# UCirKitBreadboardWithEverything2.net
KiCad netlist of a schematic drawn in EAGLE
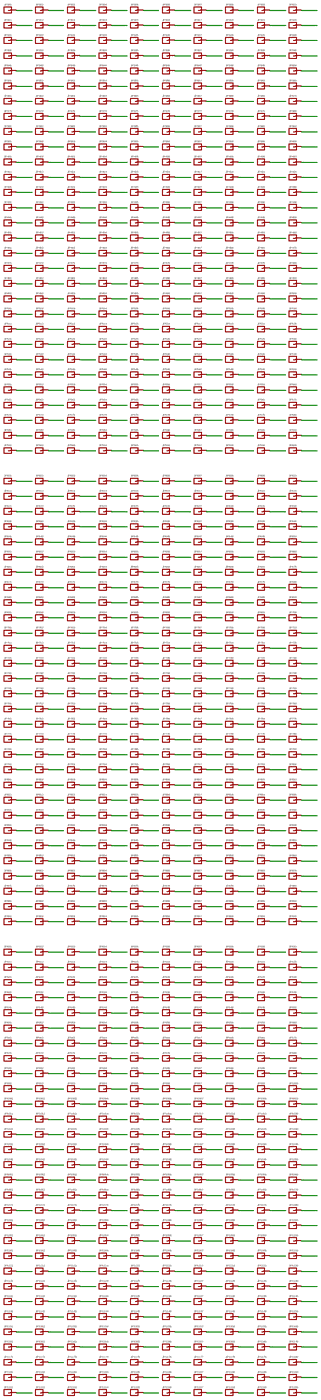
[diagram p0: schematic, sheet 1, overview]
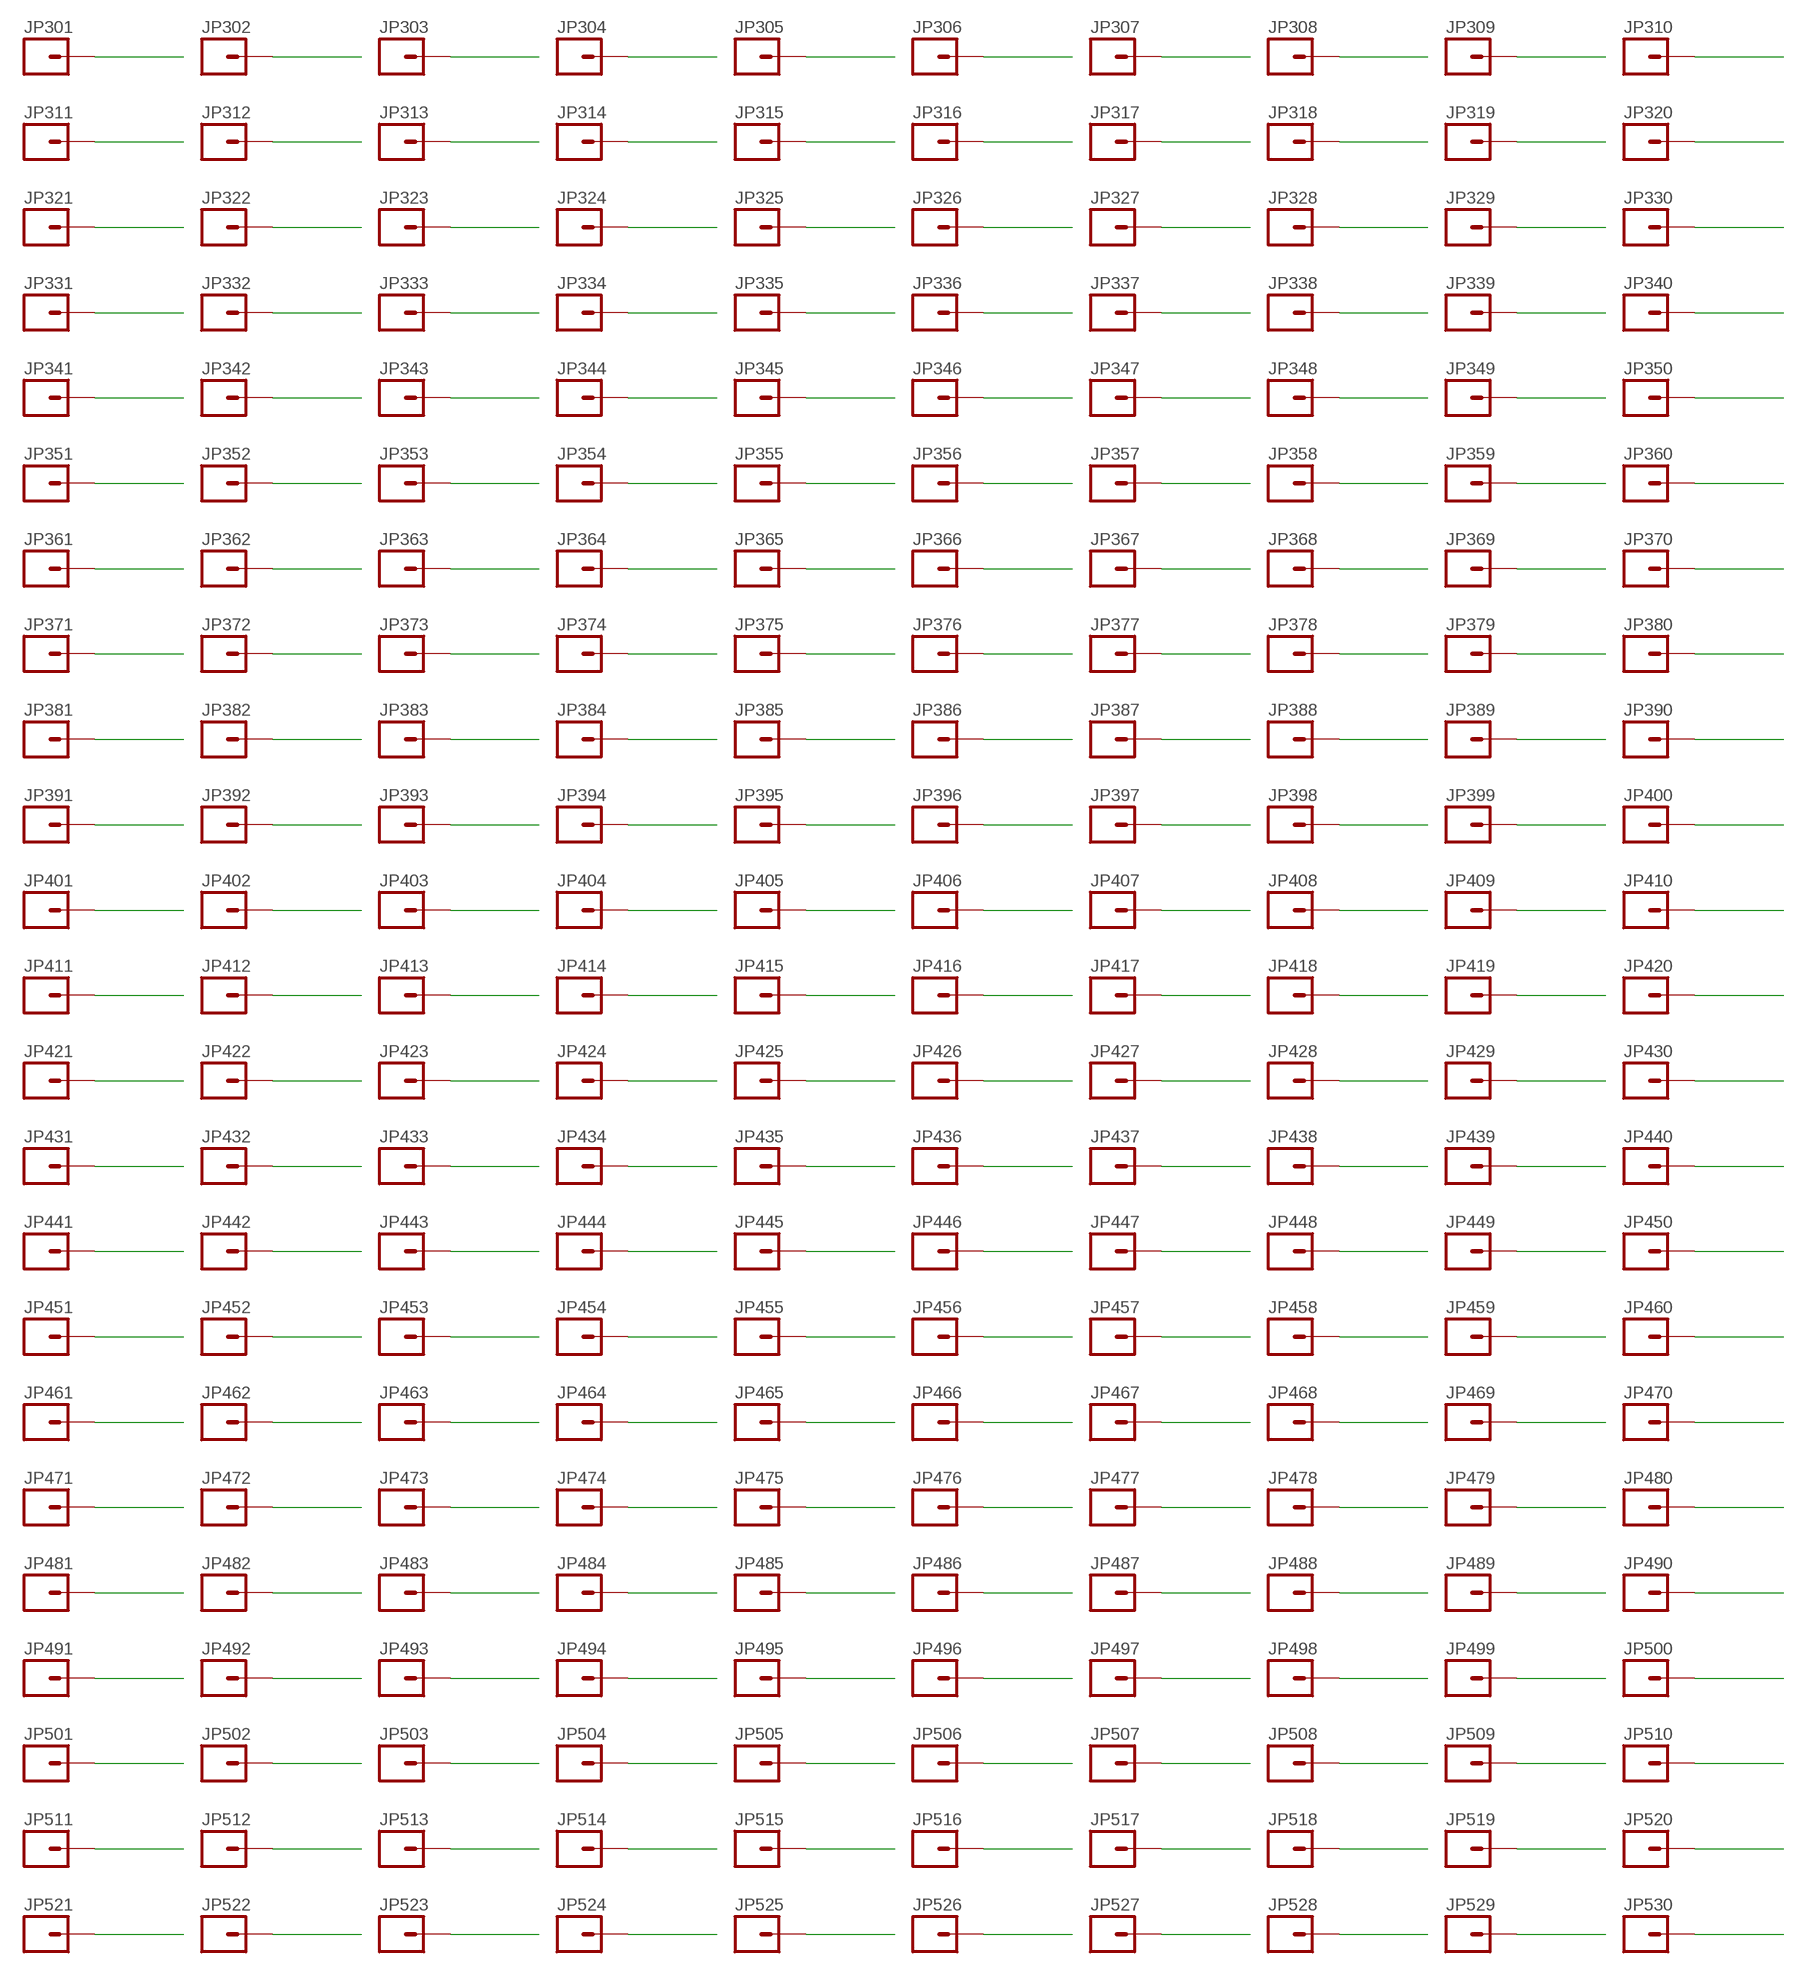
[diagram p1: schematic, sheet 1, part 1 of 4]
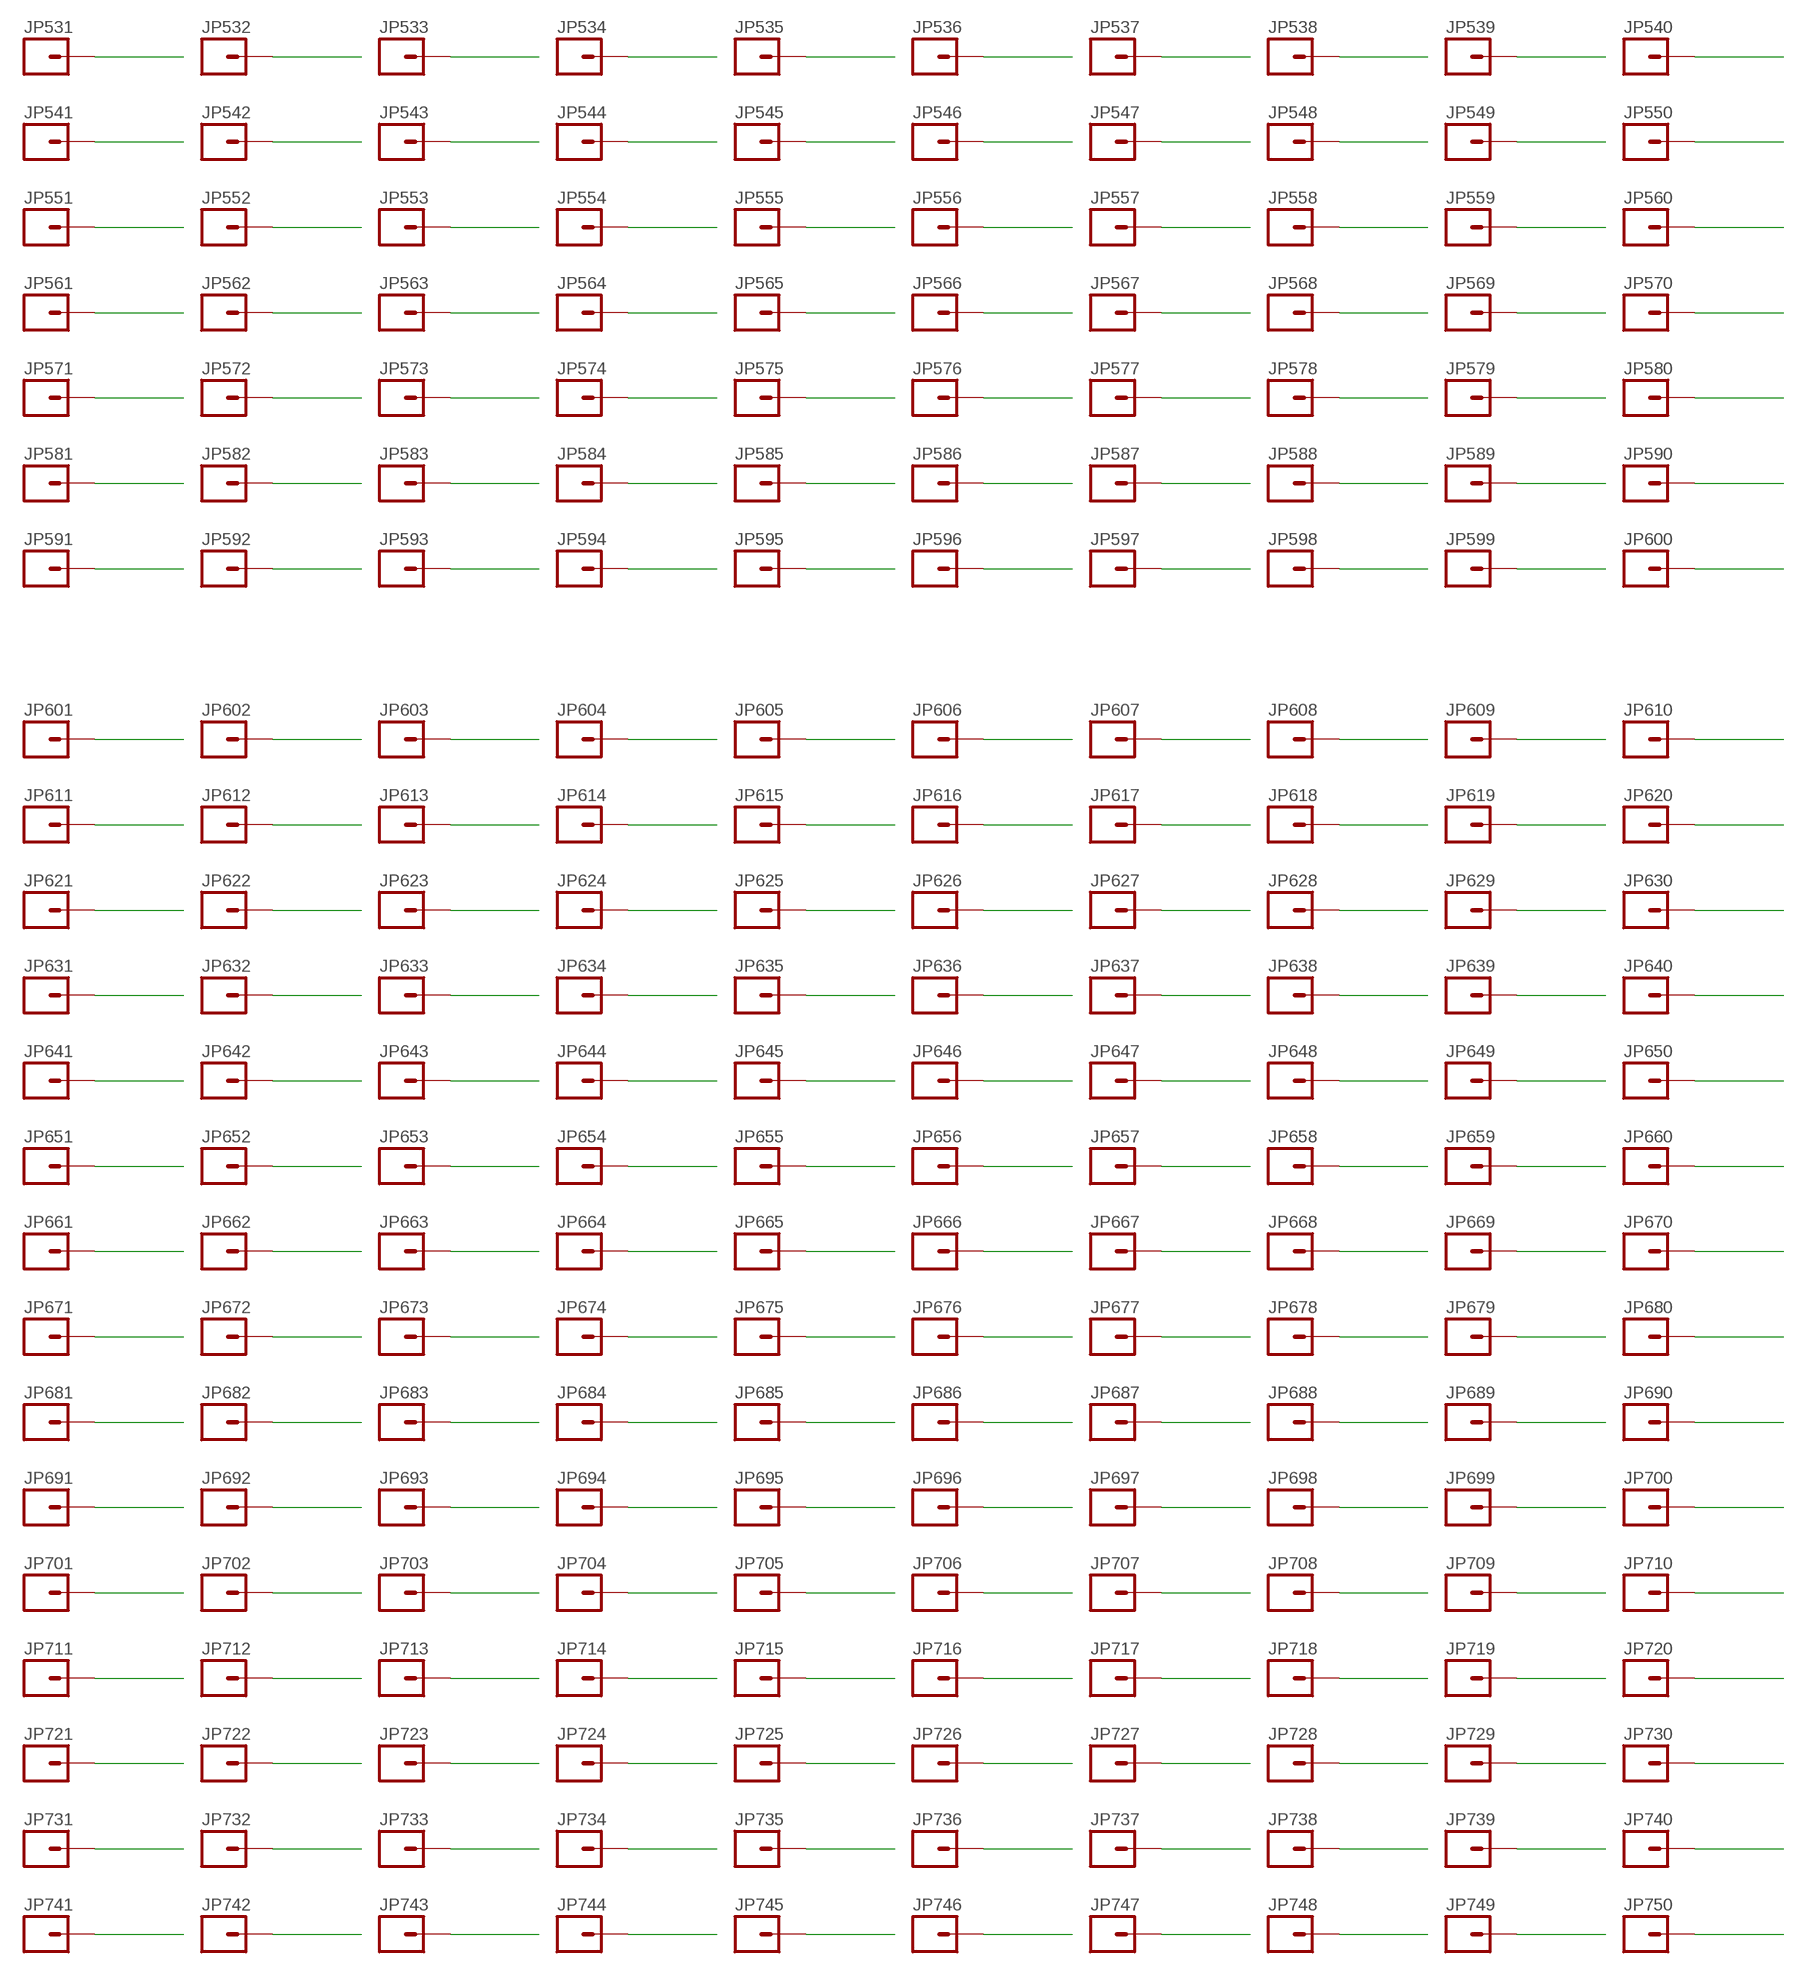
[diagram p2: schematic, sheet 1, part 2 of 4]
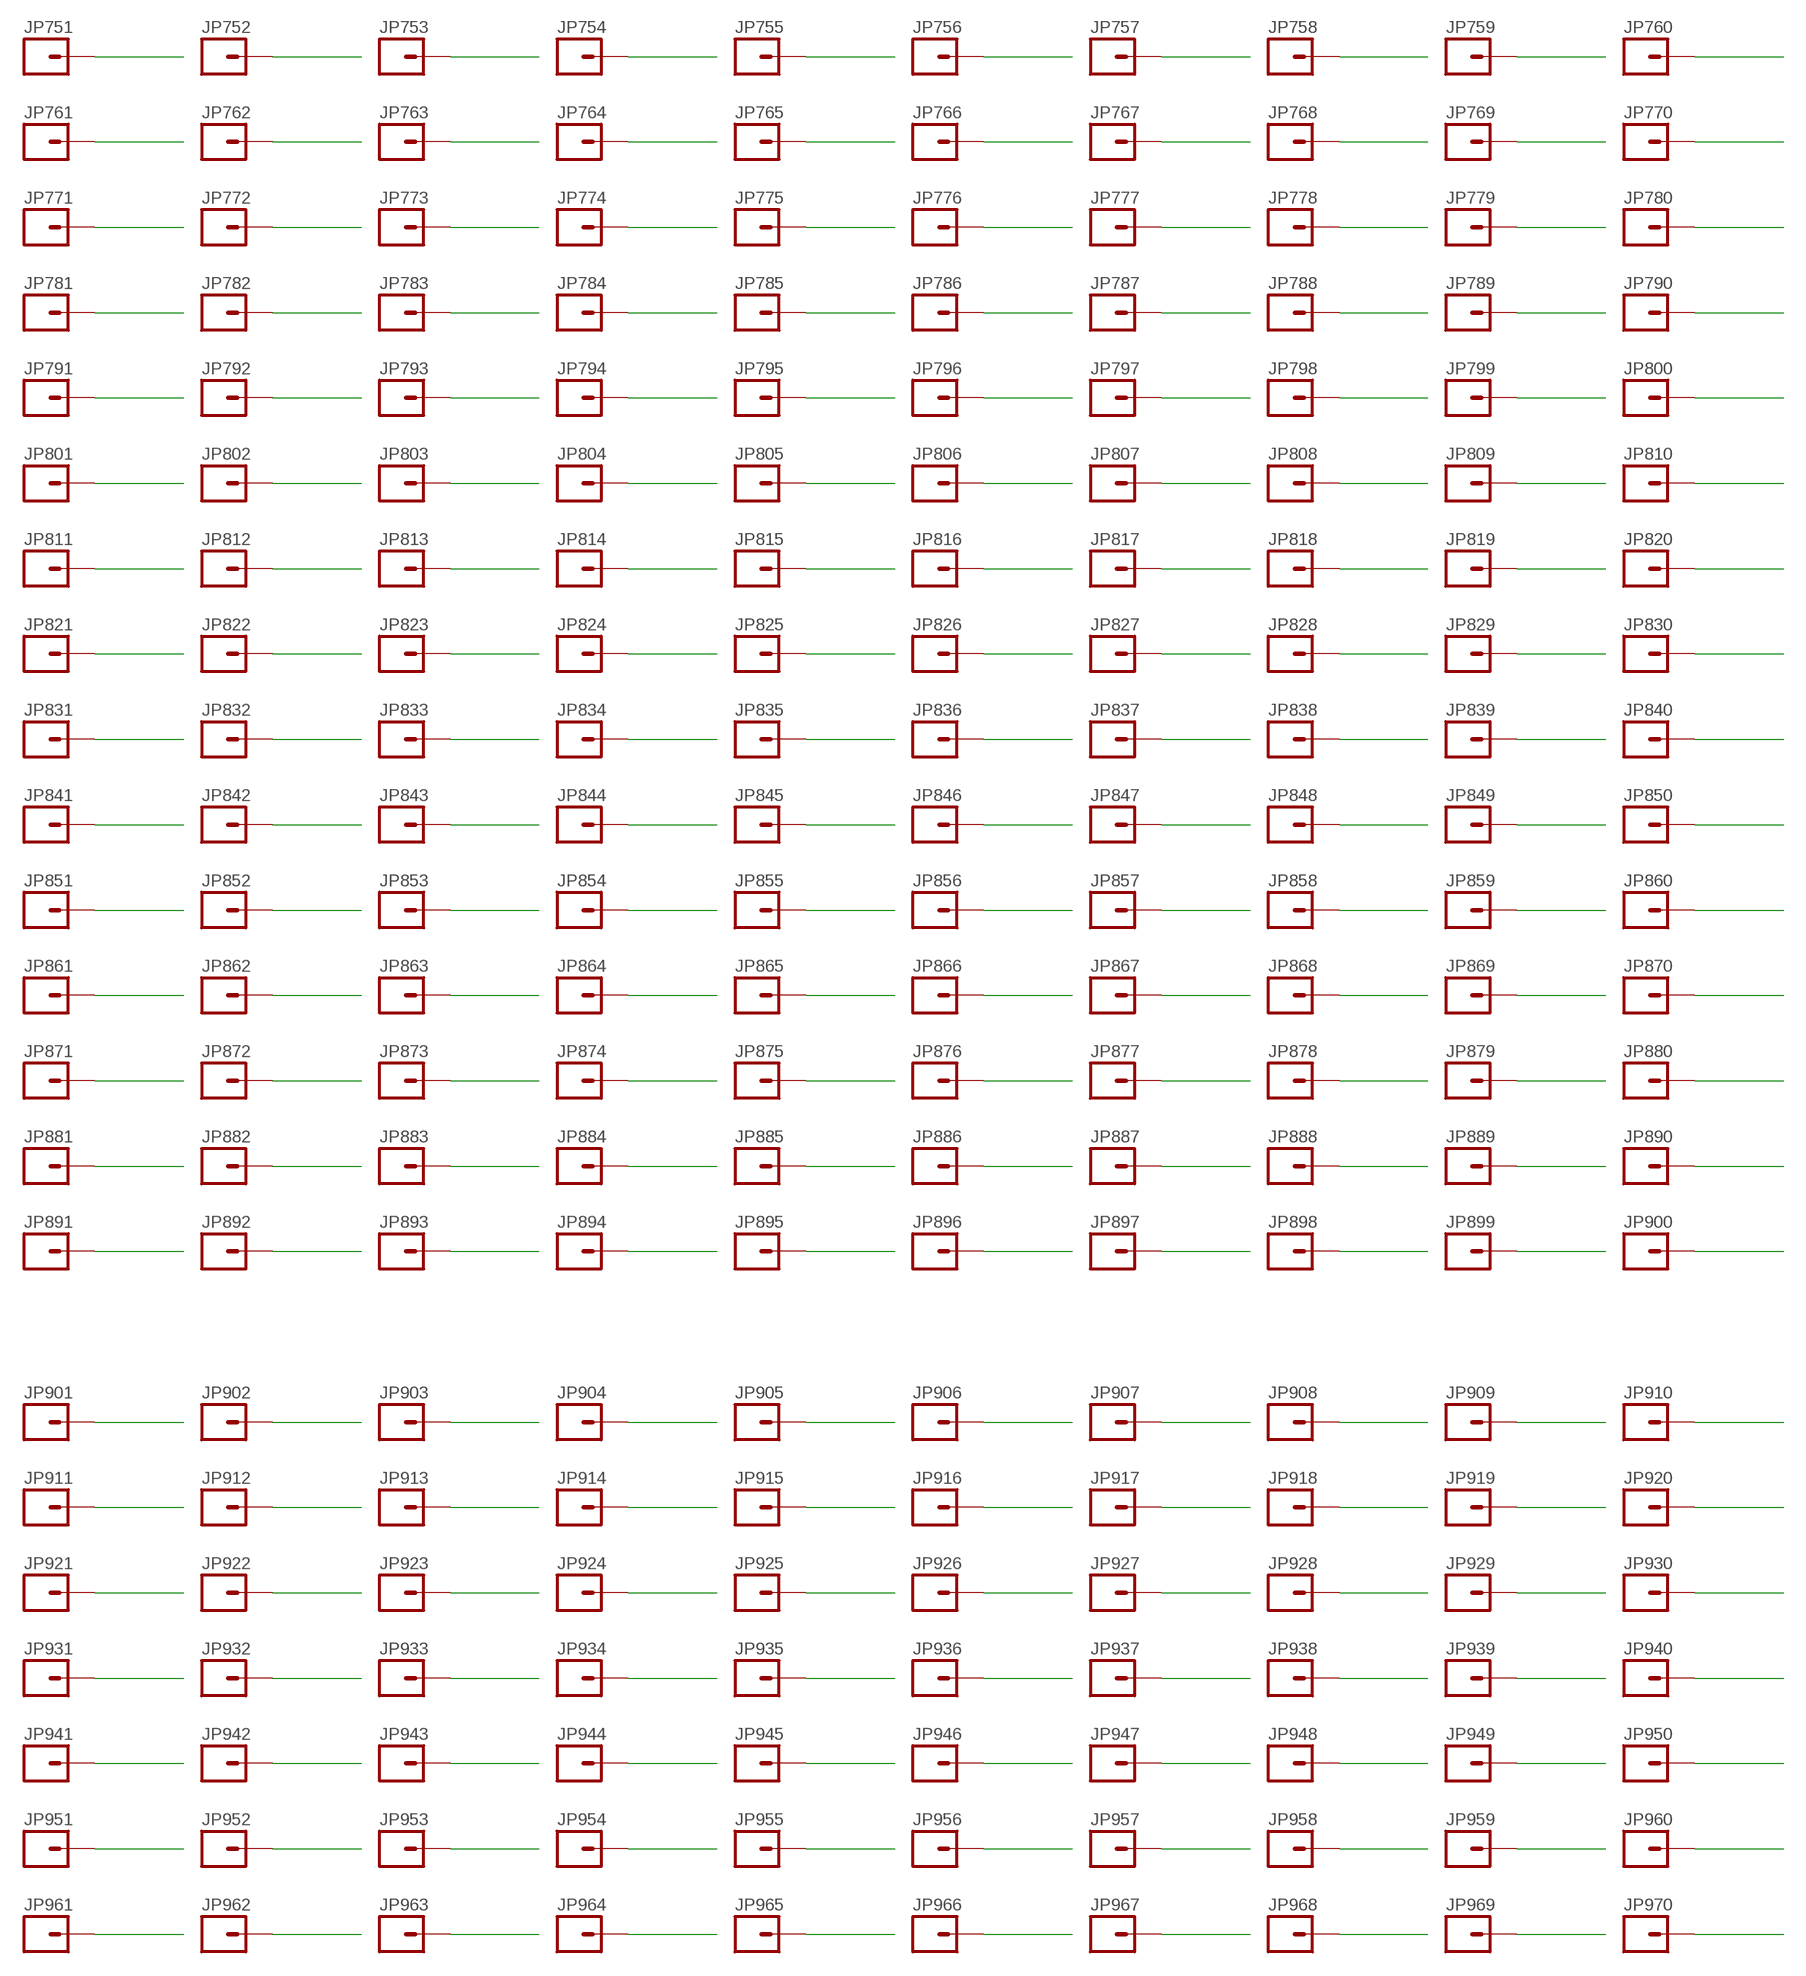
[diagram p3: schematic, sheet 1, part 3 of 4]
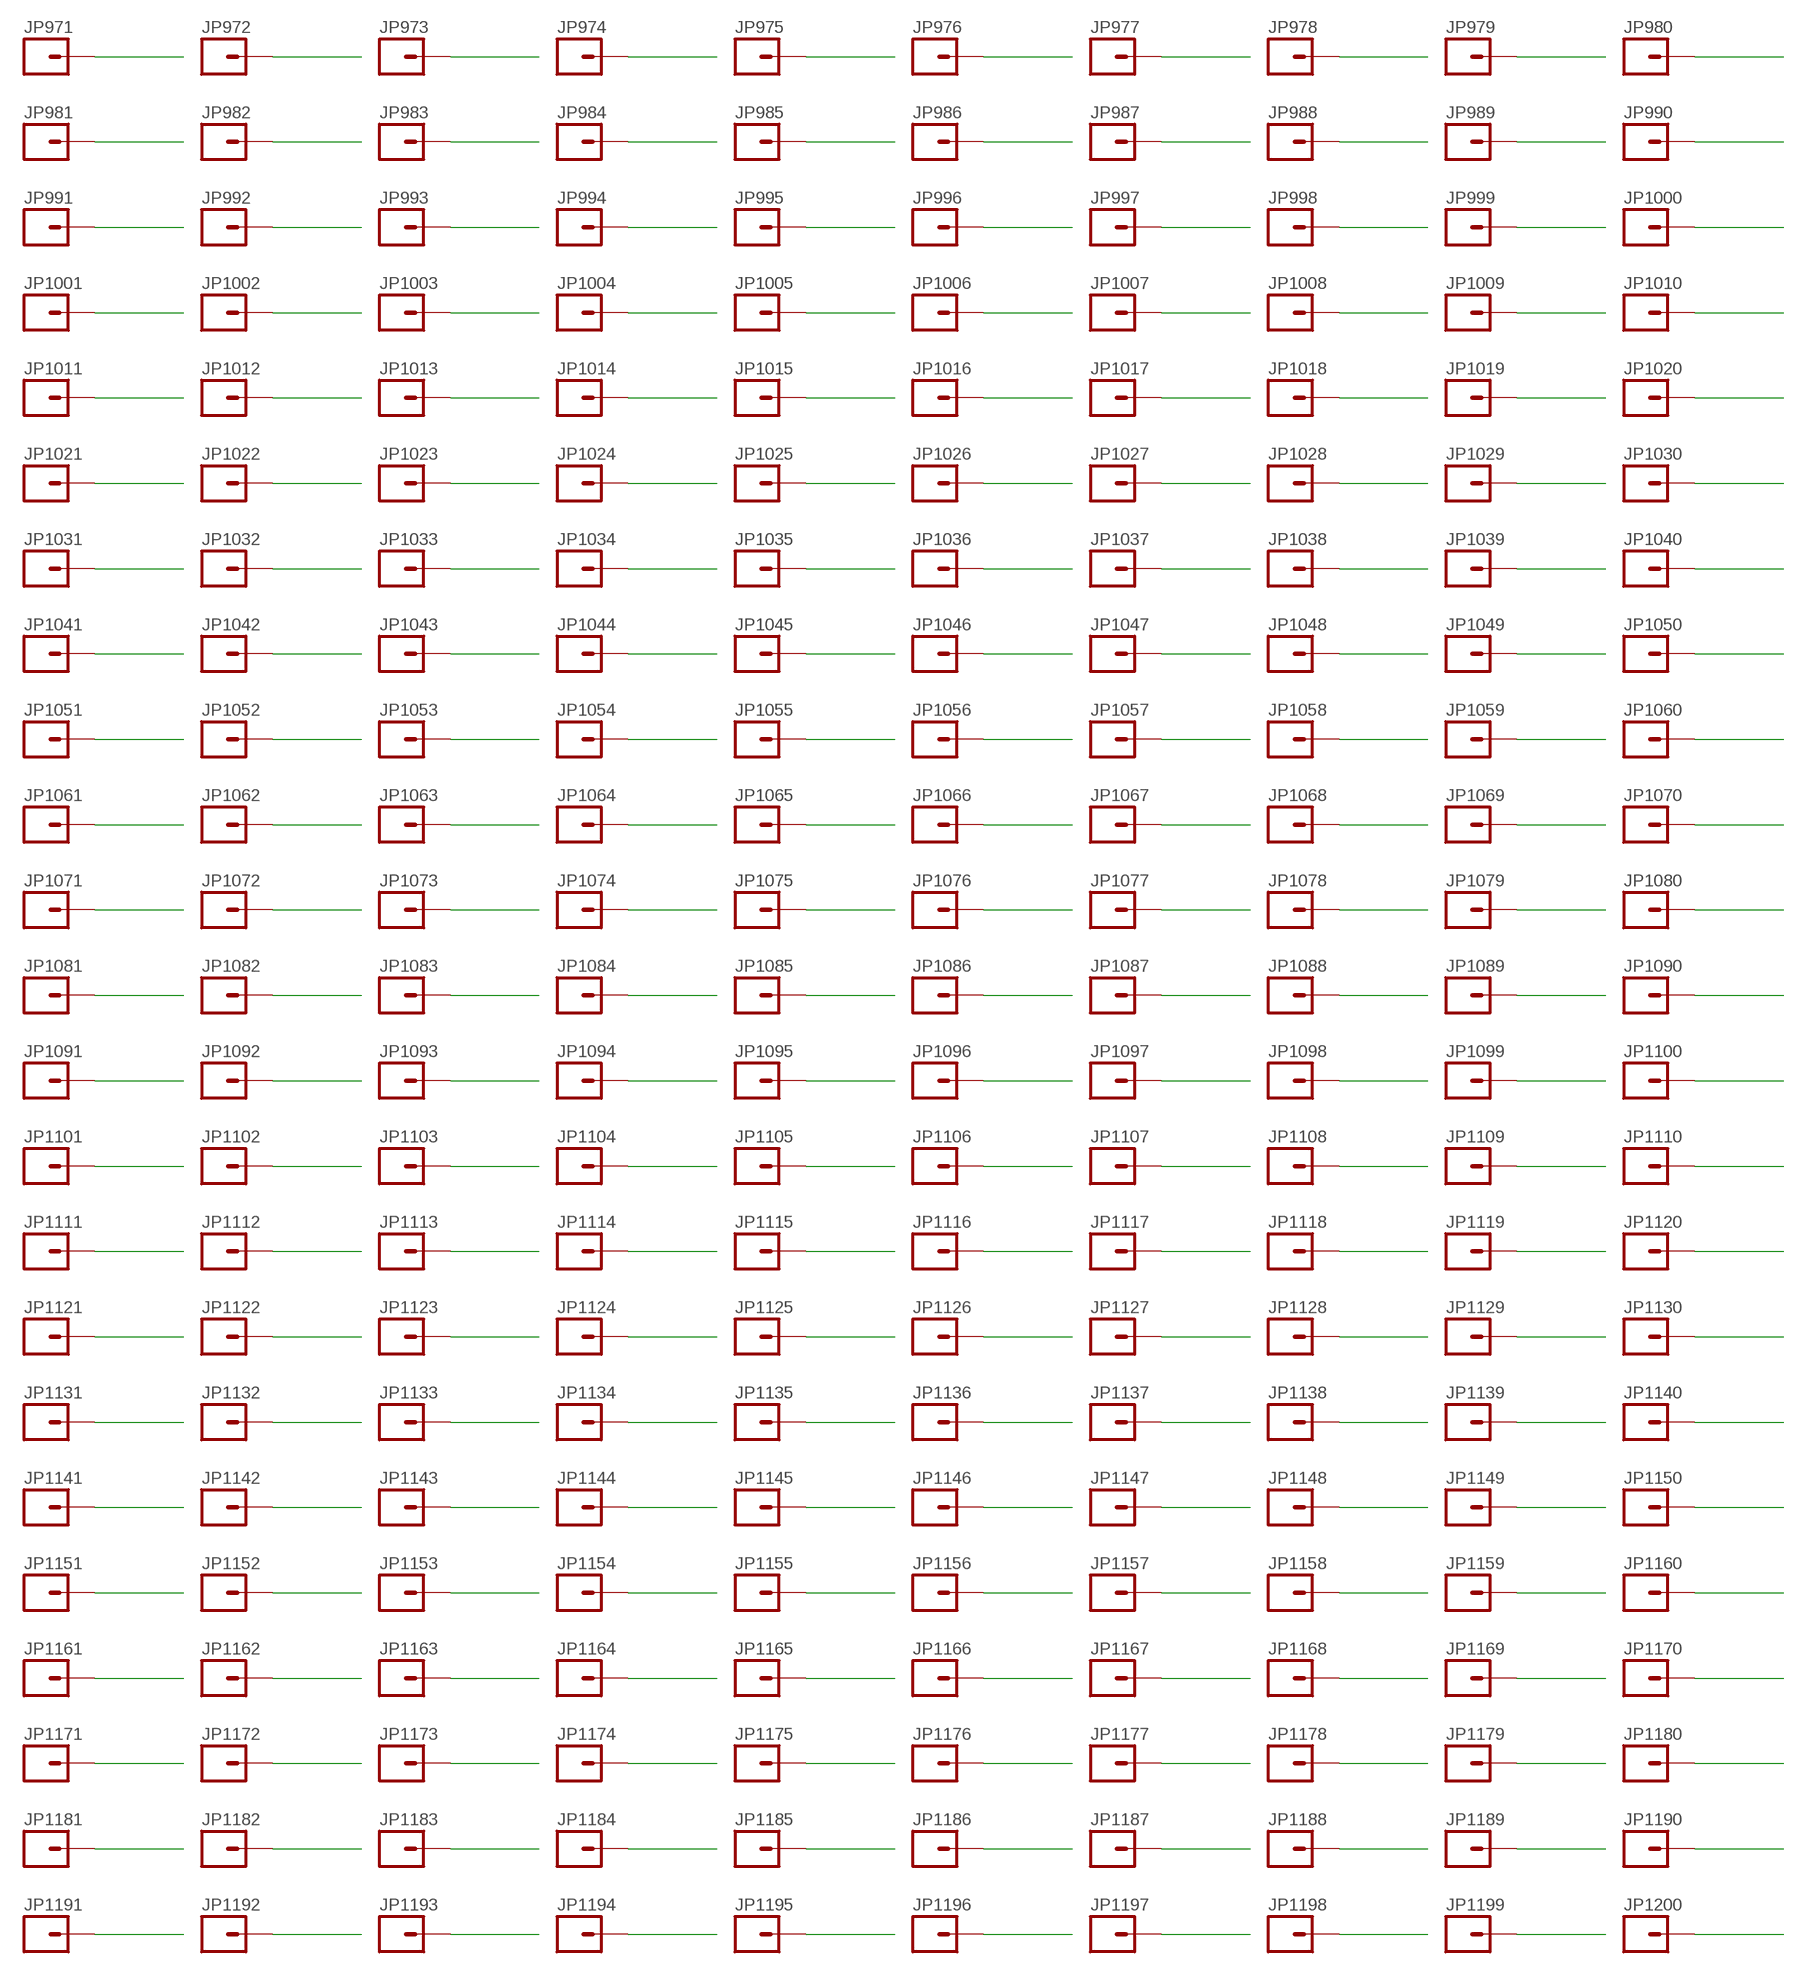
[diagram p4: schematic, sheet 1, part 4 of 4]

(export (version "E")
  (design (tool "Eeschema 10.0.6"))
  (components
    (comp (ref "JP301")
      (value "M01PTH_SMD_3.25X0.85MM_NO_SILK")
      (footprint "eagle-import:1X01_SMD_3.25X0.85MM_NO_SILK")
      (libsource (lib "eagle-import") (part "M01PTH_SMD_3.25X0.85MM_NO_SILK"))
    )
    (comp (ref "JP302")
      (value "M01PTH_SMD_3.25X0.85MM_NO_SILK")
      (footprint "eagle-import:1X01_SMD_3.25X0.85MM_NO_SILK")
      (libsource (lib "eagle-import") (part "M01PTH_SMD_3.25X0.85MM_NO_SILK"))
    )
    (comp (ref "JP303")
      (value "M01PTH_SMD_3.25X0.85MM_NO_SILK")
      (footprint "eagle-import:1X01_SMD_3.25X0.85MM_NO_SILK")
      (libsource (lib "eagle-import") (part "M01PTH_SMD_3.25X0.85MM_NO_SILK"))
    )
    (comp (ref "JP304")
      (value "M01PTH_SMD_3.25X0.85MM_NO_SILK")
      (footprint "eagle-import:1X01_SMD_3.25X0.85MM_NO_SILK")
      (libsource (lib "eagle-import") (part "M01PTH_SMD_3.25X0.85MM_NO_SILK"))
    )
    (comp (ref "JP305")
      (value "M01PTH_SMD_3.25X0.85MM_NO_SILK")
      (footprint "eagle-import:1X01_SMD_3.25X0.85MM_NO_SILK")
      (libsource (lib "eagle-import") (part "M01PTH_SMD_3.25X0.85MM_NO_SILK"))
    )
    (comp (ref "JP306")
      (value "M01PTH_SMD_3.25X0.85MM_NO_SILK")
      (footprint "eagle-import:1X01_SMD_3.25X0.85MM_NO_SILK")
      (libsource (lib "eagle-import") (part "M01PTH_SMD_3.25X0.85MM_NO_SILK"))
    )
    (comp (ref "JP307")
      (value "M01PTH_SMD_3.25X0.85MM_NO_SILK")
      (footprint "eagle-import:1X01_SMD_3.25X0.85MM_NO_SILK")
      (libsource (lib "eagle-import") (part "M01PTH_SMD_3.25X0.85MM_NO_SILK"))
    )
    (comp (ref "JP308")
      (value "M01PTH_SMD_3.25X0.85MM_NO_SILK")
      (footprint "eagle-import:1X01_SMD_3.25X0.85MM_NO_SILK")
      (libsource (lib "eagle-import") (part "M01PTH_SMD_3.25X0.85MM_NO_SILK"))
    )
    (comp (ref "JP309")
      (value "M01PTH_SMD_3.25X0.85MM_NO_SILK")
      (footprint "eagle-import:1X01_SMD_3.25X0.85MM_NO_SILK")
      (libsource (lib "eagle-import") (part "M01PTH_SMD_3.25X0.85MM_NO_SILK"))
    )
    (comp (ref "JP310")
      (value "M01PTH_SMD_3.25X0.85MM_NO_SILK")
      (footprint "eagle-import:1X01_SMD_3.25X0.85MM_NO_SILK")
      (libsource (lib "eagle-import") (part "M01PTH_SMD_3.25X0.85MM_NO_SILK"))
    )
    (comp (ref "JP311")
      (value "M01PTH_SMD_3.25X0.85MM_NO_SILK")
      (footprint "eagle-import:1X01_SMD_3.25X0.85MM_NO_SILK")
      (libsource (lib "eagle-import") (part "M01PTH_SMD_3.25X0.85MM_NO_SILK"))
    )
    (comp (ref "JP312")
      (value "M01PTH_SMD_3.25X0.85MM_NO_SILK")
      (footprint "eagle-import:1X01_SMD_3.25X0.85MM_NO_SILK")
      (libsource (lib "eagle-import") (part "M01PTH_SMD_3.25X0.85MM_NO_SILK"))
    )
    (comp (ref "JP313")
      (value "M01PTH_SMD_3.25X0.85MM_NO_SILK")
      (footprint "eagle-import:1X01_SMD_3.25X0.85MM_NO_SILK")
      (libsource (lib "eagle-import") (part "M01PTH_SMD_3.25X0.85MM_NO_SILK"))
    )
    (comp (ref "JP314")
      (value "M01PTH_SMD_3.25X0.85MM_NO_SILK")
      (footprint "eagle-import:1X01_SMD_3.25X0.85MM_NO_SILK")
      (libsource (lib "eagle-import") (part "M01PTH_SMD_3.25X0.85MM_NO_SILK"))
    )
    (comp (ref "JP315")
      (value "M01PTH_SMD_3.25X0.85MM_NO_SILK")
      (footprint "eagle-import:1X01_SMD_3.25X0.85MM_NO_SILK")
      (libsource (lib "eagle-import") (part "M01PTH_SMD_3.25X0.85MM_NO_SILK"))
    )
    (comp (ref "JP316")
      (value "M01PTH_SMD_3.25X0.85MM_NO_SILK")
      (footprint "eagle-import:1X01_SMD_3.25X0.85MM_NO_SILK")
      (libsource (lib "eagle-import") (part "M01PTH_SMD_3.25X0.85MM_NO_SILK"))
    )
    (comp (ref "JP317")
      (value "M01PTH_SMD_3.25X0.85MM_NO_SILK")
      (footprint "eagle-import:1X01_SMD_3.25X0.85MM_NO_SILK")
      (libsource (lib "eagle-import") (part "M01PTH_SMD_3.25X0.85MM_NO_SILK"))
    )
    (comp (ref "JP318")
      (value "M01PTH_SMD_3.25X0.85MM_NO_SILK")
      (footprint "eagle-import:1X01_SMD_3.25X0.85MM_NO_SILK")
      (libsource (lib "eagle-import") (part "M01PTH_SMD_3.25X0.85MM_NO_SILK"))
    )
    (comp (ref "JP319")
      (value "M01PTH_SMD_3.25X0.85MM_NO_SILK")
      (footprint "eagle-import:1X01_SMD_3.25X0.85MM_NO_SILK")
      (libsource (lib "eagle-import") (part "M01PTH_SMD_3.25X0.85MM_NO_SILK"))
    )
    (comp (ref "JP320")
      (value "M01PTH_SMD_3.25X0.85MM_NO_SILK")
      (footprint "eagle-import:1X01_SMD_3.25X0.85MM_NO_SILK")
      (libsource (lib "eagle-import") (part "M01PTH_SMD_3.25X0.85MM_NO_SILK"))
    )
    (comp (ref "JP321")
      (value "M01PTH_SMD_3.25X0.85MM_NO_SILK")
      (footprint "eagle-import:1X01_SMD_3.25X0.85MM_NO_SILK")
      (libsource (lib "eagle-import") (part "M01PTH_SMD_3.25X0.85MM_NO_SILK"))
    )
    (comp (ref "JP322")
      (value "M01PTH_SMD_3.25X0.85MM_NO_SILK")
      (footprint "eagle-import:1X01_SMD_3.25X0.85MM_NO_SILK")
      (libsource (lib "eagle-import") (part "M01PTH_SMD_3.25X0.85MM_NO_SILK"))
    )
    (comp (ref "JP323")
      (value "M01PTH_SMD_3.25X0.85MM_NO_SILK")
      (footprint "eagle-import:1X01_SMD_3.25X0.85MM_NO_SILK")
      (libsource (lib "eagle-import") (part "M01PTH_SMD_3.25X0.85MM_NO_SILK"))
    )
    (comp (ref "JP324")
      (value "M01PTH_SMD_3.25X0.85MM_NO_SILK")
      (footprint "eagle-import:1X01_SMD_3.25X0.85MM_NO_SILK")
      (libsource (lib "eagle-import") (part "M01PTH_SMD_3.25X0.85MM_NO_SILK"))
    )
    (comp (ref "JP325")
      (value "M01PTH_SMD_3.25X0.85MM_NO_SILK")
      (footprint "eagle-import:1X01_SMD_3.25X0.85MM_NO_SILK")
      (libsource (lib "eagle-import") (part "M01PTH_SMD_3.25X0.85MM_NO_SILK"))
    )
    (comp (ref "JP326")
      (value "M01PTH_SMD_3.25X0.85MM_NO_SILK")
      (footprint "eagle-import:1X01_SMD_3.25X0.85MM_NO_SILK")
      (libsource (lib "eagle-import") (part "M01PTH_SMD_3.25X0.85MM_NO_SILK"))
    )
    (comp (ref "JP327")
      (value "M01PTH_SMD_3.25X0.85MM_NO_SILK")
      (footprint "eagle-import:1X01_SMD_3.25X0.85MM_NO_SILK")
      (libsource (lib "eagle-import") (part "M01PTH_SMD_3.25X0.85MM_NO_SILK"))
    )
    (comp (ref "JP328")
      (value "M01PTH_SMD_3.25X0.85MM_NO_SILK")
      (footprint "eagle-import:1X01_SMD_3.25X0.85MM_NO_SILK")
      (libsource (lib "eagle-import") (part "M01PTH_SMD_3.25X0.85MM_NO_SILK"))
    )
    (comp (ref "JP329")
      (value "M01PTH_SMD_3.25X0.85MM_NO_SILK")
      (footprint "eagle-import:1X01_SMD_3.25X0.85MM_NO_SILK")
      (libsource (lib "eagle-import") (part "M01PTH_SMD_3.25X0.85MM_NO_SILK"))
    )
    (comp (ref "JP330")
      (value "M01PTH_SMD_3.25X0.85MM_NO_SILK")
      (footprint "eagle-import:1X01_SMD_3.25X0.85MM_NO_SILK")
      (libsource (lib "eagle-import") (part "M01PTH_SMD_3.25X0.85MM_NO_SILK"))
    )
    (comp (ref "JP331")
      (value "M01PTH_SMD_3.25X0.85MM_NO_SILK")
      (footprint "eagle-import:1X01_SMD_3.25X0.85MM_NO_SILK")
      (libsource (lib "eagle-import") (part "M01PTH_SMD_3.25X0.85MM_NO_SILK"))
    )
    (comp (ref "JP332")
      (value "M01PTH_SMD_3.25X0.85MM_NO_SILK")
      (footprint "eagle-import:1X01_SMD_3.25X0.85MM_NO_SILK")
      (libsource (lib "eagle-import") (part "M01PTH_SMD_3.25X0.85MM_NO_SILK"))
    )
    (comp (ref "JP333")
      (value "M01PTH_SMD_3.25X0.85MM_NO_SILK")
      (footprint "eagle-import:1X01_SMD_3.25X0.85MM_NO_SILK")
      (libsource (lib "eagle-import") (part "M01PTH_SMD_3.25X0.85MM_NO_SILK"))
    )
    (comp (ref "JP334")
      (value "M01PTH_SMD_3.25X0.85MM_NO_SILK")
      (footprint "eagle-import:1X01_SMD_3.25X0.85MM_NO_SILK")
      (libsource (lib "eagle-import") (part "M01PTH_SMD_3.25X0.85MM_NO_SILK"))
    )
    (comp (ref "JP335")
      (value "M01PTH_SMD_3.25X0.85MM_NO_SILK")
      (footprint "eagle-import:1X01_SMD_3.25X0.85MM_NO_SILK")
      (libsource (lib "eagle-import") (part "M01PTH_SMD_3.25X0.85MM_NO_SILK"))
    )
    (comp (ref "JP336")
      (value "M01PTH_SMD_3.25X0.85MM_NO_SILK")
      (footprint "eagle-import:1X01_SMD_3.25X0.85MM_NO_SILK")
      (libsource (lib "eagle-import") (part "M01PTH_SMD_3.25X0.85MM_NO_SILK"))
    )
    (comp (ref "JP337")
      (value "M01PTH_SMD_3.25X0.85MM_NO_SILK")
      (footprint "eagle-import:1X01_SMD_3.25X0.85MM_NO_SILK")
      (libsource (lib "eagle-import") (part "M01PTH_SMD_3.25X0.85MM_NO_SILK"))
    )
    (comp (ref "JP338")
      (value "M01PTH_SMD_3.25X0.85MM_NO_SILK")
      (footprint "eagle-import:1X01_SMD_3.25X0.85MM_NO_SILK")
      (libsource (lib "eagle-import") (part "M01PTH_SMD_3.25X0.85MM_NO_SILK"))
    )
    (comp (ref "JP339")
      (value "M01PTH_SMD_3.25X0.85MM_NO_SILK")
      (footprint "eagle-import:1X01_SMD_3.25X0.85MM_NO_SILK")
      (libsource (lib "eagle-import") (part "M01PTH_SMD_3.25X0.85MM_NO_SILK"))
    )
    (comp (ref "JP340")
      (value "M01PTH_SMD_3.25X0.85MM_NO_SILK")
      (footprint "eagle-import:1X01_SMD_3.25X0.85MM_NO_SILK")
      (libsource (lib "eagle-import") (part "M01PTH_SMD_3.25X0.85MM_NO_SILK"))
    )
    (comp (ref "JP341")
      (value "M01PTH_SMD_3.25X0.85MM_NO_SILK")
      (footprint "eagle-import:1X01_SMD_3.25X0.85MM_NO_SILK")
      (libsource (lib "eagle-import") (part "M01PTH_SMD_3.25X0.85MM_NO_SILK"))
    )
    (comp (ref "JP342")
      (value "M01PTH_SMD_3.25X0.85MM_NO_SILK")
      (footprint "eagle-import:1X01_SMD_3.25X0.85MM_NO_SILK")
      (libsource (lib "eagle-import") (part "M01PTH_SMD_3.25X0.85MM_NO_SILK"))
    )
    (comp (ref "JP343")
      (value "M01PTH_SMD_3.25X0.85MM_NO_SILK")
      (footprint "eagle-import:1X01_SMD_3.25X0.85MM_NO_SILK")
      (libsource (lib "eagle-import") (part "M01PTH_SMD_3.25X0.85MM_NO_SILK"))
    )
    (comp (ref "JP344")
      (value "M01PTH_SMD_3.25X0.85MM_NO_SILK")
      (footprint "eagle-import:1X01_SMD_3.25X0.85MM_NO_SILK")
      (libsource (lib "eagle-import") (part "M01PTH_SMD_3.25X0.85MM_NO_SILK"))
    )
    (comp (ref "JP345")
      (value "M01PTH_SMD_3.25X0.85MM_NO_SILK")
      (footprint "eagle-import:1X01_SMD_3.25X0.85MM_NO_SILK")
      (libsource (lib "eagle-import") (part "M01PTH_SMD_3.25X0.85MM_NO_SILK"))
    )
    (comp (ref "JP346")
      (value "M01PTH_SMD_3.25X0.85MM_NO_SILK")
      (footprint "eagle-import:1X01_SMD_3.25X0.85MM_NO_SILK")
      (libsource (lib "eagle-import") (part "M01PTH_SMD_3.25X0.85MM_NO_SILK"))
    )
    (comp (ref "JP347")
      (value "M01PTH_SMD_3.25X0.85MM_NO_SILK")
      (footprint "eagle-import:1X01_SMD_3.25X0.85MM_NO_SILK")
      (libsource (lib "eagle-import") (part "M01PTH_SMD_3.25X0.85MM_NO_SILK"))
    )
    (comp (ref "JP348")
      (value "M01PTH_SMD_3.25X0.85MM_NO_SILK")
      (footprint "eagle-import:1X01_SMD_3.25X0.85MM_NO_SILK")
      (libsource (lib "eagle-import") (part "M01PTH_SMD_3.25X0.85MM_NO_SILK"))
    )
    (comp (ref "JP349")
      (value "M01PTH_SMD_3.25X0.85MM_NO_SILK")
      (footprint "eagle-import:1X01_SMD_3.25X0.85MM_NO_SILK")
      (libsource (lib "eagle-import") (part "M01PTH_SMD_3.25X0.85MM_NO_SILK"))
    )
    (comp (ref "JP350")
      (value "M01PTH_SMD_3.25X0.85MM_NO_SILK")
      (footprint "eagle-import:1X01_SMD_3.25X0.85MM_NO_SILK")
      (libsource (lib "eagle-import") (part "M01PTH_SMD_3.25X0.85MM_NO_SILK"))
    )
    (comp (ref "JP351")
      (value "M01PTH_SMD_3.25X0.85MM_NO_SILK")
      (footprint "eagle-import:1X01_SMD_3.25X0.85MM_NO_SILK")
      (libsource (lib "eagle-import") (part "M01PTH_SMD_3.25X0.85MM_NO_SILK"))
    )
    (comp (ref "JP352")
      (value "M01PTH_SMD_3.25X0.85MM_NO_SILK")
      (footprint "eagle-import:1X01_SMD_3.25X0.85MM_NO_SILK")
      (libsource (lib "eagle-import") (part "M01PTH_SMD_3.25X0.85MM_NO_SILK"))
    )
    (comp (ref "JP353")
      (value "M01PTH_SMD_3.25X0.85MM_NO_SILK")
      (footprint "eagle-import:1X01_SMD_3.25X0.85MM_NO_SILK")
      (libsource (lib "eagle-import") (part "M01PTH_SMD_3.25X0.85MM_NO_SILK"))
    )
    (comp (ref "JP354")
      (value "M01PTH_SMD_3.25X0.85MM_NO_SILK")
      (footprint "eagle-import:1X01_SMD_3.25X0.85MM_NO_SILK")
      (libsource (lib "eagle-import") (part "M01PTH_SMD_3.25X0.85MM_NO_SILK"))
    )
    (comp (ref "JP355")
      (value "M01PTH_SMD_3.25X0.85MM_NO_SILK")
      (footprint "eagle-import:1X01_SMD_3.25X0.85MM_NO_SILK")
      (libsource (lib "eagle-import") (part "M01PTH_SMD_3.25X0.85MM_NO_SILK"))
    )
    (comp (ref "JP356")
      (value "M01PTH_SMD_3.25X0.85MM_NO_SILK")
      (footprint "eagle-import:1X01_SMD_3.25X0.85MM_NO_SILK")
      (libsource (lib "eagle-import") (part "M01PTH_SMD_3.25X0.85MM_NO_SILK"))
    )
    (comp (ref "JP357")
      (value "M01PTH_SMD_3.25X0.85MM_NO_SILK")
      (footprint "eagle-import:1X01_SMD_3.25X0.85MM_NO_SILK")
      (libsource (lib "eagle-import") (part "M01PTH_SMD_3.25X0.85MM_NO_SILK"))
    )
    (comp (ref "JP358")
      (value "M01PTH_SMD_3.25X0.85MM_NO_SILK")
      (footprint "eagle-import:1X01_SMD_3.25X0.85MM_NO_SILK")
      (libsource (lib "eagle-import") (part "M01PTH_SMD_3.25X0.85MM_NO_SILK"))
    )
    (comp (ref "JP359")
      (value "M01PTH_SMD_3.25X0.85MM_NO_SILK")
      (footprint "eagle-import:1X01_SMD_3.25X0.85MM_NO_SILK")
      (libsource (lib "eagle-import") (part "M01PTH_SMD_3.25X0.85MM_NO_SILK"))
    )
    (comp (ref "JP360")
      (value "M01PTH_SMD_3.25X0.85MM_NO_SILK")
      (footprint "eagle-import:1X01_SMD_3.25X0.85MM_NO_SILK")
      (libsource (lib "eagle-import") (part "M01PTH_SMD_3.25X0.85MM_NO_SILK"))
    )
    (comp (ref "JP361")
      (value "M01PTH_SMD_3.25X0.85MM_NO_SILK")
      (footprint "eagle-import:1X01_SMD_3.25X0.85MM_NO_SILK")
      (libsource (lib "eagle-import") (part "M01PTH_SMD_3.25X0.85MM_NO_SILK"))
    )
    (comp (ref "JP362")
      (value "M01PTH_SMD_3.25X0.85MM_NO_SILK")
      (footprint "eagle-import:1X01_SMD_3.25X0.85MM_NO_SILK")
      (libsource (lib "eagle-import") (part "M01PTH_SMD_3.25X0.85MM_NO_SILK"))
    )
    (comp (ref "JP363")
      (value "M01PTH_SMD_3.25X0.85MM_NO_SILK")
      (footprint "eagle-import:1X01_SMD_3.25X0.85MM_NO_SILK")
      (libsource (lib "eagle-import") (part "M01PTH_SMD_3.25X0.85MM_NO_SILK"))
    )
    (comp (ref "JP364")
      (value "M01PTH_SMD_3.25X0.85MM_NO_SILK")
      (footprint "eagle-import:1X01_SMD_3.25X0.85MM_NO_SILK")
      (libsource (lib "eagle-import") (part "M01PTH_SMD_3.25X0.85MM_NO_SILK"))
    )
    (comp (ref "JP365")
      (value "M01PTH_SMD_3.25X0.85MM_NO_SILK")
      (footprint "eagle-import:1X01_SMD_3.25X0.85MM_NO_SILK")
      (libsource (lib "eagle-import") (part "M01PTH_SMD_3.25X0.85MM_NO_SILK"))
    )
    (comp (ref "JP366")
      (value "M01PTH_SMD_3.25X0.85MM_NO_SILK")
      (footprint "eagle-import:1X01_SMD_3.25X0.85MM_NO_SILK")
      (libsource (lib "eagle-import") (part "M01PTH_SMD_3.25X0.85MM_NO_SILK"))
    )
    (comp (ref "JP367")
      (value "M01PTH_SMD_3.25X0.85MM_NO_SILK")
      (footprint "eagle-import:1X01_SMD_3.25X0.85MM_NO_SILK")
      (libsource (lib "eagle-import") (part "M01PTH_SMD_3.25X0.85MM_NO_SILK"))
    )
    (comp (ref "JP368")
      (value "M01PTH_SMD_3.25X0.85MM_NO_SILK")
      (footprint "eagle-import:1X01_SMD_3.25X0.85MM_NO_SILK")
      (libsource (lib "eagle-import") (part "M01PTH_SMD_3.25X0.85MM_NO_SILK"))
    )
    (comp (ref "JP369")
      (value "M01PTH_SMD_3.25X0.85MM_NO_SILK")
      (footprint "eagle-import:1X01_SMD_3.25X0.85MM_NO_SILK")
      (libsource (lib "eagle-import") (part "M01PTH_SMD_3.25X0.85MM_NO_SILK"))
    )
    (comp (ref "JP370")
      (value "M01PTH_SMD_3.25X0.85MM_NO_SILK")
      (footprint "eagle-import:1X01_SMD_3.25X0.85MM_NO_SILK")
      (libsource (lib "eagle-import") (part "M01PTH_SMD_3.25X0.85MM_NO_SILK"))
    )
    (comp (ref "JP371")
      (value "M01PTH_SMD_3.25X0.85MM_NO_SILK")
      (footprint "eagle-import:1X01_SMD_3.25X0.85MM_NO_SILK")
      (libsource (lib "eagle-import") (part "M01PTH_SMD_3.25X0.85MM_NO_SILK"))
    )
    (comp (ref "JP372")
      (value "M01PTH_SMD_3.25X0.85MM_NO_SILK")
      (footprint "eagle-import:1X01_SMD_3.25X0.85MM_NO_SILK")
      (libsource (lib "eagle-import") (part "M01PTH_SMD_3.25X0.85MM_NO_SILK"))
    )
    (comp (ref "JP373")
      (value "M01PTH_SMD_3.25X0.85MM_NO_SILK")
      (footprint "eagle-import:1X01_SMD_3.25X0.85MM_NO_SILK")
      (libsource (lib "eagle-import") (part "M01PTH_SMD_3.25X0.85MM_NO_SILK"))
    )
    (comp (ref "JP374")
      (value "M01PTH_SMD_3.25X0.85MM_NO_SILK")
      (footprint "eagle-import:1X01_SMD_3.25X0.85MM_NO_SILK")
      (libsource (lib "eagle-import") (part "M01PTH_SMD_3.25X0.85MM_NO_SILK"))
    )
    (comp (ref "JP375")
      (value "M01PTH_SMD_3.25X0.85MM_NO_SILK")
      (footprint "eagle-import:1X01_SMD_3.25X0.85MM_NO_SILK")
      (libsource (lib "eagle-import") (part "M01PTH_SMD_3.25X0.85MM_NO_SILK"))
    )
    (comp (ref "JP376")
      (value "M01PTH_SMD_3.25X0.85MM_NO_SILK")
      (footprint "eagle-import:1X01_SMD_3.25X0.85MM_NO_SILK")
      (libsource (lib "eagle-import") (part "M01PTH_SMD_3.25X0.85MM_NO_SILK"))
    )
    (comp (ref "JP377")
      (value "M01PTH_SMD_3.25X0.85MM_NO_SILK")
      (footprint "eagle-import:1X01_SMD_3.25X0.85MM_NO_SILK")
      (libsource (lib "eagle-import") (part "M01PTH_SMD_3.25X0.85MM_NO_SILK"))
    )
    (comp (ref "JP378")
      (value "M01PTH_SMD_3.25X0.85MM_NO_SILK")
      (footprint "eagle-import:1X01_SMD_3.25X0.85MM_NO_SILK")
      (libsource (lib "eagle-import") (part "M01PTH_SMD_3.25X0.85MM_NO_SILK"))
    )
    (comp (ref "JP379")
      (value "M01PTH_SMD_3.25X0.85MM_NO_SILK")
      (footprint "eagle-import:1X01_SMD_3.25X0.85MM_NO_SILK")
      (libsource (lib "eagle-import") (part "M01PTH_SMD_3.25X0.85MM_NO_SILK"))
    )
    (comp (ref "JP380")
      (value "M01PTH_SMD_3.25X0.85MM_NO_SILK")
      (footprint "eagle-import:1X01_SMD_3.25X0.85MM_NO_SILK")
      (libsource (lib "eagle-import") (part "M01PTH_SMD_3.25X0.85MM_NO_SILK"))
    )
    (comp (ref "JP381")
      (value "M01PTH_SMD_3.25X0.85MM_NO_SILK")
      (footprint "eagle-import:1X01_SMD_3.25X0.85MM_NO_SILK")
      (libsource (lib "eagle-import") (part "M01PTH_SMD_3.25X0.85MM_NO_SILK"))
    )
    (comp (ref "JP382")
      (value "M01PTH_SMD_3.25X0.85MM_NO_SILK")
      (footprint "eagle-import:1X01_SMD_3.25X0.85MM_NO_SILK")
      (libsource (lib "eagle-import") (part "M01PTH_SMD_3.25X0.85MM_NO_SILK"))
    )
    (comp (ref "JP383")
      (value "M01PTH_SMD_3.25X0.85MM_NO_SILK")
      (footprint "eagle-import:1X01_SMD_3.25X0.85MM_NO_SILK")
      (libsource (lib "eagle-import") (part "M01PTH_SMD_3.25X0.85MM_NO_SILK"))
    )
    (comp (ref "JP384")
      (value "M01PTH_SMD_3.25X0.85MM_NO_SILK")
      (footprint "eagle-import:1X01_SMD_3.25X0.85MM_NO_SILK")
      (libsource (lib "eagle-import") (part "M01PTH_SMD_3.25X0.85MM_NO_SILK"))
    )
    (comp (ref "JP385")
      (value "M01PTH_SMD_3.25X0.85MM_NO_SILK")
      (footprint "eagle-import:1X01_SMD_3.25X0.85MM_NO_SILK")
      (libsource (lib "eagle-import") (part "M01PTH_SMD_3.25X0.85MM_NO_SILK"))
    )
    (comp (ref "JP386")
      (value "M01PTH_SMD_3.25X0.85MM_NO_SILK")
      (footprint "eagle-import:1X01_SMD_3.25X0.85MM_NO_SILK")
      (libsource (lib "eagle-import") (part "M01PTH_SMD_3.25X0.85MM_NO_SILK"))
    )
    (comp (ref "JP387")
      (value "M01PTH_SMD_3.25X0.85MM_NO_SILK")
      (footprint "eagle-import:1X01_SMD_3.25X0.85MM_NO_SILK")
      (libsource (lib "eagle-import") (part "M01PTH_SMD_3.25X0.85MM_NO_SILK"))
    )
    (comp (ref "JP388")
      (value "M01PTH_SMD_3.25X0.85MM_NO_SILK")
      (footprint "eagle-import:1X01_SMD_3.25X0.85MM_NO_SILK")
      (libsource (lib "eagle-import") (part "M01PTH_SMD_3.25X0.85MM_NO_SILK"))
    )
    (comp (ref "JP389")
      (value "M01PTH_SMD_3.25X0.85MM_NO_SILK")
      (footprint "eagle-import:1X01_SMD_3.25X0.85MM_NO_SILK")
      (libsource (lib "eagle-import") (part "M01PTH_SMD_3.25X0.85MM_NO_SILK"))
    )
    (comp (ref "JP390")
      (value "M01PTH_SMD_3.25X0.85MM_NO_SILK")
      (footprint "eagle-import:1X01_SMD_3.25X0.85MM_NO_SILK")
      (libsource (lib "eagle-import") (part "M01PTH_SMD_3.25X0.85MM_NO_SILK"))
    )
    (comp (ref "JP391")
      (value "M01PTH_SMD_3.25X0.85MM_NO_SILK")
      (footprint "eagle-import:1X01_SMD_3.25X0.85MM_NO_SILK")
      (libsource (lib "eagle-import") (part "M01PTH_SMD_3.25X0.85MM_NO_SILK"))
    )
    (comp (ref "JP392")
      (value "M01PTH_SMD_3.25X0.85MM_NO_SILK")
      (footprint "eagle-import:1X01_SMD_3.25X0.85MM_NO_SILK")
      (libsource (lib "eagle-import") (part "M01PTH_SMD_3.25X0.85MM_NO_SILK"))
    )
    (comp (ref "JP393")
      (value "M01PTH_SMD_3.25X0.85MM_NO_SILK")
      (footprint "eagle-import:1X01_SMD_3.25X0.85MM_NO_SILK")
      (libsource (lib "eagle-import") (part "M01PTH_SMD_3.25X0.85MM_NO_SILK"))
    )
    (comp (ref "JP394")
      (value "M01PTH_SMD_3.25X0.85MM_NO_SILK")
      (footprint "eagle-import:1X01_SMD_3.25X0.85MM_NO_SILK")
      (libsource (lib "eagle-import") (part "M01PTH_SMD_3.25X0.85MM_NO_SILK"))
    )
    (comp (ref "JP395")
      (value "M01PTH_SMD_3.25X0.85MM_NO_SILK")
      (footprint "eagle-import:1X01_SMD_3.25X0.85MM_NO_SILK")
      (libsource (lib "eagle-import") (part "M01PTH_SMD_3.25X0.85MM_NO_SILK"))
    )
    (comp (ref "JP396")
      (value "M01PTH_SMD_3.25X0.85MM_NO_SILK")
      (footprint "eagle-import:1X01_SMD_3.25X0.85MM_NO_SILK")
      (libsource (lib "eagle-import") (part "M01PTH_SMD_3.25X0.85MM_NO_SILK"))
    )
    (comp (ref "JP397")
      (value "M01PTH_SMD_3.25X0.85MM_NO_SILK")
      (footprint "eagle-import:1X01_SMD_3.25X0.85MM_NO_SILK")
      (libsource (lib "eagle-import") (part "M01PTH_SMD_3.25X0.85MM_NO_SILK"))
    )
    (comp (ref "JP398")
      (value "M01PTH_SMD_3.25X0.85MM_NO_SILK")
      (footprint "eagle-import:1X01_SMD_3.25X0.85MM_NO_SILK")
      (libsource (lib "eagle-import") (part "M01PTH_SMD_3.25X0.85MM_NO_SILK"))
    )
    (comp (ref "JP399")
      (value "M01PTH_SMD_3.25X0.85MM_NO_SILK")
      (footprint "eagle-import:1X01_SMD_3.25X0.85MM_NO_SILK")
      (libsource (lib "eagle-import") (part "M01PTH_SMD_3.25X0.85MM_NO_SILK"))
    )
    (comp (ref "JP400")
      (value "M01PTH_SMD_3.25X0.85MM_NO_SILK")
      (footprint "eagle-import:1X01_SMD_3.25X0.85MM_NO_SILK")
      (libsource (lib "eagle-import") (part "M01PTH_SMD_3.25X0.85MM_NO_SILK"))
    )
    (comp (ref "JP401")
      (value "M01PTH_SMD_3.25X0.85MM_NO_SILK")
      (footprint "eagle-import:1X01_SMD_3.25X0.85MM_NO_SILK")
      (libsource (lib "eagle-import") (part "M01PTH_SMD_3.25X0.85MM_NO_SILK"))
    )
    (comp (ref "JP402")
      (value "M01PTH_SMD_3.25X0.85MM_NO_SILK")
      (footprint "eagle-import:1X01_SMD_3.25X0.85MM_NO_SILK")
      (libsource (lib "eagle-import") (part "M01PTH_SMD_3.25X0.85MM_NO_SILK"))
    )
    (comp (ref "JP403")
      (value "M01PTH_SMD_3.25X0.85MM_NO_SILK")
      (footprint "eagle-import:1X01_SMD_3.25X0.85MM_NO_SILK")
      (libsource (lib "eagle-import") (part "M01PTH_SMD_3.25X0.85MM_NO_SILK"))
    )
    (comp (ref "JP404")
      (value "M01PTH_SMD_3.25X0.85MM_NO_SILK")
      (footprint "eagle-import:1X01_SMD_3.25X0.85MM_NO_SILK")
      (libsource (lib "eagle-import") (part "M01PTH_SMD_3.25X0.85MM_NO_SILK"))
    )
    (comp (ref "JP405")
      (value "M01PTH_SMD_3.25X0.85MM_NO_SILK")
      (footprint "eagle-import:1X01_SMD_3.25X0.85MM_NO_SILK")
      (libsource (lib "eagle-import") (part "M01PTH_SMD_3.25X0.85MM_NO_SILK"))
    )
    (comp (ref "JP406")
      (value "M01PTH_SMD_3.25X0.85MM_NO_SILK")
      (footprint "eagle-import:1X01_SMD_3.25X0.85MM_NO_SILK")
      (libsource (lib "eagle-import") (part "M01PTH_SMD_3.25X0.85MM_NO_SILK"))
    )
    (comp (ref "JP407")
      (value "M01PTH_SMD_3.25X0.85MM_NO_SILK")
      (footprint "eagle-import:1X01_SMD_3.25X0.85MM_NO_SILK")
      (libsource (lib "eagle-import") (part "M01PTH_SMD_3.25X0.85MM_NO_SILK"))
    )
    (comp (ref "JP408")
      (value "M01PTH_SMD_3.25X0.85MM_NO_SILK")
      (footprint "eagle-import:1X01_SMD_3.25X0.85MM_NO_SILK")
      (libsource (lib "eagle-import") (part "M01PTH_SMD_3.25X0.85MM_NO_SILK"))
    )
    (comp (ref "JP409")
      (value "M01PTH_SMD_3.25X0.85MM_NO_SILK")
      (footprint "eagle-import:1X01_SMD_3.25X0.85MM_NO_SILK")
      (libsource (lib "eagle-import") (part "M01PTH_SMD_3.25X0.85MM_NO_SILK"))
    )
    (comp (ref "JP410")
      (value "M01PTH_SMD_3.25X0.85MM_NO_SILK")
      (footprint "eagle-import:1X01_SMD_3.25X0.85MM_NO_SILK")
      (libsource (lib "eagle-import") (part "M01PTH_SMD_3.25X0.85MM_NO_SILK"))
    )
    (comp (ref "JP411")
      (value "M01PTH_SMD_3.25X0.85MM_NO_SILK")
      (footprint "eagle-import:1X01_SMD_3.25X0.85MM_NO_SILK")
      (libsource (lib "eagle-import") (part "M01PTH_SMD_3.25X0.85MM_NO_SILK"))
    )
    (comp (ref "JP412")
      (value "M01PTH_SMD_3.25X0.85MM_NO_SILK")
      (footprint "eagle-import:1X01_SMD_3.25X0.85MM_NO_SILK")
      (libsource (lib "eagle-import") (part "M01PTH_SMD_3.25X0.85MM_NO_SILK"))
    )
    (comp (ref "JP413")
      (value "M01PTH_SMD_3.25X0.85MM_NO_SILK")
      (footprint "eagle-import:1X01_SMD_3.25X0.85MM_NO_SILK")
      (libsource (lib "eagle-import") (part "M01PTH_SMD_3.25X0.85MM_NO_SILK"))
    )
    (comp (ref "JP414")
      (value "M01PTH_SMD_3.25X0.85MM_NO_SILK")
      (footprint "eagle-import:1X01_SMD_3.25X0.85MM_NO_SILK")
      (libsource (lib "eagle-import") (part "M01PTH_SMD_3.25X0.85MM_NO_SILK"))
    )
    (comp (ref "JP415")
      (value "M01PTH_SMD_3.25X0.85MM_NO_SILK")
      (footprint "eagle-import:1X01_SMD_3.25X0.85MM_NO_SILK")
      (libsource (lib "eagle-import") (part "M01PTH_SMD_3.25X0.85MM_NO_SILK"))
    )
    (comp (ref "JP416")
      (value "M01PTH_SMD_3.25X0.85MM_NO_SILK")
      (footprint "eagle-import:1X01_SMD_3.25X0.85MM_NO_SILK")
      (libsource (lib "eagle-import") (part "M01PTH_SMD_3.25X0.85MM_NO_SILK"))
    )
    (comp (ref "JP417")
      (value "M01PTH_SMD_3.25X0.85MM_NO_SILK")
      (footprint "eagle-import:1X01_SMD_3.25X0.85MM_NO_SILK")
      (libsource (lib "eagle-import") (part "M01PTH_SMD_3.25X0.85MM_NO_SILK"))
    )
    (comp (ref "JP418")
      (value "M01PTH_SMD_3.25X0.85MM_NO_SILK")
      (footprint "eagle-import:1X01_SMD_3.25X0.85MM_NO_SILK")
      (libsource (lib "eagle-import") (part "M01PTH_SMD_3.25X0.85MM_NO_SILK"))
    )
    (comp (ref "JP419")
      (value "M01PTH_SMD_3.25X0.85MM_NO_SILK")
      (footprint "eagle-import:1X01_SMD_3.25X0.85MM_NO_SILK")
      (libsource (lib "eagle-import") (part "M01PTH_SMD_3.25X0.85MM_NO_SILK"))
    )
    (comp (ref "JP420")
      (value "M01PTH_SMD_3.25X0.85MM_NO_SILK")
      (footprint "eagle-import:1X01_SMD_3.25X0.85MM_NO_SILK")
      (libsource (lib "eagle-import") (part "M01PTH_SMD_3.25X0.85MM_NO_SILK"))
    )
    (comp (ref "JP421")
      (value "M01PTH_SMD_3.25X0.85MM_NO_SILK")
      (footprint "eagle-import:1X01_SMD_3.25X0.85MM_NO_SILK")
      (libsource (lib "eagle-import") (part "M01PTH_SMD_3.25X0.85MM_NO_SILK"))
    )
    (comp (ref "JP422")
      (value "M01PTH_SMD_3.25X0.85MM_NO_SILK")
      (footprint "eagle-import:1X01_SMD_3.25X0.85MM_NO_SILK")
      (libsource (lib "eagle-import") (part "M01PTH_SMD_3.25X0.85MM_NO_SILK"))
    )
    (comp (ref "JP423")
      (value "M01PTH_SMD_3.25X0.85MM_NO_SILK")
      (footprint "eagle-import:1X01_SMD_3.25X0.85MM_NO_SILK")
      (libsource (lib "eagle-import") (part "M01PTH_SMD_3.25X0.85MM_NO_SILK"))
    )
    (comp (ref "JP424")
      (value "M01PTH_SMD_3.25X0.85MM_NO_SILK")
      (footprint "eagle-import:1X01_SMD_3.25X0.85MM_NO_SILK")
      (libsource (lib "eagle-import") (part "M01PTH_SMD_3.25X0.85MM_NO_SILK"))
    )
    (comp (ref "JP425")
      (value "M01PTH_SMD_3.25X0.85MM_NO_SILK")
      (footprint "eagle-import:1X01_SMD_3.25X0.85MM_NO_SILK")
      (libsource (lib "eagle-import") (part "M01PTH_SMD_3.25X0.85MM_NO_SILK"))
    )
    (comp (ref "JP426")
      (value "M01PTH_SMD_3.25X0.85MM_NO_SILK")
      (footprint "eagle-import:1X01_SMD_3.25X0.85MM_NO_SILK")
      (libsource (lib "eagle-import") (part "M01PTH_SMD_3.25X0.85MM_NO_SILK"))
    )
    (comp (ref "JP427")
      (value "M01PTH_SMD_3.25X0.85MM_NO_SILK")
      (footprint "eagle-import:1X01_SMD_3.25X0.85MM_NO_SILK")
      (libsource (lib "eagle-import") (part "M01PTH_SMD_3.25X0.85MM_NO_SILK"))
    )
    (comp (ref "JP428")
      (value "M01PTH_SMD_3.25X0.85MM_NO_SILK")
      (footprint "eagle-import:1X01_SMD_3.25X0.85MM_NO_SILK")
      (libsource (lib "eagle-import") (part "M01PTH_SMD_3.25X0.85MM_NO_SILK"))
    )
    (comp (ref "JP429")
      (value "M01PTH_SMD_3.25X0.85MM_NO_SILK")
      (footprint "eagle-import:1X01_SMD_3.25X0.85MM_NO_SILK")
      (libsource (lib "eagle-import") (part "M01PTH_SMD_3.25X0.85MM_NO_SILK"))
    )
    (comp (ref "JP430")
      (value "M01PTH_SMD_3.25X0.85MM_NO_SILK")
      (footprint "eagle-import:1X01_SMD_3.25X0.85MM_NO_SILK")
      (libsource (lib "eagle-import") (part "M01PTH_SMD_3.25X0.85MM_NO_SILK"))
    )
    (comp (ref "JP431")
      (value "M01PTH_SMD_3.25X0.85MM_NO_SILK")
      (footprint "eagle-import:1X01_SMD_3.25X0.85MM_NO_SILK")
      (libsource (lib "eagle-import") (part "M01PTH_SMD_3.25X0.85MM_NO_SILK"))
    )
    (comp (ref "JP432")
      (value "M01PTH_SMD_3.25X0.85MM_NO_SILK")
      (footprint "eagle-import:1X01_SMD_3.25X0.85MM_NO_SILK")
      (libsource (lib "eagle-import") (part "M01PTH_SMD_3.25X0.85MM_NO_SILK"))
    )
    (comp (ref "JP433")
      (value "M01PTH_SMD_3.25X0.85MM_NO_SILK")
      (footprint "eagle-import:1X01_SMD_3.25X0.85MM_NO_SILK")
      (libsource (lib "eagle-import") (part "M01PTH_SMD_3.25X0.85MM_NO_SILK"))
    )
    (comp (ref "JP434")
      (value "M01PTH_SMD_3.25X0.85MM_NO_SILK")
      (footprint "eagle-import:1X01_SMD_3.25X0.85MM_NO_SILK")
      (libsource (lib "eagle-import") (part "M01PTH_SMD_3.25X0.85MM_NO_SILK"))
    )
    (comp (ref "JP435")
      (value "M01PTH_SMD_3.25X0.85MM_NO_SILK")
      (footprint "eagle-import:1X01_SMD_3.25X0.85MM_NO_SILK")
      (libsource (lib "eagle-import") (part "M01PTH_SMD_3.25X0.85MM_NO_SILK"))
    )
    (comp (ref "JP436")
      (value "M01PTH_SMD_3.25X0.85MM_NO_SILK")
      (footprint "eagle-import:1X01_SMD_3.25X0.85MM_NO_SILK")
      (libsource (lib "eagle-import") (part "M01PTH_SMD_3.25X0.85MM_NO_SILK"))
    )
    (comp (ref "JP437")
      (value "M01PTH_SMD_3.25X0.85MM_NO_SILK")
      (footprint "eagle-import:1X01_SMD_3.25X0.85MM_NO_SILK")
      (libsource (lib "eagle-import") (part "M01PTH_SMD_3.25X0.85MM_NO_SILK"))
    )
    (comp (ref "JP438")
      (value "M01PTH_SMD_3.25X0.85MM_NO_SILK")
      (footprint "eagle-import:1X01_SMD_3.25X0.85MM_NO_SILK")
      (libsource (lib "eagle-import") (part "M01PTH_SMD_3.25X0.85MM_NO_SILK"))
    )
    (comp (ref "JP439")
      (value "M01PTH_SMD_3.25X0.85MM_NO_SILK")
      (footprint "eagle-import:1X01_SMD_3.25X0.85MM_NO_SILK")
      (libsource (lib "eagle-import") (part "M01PTH_SMD_3.25X0.85MM_NO_SILK"))
    )
    (comp (ref "JP440")
      (value "M01PTH_SMD_3.25X0.85MM_NO_SILK")
      (footprint "eagle-import:1X01_SMD_3.25X0.85MM_NO_SILK")
      (libsource (lib "eagle-import") (part "M01PTH_SMD_3.25X0.85MM_NO_SILK"))
    )
    (comp (ref "JP441")
      (value "M01PTH_SMD_3.25X0.85MM_NO_SILK")
      (footprint "eagle-import:1X01_SMD_3.25X0.85MM_NO_SILK")
      (libsource (lib "eagle-import") (part "M01PTH_SMD_3.25X0.85MM_NO_SILK"))
    )
    (comp (ref "JP442")
      (value "M01PTH_SMD_3.25X0.85MM_NO_SILK")
      (footprint "eagle-import:1X01_SMD_3.25X0.85MM_NO_SILK")
      (libsource (lib "eagle-import") (part "M01PTH_SMD_3.25X0.85MM_NO_SILK"))
    )
    (comp (ref "JP443")
      (value "M01PTH_SMD_3.25X0.85MM_NO_SILK")
      (footprint "eagle-import:1X01_SMD_3.25X0.85MM_NO_SILK")
      (libsource (lib "eagle-import") (part "M01PTH_SMD_3.25X0.85MM_NO_SILK"))
    )
    (comp (ref "JP444")
      (value "M01PTH_SMD_3.25X0.85MM_NO_SILK")
      (footprint "eagle-import:1X01_SMD_3.25X0.85MM_NO_SILK")
      (libsource (lib "eagle-import") (part "M01PTH_SMD_3.25X0.85MM_NO_SILK"))
    )
    (comp (ref "JP445")
      (value "M01PTH_SMD_3.25X0.85MM_NO_SILK")
      (footprint "eagle-import:1X01_SMD_3.25X0.85MM_NO_SILK")
      (libsource (lib "eagle-import") (part "M01PTH_SMD_3.25X0.85MM_NO_SILK"))
    )
    (comp (ref "JP446")
      (value "M01PTH_SMD_3.25X0.85MM_NO_SILK")
      (footprint "eagle-import:1X01_SMD_3.25X0.85MM_NO_SILK")
      (libsource (lib "eagle-import") (part "M01PTH_SMD_3.25X0.85MM_NO_SILK"))
    )
    (comp (ref "JP447")
      (value "M01PTH_SMD_3.25X0.85MM_NO_SILK")
      (footprint "eagle-import:1X01_SMD_3.25X0.85MM_NO_SILK")
      (libsource (lib "eagle-import") (part "M01PTH_SMD_3.25X0.85MM_NO_SILK"))
    )
    (comp (ref "JP448")
      (value "M01PTH_SMD_3.25X0.85MM_NO_SILK")
      (footprint "eagle-import:1X01_SMD_3.25X0.85MM_NO_SILK")
      (libsource (lib "eagle-import") (part "M01PTH_SMD_3.25X0.85MM_NO_SILK"))
    )
    (comp (ref "JP449")
      (value "M01PTH_SMD_3.25X0.85MM_NO_SILK")
      (footprint "eagle-import:1X01_SMD_3.25X0.85MM_NO_SILK")
      (libsource (lib "eagle-import") (part "M01PTH_SMD_3.25X0.85MM_NO_SILK"))
    )
    (comp (ref "JP450")
      (value "M01PTH_SMD_3.25X0.85MM_NO_SILK")
      (footprint "eagle-import:1X01_SMD_3.25X0.85MM_NO_SILK")
      (libsource (lib "eagle-import") (part "M01PTH_SMD_3.25X0.85MM_NO_SILK"))
    )
    (comp (ref "JP451")
      (value "M01PTH_SMD_3.25X0.85MM_NO_SILK")
      (footprint "eagle-import:1X01_SMD_3.25X0.85MM_NO_SILK")
      (libsource (lib "eagle-import") (part "M01PTH_SMD_3.25X0.85MM_NO_SILK"))
    )
    (comp (ref "JP452")
      (value "M01PTH_SMD_3.25X0.85MM_NO_SILK")
      (footprint "eagle-import:1X01_SMD_3.25X0.85MM_NO_SILK")
      (libsource (lib "eagle-import") (part "M01PTH_SMD_3.25X0.85MM_NO_SILK"))
    )
    (comp (ref "JP453")
      (value "M01PTH_SMD_3.25X0.85MM_NO_SILK")
      (footprint "eagle-import:1X01_SMD_3.25X0.85MM_NO_SILK")
      (libsource (lib "eagle-import") (part "M01PTH_SMD_3.25X0.85MM_NO_SILK"))
    )
    (comp (ref "JP454")
      (value "M01PTH_SMD_3.25X0.85MM_NO_SILK")
      (footprint "eagle-import:1X01_SMD_3.25X0.85MM_NO_SILK")
      (libsource (lib "eagle-import") (part "M01PTH_SMD_3.25X0.85MM_NO_SILK"))
    )
    (comp (ref "JP455")
      (value "M01PTH_SMD_3.25X0.85MM_NO_SILK")
      (footprint "eagle-import:1X01_SMD_3.25X0.85MM_NO_SILK")
      (libsource (lib "eagle-import") (part "M01PTH_SMD_3.25X0.85MM_NO_SILK"))
    )
    (comp (ref "JP456")
      (value "M01PTH_SMD_3.25X0.85MM_NO_SILK")
      (footprint "eagle-import:1X01_SMD_3.25X0.85MM_NO_SILK")
      (libsource (lib "eagle-import") (part "M01PTH_SMD_3.25X0.85MM_NO_SILK"))
    )
    (comp (ref "JP457")
      (value "M01PTH_SMD_3.25X0.85MM_NO_SILK")
      (footprint "eagle-import:1X01_SMD_3.25X0.85MM_NO_SILK")
      (libsource (lib "eagle-import") (part "M01PTH_SMD_3.25X0.85MM_NO_SILK"))
    )
    (comp (ref "JP458")
      (value "M01PTH_SMD_3.25X0.85MM_NO_SILK")
      (footprint "eagle-import:1X01_SMD_3.25X0.85MM_NO_SILK")
      (libsource (lib "eagle-import") (part "M01PTH_SMD_3.25X0.85MM_NO_SILK"))
    )
    (comp (ref "JP459")
      (value "M01PTH_SMD_3.25X0.85MM_NO_SILK")
      (footprint "eagle-import:1X01_SMD_3.25X0.85MM_NO_SILK")
      (libsource (lib "eagle-import") (part "M01PTH_SMD_3.25X0.85MM_NO_SILK"))
    )
    (comp (ref "JP460")
      (value "M01PTH_SMD_3.25X0.85MM_NO_SILK")
      (footprint "eagle-import:1X01_SMD_3.25X0.85MM_NO_SILK")
      (libsource (lib "eagle-import") (part "M01PTH_SMD_3.25X0.85MM_NO_SILK"))
    )
    (comp (ref "JP461")
      (value "M01PTH_SMD_3.25X0.85MM_NO_SILK")
      (footprint "eagle-import:1X01_SMD_3.25X0.85MM_NO_SILK")
      (libsource (lib "eagle-import") (part "M01PTH_SMD_3.25X0.85MM_NO_SILK"))
    )
    (comp (ref "JP462")
      (value "M01PTH_SMD_3.25X0.85MM_NO_SILK")
      (footprint "eagle-import:1X01_SMD_3.25X0.85MM_NO_SILK")
      (libsource (lib "eagle-import") (part "M01PTH_SMD_3.25X0.85MM_NO_SILK"))
    )
    (comp (ref "JP463")
      (value "M01PTH_SMD_3.25X0.85MM_NO_SILK")
      (footprint "eagle-import:1X01_SMD_3.25X0.85MM_NO_SILK")
      (libsource (lib "eagle-import") (part "M01PTH_SMD_3.25X0.85MM_NO_SILK"))
    )
    (comp (ref "JP464")
      (value "M01PTH_SMD_3.25X0.85MM_NO_SILK")
      (footprint "eagle-import:1X01_SMD_3.25X0.85MM_NO_SILK")
      (libsource (lib "eagle-import") (part "M01PTH_SMD_3.25X0.85MM_NO_SILK"))
    )
    (comp (ref "JP465")
      (value "M01PTH_SMD_3.25X0.85MM_NO_SILK")
      (footprint "eagle-import:1X01_SMD_3.25X0.85MM_NO_SILK")
      (libsource (lib "eagle-import") (part "M01PTH_SMD_3.25X0.85MM_NO_SILK"))
    )
    (comp (ref "JP466")
      (value "M01PTH_SMD_3.25X0.85MM_NO_SILK")
      (footprint "eagle-import:1X01_SMD_3.25X0.85MM_NO_SILK")
      (libsource (lib "eagle-import") (part "M01PTH_SMD_3.25X0.85MM_NO_SILK"))
    )
    (comp (ref "JP467")
      (value "M01PTH_SMD_3.25X0.85MM_NO_SILK")
      (footprint "eagle-import:1X01_SMD_3.25X0.85MM_NO_SILK")
      (libsource (lib "eagle-import") (part "M01PTH_SMD_3.25X0.85MM_NO_SILK"))
    )
    (comp (ref "JP468")
      (value "M01PTH_SMD_3.25X0.85MM_NO_SILK")
      (footprint "eagle-import:1X01_SMD_3.25X0.85MM_NO_SILK")
      (libsource (lib "eagle-import") (part "M01PTH_SMD_3.25X0.85MM_NO_SILK"))
    )
    (comp (ref "JP469")
      (value "M01PTH_SMD_3.25X0.85MM_NO_SILK")
      (footprint "eagle-import:1X01_SMD_3.25X0.85MM_NO_SILK")
      (libsource (lib "eagle-import") (part "M01PTH_SMD_3.25X0.85MM_NO_SILK"))
    )
    (comp (ref "JP470")
      (value "M01PTH_SMD_3.25X0.85MM_NO_SILK")
      (footprint "eagle-import:1X01_SMD_3.25X0.85MM_NO_SILK")
      (libsource (lib "eagle-import") (part "M01PTH_SMD_3.25X0.85MM_NO_SILK"))
    )
    (comp (ref "JP471")
      (value "M01PTH_SMD_3.25X0.85MM_NO_SILK")
      (footprint "eagle-import:1X01_SMD_3.25X0.85MM_NO_SILK")
      (libsource (lib "eagle-import") (part "M01PTH_SMD_3.25X0.85MM_NO_SILK"))
    )
    (comp (ref "JP472")
      (value "M01PTH_SMD_3.25X0.85MM_NO_SILK")
      (footprint "eagle-import:1X01_SMD_3.25X0.85MM_NO_SILK")
      (libsource (lib "eagle-import") (part "M01PTH_SMD_3.25X0.85MM_NO_SILK"))
    )
    (comp (ref "JP473")
      (value "M01PTH_SMD_3.25X0.85MM_NO_SILK")
      (footprint "eagle-import:1X01_SMD_3.25X0.85MM_NO_SILK")
      (libsource (lib "eagle-import") (part "M01PTH_SMD_3.25X0.85MM_NO_SILK"))
    )
    (comp (ref "JP474")
      (value "M01PTH_SMD_3.25X0.85MM_NO_SILK")
      (footprint "eagle-import:1X01_SMD_3.25X0.85MM_NO_SILK")
      (libsource (lib "eagle-import") (part "M01PTH_SMD_3.25X0.85MM_NO_SILK"))
    )
    (comp (ref "JP475")
      (value "M01PTH_SMD_3.25X0.85MM_NO_SILK")
      (footprint "eagle-import:1X01_SMD_3.25X0.85MM_NO_SILK")
      (libsource (lib "eagle-import") (part "M01PTH_SMD_3.25X0.85MM_NO_SILK"))
    )
    (comp (ref "JP476")
      (value "M01PTH_SMD_3.25X0.85MM_NO_SILK")
      (footprint "eagle-import:1X01_SMD_3.25X0.85MM_NO_SILK")
      (libsource (lib "eagle-import") (part "M01PTH_SMD_3.25X0.85MM_NO_SILK"))
    )
    (comp (ref "JP477")
      (value "M01PTH_SMD_3.25X0.85MM_NO_SILK")
      (footprint "eagle-import:1X01_SMD_3.25X0.85MM_NO_SILK")
      (libsource (lib "eagle-import") (part "M01PTH_SMD_3.25X0.85MM_NO_SILK"))
    )
    (comp (ref "JP478")
      (value "M01PTH_SMD_3.25X0.85MM_NO_SILK")
      (footprint "eagle-import:1X01_SMD_3.25X0.85MM_NO_SILK")
      (libsource (lib "eagle-import") (part "M01PTH_SMD_3.25X0.85MM_NO_SILK"))
    )
    (comp (ref "JP479")
      (value "M01PTH_SMD_3.25X0.85MM_NO_SILK")
      (footprint "eagle-import:1X01_SMD_3.25X0.85MM_NO_SILK")
      (libsource (lib "eagle-import") (part "M01PTH_SMD_3.25X0.85MM_NO_SILK"))
    )
    (comp (ref "JP480")
      (value "M01PTH_SMD_3.25X0.85MM_NO_SILK")
      (footprint "eagle-import:1X01_SMD_3.25X0.85MM_NO_SILK")
      (libsource (lib "eagle-import") (part "M01PTH_SMD_3.25X0.85MM_NO_SILK"))
    )
    (comp (ref "JP481")
      (value "M01PTH_SMD_3.25X0.85MM_NO_SILK")
      (footprint "eagle-import:1X01_SMD_3.25X0.85MM_NO_SILK")
      (libsource (lib "eagle-import") (part "M01PTH_SMD_3.25X0.85MM_NO_SILK"))
    )
    (comp (ref "JP482")
      (value "M01PTH_SMD_3.25X0.85MM_NO_SILK")
      (footprint "eagle-import:1X01_SMD_3.25X0.85MM_NO_SILK")
      (libsource (lib "eagle-import") (part "M01PTH_SMD_3.25X0.85MM_NO_SILK"))
    )
    (comp (ref "JP483")
      (value "M01PTH_SMD_3.25X0.85MM_NO_SILK")
      (footprint "eagle-import:1X01_SMD_3.25X0.85MM_NO_SILK")
      (libsource (lib "eagle-import") (part "M01PTH_SMD_3.25X0.85MM_NO_SILK"))
    )
    (comp (ref "JP484")
      (value "M01PTH_SMD_3.25X0.85MM_NO_SILK")
      (footprint "eagle-import:1X01_SMD_3.25X0.85MM_NO_SILK")
      (libsource (lib "eagle-import") (part "M01PTH_SMD_3.25X0.85MM_NO_SILK"))
    )
    (comp (ref "JP485")
      (value "M01PTH_SMD_3.25X0.85MM_NO_SILK")
      (footprint "eagle-import:1X01_SMD_3.25X0.85MM_NO_SILK")
      (libsource (lib "eagle-import") (part "M01PTH_SMD_3.25X0.85MM_NO_SILK"))
    )
    (comp (ref "JP486")
      (value "M01PTH_SMD_3.25X0.85MM_NO_SILK")
      (footprint "eagle-import:1X01_SMD_3.25X0.85MM_NO_SILK")
      (libsource (lib "eagle-import") (part "M01PTH_SMD_3.25X0.85MM_NO_SILK"))
    )
    (comp (ref "JP487")
      (value "M01PTH_SMD_3.25X0.85MM_NO_SILK")
      (footprint "eagle-import:1X01_SMD_3.25X0.85MM_NO_SILK")
      (libsource (lib "eagle-import") (part "M01PTH_SMD_3.25X0.85MM_NO_SILK"))
    )
    (comp (ref "JP488")
      (value "M01PTH_SMD_3.25X0.85MM_NO_SILK")
      (footprint "eagle-import:1X01_SMD_3.25X0.85MM_NO_SILK")
      (libsource (lib "eagle-import") (part "M01PTH_SMD_3.25X0.85MM_NO_SILK"))
    )
    (comp (ref "JP489")
      (value "M01PTH_SMD_3.25X0.85MM_NO_SILK")
      (footprint "eagle-import:1X01_SMD_3.25X0.85MM_NO_SILK")
      (libsource (lib "eagle-import") (part "M01PTH_SMD_3.25X0.85MM_NO_SILK"))
    )
    (comp (ref "JP490")
      (value "M01PTH_SMD_3.25X0.85MM_NO_SILK")
      (footprint "eagle-import:1X01_SMD_3.25X0.85MM_NO_SILK")
      (libsource (lib "eagle-import") (part "M01PTH_SMD_3.25X0.85MM_NO_SILK"))
    )
    (comp (ref "JP491")
      (value "M01PTH_SMD_3.25X0.85MM_NO_SILK")
      (footprint "eagle-import:1X01_SMD_3.25X0.85MM_NO_SILK")
      (libsource (lib "eagle-import") (part "M01PTH_SMD_3.25X0.85MM_NO_SILK"))
    )
    (comp (ref "JP492")
      (value "M01PTH_SMD_3.25X0.85MM_NO_SILK")
      (footprint "eagle-import:1X01_SMD_3.25X0.85MM_NO_SILK")
      (libsource (lib "eagle-import") (part "M01PTH_SMD_3.25X0.85MM_NO_SILK"))
    )
    (comp (ref "JP493")
      (value "M01PTH_SMD_3.25X0.85MM_NO_SILK")
      (footprint "eagle-import:1X01_SMD_3.25X0.85MM_NO_SILK")
      (libsource (lib "eagle-import") (part "M01PTH_SMD_3.25X0.85MM_NO_SILK"))
    )
    (comp (ref "JP494")
      (value "M01PTH_SMD_3.25X0.85MM_NO_SILK")
      (footprint "eagle-import:1X01_SMD_3.25X0.85MM_NO_SILK")
      (libsource (lib "eagle-import") (part "M01PTH_SMD_3.25X0.85MM_NO_SILK"))
    )
    (comp (ref "JP495")
      (value "M01PTH_SMD_3.25X0.85MM_NO_SILK")
      (footprint "eagle-import:1X01_SMD_3.25X0.85MM_NO_SILK")
      (libsource (lib "eagle-import") (part "M01PTH_SMD_3.25X0.85MM_NO_SILK"))
    )
    (comp (ref "JP496")
      (value "M01PTH_SMD_3.25X0.85MM_NO_SILK")
      (footprint "eagle-import:1X01_SMD_3.25X0.85MM_NO_SILK")
      (libsource (lib "eagle-import") (part "M01PTH_SMD_3.25X0.85MM_NO_SILK"))
    )
    (comp (ref "JP497")
      (value "M01PTH_SMD_3.25X0.85MM_NO_SILK")
      (footprint "eagle-import:1X01_SMD_3.25X0.85MM_NO_SILK")
      (libsource (lib "eagle-import") (part "M01PTH_SMD_3.25X0.85MM_NO_SILK"))
    )
    (comp (ref "JP498")
      (value "M01PTH_SMD_3.25X0.85MM_NO_SILK")
      (footprint "eagle-import:1X01_SMD_3.25X0.85MM_NO_SILK")
      (libsource (lib "eagle-import") (part "M01PTH_SMD_3.25X0.85MM_NO_SILK"))
    )
    (comp (ref "JP499")
      (value "M01PTH_SMD_3.25X0.85MM_NO_SILK")
      (footprint "eagle-import:1X01_SMD_3.25X0.85MM_NO_SILK")
      (libsource (lib "eagle-import") (part "M01PTH_SMD_3.25X0.85MM_NO_SILK"))
    )
    (comp (ref "JP500")
      (value "M01PTH_SMD_3.25X0.85MM_NO_SILK")
      (footprint "eagle-import:1X01_SMD_3.25X0.85MM_NO_SILK")
      (libsource (lib "eagle-import") (part "M01PTH_SMD_3.25X0.85MM_NO_SILK"))
    )
    (comp (ref "JP501")
      (value "M01PTH_SMD_3.25X0.85MM_NO_SILK")
      (footprint "eagle-import:1X01_SMD_3.25X0.85MM_NO_SILK")
      (libsource (lib "eagle-import") (part "M01PTH_SMD_3.25X0.85MM_NO_SILK"))
    )
    (comp (ref "JP502")
      (value "M01PTH_SMD_3.25X0.85MM_NO_SILK")
      (footprint "eagle-import:1X01_SMD_3.25X0.85MM_NO_SILK")
      (libsource (lib "eagle-import") (part "M01PTH_SMD_3.25X0.85MM_NO_SILK"))
    )
    (comp (ref "JP503")
      (value "M01PTH_SMD_3.25X0.85MM_NO_SILK")
      (footprint "eagle-import:1X01_SMD_3.25X0.85MM_NO_SILK")
      (libsource (lib "eagle-import") (part "M01PTH_SMD_3.25X0.85MM_NO_SILK"))
    )
    (comp (ref "JP504")
      (value "M01PTH_SMD_3.25X0.85MM_NO_SILK")
      (footprint "eagle-import:1X01_SMD_3.25X0.85MM_NO_SILK")
      (libsource (lib "eagle-import") (part "M01PTH_SMD_3.25X0.85MM_NO_SILK"))
    )
    (comp (ref "JP505")
      (value "M01PTH_SMD_3.25X0.85MM_NO_SILK")
      (footprint "eagle-import:1X01_SMD_3.25X0.85MM_NO_SILK")
      (libsource (lib "eagle-import") (part "M01PTH_SMD_3.25X0.85MM_NO_SILK"))
    )
    (comp (ref "JP506")
      (value "M01PTH_SMD_3.25X0.85MM_NO_SILK")
      (footprint "eagle-import:1X01_SMD_3.25X0.85MM_NO_SILK")
      (libsource (lib "eagle-import") (part "M01PTH_SMD_3.25X0.85MM_NO_SILK"))
    )
    (comp (ref "JP507")
      (value "M01PTH_SMD_3.25X0.85MM_NO_SILK")
      (footprint "eagle-import:1X01_SMD_3.25X0.85MM_NO_SILK")
      (libsource (lib "eagle-import") (part "M01PTH_SMD_3.25X0.85MM_NO_SILK"))
    )
    (comp (ref "JP508")
      (value "M01PTH_SMD_3.25X0.85MM_NO_SILK")
      (footprint "eagle-import:1X01_SMD_3.25X0.85MM_NO_SILK")
      (libsource (lib "eagle-import") (part "M01PTH_SMD_3.25X0.85MM_NO_SILK"))
    )
    (comp (ref "JP509")
      (value "M01PTH_SMD_3.25X0.85MM_NO_SILK")
      (footprint "eagle-import:1X01_SMD_3.25X0.85MM_NO_SILK")
      (libsource (lib "eagle-import") (part "M01PTH_SMD_3.25X0.85MM_NO_SILK"))
    )
    (comp (ref "JP510")
      (value "M01PTH_SMD_3.25X0.85MM_NO_SILK")
      (footprint "eagle-import:1X01_SMD_3.25X0.85MM_NO_SILK")
      (libsource (lib "eagle-import") (part "M01PTH_SMD_3.25X0.85MM_NO_SILK"))
    )
    (comp (ref "JP511")
      (value "M01PTH_SMD_3.25X0.85MM_NO_SILK")
      (footprint "eagle-import:1X01_SMD_3.25X0.85MM_NO_SILK")
      (libsource (lib "eagle-import") (part "M01PTH_SMD_3.25X0.85MM_NO_SILK"))
    )
    (comp (ref "JP512")
      (value "M01PTH_SMD_3.25X0.85MM_NO_SILK")
      (footprint "eagle-import:1X01_SMD_3.25X0.85MM_NO_SILK")
      (libsource (lib "eagle-import") (part "M01PTH_SMD_3.25X0.85MM_NO_SILK"))
    )
    (comp (ref "JP513")
      (value "M01PTH_SMD_3.25X0.85MM_NO_SILK")
      (footprint "eagle-import:1X01_SMD_3.25X0.85MM_NO_SILK")
      (libsource (lib "eagle-import") (part "M01PTH_SMD_3.25X0.85MM_NO_SILK"))
    )
    (comp (ref "JP514")
      (value "M01PTH_SMD_3.25X0.85MM_NO_SILK")
      (footprint "eagle-import:1X01_SMD_3.25X0.85MM_NO_SILK")
      (libsource (lib "eagle-import") (part "M01PTH_SMD_3.25X0.85MM_NO_SILK"))
    )
    (comp (ref "JP515")
      (value "M01PTH_SMD_3.25X0.85MM_NO_SILK")
      (footprint "eagle-import:1X01_SMD_3.25X0.85MM_NO_SILK")
      (libsource (lib "eagle-import") (part "M01PTH_SMD_3.25X0.85MM_NO_SILK"))
    )
    (comp (ref "JP516")
      (value "M01PTH_SMD_3.25X0.85MM_NO_SILK")
      (footprint "eagle-import:1X01_SMD_3.25X0.85MM_NO_SILK")
      (libsource (lib "eagle-import") (part "M01PTH_SMD_3.25X0.85MM_NO_SILK"))
    )
    (comp (ref "JP517")
      (value "M01PTH_SMD_3.25X0.85MM_NO_SILK")
      (footprint "eagle-import:1X01_SMD_3.25X0.85MM_NO_SILK")
      (libsource (lib "eagle-import") (part "M01PTH_SMD_3.25X0.85MM_NO_SILK"))
    )
    (comp (ref "JP518")
      (value "M01PTH_SMD_3.25X0.85MM_NO_SILK")
      (footprint "eagle-import:1X01_SMD_3.25X0.85MM_NO_SILK")
      (libsource (lib "eagle-import") (part "M01PTH_SMD_3.25X0.85MM_NO_SILK"))
    )
    (comp (ref "JP519")
      (value "M01PTH_SMD_3.25X0.85MM_NO_SILK")
      (footprint "eagle-import:1X01_SMD_3.25X0.85MM_NO_SILK")
      (libsource (lib "eagle-import") (part "M01PTH_SMD_3.25X0.85MM_NO_SILK"))
    )
    (comp (ref "JP520")
      (value "M01PTH_SMD_3.25X0.85MM_NO_SILK")
      (footprint "eagle-import:1X01_SMD_3.25X0.85MM_NO_SILK")
      (libsource (lib "eagle-import") (part "M01PTH_SMD_3.25X0.85MM_NO_SILK"))
    )
    (comp (ref "JP521")
      (value "M01PTH_SMD_3.25X0.85MM_NO_SILK")
      (footprint "eagle-import:1X01_SMD_3.25X0.85MM_NO_SILK")
      (libsource (lib "eagle-import") (part "M01PTH_SMD_3.25X0.85MM_NO_SILK"))
    )
    (comp (ref "JP522")
      (value "M01PTH_SMD_3.25X0.85MM_NO_SILK")
      (footprint "eagle-import:1X01_SMD_3.25X0.85MM_NO_SILK")
      (libsource (lib "eagle-import") (part "M01PTH_SMD_3.25X0.85MM_NO_SILK"))
    )
    (comp (ref "JP523")
      (value "M01PTH_SMD_3.25X0.85MM_NO_SILK")
      (footprint "eagle-import:1X01_SMD_3.25X0.85MM_NO_SILK")
      (libsource (lib "eagle-import") (part "M01PTH_SMD_3.25X0.85MM_NO_SILK"))
    )
    (comp (ref "JP524")
      (value "M01PTH_SMD_3.25X0.85MM_NO_SILK")
      (footprint "eagle-import:1X01_SMD_3.25X0.85MM_NO_SILK")
      (libsource (lib "eagle-import") (part "M01PTH_SMD_3.25X0.85MM_NO_SILK"))
    )
    (comp (ref "JP525")
      (value "M01PTH_SMD_3.25X0.85MM_NO_SILK")
      (footprint "eagle-import:1X01_SMD_3.25X0.85MM_NO_SILK")
      (libsource (lib "eagle-import") (part "M01PTH_SMD_3.25X0.85MM_NO_SILK"))
    )
    (comp (ref "JP526")
      (value "M01PTH_SMD_3.25X0.85MM_NO_SILK")
      (footprint "eagle-import:1X01_SMD_3.25X0.85MM_NO_SILK")
      (libsource (lib "eagle-import") (part "M01PTH_SMD_3.25X0.85MM_NO_SILK"))
    )
    (comp (ref "JP527")
      (value "M01PTH_SMD_3.25X0.85MM_NO_SILK")
      (footprint "eagle-import:1X01_SMD_3.25X0.85MM_NO_SILK")
      (libsource (lib "eagle-import") (part "M01PTH_SMD_3.25X0.85MM_NO_SILK"))
    )
    (comp (ref "JP528")
      (value "M01PTH_SMD_3.25X0.85MM_NO_SILK")
      (footprint "eagle-import:1X01_SMD_3.25X0.85MM_NO_SILK")
      (libsource (lib "eagle-import") (part "M01PTH_SMD_3.25X0.85MM_NO_SILK"))
    )
    (comp (ref "JP529")
      (value "M01PTH_SMD_3.25X0.85MM_NO_SILK")
      (footprint "eagle-import:1X01_SMD_3.25X0.85MM_NO_SILK")
      (libsource (lib "eagle-import") (part "M01PTH_SMD_3.25X0.85MM_NO_SILK"))
    )
    (comp (ref "JP530")
      (value "M01PTH_SMD_3.25X0.85MM_NO_SILK")
      (footprint "eagle-import:1X01_SMD_3.25X0.85MM_NO_SILK")
      (libsource (lib "eagle-import") (part "M01PTH_SMD_3.25X0.85MM_NO_SILK"))
    )
    (comp (ref "JP531")
      (value "M01PTH_SMD_3.25X0.85MM_NO_SILK")
      (footprint "eagle-import:1X01_SMD_3.25X0.85MM_NO_SILK")
      (libsource (lib "eagle-import") (part "M01PTH_SMD_3.25X0.85MM_NO_SILK"))
    )
    (comp (ref "JP532")
      (value "M01PTH_SMD_3.25X0.85MM_NO_SILK")
      (footprint "eagle-import:1X01_SMD_3.25X0.85MM_NO_SILK")
      (libsource (lib "eagle-import") (part "M01PTH_SMD_3.25X0.85MM_NO_SILK"))
    )
    (comp (ref "JP533")
      (value "M01PTH_SMD_3.25X0.85MM_NO_SILK")
      (footprint "eagle-import:1X01_SMD_3.25X0.85MM_NO_SILK")
      (libsource (lib "eagle-import") (part "M01PTH_SMD_3.25X0.85MM_NO_SILK"))
    )
    (comp (ref "JP534")
      (value "M01PTH_SMD_3.25X0.85MM_NO_SILK")
      (footprint "eagle-import:1X01_SMD_3.25X0.85MM_NO_SILK")
      (libsource (lib "eagle-import") (part "M01PTH_SMD_3.25X0.85MM_NO_SILK"))
    )
    (comp (ref "JP535")
      (value "M01PTH_SMD_3.25X0.85MM_NO_SILK")
      (footprint "eagle-import:1X01_SMD_3.25X0.85MM_NO_SILK")
      (libsource (lib "eagle-import") (part "M01PTH_SMD_3.25X0.85MM_NO_SILK"))
    )
    (comp (ref "JP536")
      (value "M01PTH_SMD_3.25X0.85MM_NO_SILK")
      (footprint "eagle-import:1X01_SMD_3.25X0.85MM_NO_SILK")
      (libsource (lib "eagle-import") (part "M01PTH_SMD_3.25X0.85MM_NO_SILK"))
    )
    (comp (ref "JP537")
      (value "M01PTH_SMD_3.25X0.85MM_NO_SILK")
      (footprint "eagle-import:1X01_SMD_3.25X0.85MM_NO_SILK")
      (libsource (lib "eagle-import") (part "M01PTH_SMD_3.25X0.85MM_NO_SILK"))
    )
    (comp (ref "JP538")
      (value "M01PTH_SMD_3.25X0.85MM_NO_SILK")
      (footprint "eagle-import:1X01_SMD_3.25X0.85MM_NO_SILK")
      (libsource (lib "eagle-import") (part "M01PTH_SMD_3.25X0.85MM_NO_SILK"))
    )
    (comp (ref "JP539")
      (value "M01PTH_SMD_3.25X0.85MM_NO_SILK")
      (footprint "eagle-import:1X01_SMD_3.25X0.85MM_NO_SILK")
      (libsource (lib "eagle-import") (part "M01PTH_SMD_3.25X0.85MM_NO_SILK"))
    )
    (comp (ref "JP540")
      (value "M01PTH_SMD_3.25X0.85MM_NO_SILK")
      (footprint "eagle-import:1X01_SMD_3.25X0.85MM_NO_SILK")
      (libsource (lib "eagle-import") (part "M01PTH_SMD_3.25X0.85MM_NO_SILK"))
    )
    (comp (ref "JP541")
      (value "M01PTH_SMD_3.25X0.85MM_NO_SILK")
      (footprint "eagle-import:1X01_SMD_3.25X0.85MM_NO_SILK")
      (libsource (lib "eagle-import") (part "M01PTH_SMD_3.25X0.85MM_NO_SILK"))
    )
    (comp (ref "JP542")
      (value "M01PTH_SMD_3.25X0.85MM_NO_SILK")
      (footprint "eagle-import:1X01_SMD_3.25X0.85MM_NO_SILK")
      (libsource (lib "eagle-import") (part "M01PTH_SMD_3.25X0.85MM_NO_SILK"))
    )
    (comp (ref "JP543")
      (value "M01PTH_SMD_3.25X0.85MM_NO_SILK")
      (footprint "eagle-import:1X01_SMD_3.25X0.85MM_NO_SILK")
      (libsource (lib "eagle-import") (part "M01PTH_SMD_3.25X0.85MM_NO_SILK"))
    )
    (comp (ref "JP544")
      (value "M01PTH_SMD_3.25X0.85MM_NO_SILK")
      (footprint "eagle-import:1X01_SMD_3.25X0.85MM_NO_SILK")
      (libsource (lib "eagle-import") (part "M01PTH_SMD_3.25X0.85MM_NO_SILK"))
    )
    (comp (ref "JP545")
      (value "M01PTH_SMD_3.25X0.85MM_NO_SILK")
      (footprint "eagle-import:1X01_SMD_3.25X0.85MM_NO_SILK")
      (libsource (lib "eagle-import") (part "M01PTH_SMD_3.25X0.85MM_NO_SILK"))
    )
    (comp (ref "JP546")
      (value "M01PTH_SMD_3.25X0.85MM_NO_SILK")
      (footprint "eagle-import:1X01_SMD_3.25X0.85MM_NO_SILK")
      (libsource (lib "eagle-import") (part "M01PTH_SMD_3.25X0.85MM_NO_SILK"))
    )
    (comp (ref "JP547")
      (value "M01PTH_SMD_3.25X0.85MM_NO_SILK")
      (footprint "eagle-import:1X01_SMD_3.25X0.85MM_NO_SILK")
      (libsource (lib "eagle-import") (part "M01PTH_SMD_3.25X0.85MM_NO_SILK"))
    )
    (comp (ref "JP548")
      (value "M01PTH_SMD_3.25X0.85MM_NO_SILK")
      (footprint "eagle-import:1X01_SMD_3.25X0.85MM_NO_SILK")
      (libsource (lib "eagle-import") (part "M01PTH_SMD_3.25X0.85MM_NO_SILK"))
    )
    (comp (ref "JP549")
      (value "M01PTH_SMD_3.25X0.85MM_NO_SILK")
      (footprint "eagle-import:1X01_SMD_3.25X0.85MM_NO_SILK")
      (libsource (lib "eagle-import") (part "M01PTH_SMD_3.25X0.85MM_NO_SILK"))
    )
    (comp (ref "JP550")
      (value "M01PTH_SMD_3.25X0.85MM_NO_SILK")
      (footprint "eagle-import:1X01_SMD_3.25X0.85MM_NO_SILK")
      (libsource (lib "eagle-import") (part "M01PTH_SMD_3.25X0.85MM_NO_SILK"))
    )
    (comp (ref "JP551")
      (value "M01PTH_SMD_3.25X0.85MM_NO_SILK")
      (footprint "eagle-import:1X01_SMD_3.25X0.85MM_NO_SILK")
      (libsource (lib "eagle-import") (part "M01PTH_SMD_3.25X0.85MM_NO_SILK"))
    )
    (comp (ref "JP552")
      (value "M01PTH_SMD_3.25X0.85MM_NO_SILK")
      (footprint "eagle-import:1X01_SMD_3.25X0.85MM_NO_SILK")
      (libsource (lib "eagle-import") (part "M01PTH_SMD_3.25X0.85MM_NO_SILK"))
    )
    (comp (ref "JP553")
      (value "M01PTH_SMD_3.25X0.85MM_NO_SILK")
      (footprint "eagle-import:1X01_SMD_3.25X0.85MM_NO_SILK")
      (libsource (lib "eagle-import") (part "M01PTH_SMD_3.25X0.85MM_NO_SILK"))
    )
    (comp (ref "JP554")
      (value "M01PTH_SMD_3.25X0.85MM_NO_SILK")
      (footprint "eagle-import:1X01_SMD_3.25X0.85MM_NO_SILK")
      (libsource (lib "eagle-import") (part "M01PTH_SMD_3.25X0.85MM_NO_SILK"))
    )
    (comp (ref "JP555")
      (value "M01PTH_SMD_3.25X0.85MM_NO_SILK")
      (footprint "eagle-import:1X01_SMD_3.25X0.85MM_NO_SILK")
      (libsource (lib "eagle-import") (part "M01PTH_SMD_3.25X0.85MM_NO_SILK"))
    )
    (comp (ref "JP556")
      (value "M01PTH_SMD_3.25X0.85MM_NO_SILK")
      (footprint "eagle-import:1X01_SMD_3.25X0.85MM_NO_SILK")
      (libsource (lib "eagle-import") (part "M01PTH_SMD_3.25X0.85MM_NO_SILK"))
    )
    (comp (ref "JP557")
      (value "M01PTH_SMD_3.25X0.85MM_NO_SILK")
      (footprint "eagle-import:1X01_SMD_3.25X0.85MM_NO_SILK")
      (libsource (lib "eagle-import") (part "M01PTH_SMD_3.25X0.85MM_NO_SILK"))
    )
    (comp (ref "JP558")
      (value "M01PTH_SMD_3.25X0.85MM_NO_SILK")
      (footprint "eagle-import:1X01_SMD_3.25X0.85MM_NO_SILK")
      (libsource (lib "eagle-import") (part "M01PTH_SMD_3.25X0.85MM_NO_SILK"))
    )
    (comp (ref "JP559")
      (value "M01PTH_SMD_3.25X0.85MM_NO_SILK")
      (footprint "eagle-import:1X01_SMD_3.25X0.85MM_NO_SILK")
      (libsource (lib "eagle-import") (part "M01PTH_SMD_3.25X0.85MM_NO_SILK"))
    )
    (comp (ref "JP560")
      (value "M01PTH_SMD_3.25X0.85MM_NO_SILK")
      (footprint "eagle-import:1X01_SMD_3.25X0.85MM_NO_SILK")
      (libsource (lib "eagle-import") (part "M01PTH_SMD_3.25X0.85MM_NO_SILK"))
    )
    (comp (ref "JP561")
      (value "M01PTH_SMD_3.25X0.85MM_NO_SILK")
      (footprint "eagle-import:1X01_SMD_3.25X0.85MM_NO_SILK")
      (libsource (lib "eagle-import") (part "M01PTH_SMD_3.25X0.85MM_NO_SILK"))
    )
    (comp (ref "JP562")
      (value "M01PTH_SMD_3.25X0.85MM_NO_SILK")
      (footprint "eagle-import:1X01_SMD_3.25X0.85MM_NO_SILK")
      (libsource (lib "eagle-import") (part "M01PTH_SMD_3.25X0.85MM_NO_SILK"))
    )
    (comp (ref "JP563")
      (value "M01PTH_SMD_3.25X0.85MM_NO_SILK")
      (footprint "eagle-import:1X01_SMD_3.25X0.85MM_NO_SILK")
      (libsource (lib "eagle-import") (part "M01PTH_SMD_3.25X0.85MM_NO_SILK"))
    )
    (comp (ref "JP564")
      (value "M01PTH_SMD_3.25X0.85MM_NO_SILK")
      (footprint "eagle-import:1X01_SMD_3.25X0.85MM_NO_SILK")
      (libsource (lib "eagle-import") (part "M01PTH_SMD_3.25X0.85MM_NO_SILK"))
    )
    (comp (ref "JP565")
      (value "M01PTH_SMD_3.25X0.85MM_NO_SILK")
      (footprint "eagle-import:1X01_SMD_3.25X0.85MM_NO_SILK")
      (libsource (lib "eagle-import") (part "M01PTH_SMD_3.25X0.85MM_NO_SILK"))
    )
    (comp (ref "JP566")
      (value "M01PTH_SMD_3.25X0.85MM_NO_SILK")
      (footprint "eagle-import:1X01_SMD_3.25X0.85MM_NO_SILK")
      (libsource (lib "eagle-import") (part "M01PTH_SMD_3.25X0.85MM_NO_SILK"))
    )
    (comp (ref "JP567")
      (value "M01PTH_SMD_3.25X0.85MM_NO_SILK")
      (footprint "eagle-import:1X01_SMD_3.25X0.85MM_NO_SILK")
      (libsource (lib "eagle-import") (part "M01PTH_SMD_3.25X0.85MM_NO_SILK"))
    )
    (comp (ref "JP568")
      (value "M01PTH_SMD_3.25X0.85MM_NO_SILK")
      (footprint "eagle-import:1X01_SMD_3.25X0.85MM_NO_SILK")
      (libsource (lib "eagle-import") (part "M01PTH_SMD_3.25X0.85MM_NO_SILK"))
    )
    (comp (ref "JP569")
      (value "M01PTH_SMD_3.25X0.85MM_NO_SILK")
      (footprint "eagle-import:1X01_SMD_3.25X0.85MM_NO_SILK")
      (libsource (lib "eagle-import") (part "M01PTH_SMD_3.25X0.85MM_NO_SILK"))
    )
    (comp (ref "JP570")
      (value "M01PTH_SMD_3.25X0.85MM_NO_SILK")
      (footprint "eagle-import:1X01_SMD_3.25X0.85MM_NO_SILK")
      (libsource (lib "eagle-import") (part "M01PTH_SMD_3.25X0.85MM_NO_SILK"))
    )
    (comp (ref "JP571")
      (value "M01PTH_SMD_3.25X0.85MM_NO_SILK")
      (footprint "eagle-import:1X01_SMD_3.25X0.85MM_NO_SILK")
      (libsource (lib "eagle-import") (part "M01PTH_SMD_3.25X0.85MM_NO_SILK"))
    )
    (comp (ref "JP572")
      (value "M01PTH_SMD_3.25X0.85MM_NO_SILK")
      (footprint "eagle-import:1X01_SMD_3.25X0.85MM_NO_SILK")
      (libsource (lib "eagle-import") (part "M01PTH_SMD_3.25X0.85MM_NO_SILK"))
    )
    (comp (ref "JP573")
      (value "M01PTH_SMD_3.25X0.85MM_NO_SILK")
      (footprint "eagle-import:1X01_SMD_3.25X0.85MM_NO_SILK")
      (libsource (lib "eagle-import") (part "M01PTH_SMD_3.25X0.85MM_NO_SILK"))
    )
    (comp (ref "JP574")
      (value "M01PTH_SMD_3.25X0.85MM_NO_SILK")
      (footprint "eagle-import:1X01_SMD_3.25X0.85MM_NO_SILK")
      (libsource (lib "eagle-import") (part "M01PTH_SMD_3.25X0.85MM_NO_SILK"))
    )
    (comp (ref "JP575")
      (value "M01PTH_SMD_3.25X0.85MM_NO_SILK")
      (footprint "eagle-import:1X01_SMD_3.25X0.85MM_NO_SILK")
      (libsource (lib "eagle-import") (part "M01PTH_SMD_3.25X0.85MM_NO_SILK"))
    )
    (comp (ref "JP576")
      (value "M01PTH_SMD_3.25X0.85MM_NO_SILK")
      (footprint "eagle-import:1X01_SMD_3.25X0.85MM_NO_SILK")
      (libsource (lib "eagle-import") (part "M01PTH_SMD_3.25X0.85MM_NO_SILK"))
    )
    (comp (ref "JP577")
      (value "M01PTH_SMD_3.25X0.85MM_NO_SILK")
      (footprint "eagle-import:1X01_SMD_3.25X0.85MM_NO_SILK")
      (libsource (lib "eagle-import") (part "M01PTH_SMD_3.25X0.85MM_NO_SILK"))
    )
    (comp (ref "JP578")
      (value "M01PTH_SMD_3.25X0.85MM_NO_SILK")
      (footprint "eagle-import:1X01_SMD_3.25X0.85MM_NO_SILK")
      (libsource (lib "eagle-import") (part "M01PTH_SMD_3.25X0.85MM_NO_SILK"))
    )
    (comp (ref "JP579")
      (value "M01PTH_SMD_3.25X0.85MM_NO_SILK")
      (footprint "eagle-import:1X01_SMD_3.25X0.85MM_NO_SILK")
      (libsource (lib "eagle-import") (part "M01PTH_SMD_3.25X0.85MM_NO_SILK"))
    )
    (comp (ref "JP580")
      (value "M01PTH_SMD_3.25X0.85MM_NO_SILK")
      (footprint "eagle-import:1X01_SMD_3.25X0.85MM_NO_SILK")
      (libsource (lib "eagle-import") (part "M01PTH_SMD_3.25X0.85MM_NO_SILK"))
    )
    (comp (ref "JP581")
      (value "M01PTH_SMD_3.25X0.85MM_NO_SILK")
      (footprint "eagle-import:1X01_SMD_3.25X0.85MM_NO_SILK")
      (libsource (lib "eagle-import") (part "M01PTH_SMD_3.25X0.85MM_NO_SILK"))
    )
    (comp (ref "JP582")
      (value "M01PTH_SMD_3.25X0.85MM_NO_SILK")
      (footprint "eagle-import:1X01_SMD_3.25X0.85MM_NO_SILK")
      (libsource (lib "eagle-import") (part "M01PTH_SMD_3.25X0.85MM_NO_SILK"))
    )
    (comp (ref "JP583")
      (value "M01PTH_SMD_3.25X0.85MM_NO_SILK")
      (footprint "eagle-import:1X01_SMD_3.25X0.85MM_NO_SILK")
      (libsource (lib "eagle-import") (part "M01PTH_SMD_3.25X0.85MM_NO_SILK"))
    )
    (comp (ref "JP584")
      (value "M01PTH_SMD_3.25X0.85MM_NO_SILK")
      (footprint "eagle-import:1X01_SMD_3.25X0.85MM_NO_SILK")
      (libsource (lib "eagle-import") (part "M01PTH_SMD_3.25X0.85MM_NO_SILK"))
    )
    (comp (ref "JP585")
      (value "M01PTH_SMD_3.25X0.85MM_NO_SILK")
      (footprint "eagle-import:1X01_SMD_3.25X0.85MM_NO_SILK")
      (libsource (lib "eagle-import") (part "M01PTH_SMD_3.25X0.85MM_NO_SILK"))
    )
    (comp (ref "JP586")
      (value "M01PTH_SMD_3.25X0.85MM_NO_SILK")
      (footprint "eagle-import:1X01_SMD_3.25X0.85MM_NO_SILK")
      (libsource (lib "eagle-import") (part "M01PTH_SMD_3.25X0.85MM_NO_SILK"))
    )
    (comp (ref "JP587")
      (value "M01PTH_SMD_3.25X0.85MM_NO_SILK")
      (footprint "eagle-import:1X01_SMD_3.25X0.85MM_NO_SILK")
      (libsource (lib "eagle-import") (part "M01PTH_SMD_3.25X0.85MM_NO_SILK"))
    )
    (comp (ref "JP588")
      (value "M01PTH_SMD_3.25X0.85MM_NO_SILK")
      (footprint "eagle-import:1X01_SMD_3.25X0.85MM_NO_SILK")
      (libsource (lib "eagle-import") (part "M01PTH_SMD_3.25X0.85MM_NO_SILK"))
    )
    (comp (ref "JP589")
      (value "M01PTH_SMD_3.25X0.85MM_NO_SILK")
      (footprint "eagle-import:1X01_SMD_3.25X0.85MM_NO_SILK")
      (libsource (lib "eagle-import") (part "M01PTH_SMD_3.25X0.85MM_NO_SILK"))
    )
    (comp (ref "JP590")
      (value "M01PTH_SMD_3.25X0.85MM_NO_SILK")
      (footprint "eagle-import:1X01_SMD_3.25X0.85MM_NO_SILK")
      (libsource (lib "eagle-import") (part "M01PTH_SMD_3.25X0.85MM_NO_SILK"))
    )
    (comp (ref "JP591")
      (value "M01PTH_SMD_3.25X0.85MM_NO_SILK")
      (footprint "eagle-import:1X01_SMD_3.25X0.85MM_NO_SILK")
      (libsource (lib "eagle-import") (part "M01PTH_SMD_3.25X0.85MM_NO_SILK"))
    )
    (comp (ref "JP592")
      (value "M01PTH_SMD_3.25X0.85MM_NO_SILK")
      (footprint "eagle-import:1X01_SMD_3.25X0.85MM_NO_SILK")
      (libsource (lib "eagle-import") (part "M01PTH_SMD_3.25X0.85MM_NO_SILK"))
    )
    (comp (ref "JP593")
      (value "M01PTH_SMD_3.25X0.85MM_NO_SILK")
      (footprint "eagle-import:1X01_SMD_3.25X0.85MM_NO_SILK")
      (libsource (lib "eagle-import") (part "M01PTH_SMD_3.25X0.85MM_NO_SILK"))
    )
    (comp (ref "JP594")
      (value "M01PTH_SMD_3.25X0.85MM_NO_SILK")
      (footprint "eagle-import:1X01_SMD_3.25X0.85MM_NO_SILK")
      (libsource (lib "eagle-import") (part "M01PTH_SMD_3.25X0.85MM_NO_SILK"))
    )
    (comp (ref "JP595")
      (value "M01PTH_SMD_3.25X0.85MM_NO_SILK")
      (footprint "eagle-import:1X01_SMD_3.25X0.85MM_NO_SILK")
      (libsource (lib "eagle-import") (part "M01PTH_SMD_3.25X0.85MM_NO_SILK"))
    )
    (comp (ref "JP596")
      (value "M01PTH_SMD_3.25X0.85MM_NO_SILK")
      (footprint "eagle-import:1X01_SMD_3.25X0.85MM_NO_SILK")
      (libsource (lib "eagle-import") (part "M01PTH_SMD_3.25X0.85MM_NO_SILK"))
    )
    (comp (ref "JP597")
      (value "M01PTH_SMD_3.25X0.85MM_NO_SILK")
      (footprint "eagle-import:1X01_SMD_3.25X0.85MM_NO_SILK")
      (libsource (lib "eagle-import") (part "M01PTH_SMD_3.25X0.85MM_NO_SILK"))
    )
    (comp (ref "JP598")
      (value "M01PTH_SMD_3.25X0.85MM_NO_SILK")
      (footprint "eagle-import:1X01_SMD_3.25X0.85MM_NO_SILK")
      (libsource (lib "eagle-import") (part "M01PTH_SMD_3.25X0.85MM_NO_SILK"))
    )
    (comp (ref "JP599")
      (value "M01PTH_SMD_3.25X0.85MM_NO_SILK")
      (footprint "eagle-import:1X01_SMD_3.25X0.85MM_NO_SILK")
      (libsource (lib "eagle-import") (part "M01PTH_SMD_3.25X0.85MM_NO_SILK"))
    )
    (comp (ref "JP600")
      (value "M01PTH_SMD_3.25X0.85MM_NO_SILK")
      (footprint "eagle-import:1X01_SMD_3.25X0.85MM_NO_SILK")
      (libsource (lib "eagle-import") (part "M01PTH_SMD_3.25X0.85MM_NO_SILK"))
    )
    (comp (ref "JP601")
      (value "M01PTH_SMD_3.25X0.85MM_NO_SILK")
      (footprint "eagle-import:1X01_SMD_3.25X0.85MM_NO_SILK")
      (libsource (lib "eagle-import") (part "M01PTH_SMD_3.25X0.85MM_NO_SILK"))
    )
    (comp (ref "JP602")
      (value "M01PTH_SMD_3.25X0.85MM_NO_SILK")
      (footprint "eagle-import:1X01_SMD_3.25X0.85MM_NO_SILK")
      (libsource (lib "eagle-import") (part "M01PTH_SMD_3.25X0.85MM_NO_SILK"))
    )
    (comp (ref "JP603")
      (value "M01PTH_SMD_3.25X0.85MM_NO_SILK")
      (footprint "eagle-import:1X01_SMD_3.25X0.85MM_NO_SILK")
      (libsource (lib "eagle-import") (part "M01PTH_SMD_3.25X0.85MM_NO_SILK"))
    )
    (comp (ref "JP604")
      (value "M01PTH_SMD_3.25X0.85MM_NO_SILK")
      (footprint "eagle-import:1X01_SMD_3.25X0.85MM_NO_SILK")
      (libsource (lib "eagle-import") (part "M01PTH_SMD_3.25X0.85MM_NO_SILK"))
    )
    (comp (ref "JP605")
      (value "M01PTH_SMD_3.25X0.85MM_NO_SILK")
      (footprint "eagle-import:1X01_SMD_3.25X0.85MM_NO_SILK")
      (libsource (lib "eagle-import") (part "M01PTH_SMD_3.25X0.85MM_NO_SILK"))
    )
    (comp (ref "JP606")
      (value "M01PTH_SMD_3.25X0.85MM_NO_SILK")
      (footprint "eagle-import:1X01_SMD_3.25X0.85MM_NO_SILK")
      (libsource (lib "eagle-import") (part "M01PTH_SMD_3.25X0.85MM_NO_SILK"))
    )
    (comp (ref "JP607")
      (value "M01PTH_SMD_3.25X0.85MM_NO_SILK")
      (footprint "eagle-import:1X01_SMD_3.25X0.85MM_NO_SILK")
      (libsource (lib "eagle-import") (part "M01PTH_SMD_3.25X0.85MM_NO_SILK"))
    )
    (comp (ref "JP608")
      (value "M01PTH_SMD_3.25X0.85MM_NO_SILK")
      (footprint "eagle-import:1X01_SMD_3.25X0.85MM_NO_SILK")
      (libsource (lib "eagle-import") (part "M01PTH_SMD_3.25X0.85MM_NO_SILK"))
    )
    (comp (ref "JP609")
      (value "M01PTH_SMD_3.25X0.85MM_NO_SILK")
      (footprint "eagle-import:1X01_SMD_3.25X0.85MM_NO_SILK")
      (libsource (lib "eagle-import") (part "M01PTH_SMD_3.25X0.85MM_NO_SILK"))
    )
    (comp (ref "JP610")
      (value "M01PTH_SMD_3.25X0.85MM_NO_SILK")
      (footprint "eagle-import:1X01_SMD_3.25X0.85MM_NO_SILK")
      (libsource (lib "eagle-import") (part "M01PTH_SMD_3.25X0.85MM_NO_SILK"))
    )
    (comp (ref "JP611")
      (value "M01PTH_SMD_3.25X0.85MM_NO_SILK")
      (footprint "eagle-import:1X01_SMD_3.25X0.85MM_NO_SILK")
      (libsource (lib "eagle-import") (part "M01PTH_SMD_3.25X0.85MM_NO_SILK"))
    )
    (comp (ref "JP612")
      (value "M01PTH_SMD_3.25X0.85MM_NO_SILK")
      (footprint "eagle-import:1X01_SMD_3.25X0.85MM_NO_SILK")
      (libsource (lib "eagle-import") (part "M01PTH_SMD_3.25X0.85MM_NO_SILK"))
    )
    (comp (ref "JP613")
      (value "M01PTH_SMD_3.25X0.85MM_NO_SILK")
      (footprint "eagle-import:1X01_SMD_3.25X0.85MM_NO_SILK")
      (libsource (lib "eagle-import") (part "M01PTH_SMD_3.25X0.85MM_NO_SILK"))
    )
    (comp (ref "JP614")
      (value "M01PTH_SMD_3.25X0.85MM_NO_SILK")
      (footprint "eagle-import:1X01_SMD_3.25X0.85MM_NO_SILK")
      (libsource (lib "eagle-import") (part "M01PTH_SMD_3.25X0.85MM_NO_SILK"))
    )
    (comp (ref "JP615")
      (value "M01PTH_SMD_3.25X0.85MM_NO_SILK")
      (footprint "eagle-import:1X01_SMD_3.25X0.85MM_NO_SILK")
      (libsource (lib "eagle-import") (part "M01PTH_SMD_3.25X0.85MM_NO_SILK"))
    )
    (comp (ref "JP616")
      (value "M01PTH_SMD_3.25X0.85MM_NO_SILK")
      (footprint "eagle-import:1X01_SMD_3.25X0.85MM_NO_SILK")
      (libsource (lib "eagle-import") (part "M01PTH_SMD_3.25X0.85MM_NO_SILK"))
    )
    (comp (ref "JP617")
      (value "M01PTH_SMD_3.25X0.85MM_NO_SILK")
      (footprint "eagle-import:1X01_SMD_3.25X0.85MM_NO_SILK")
      (libsource (lib "eagle-import") (part "M01PTH_SMD_3.25X0.85MM_NO_SILK"))
    )
    (comp (ref "JP618")
      (value "M01PTH_SMD_3.25X0.85MM_NO_SILK")
      (footprint "eagle-import:1X01_SMD_3.25X0.85MM_NO_SILK")
      (libsource (lib "eagle-import") (part "M01PTH_SMD_3.25X0.85MM_NO_SILK"))
    )
    (comp (ref "JP619")
      (value "M01PTH_SMD_3.25X0.85MM_NO_SILK")
      (footprint "eagle-import:1X01_SMD_3.25X0.85MM_NO_SILK")
      (libsource (lib "eagle-import") (part "M01PTH_SMD_3.25X0.85MM_NO_SILK"))
    )
    (comp (ref "JP620")
      (value "M01PTH_SMD_3.25X0.85MM_NO_SILK")
      (footprint "eagle-import:1X01_SMD_3.25X0.85MM_NO_SILK")
      (libsource (lib "eagle-import") (part "M01PTH_SMD_3.25X0.85MM_NO_SILK"))
    )
    (comp (ref "JP621")
      (value "M01PTH_SMD_3.25X0.85MM_NO_SILK")
      (footprint "eagle-import:1X01_SMD_3.25X0.85MM_NO_SILK")
      (libsource (lib "eagle-import") (part "M01PTH_SMD_3.25X0.85MM_NO_SILK"))
    )
    (comp (ref "JP622")
      (value "M01PTH_SMD_3.25X0.85MM_NO_SILK")
      (footprint "eagle-import:1X01_SMD_3.25X0.85MM_NO_SILK")
      (libsource (lib "eagle-import") (part "M01PTH_SMD_3.25X0.85MM_NO_SILK"))
    )
    (comp (ref "JP623")
      (value "M01PTH_SMD_3.25X0.85MM_NO_SILK")
      (footprint "eagle-import:1X01_SMD_3.25X0.85MM_NO_SILK")
      (libsource (lib "eagle-import") (part "M01PTH_SMD_3.25X0.85MM_NO_SILK"))
    )
    (comp (ref "JP624")
      (value "M01PTH_SMD_3.25X0.85MM_NO_SILK")
      (footprint "eagle-import:1X01_SMD_3.25X0.85MM_NO_SILK")
      (libsource (lib "eagle-import") (part "M01PTH_SMD_3.25X0.85MM_NO_SILK"))
    )
    (comp (ref "JP625")
      (value "M01PTH_SMD_3.25X0.85MM_NO_SILK")
      (footprint "eagle-import:1X01_SMD_3.25X0.85MM_NO_SILK")
      (libsource (lib "eagle-import") (part "M01PTH_SMD_3.25X0.85MM_NO_SILK"))
    )
    (comp (ref "JP626")
      (value "M01PTH_SMD_3.25X0.85MM_NO_SILK")
      (footprint "eagle-import:1X01_SMD_3.25X0.85MM_NO_SILK")
      (libsource (lib "eagle-import") (part "M01PTH_SMD_3.25X0.85MM_NO_SILK"))
    )
    (comp (ref "JP627")
      (value "M01PTH_SMD_3.25X0.85MM_NO_SILK")
      (footprint "eagle-import:1X01_SMD_3.25X0.85MM_NO_SILK")
      (libsource (lib "eagle-import") (part "M01PTH_SMD_3.25X0.85MM_NO_SILK"))
    )
    (comp (ref "JP628")
      (value "M01PTH_SMD_3.25X0.85MM_NO_SILK")
      (footprint "eagle-import:1X01_SMD_3.25X0.85MM_NO_SILK")
      (libsource (lib "eagle-import") (part "M01PTH_SMD_3.25X0.85MM_NO_SILK"))
    )
    (comp (ref "JP629")
      (value "M01PTH_SMD_3.25X0.85MM_NO_SILK")
      (footprint "eagle-import:1X01_SMD_3.25X0.85MM_NO_SILK")
      (libsource (lib "eagle-import") (part "M01PTH_SMD_3.25X0.85MM_NO_SILK"))
    )
    (comp (ref "JP630")
      (value "M01PTH_SMD_3.25X0.85MM_NO_SILK")
      (footprint "eagle-import:1X01_SMD_3.25X0.85MM_NO_SILK")
      (libsource (lib "eagle-import") (part "M01PTH_SMD_3.25X0.85MM_NO_SILK"))
    )
    (comp (ref "JP631")
      (value "M01PTH_SMD_3.25X0.85MM_NO_SILK")
      (footprint "eagle-import:1X01_SMD_3.25X0.85MM_NO_SILK")
      (libsource (lib "eagle-import") (part "M01PTH_SMD_3.25X0.85MM_NO_SILK"))
    )
    (comp (ref "JP632")
      (value "M01PTH_SMD_3.25X0.85MM_NO_SILK")
      (footprint "eagle-import:1X01_SMD_3.25X0.85MM_NO_SILK")
      (libsource (lib "eagle-import") (part "M01PTH_SMD_3.25X0.85MM_NO_SILK"))
    )
    (comp (ref "JP633")
      (value "M01PTH_SMD_3.25X0.85MM_NO_SILK")
      (footprint "eagle-import:1X01_SMD_3.25X0.85MM_NO_SILK")
      (libsource (lib "eagle-import") (part "M01PTH_SMD_3.25X0.85MM_NO_SILK"))
    )
    (comp (ref "JP634")
      (value "M01PTH_SMD_3.25X0.85MM_NO_SILK")
      (footprint "eagle-import:1X01_SMD_3.25X0.85MM_NO_SILK")
      (libsource (lib "eagle-import") (part "M01PTH_SMD_3.25X0.85MM_NO_SILK"))
    )
    (comp (ref "JP635")
      (value "M01PTH_SMD_3.25X0.85MM_NO_SILK")
      (footprint "eagle-import:1X01_SMD_3.25X0.85MM_NO_SILK")
      (libsource (lib "eagle-import") (part "M01PTH_SMD_3.25X0.85MM_NO_SILK"))
    )
    (comp (ref "JP636")
      (value "M01PTH_SMD_3.25X0.85MM_NO_SILK")
      (footprint "eagle-import:1X01_SMD_3.25X0.85MM_NO_SILK")
      (libsource (lib "eagle-import") (part "M01PTH_SMD_3.25X0.85MM_NO_SILK"))
    )
    (comp (ref "JP637")
      (value "M01PTH_SMD_3.25X0.85MM_NO_SILK")
      (footprint "eagle-import:1X01_SMD_3.25X0.85MM_NO_SILK")
      (libsource (lib "eagle-import") (part "M01PTH_SMD_3.25X0.85MM_NO_SILK"))
    )
    (comp (ref "JP638")
      (value "M01PTH_SMD_3.25X0.85MM_NO_SILK")
      (footprint "eagle-import:1X01_SMD_3.25X0.85MM_NO_SILK")
      (libsource (lib "eagle-import") (part "M01PTH_SMD_3.25X0.85MM_NO_SILK"))
    )
    (comp (ref "JP639")
      (value "M01PTH_SMD_3.25X0.85MM_NO_SILK")
      (footprint "eagle-import:1X01_SMD_3.25X0.85MM_NO_SILK")
      (libsource (lib "eagle-import") (part "M01PTH_SMD_3.25X0.85MM_NO_SILK"))
    )
    (comp (ref "JP640")
      (value "M01PTH_SMD_3.25X0.85MM_NO_SILK")
      (footprint "eagle-import:1X01_SMD_3.25X0.85MM_NO_SILK")
      (libsource (lib "eagle-import") (part "M01PTH_SMD_3.25X0.85MM_NO_SILK"))
    )
    (comp (ref "JP641")
      (value "M01PTH_SMD_3.25X0.85MM_NO_SILK")
      (footprint "eagle-import:1X01_SMD_3.25X0.85MM_NO_SILK")
      (libsource (lib "eagle-import") (part "M01PTH_SMD_3.25X0.85MM_NO_SILK"))
    )
    (comp (ref "JP642")
      (value "M01PTH_SMD_3.25X0.85MM_NO_SILK")
      (footprint "eagle-import:1X01_SMD_3.25X0.85MM_NO_SILK")
      (libsource (lib "eagle-import") (part "M01PTH_SMD_3.25X0.85MM_NO_SILK"))
    )
    (comp (ref "JP643")
      (value "M01PTH_SMD_3.25X0.85MM_NO_SILK")
      (footprint "eagle-import:1X01_SMD_3.25X0.85MM_NO_SILK")
      (libsource (lib "eagle-import") (part "M01PTH_SMD_3.25X0.85MM_NO_SILK"))
    )
    (comp (ref "JP644")
      (value "M01PTH_SMD_3.25X0.85MM_NO_SILK")
      (footprint "eagle-import:1X01_SMD_3.25X0.85MM_NO_SILK")
      (libsource (lib "eagle-import") (part "M01PTH_SMD_3.25X0.85MM_NO_SILK"))
    )
    (comp (ref "JP645")
      (value "M01PTH_SMD_3.25X0.85MM_NO_SILK")
      (footprint "eagle-import:1X01_SMD_3.25X0.85MM_NO_SILK")
      (libsource (lib "eagle-import") (part "M01PTH_SMD_3.25X0.85MM_NO_SILK"))
    )
    (comp (ref "JP646")
      (value "M01PTH_SMD_3.25X0.85MM_NO_SILK")
      (footprint "eagle-import:1X01_SMD_3.25X0.85MM_NO_SILK")
      (libsource (lib "eagle-import") (part "M01PTH_SMD_3.25X0.85MM_NO_SILK"))
    )
    (comp (ref "JP647")
      (value "M01PTH_SMD_3.25X0.85MM_NO_SILK")
      (footprint "eagle-import:1X01_SMD_3.25X0.85MM_NO_SILK")
      (libsource (lib "eagle-import") (part "M01PTH_SMD_3.25X0.85MM_NO_SILK"))
    )
    (comp (ref "JP648")
      (value "M01PTH_SMD_3.25X0.85MM_NO_SILK")
      (footprint "eagle-import:1X01_SMD_3.25X0.85MM_NO_SILK")
      (libsource (lib "eagle-import") (part "M01PTH_SMD_3.25X0.85MM_NO_SILK"))
    )
    (comp (ref "JP649")
      (value "M01PTH_SMD_3.25X0.85MM_NO_SILK")
      (footprint "eagle-import:1X01_SMD_3.25X0.85MM_NO_SILK")
      (libsource (lib "eagle-import") (part "M01PTH_SMD_3.25X0.85MM_NO_SILK"))
    )
    (comp (ref "JP650")
      (value "M01PTH_SMD_3.25X0.85MM_NO_SILK")
      (footprint "eagle-import:1X01_SMD_3.25X0.85MM_NO_SILK")
      (libsource (lib "eagle-import") (part "M01PTH_SMD_3.25X0.85MM_NO_SILK"))
    )
    (comp (ref "JP651")
      (value "M01PTH_SMD_3.25X0.85MM_NO_SILK")
      (footprint "eagle-import:1X01_SMD_3.25X0.85MM_NO_SILK")
      (libsource (lib "eagle-import") (part "M01PTH_SMD_3.25X0.85MM_NO_SILK"))
    )
    (comp (ref "JP652")
      (value "M01PTH_SMD_3.25X0.85MM_NO_SILK")
      (footprint "eagle-import:1X01_SMD_3.25X0.85MM_NO_SILK")
      (libsource (lib "eagle-import") (part "M01PTH_SMD_3.25X0.85MM_NO_SILK"))
    )
    (comp (ref "JP653")
      (value "M01PTH_SMD_3.25X0.85MM_NO_SILK")
      (footprint "eagle-import:1X01_SMD_3.25X0.85MM_NO_SILK")
      (libsource (lib "eagle-import") (part "M01PTH_SMD_3.25X0.85MM_NO_SILK"))
    )
    (comp (ref "JP654")
      (value "M01PTH_SMD_3.25X0.85MM_NO_SILK")
      (footprint "eagle-import:1X01_SMD_3.25X0.85MM_NO_SILK")
      (libsource (lib "eagle-import") (part "M01PTH_SMD_3.25X0.85MM_NO_SILK"))
    )
    (comp (ref "JP655")
      (value "M01PTH_SMD_3.25X0.85MM_NO_SILK")
      (footprint "eagle-import:1X01_SMD_3.25X0.85MM_NO_SILK")
      (libsource (lib "eagle-import") (part "M01PTH_SMD_3.25X0.85MM_NO_SILK"))
    )
    (comp (ref "JP656")
      (value "M01PTH_SMD_3.25X0.85MM_NO_SILK")
      (footprint "eagle-import:1X01_SMD_3.25X0.85MM_NO_SILK")
      (libsource (lib "eagle-import") (part "M01PTH_SMD_3.25X0.85MM_NO_SILK"))
    )
    (comp (ref "JP657")
      (value "M01PTH_SMD_3.25X0.85MM_NO_SILK")
      (footprint "eagle-import:1X01_SMD_3.25X0.85MM_NO_SILK")
      (libsource (lib "eagle-import") (part "M01PTH_SMD_3.25X0.85MM_NO_SILK"))
    )
    (comp (ref "JP658")
      (value "M01PTH_SMD_3.25X0.85MM_NO_SILK")
      (footprint "eagle-import:1X01_SMD_3.25X0.85MM_NO_SILK")
      (libsource (lib "eagle-import") (part "M01PTH_SMD_3.25X0.85MM_NO_SILK"))
    )
    (comp (ref "JP659")
      (value "M01PTH_SMD_3.25X0.85MM_NO_SILK")
      (footprint "eagle-import:1X01_SMD_3.25X0.85MM_NO_SILK")
      (libsource (lib "eagle-import") (part "M01PTH_SMD_3.25X0.85MM_NO_SILK"))
    )
    (comp (ref "JP660")
      (value "M01PTH_SMD_3.25X0.85MM_NO_SILK")
      (footprint "eagle-import:1X01_SMD_3.25X0.85MM_NO_SILK")
      (libsource (lib "eagle-import") (part "M01PTH_SMD_3.25X0.85MM_NO_SILK"))
    )
    (comp (ref "JP661")
      (value "M01PTH_SMD_3.25X0.85MM_NO_SILK")
      (footprint "eagle-import:1X01_SMD_3.25X0.85MM_NO_SILK")
      (libsource (lib "eagle-import") (part "M01PTH_SMD_3.25X0.85MM_NO_SILK"))
    )
    (comp (ref "JP662")
      (value "M01PTH_SMD_3.25X0.85MM_NO_SILK")
      (footprint "eagle-import:1X01_SMD_3.25X0.85MM_NO_SILK")
      (libsource (lib "eagle-import") (part "M01PTH_SMD_3.25X0.85MM_NO_SILK"))
    )
    (comp (ref "JP663")
      (value "M01PTH_SMD_3.25X0.85MM_NO_SILK")
      (footprint "eagle-import:1X01_SMD_3.25X0.85MM_NO_SILK")
      (libsource (lib "eagle-import") (part "M01PTH_SMD_3.25X0.85MM_NO_SILK"))
    )
    (comp (ref "JP664")
      (value "M01PTH_SMD_3.25X0.85MM_NO_SILK")
      (footprint "eagle-import:1X01_SMD_3.25X0.85MM_NO_SILK")
      (libsource (lib "eagle-import") (part "M01PTH_SMD_3.25X0.85MM_NO_SILK"))
    )
    (comp (ref "JP665")
      (value "M01PTH_SMD_3.25X0.85MM_NO_SILK")
      (footprint "eagle-import:1X01_SMD_3.25X0.85MM_NO_SILK")
      (libsource (lib "eagle-import") (part "M01PTH_SMD_3.25X0.85MM_NO_SILK"))
    )
    (comp (ref "JP666")
      (value "M01PTH_SMD_3.25X0.85MM_NO_SILK")
      (footprint "eagle-import:1X01_SMD_3.25X0.85MM_NO_SILK")
      (libsource (lib "eagle-import") (part "M01PTH_SMD_3.25X0.85MM_NO_SILK"))
    )
    (comp (ref "JP667")
      (value "M01PTH_SMD_3.25X0.85MM_NO_SILK")
      (footprint "eagle-import:1X01_SMD_3.25X0.85MM_NO_SILK")
      (libsource (lib "eagle-import") (part "M01PTH_SMD_3.25X0.85MM_NO_SILK"))
    )
    (comp (ref "JP668")
      (value "M01PTH_SMD_3.25X0.85MM_NO_SILK")
      (footprint "eagle-import:1X01_SMD_3.25X0.85MM_NO_SILK")
      (libsource (lib "eagle-import") (part "M01PTH_SMD_3.25X0.85MM_NO_SILK"))
    )
    (comp (ref "JP669")
      (value "M01PTH_SMD_3.25X0.85MM_NO_SILK")
      (footprint "eagle-import:1X01_SMD_3.25X0.85MM_NO_SILK")
      (libsource (lib "eagle-import") (part "M01PTH_SMD_3.25X0.85MM_NO_SILK"))
    )
    (comp (ref "JP670")
      (value "M01PTH_SMD_3.25X0.85MM_NO_SILK")
      (footprint "eagle-import:1X01_SMD_3.25X0.85MM_NO_SILK")
      (libsource (lib "eagle-import") (part "M01PTH_SMD_3.25X0.85MM_NO_SILK"))
    )
    (comp (ref "JP671")
      (value "M01PTH_SMD_3.25X0.85MM_NO_SILK")
      (footprint "eagle-import:1X01_SMD_3.25X0.85MM_NO_SILK")
      (libsource (lib "eagle-import") (part "M01PTH_SMD_3.25X0.85MM_NO_SILK"))
    )
    (comp (ref "JP672")
      (value "M01PTH_SMD_3.25X0.85MM_NO_SILK")
      (footprint "eagle-import:1X01_SMD_3.25X0.85MM_NO_SILK")
      (libsource (lib "eagle-import") (part "M01PTH_SMD_3.25X0.85MM_NO_SILK"))
    )
    (comp (ref "JP673")
      (value "M01PTH_SMD_3.25X0.85MM_NO_SILK")
      (footprint "eagle-import:1X01_SMD_3.25X0.85MM_NO_SILK")
      (libsource (lib "eagle-import") (part "M01PTH_SMD_3.25X0.85MM_NO_SILK"))
    )
    (comp (ref "JP674")
      (value "M01PTH_SMD_3.25X0.85MM_NO_SILK")
      (footprint "eagle-import:1X01_SMD_3.25X0.85MM_NO_SILK")
      (libsource (lib "eagle-import") (part "M01PTH_SMD_3.25X0.85MM_NO_SILK"))
    )
    (comp (ref "JP675")
      (value "M01PTH_SMD_3.25X0.85MM_NO_SILK")
      (footprint "eagle-import:1X01_SMD_3.25X0.85MM_NO_SILK")
      (libsource (lib "eagle-import") (part "M01PTH_SMD_3.25X0.85MM_NO_SILK"))
    )
    (comp (ref "JP676")
      (value "M01PTH_SMD_3.25X0.85MM_NO_SILK")
      (footprint "eagle-import:1X01_SMD_3.25X0.85MM_NO_SILK")
      (libsource (lib "eagle-import") (part "M01PTH_SMD_3.25X0.85MM_NO_SILK"))
    )
    (comp (ref "JP677")
      (value "M01PTH_SMD_3.25X0.85MM_NO_SILK")
      (footprint "eagle-import:1X01_SMD_3.25X0.85MM_NO_SILK")
      (libsource (lib "eagle-import") (part "M01PTH_SMD_3.25X0.85MM_NO_SILK"))
    )
    (comp (ref "JP678")
      (value "M01PTH_SMD_3.25X0.85MM_NO_SILK")
      (footprint "eagle-import:1X01_SMD_3.25X0.85MM_NO_SILK")
      (libsource (lib "eagle-import") (part "M01PTH_SMD_3.25X0.85MM_NO_SILK"))
    )
    (comp (ref "JP679")
      (value "M01PTH_SMD_3.25X0.85MM_NO_SILK")
      (footprint "eagle-import:1X01_SMD_3.25X0.85MM_NO_SILK")
      (libsource (lib "eagle-import") (part "M01PTH_SMD_3.25X0.85MM_NO_SILK"))
    )
    (comp (ref "JP680")
      (value "M01PTH_SMD_3.25X0.85MM_NO_SILK")
      (footprint "eagle-import:1X01_SMD_3.25X0.85MM_NO_SILK")
      (libsource (lib "eagle-import") (part "M01PTH_SMD_3.25X0.85MM_NO_SILK"))
    )
    (comp (ref "JP681")
      (value "M01PTH_SMD_3.25X0.85MM_NO_SILK")
      (footprint "eagle-import:1X01_SMD_3.25X0.85MM_NO_SILK")
      (libsource (lib "eagle-import") (part "M01PTH_SMD_3.25X0.85MM_NO_SILK"))
    )
    (comp (ref "JP682")
      (value "M01PTH_SMD_3.25X0.85MM_NO_SILK")
      (footprint "eagle-import:1X01_SMD_3.25X0.85MM_NO_SILK")
      (libsource (lib "eagle-import") (part "M01PTH_SMD_3.25X0.85MM_NO_SILK"))
    )
    (comp (ref "JP683")
      (value "M01PTH_SMD_3.25X0.85MM_NO_SILK")
      (footprint "eagle-import:1X01_SMD_3.25X0.85MM_NO_SILK")
      (libsource (lib "eagle-import") (part "M01PTH_SMD_3.25X0.85MM_NO_SILK"))
    )
    (comp (ref "JP684")
      (value "M01PTH_SMD_3.25X0.85MM_NO_SILK")
      (footprint "eagle-import:1X01_SMD_3.25X0.85MM_NO_SILK")
      (libsource (lib "eagle-import") (part "M01PTH_SMD_3.25X0.85MM_NO_SILK"))
    )
    (comp (ref "JP685")
      (value "M01PTH_SMD_3.25X0.85MM_NO_SILK")
      (footprint "eagle-import:1X01_SMD_3.25X0.85MM_NO_SILK")
      (libsource (lib "eagle-import") (part "M01PTH_SMD_3.25X0.85MM_NO_SILK"))
    )
    (comp (ref "JP686")
      (value "M01PTH_SMD_3.25X0.85MM_NO_SILK")
      (footprint "eagle-import:1X01_SMD_3.25X0.85MM_NO_SILK")
      (libsource (lib "eagle-import") (part "M01PTH_SMD_3.25X0.85MM_NO_SILK"))
    )
    (comp (ref "JP687")
      (value "M01PTH_SMD_3.25X0.85MM_NO_SILK")
      (footprint "eagle-import:1X01_SMD_3.25X0.85MM_NO_SILK")
      (libsource (lib "eagle-import") (part "M01PTH_SMD_3.25X0.85MM_NO_SILK"))
    )
    (comp (ref "JP688")
      (value "M01PTH_SMD_3.25X0.85MM_NO_SILK")
      (footprint "eagle-import:1X01_SMD_3.25X0.85MM_NO_SILK")
      (libsource (lib "eagle-import") (part "M01PTH_SMD_3.25X0.85MM_NO_SILK"))
    )
    (comp (ref "JP689")
      (value "M01PTH_SMD_3.25X0.85MM_NO_SILK")
      (footprint "eagle-import:1X01_SMD_3.25X0.85MM_NO_SILK")
      (libsource (lib "eagle-import") (part "M01PTH_SMD_3.25X0.85MM_NO_SILK"))
    )
    (comp (ref "JP690")
      (value "M01PTH_SMD_3.25X0.85MM_NO_SILK")
      (footprint "eagle-import:1X01_SMD_3.25X0.85MM_NO_SILK")
      (libsource (lib "eagle-import") (part "M01PTH_SMD_3.25X0.85MM_NO_SILK"))
    )
    (comp (ref "JP691")
      (value "M01PTH_SMD_3.25X0.85MM_NO_SILK")
      (footprint "eagle-import:1X01_SMD_3.25X0.85MM_NO_SILK")
      (libsource (lib "eagle-import") (part "M01PTH_SMD_3.25X0.85MM_NO_SILK"))
    )
    (comp (ref "JP692")
      (value "M01PTH_SMD_3.25X0.85MM_NO_SILK")
      (footprint "eagle-import:1X01_SMD_3.25X0.85MM_NO_SILK")
      (libsource (lib "eagle-import") (part "M01PTH_SMD_3.25X0.85MM_NO_SILK"))
    )
    (comp (ref "JP693")
      (value "M01PTH_SMD_3.25X0.85MM_NO_SILK")
      (footprint "eagle-import:1X01_SMD_3.25X0.85MM_NO_SILK")
      (libsource (lib "eagle-import") (part "M01PTH_SMD_3.25X0.85MM_NO_SILK"))
    )
    (comp (ref "JP694")
      (value "M01PTH_SMD_3.25X0.85MM_NO_SILK")
      (footprint "eagle-import:1X01_SMD_3.25X0.85MM_NO_SILK")
      (libsource (lib "eagle-import") (part "M01PTH_SMD_3.25X0.85MM_NO_SILK"))
    )
    (comp (ref "JP695")
      (value "M01PTH_SMD_3.25X0.85MM_NO_SILK")
      (footprint "eagle-import:1X01_SMD_3.25X0.85MM_NO_SILK")
      (libsource (lib "eagle-import") (part "M01PTH_SMD_3.25X0.85MM_NO_SILK"))
    )
    (comp (ref "JP696")
      (value "M01PTH_SMD_3.25X0.85MM_NO_SILK")
      (footprint "eagle-import:1X01_SMD_3.25X0.85MM_NO_SILK")
      (libsource (lib "eagle-import") (part "M01PTH_SMD_3.25X0.85MM_NO_SILK"))
    )
    (comp (ref "JP697")
      (value "M01PTH_SMD_3.25X0.85MM_NO_SILK")
      (footprint "eagle-import:1X01_SMD_3.25X0.85MM_NO_SILK")
      (libsource (lib "eagle-import") (part "M01PTH_SMD_3.25X0.85MM_NO_SILK"))
    )
    (comp (ref "JP698")
      (value "M01PTH_SMD_3.25X0.85MM_NO_SILK")
      (footprint "eagle-import:1X01_SMD_3.25X0.85MM_NO_SILK")
      (libsource (lib "eagle-import") (part "M01PTH_SMD_3.25X0.85MM_NO_SILK"))
    )
    (comp (ref "JP699")
      (value "M01PTH_SMD_3.25X0.85MM_NO_SILK")
      (footprint "eagle-import:1X01_SMD_3.25X0.85MM_NO_SILK")
      (libsource (lib "eagle-import") (part "M01PTH_SMD_3.25X0.85MM_NO_SILK"))
    )
    (comp (ref "JP700")
      (value "M01PTH_SMD_3.25X0.85MM_NO_SILK")
      (footprint "eagle-import:1X01_SMD_3.25X0.85MM_NO_SILK")
      (libsource (lib "eagle-import") (part "M01PTH_SMD_3.25X0.85MM_NO_SILK"))
    )
    (comp (ref "JP701")
      (value "M01PTH_SMD_3.25X0.85MM_NO_SILK")
      (footprint "eagle-import:1X01_SMD_3.25X0.85MM_NO_SILK")
      (libsource (lib "eagle-import") (part "M01PTH_SMD_3.25X0.85MM_NO_SILK"))
    )
    (comp (ref "JP702")
      (value "M01PTH_SMD_3.25X0.85MM_NO_SILK")
      (footprint "eagle-import:1X01_SMD_3.25X0.85MM_NO_SILK")
      (libsource (lib "eagle-import") (part "M01PTH_SMD_3.25X0.85MM_NO_SILK"))
    )
    (comp (ref "JP703")
      (value "M01PTH_SMD_3.25X0.85MM_NO_SILK")
      (footprint "eagle-import:1X01_SMD_3.25X0.85MM_NO_SILK")
      (libsource (lib "eagle-import") (part "M01PTH_SMD_3.25X0.85MM_NO_SILK"))
    )
    (comp (ref "JP704")
      (value "M01PTH_SMD_3.25X0.85MM_NO_SILK")
      (footprint "eagle-import:1X01_SMD_3.25X0.85MM_NO_SILK")
      (libsource (lib "eagle-import") (part "M01PTH_SMD_3.25X0.85MM_NO_SILK"))
    )
    (comp (ref "JP705")
      (value "M01PTH_SMD_3.25X0.85MM_NO_SILK")
      (footprint "eagle-import:1X01_SMD_3.25X0.85MM_NO_SILK")
      (libsource (lib "eagle-import") (part "M01PTH_SMD_3.25X0.85MM_NO_SILK"))
    )
    (comp (ref "JP706")
      (value "M01PTH_SMD_3.25X0.85MM_NO_SILK")
      (footprint "eagle-import:1X01_SMD_3.25X0.85MM_NO_SILK")
      (libsource (lib "eagle-import") (part "M01PTH_SMD_3.25X0.85MM_NO_SILK"))
    )
    (comp (ref "JP707")
      (value "M01PTH_SMD_3.25X0.85MM_NO_SILK")
      (footprint "eagle-import:1X01_SMD_3.25X0.85MM_NO_SILK")
      (libsource (lib "eagle-import") (part "M01PTH_SMD_3.25X0.85MM_NO_SILK"))
    )
    (comp (ref "JP708")
      (value "M01PTH_SMD_3.25X0.85MM_NO_SILK")
      (footprint "eagle-import:1X01_SMD_3.25X0.85MM_NO_SILK")
      (libsource (lib "eagle-import") (part "M01PTH_SMD_3.25X0.85MM_NO_SILK"))
    )
    (comp (ref "JP709")
      (value "M01PTH_SMD_3.25X0.85MM_NO_SILK")
      (footprint "eagle-import:1X01_SMD_3.25X0.85MM_NO_SILK")
      (libsource (lib "eagle-import") (part "M01PTH_SMD_3.25X0.85MM_NO_SILK"))
    )
    (comp (ref "JP710")
      (value "M01PTH_SMD_3.25X0.85MM_NO_SILK")
      (footprint "eagle-import:1X01_SMD_3.25X0.85MM_NO_SILK")
      (libsource (lib "eagle-import") (part "M01PTH_SMD_3.25X0.85MM_NO_SILK"))
    )
    (comp (ref "JP711")
      (value "M01PTH_SMD_3.25X0.85MM_NO_SILK")
      (footprint "eagle-import:1X01_SMD_3.25X0.85MM_NO_SILK")
      (libsource (lib "eagle-import") (part "M01PTH_SMD_3.25X0.85MM_NO_SILK"))
    )
    (comp (ref "JP712")
      (value "M01PTH_SMD_3.25X0.85MM_NO_SILK")
      (footprint "eagle-import:1X01_SMD_3.25X0.85MM_NO_SILK")
      (libsource (lib "eagle-import") (part "M01PTH_SMD_3.25X0.85MM_NO_SILK"))
    )
    (comp (ref "JP713")
      (value "M01PTH_SMD_3.25X0.85MM_NO_SILK")
      (footprint "eagle-import:1X01_SMD_3.25X0.85MM_NO_SILK")
      (libsource (lib "eagle-import") (part "M01PTH_SMD_3.25X0.85MM_NO_SILK"))
    )
    (comp (ref "JP714")
      (value "M01PTH_SMD_3.25X0.85MM_NO_SILK")
      (footprint "eagle-import:1X01_SMD_3.25X0.85MM_NO_SILK")
      (libsource (lib "eagle-import") (part "M01PTH_SMD_3.25X0.85MM_NO_SILK"))
    )
    (comp (ref "JP715")
      (value "M01PTH_SMD_3.25X0.85MM_NO_SILK")
      (footprint "eagle-import:1X01_SMD_3.25X0.85MM_NO_SILK")
      (libsource (lib "eagle-import") (part "M01PTH_SMD_3.25X0.85MM_NO_SILK"))
    )
    (comp (ref "JP716")
      (value "M01PTH_SMD_3.25X0.85MM_NO_SILK")
      (footprint "eagle-import:1X01_SMD_3.25X0.85MM_NO_SILK")
      (libsource (lib "eagle-import") (part "M01PTH_SMD_3.25X0.85MM_NO_SILK"))
    )
    (comp (ref "JP717")
      (value "M01PTH_SMD_3.25X0.85MM_NO_SILK")
      (footprint "eagle-import:1X01_SMD_3.25X0.85MM_NO_SILK")
      (libsource (lib "eagle-import") (part "M01PTH_SMD_3.25X0.85MM_NO_SILK"))
    )
    (comp (ref "JP718")
      (value "M01PTH_SMD_3.25X0.85MM_NO_SILK")
      (footprint "eagle-import:1X01_SMD_3.25X0.85MM_NO_SILK")
      (libsource (lib "eagle-import") (part "M01PTH_SMD_3.25X0.85MM_NO_SILK"))
    )
    (comp (ref "JP719")
      (value "M01PTH_SMD_3.25X0.85MM_NO_SILK")
      (footprint "eagle-import:1X01_SMD_3.25X0.85MM_NO_SILK")
      (libsource (lib "eagle-import") (part "M01PTH_SMD_3.25X0.85MM_NO_SILK"))
    )
    (comp (ref "JP720")
      (value "M01PTH_SMD_3.25X0.85MM_NO_SILK")
      (footprint "eagle-import:1X01_SMD_3.25X0.85MM_NO_SILK")
      (libsource (lib "eagle-import") (part "M01PTH_SMD_3.25X0.85MM_NO_SILK"))
    )
    (comp (ref "JP721")
      (value "M01PTH_SMD_3.25X0.85MM_NO_SILK")
      (footprint "eagle-import:1X01_SMD_3.25X0.85MM_NO_SILK")
      (libsource (lib "eagle-import") (part "M01PTH_SMD_3.25X0.85MM_NO_SILK"))
    )
    (comp (ref "JP722")
      (value "M01PTH_SMD_3.25X0.85MM_NO_SILK")
      (footprint "eagle-import:1X01_SMD_3.25X0.85MM_NO_SILK")
      (libsource (lib "eagle-import") (part "M01PTH_SMD_3.25X0.85MM_NO_SILK"))
    )
    (comp (ref "JP723")
      (value "M01PTH_SMD_3.25X0.85MM_NO_SILK")
      (footprint "eagle-import:1X01_SMD_3.25X0.85MM_NO_SILK")
      (libsource (lib "eagle-import") (part "M01PTH_SMD_3.25X0.85MM_NO_SILK"))
    )
    (comp (ref "JP724")
      (value "M01PTH_SMD_3.25X0.85MM_NO_SILK")
      (footprint "eagle-import:1X01_SMD_3.25X0.85MM_NO_SILK")
      (libsource (lib "eagle-import") (part "M01PTH_SMD_3.25X0.85MM_NO_SILK"))
    )
    (comp (ref "JP725")
      (value "M01PTH_SMD_3.25X0.85MM_NO_SILK")
      (footprint "eagle-import:1X01_SMD_3.25X0.85MM_NO_SILK")
      (libsource (lib "eagle-import") (part "M01PTH_SMD_3.25X0.85MM_NO_SILK"))
    )
    (comp (ref "JP726")
      (value "M01PTH_SMD_3.25X0.85MM_NO_SILK")
      (footprint "eagle-import:1X01_SMD_3.25X0.85MM_NO_SILK")
      (libsource (lib "eagle-import") (part "M01PTH_SMD_3.25X0.85MM_NO_SILK"))
    )
    (comp (ref "JP727")
      (value "M01PTH_SMD_3.25X0.85MM_NO_SILK")
      (footprint "eagle-import:1X01_SMD_3.25X0.85MM_NO_SILK")
      (libsource (lib "eagle-import") (part "M01PTH_SMD_3.25X0.85MM_NO_SILK"))
    )
    (comp (ref "JP728")
      (value "M01PTH_SMD_3.25X0.85MM_NO_SILK")
      (footprint "eagle-import:1X01_SMD_3.25X0.85MM_NO_SILK")
      (libsource (lib "eagle-import") (part "M01PTH_SMD_3.25X0.85MM_NO_SILK"))
    )
    (comp (ref "JP729")
      (value "M01PTH_SMD_3.25X0.85MM_NO_SILK")
      (footprint "eagle-import:1X01_SMD_3.25X0.85MM_NO_SILK")
      (libsource (lib "eagle-import") (part "M01PTH_SMD_3.25X0.85MM_NO_SILK"))
    )
    (comp (ref "JP730")
      (value "M01PTH_SMD_3.25X0.85MM_NO_SILK")
      (footprint "eagle-import:1X01_SMD_3.25X0.85MM_NO_SILK")
      (libsource (lib "eagle-import") (part "M01PTH_SMD_3.25X0.85MM_NO_SILK"))
    )
    (comp (ref "JP731")
      (value "M01PTH_SMD_3.25X0.85MM_NO_SILK")
      (footprint "eagle-import:1X01_SMD_3.25X0.85MM_NO_SILK")
      (libsource (lib "eagle-import") (part "M01PTH_SMD_3.25X0.85MM_NO_SILK"))
    )
    (comp (ref "JP732")
      (value "M01PTH_SMD_3.25X0.85MM_NO_SILK")
      (footprint "eagle-import:1X01_SMD_3.25X0.85MM_NO_SILK")
      (libsource (lib "eagle-import") (part "M01PTH_SMD_3.25X0.85MM_NO_SILK"))
    )
    (comp (ref "JP733")
      (value "M01PTH_SMD_3.25X0.85MM_NO_SILK")
      (footprint "eagle-import:1X01_SMD_3.25X0.85MM_NO_SILK")
      (libsource (lib "eagle-import") (part "M01PTH_SMD_3.25X0.85MM_NO_SILK"))
    )
    (comp (ref "JP734")
      (value "M01PTH_SMD_3.25X0.85MM_NO_SILK")
      (footprint "eagle-import:1X01_SMD_3.25X0.85MM_NO_SILK")
      (libsource (lib "eagle-import") (part "M01PTH_SMD_3.25X0.85MM_NO_SILK"))
    )
    (comp (ref "JP735")
      (value "M01PTH_SMD_3.25X0.85MM_NO_SILK")
      (footprint "eagle-import:1X01_SMD_3.25X0.85MM_NO_SILK")
      (libsource (lib "eagle-import") (part "M01PTH_SMD_3.25X0.85MM_NO_SILK"))
    )
    (comp (ref "JP736")
      (value "M01PTH_SMD_3.25X0.85MM_NO_SILK")
      (footprint "eagle-import:1X01_SMD_3.25X0.85MM_NO_SILK")
      (libsource (lib "eagle-import") (part "M01PTH_SMD_3.25X0.85MM_NO_SILK"))
    )
    (comp (ref "JP737")
      (value "M01PTH_SMD_3.25X0.85MM_NO_SILK")
      (footprint "eagle-import:1X01_SMD_3.25X0.85MM_NO_SILK")
      (libsource (lib "eagle-import") (part "M01PTH_SMD_3.25X0.85MM_NO_SILK"))
    )
    (comp (ref "JP738")
      (value "M01PTH_SMD_3.25X0.85MM_NO_SILK")
      (footprint "eagle-import:1X01_SMD_3.25X0.85MM_NO_SILK")
      (libsource (lib "eagle-import") (part "M01PTH_SMD_3.25X0.85MM_NO_SILK"))
    )
    (comp (ref "JP739")
      (value "M01PTH_SMD_3.25X0.85MM_NO_SILK")
      (footprint "eagle-import:1X01_SMD_3.25X0.85MM_NO_SILK")
      (libsource (lib "eagle-import") (part "M01PTH_SMD_3.25X0.85MM_NO_SILK"))
    )
    (comp (ref "JP740")
      (value "M01PTH_SMD_3.25X0.85MM_NO_SILK")
      (footprint "eagle-import:1X01_SMD_3.25X0.85MM_NO_SILK")
      (libsource (lib "eagle-import") (part "M01PTH_SMD_3.25X0.85MM_NO_SILK"))
    )
    (comp (ref "JP741")
      (value "M01PTH_SMD_3.25X0.85MM_NO_SILK")
      (footprint "eagle-import:1X01_SMD_3.25X0.85MM_NO_SILK")
      (libsource (lib "eagle-import") (part "M01PTH_SMD_3.25X0.85MM_NO_SILK"))
    )
    (comp (ref "JP742")
      (value "M01PTH_SMD_3.25X0.85MM_NO_SILK")
      (footprint "eagle-import:1X01_SMD_3.25X0.85MM_NO_SILK")
      (libsource (lib "eagle-import") (part "M01PTH_SMD_3.25X0.85MM_NO_SILK"))
    )
    (comp (ref "JP743")
      (value "M01PTH_SMD_3.25X0.85MM_NO_SILK")
      (footprint "eagle-import:1X01_SMD_3.25X0.85MM_NO_SILK")
      (libsource (lib "eagle-import") (part "M01PTH_SMD_3.25X0.85MM_NO_SILK"))
    )
    (comp (ref "JP744")
      (value "M01PTH_SMD_3.25X0.85MM_NO_SILK")
      (footprint "eagle-import:1X01_SMD_3.25X0.85MM_NO_SILK")
      (libsource (lib "eagle-import") (part "M01PTH_SMD_3.25X0.85MM_NO_SILK"))
    )
    (comp (ref "JP745")
      (value "M01PTH_SMD_3.25X0.85MM_NO_SILK")
      (footprint "eagle-import:1X01_SMD_3.25X0.85MM_NO_SILK")
      (libsource (lib "eagle-import") (part "M01PTH_SMD_3.25X0.85MM_NO_SILK"))
    )
    (comp (ref "JP746")
      (value "M01PTH_SMD_3.25X0.85MM_NO_SILK")
      (footprint "eagle-import:1X01_SMD_3.25X0.85MM_NO_SILK")
      (libsource (lib "eagle-import") (part "M01PTH_SMD_3.25X0.85MM_NO_SILK"))
    )
    (comp (ref "JP747")
      (value "M01PTH_SMD_3.25X0.85MM_NO_SILK")
      (footprint "eagle-import:1X01_SMD_3.25X0.85MM_NO_SILK")
      (libsource (lib "eagle-import") (part "M01PTH_SMD_3.25X0.85MM_NO_SILK"))
    )
    (comp (ref "JP748")
      (value "M01PTH_SMD_3.25X0.85MM_NO_SILK")
      (footprint "eagle-import:1X01_SMD_3.25X0.85MM_NO_SILK")
      (libsource (lib "eagle-import") (part "M01PTH_SMD_3.25X0.85MM_NO_SILK"))
    )
    (comp (ref "JP749")
      (value "M01PTH_SMD_3.25X0.85MM_NO_SILK")
      (footprint "eagle-import:1X01_SMD_3.25X0.85MM_NO_SILK")
      (libsource (lib "eagle-import") (part "M01PTH_SMD_3.25X0.85MM_NO_SILK"))
    )
    (comp (ref "JP750")
      (value "M01PTH_SMD_3.25X0.85MM_NO_SILK")
      (footprint "eagle-import:1X01_SMD_3.25X0.85MM_NO_SILK")
      (libsource (lib "eagle-import") (part "M01PTH_SMD_3.25X0.85MM_NO_SILK"))
    )
    (comp (ref "JP751")
      (value "M01PTH_SMD_3.25X0.85MM_NO_SILK")
      (footprint "eagle-import:1X01_SMD_3.25X0.85MM_NO_SILK")
      (libsource (lib "eagle-import") (part "M01PTH_SMD_3.25X0.85MM_NO_SILK"))
    )
    (comp (ref "JP752")
      (value "M01PTH_SMD_3.25X0.85MM_NO_SILK")
      (footprint "eagle-import:1X01_SMD_3.25X0.85MM_NO_SILK")
      (libsource (lib "eagle-import") (part "M01PTH_SMD_3.25X0.85MM_NO_SILK"))
    )
    (comp (ref "JP753")
      (value "M01PTH_SMD_3.25X0.85MM_NO_SILK")
      (footprint "eagle-import:1X01_SMD_3.25X0.85MM_NO_SILK")
      (libsource (lib "eagle-import") (part "M01PTH_SMD_3.25X0.85MM_NO_SILK"))
    )
    (comp (ref "JP754")
      (value "M01PTH_SMD_3.25X0.85MM_NO_SILK")
      (footprint "eagle-import:1X01_SMD_3.25X0.85MM_NO_SILK")
      (libsource (lib "eagle-import") (part "M01PTH_SMD_3.25X0.85MM_NO_SILK"))
    )
    (comp (ref "JP755")
      (value "M01PTH_SMD_3.25X0.85MM_NO_SILK")
      (footprint "eagle-import:1X01_SMD_3.25X0.85MM_NO_SILK")
      (libsource (lib "eagle-import") (part "M01PTH_SMD_3.25X0.85MM_NO_SILK"))
    )
    (comp (ref "JP756")
      (value "M01PTH_SMD_3.25X0.85MM_NO_SILK")
      (footprint "eagle-import:1X01_SMD_3.25X0.85MM_NO_SILK")
      (libsource (lib "eagle-import") (part "M01PTH_SMD_3.25X0.85MM_NO_SILK"))
    )
    (comp (ref "JP757")
      (value "M01PTH_SMD_3.25X0.85MM_NO_SILK")
      (footprint "eagle-import:1X01_SMD_3.25X0.85MM_NO_SILK")
      (libsource (lib "eagle-import") (part "M01PTH_SMD_3.25X0.85MM_NO_SILK"))
    )
    (comp (ref "JP758")
      (value "M01PTH_SMD_3.25X0.85MM_NO_SILK")
      (footprint "eagle-import:1X01_SMD_3.25X0.85MM_NO_SILK")
      (libsource (lib "eagle-import") (part "M01PTH_SMD_3.25X0.85MM_NO_SILK"))
    )
    (comp (ref "JP759")
      (value "M01PTH_SMD_3.25X0.85MM_NO_SILK")
      (footprint "eagle-import:1X01_SMD_3.25X0.85MM_NO_SILK")
      (libsource (lib "eagle-import") (part "M01PTH_SMD_3.25X0.85MM_NO_SILK"))
    )
    (comp (ref "JP760")
      (value "M01PTH_SMD_3.25X0.85MM_NO_SILK")
      (footprint "eagle-import:1X01_SMD_3.25X0.85MM_NO_SILK")
      (libsource (lib "eagle-import") (part "M01PTH_SMD_3.25X0.85MM_NO_SILK"))
    )
    (comp (ref "JP761")
      (value "M01PTH_SMD_3.25X0.85MM_NO_SILK")
      (footprint "eagle-import:1X01_SMD_3.25X0.85MM_NO_SILK")
      (libsource (lib "eagle-import") (part "M01PTH_SMD_3.25X0.85MM_NO_SILK"))
    )
    (comp (ref "JP762")
      (value "M01PTH_SMD_3.25X0.85MM_NO_SILK")
      (footprint "eagle-import:1X01_SMD_3.25X0.85MM_NO_SILK")
      (libsource (lib "eagle-import") (part "M01PTH_SMD_3.25X0.85MM_NO_SILK"))
    )
    (comp (ref "JP763")
      (value "M01PTH_SMD_3.25X0.85MM_NO_SILK")
      (footprint "eagle-import:1X01_SMD_3.25X0.85MM_NO_SILK")
      (libsource (lib "eagle-import") (part "M01PTH_SMD_3.25X0.85MM_NO_SILK"))
    )
    (comp (ref "JP764")
      (value "M01PTH_SMD_3.25X0.85MM_NO_SILK")
      (footprint "eagle-import:1X01_SMD_3.25X0.85MM_NO_SILK")
      (libsource (lib "eagle-import") (part "M01PTH_SMD_3.25X0.85MM_NO_SILK"))
    )
    (comp (ref "JP765")
      (value "M01PTH_SMD_3.25X0.85MM_NO_SILK")
      (footprint "eagle-import:1X01_SMD_3.25X0.85MM_NO_SILK")
      (libsource (lib "eagle-import") (part "M01PTH_SMD_3.25X0.85MM_NO_SILK"))
    )
    (comp (ref "JP766")
      (value "M01PTH_SMD_3.25X0.85MM_NO_SILK")
      (footprint "eagle-import:1X01_SMD_3.25X0.85MM_NO_SILK")
      (libsource (lib "eagle-import") (part "M01PTH_SMD_3.25X0.85MM_NO_SILK"))
    )
    (comp (ref "JP767")
      (value "M01PTH_SMD_3.25X0.85MM_NO_SILK")
      (footprint "eagle-import:1X01_SMD_3.25X0.85MM_NO_SILK")
      (libsource (lib "eagle-import") (part "M01PTH_SMD_3.25X0.85MM_NO_SILK"))
    )
    (comp (ref "JP768")
      (value "M01PTH_SMD_3.25X0.85MM_NO_SILK")
      (footprint "eagle-import:1X01_SMD_3.25X0.85MM_NO_SILK")
      (libsource (lib "eagle-import") (part "M01PTH_SMD_3.25X0.85MM_NO_SILK"))
    )
    (comp (ref "JP769")
      (value "M01PTH_SMD_3.25X0.85MM_NO_SILK")
      (footprint "eagle-import:1X01_SMD_3.25X0.85MM_NO_SILK")
      (libsource (lib "eagle-import") (part "M01PTH_SMD_3.25X0.85MM_NO_SILK"))
    )
    (comp (ref "JP770")
      (value "M01PTH_SMD_3.25X0.85MM_NO_SILK")
      (footprint "eagle-import:1X01_SMD_3.25X0.85MM_NO_SILK")
      (libsource (lib "eagle-import") (part "M01PTH_SMD_3.25X0.85MM_NO_SILK"))
    )
    (comp (ref "JP771")
      (value "M01PTH_SMD_3.25X0.85MM_NO_SILK")
      (footprint "eagle-import:1X01_SMD_3.25X0.85MM_NO_SILK")
      (libsource (lib "eagle-import") (part "M01PTH_SMD_3.25X0.85MM_NO_SILK"))
    )
    (comp (ref "JP772")
      (value "M01PTH_SMD_3.25X0.85MM_NO_SILK")
      (footprint "eagle-import:1X01_SMD_3.25X0.85MM_NO_SILK")
      (libsource (lib "eagle-import") (part "M01PTH_SMD_3.25X0.85MM_NO_SILK"))
    )
    (comp (ref "JP773")
      (value "M01PTH_SMD_3.25X0.85MM_NO_SILK")
      (footprint "eagle-import:1X01_SMD_3.25X0.85MM_NO_SILK")
      (libsource (lib "eagle-import") (part "M01PTH_SMD_3.25X0.85MM_NO_SILK"))
    )
    (comp (ref "JP774")
      (value "M01PTH_SMD_3.25X0.85MM_NO_SILK")
      (footprint "eagle-import:1X01_SMD_3.25X0.85MM_NO_SILK")
      (libsource (lib "eagle-import") (part "M01PTH_SMD_3.25X0.85MM_NO_SILK"))
    )
    (comp (ref "JP775")
      (value "M01PTH_SMD_3.25X0.85MM_NO_SILK")
      (footprint "eagle-import:1X01_SMD_3.25X0.85MM_NO_SILK")
      (libsource (lib "eagle-import") (part "M01PTH_SMD_3.25X0.85MM_NO_SILK"))
    )
    (comp (ref "JP776")
      (value "M01PTH_SMD_3.25X0.85MM_NO_SILK")
      (footprint "eagle-import:1X01_SMD_3.25X0.85MM_NO_SILK")
      (libsource (lib "eagle-import") (part "M01PTH_SMD_3.25X0.85MM_NO_SILK"))
    )
    (comp (ref "JP777")
      (value "M01PTH_SMD_3.25X0.85MM_NO_SILK")
      (footprint "eagle-import:1X01_SMD_3.25X0.85MM_NO_SILK")
      (libsource (lib "eagle-import") (part "M01PTH_SMD_3.25X0.85MM_NO_SILK"))
    )
    (comp (ref "JP778")
      (value "M01PTH_SMD_3.25X0.85MM_NO_SILK")
      (footprint "eagle-import:1X01_SMD_3.25X0.85MM_NO_SILK")
      (libsource (lib "eagle-import") (part "M01PTH_SMD_3.25X0.85MM_NO_SILK"))
    )
    (comp (ref "JP779")
      (value "M01PTH_SMD_3.25X0.85MM_NO_SILK")
      (footprint "eagle-import:1X01_SMD_3.25X0.85MM_NO_SILK")
      (libsource (lib "eagle-import") (part "M01PTH_SMD_3.25X0.85MM_NO_SILK"))
    )
    (comp (ref "JP780")
      (value "M01PTH_SMD_3.25X0.85MM_NO_SILK")
      (footprint "eagle-import:1X01_SMD_3.25X0.85MM_NO_SILK")
      (libsource (lib "eagle-import") (part "M01PTH_SMD_3.25X0.85MM_NO_SILK"))
    )
    (comp (ref "JP781")
      (value "M01PTH_SMD_3.25X0.85MM_NO_SILK")
      (footprint "eagle-import:1X01_SMD_3.25X0.85MM_NO_SILK")
      (libsource (lib "eagle-import") (part "M01PTH_SMD_3.25X0.85MM_NO_SILK"))
    )
    (comp (ref "JP782")
      (value "M01PTH_SMD_3.25X0.85MM_NO_SILK")
      (footprint "eagle-import:1X01_SMD_3.25X0.85MM_NO_SILK")
      (libsource (lib "eagle-import") (part "M01PTH_SMD_3.25X0.85MM_NO_SILK"))
    )
    (comp (ref "JP783")
      (value "M01PTH_SMD_3.25X0.85MM_NO_SILK")
      (footprint "eagle-import:1X01_SMD_3.25X0.85MM_NO_SILK")
      (libsource (lib "eagle-import") (part "M01PTH_SMD_3.25X0.85MM_NO_SILK"))
    )
    (comp (ref "JP784")
      (value "M01PTH_SMD_3.25X0.85MM_NO_SILK")
      (footprint "eagle-import:1X01_SMD_3.25X0.85MM_NO_SILK")
      (libsource (lib "eagle-import") (part "M01PTH_SMD_3.25X0.85MM_NO_SILK"))
    )
    (comp (ref "JP785")
      (value "M01PTH_SMD_3.25X0.85MM_NO_SILK")
      (footprint "eagle-import:1X01_SMD_3.25X0.85MM_NO_SILK")
      (libsource (lib "eagle-import") (part "M01PTH_SMD_3.25X0.85MM_NO_SILK"))
    )
    (comp (ref "JP786")
      (value "M01PTH_SMD_3.25X0.85MM_NO_SILK")
      (footprint "eagle-import:1X01_SMD_3.25X0.85MM_NO_SILK")
      (libsource (lib "eagle-import") (part "M01PTH_SMD_3.25X0.85MM_NO_SILK"))
    )
    (comp (ref "JP787")
      (value "M01PTH_SMD_3.25X0.85MM_NO_SILK")
      (footprint "eagle-import:1X01_SMD_3.25X0.85MM_NO_SILK")
      (libsource (lib "eagle-import") (part "M01PTH_SMD_3.25X0.85MM_NO_SILK"))
    )
    (comp (ref "JP788")
      (value "M01PTH_SMD_3.25X0.85MM_NO_SILK")
      (footprint "eagle-import:1X01_SMD_3.25X0.85MM_NO_SILK")
      (libsource (lib "eagle-import") (part "M01PTH_SMD_3.25X0.85MM_NO_SILK"))
    )
    (comp (ref "JP789")
      (value "M01PTH_SMD_3.25X0.85MM_NO_SILK")
      (footprint "eagle-import:1X01_SMD_3.25X0.85MM_NO_SILK")
      (libsource (lib "eagle-import") (part "M01PTH_SMD_3.25X0.85MM_NO_SILK"))
    )
    (comp (ref "JP790")
      (value "M01PTH_SMD_3.25X0.85MM_NO_SILK")
      (footprint "eagle-import:1X01_SMD_3.25X0.85MM_NO_SILK")
      (libsource (lib "eagle-import") (part "M01PTH_SMD_3.25X0.85MM_NO_SILK"))
    )
    (comp (ref "JP791")
      (value "M01PTH_SMD_3.25X0.85MM_NO_SILK")
      (footprint "eagle-import:1X01_SMD_3.25X0.85MM_NO_SILK")
      (libsource (lib "eagle-import") (part "M01PTH_SMD_3.25X0.85MM_NO_SILK"))
    )
    (comp (ref "JP792")
      (value "M01PTH_SMD_3.25X0.85MM_NO_SILK")
      (footprint "eagle-import:1X01_SMD_3.25X0.85MM_NO_SILK")
      (libsource (lib "eagle-import") (part "M01PTH_SMD_3.25X0.85MM_NO_SILK"))
    )
    (comp (ref "JP793")
      (value "M01PTH_SMD_3.25X0.85MM_NO_SILK")
      (footprint "eagle-import:1X01_SMD_3.25X0.85MM_NO_SILK")
      (libsource (lib "eagle-import") (part "M01PTH_SMD_3.25X0.85MM_NO_SILK"))
    )
    (comp (ref "JP794")
      (value "M01PTH_SMD_3.25X0.85MM_NO_SILK")
      (footprint "eagle-import:1X01_SMD_3.25X0.85MM_NO_SILK")
      (libsource (lib "eagle-import") (part "M01PTH_SMD_3.25X0.85MM_NO_SILK"))
    )
    (comp (ref "JP795")
      (value "M01PTH_SMD_3.25X0.85MM_NO_SILK")
      (footprint "eagle-import:1X01_SMD_3.25X0.85MM_NO_SILK")
      (libsource (lib "eagle-import") (part "M01PTH_SMD_3.25X0.85MM_NO_SILK"))
    )
    (comp (ref "JP796")
      (value "M01PTH_SMD_3.25X0.85MM_NO_SILK")
      (footprint "eagle-import:1X01_SMD_3.25X0.85MM_NO_SILK")
      (libsource (lib "eagle-import") (part "M01PTH_SMD_3.25X0.85MM_NO_SILK"))
    )
    (comp (ref "JP797")
      (value "M01PTH_SMD_3.25X0.85MM_NO_SILK")
      (footprint "eagle-import:1X01_SMD_3.25X0.85MM_NO_SILK")
      (libsource (lib "eagle-import") (part "M01PTH_SMD_3.25X0.85MM_NO_SILK"))
    )
    (comp (ref "JP798")
      (value "M01PTH_SMD_3.25X0.85MM_NO_SILK")
      (footprint "eagle-import:1X01_SMD_3.25X0.85MM_NO_SILK")
      (libsource (lib "eagle-import") (part "M01PTH_SMD_3.25X0.85MM_NO_SILK"))
    )
    (comp (ref "JP799")
      (value "M01PTH_SMD_3.25X0.85MM_NO_SILK")
      (footprint "eagle-import:1X01_SMD_3.25X0.85MM_NO_SILK")
      (libsource (lib "eagle-import") (part "M01PTH_SMD_3.25X0.85MM_NO_SILK"))
    )
    (comp (ref "JP800")
      (value "M01PTH_SMD_3.25X0.85MM_NO_SILK")
      (footprint "eagle-import:1X01_SMD_3.25X0.85MM_NO_SILK")
      (libsource (lib "eagle-import") (part "M01PTH_SMD_3.25X0.85MM_NO_SILK"))
    )
    (comp (ref "JP801")
      (value "M01PTH_SMD_3.25X0.85MM_NO_SILK")
      (footprint "eagle-import:1X01_SMD_3.25X0.85MM_NO_SILK")
      (libsource (lib "eagle-import") (part "M01PTH_SMD_3.25X0.85MM_NO_SILK"))
    )
    (comp (ref "JP802")
      (value "M01PTH_SMD_3.25X0.85MM_NO_SILK")
      (footprint "eagle-import:1X01_SMD_3.25X0.85MM_NO_SILK")
      (libsource (lib "eagle-import") (part "M01PTH_SMD_3.25X0.85MM_NO_SILK"))
    )
    (comp (ref "JP803")
      (value "M01PTH_SMD_3.25X0.85MM_NO_SILK")
      (footprint "eagle-import:1X01_SMD_3.25X0.85MM_NO_SILK")
      (libsource (lib "eagle-import") (part "M01PTH_SMD_3.25X0.85MM_NO_SILK"))
    )
    (comp (ref "JP804")
      (value "M01PTH_SMD_3.25X0.85MM_NO_SILK")
      (footprint "eagle-import:1X01_SMD_3.25X0.85MM_NO_SILK")
      (libsource (lib "eagle-import") (part "M01PTH_SMD_3.25X0.85MM_NO_SILK"))
    )
    (comp (ref "JP805")
      (value "M01PTH_SMD_3.25X0.85MM_NO_SILK")
      (footprint "eagle-import:1X01_SMD_3.25X0.85MM_NO_SILK")
      (libsource (lib "eagle-import") (part "M01PTH_SMD_3.25X0.85MM_NO_SILK"))
    )
    (comp (ref "JP806")
      (value "M01PTH_SMD_3.25X0.85MM_NO_SILK")
      (footprint "eagle-import:1X01_SMD_3.25X0.85MM_NO_SILK")
      (libsource (lib "eagle-import") (part "M01PTH_SMD_3.25X0.85MM_NO_SILK"))
    )
    (comp (ref "JP807")
      (value "M01PTH_SMD_3.25X0.85MM_NO_SILK")
      (footprint "eagle-import:1X01_SMD_3.25X0.85MM_NO_SILK")
      (libsource (lib "eagle-import") (part "M01PTH_SMD_3.25X0.85MM_NO_SILK"))
    )
    (comp (ref "JP808")
      (value "M01PTH_SMD_3.25X0.85MM_NO_SILK")
      (footprint "eagle-import:1X01_SMD_3.25X0.85MM_NO_SILK")
      (libsource (lib "eagle-import") (part "M01PTH_SMD_3.25X0.85MM_NO_SILK"))
    )
    (comp (ref "JP809")
      (value "M01PTH_SMD_3.25X0.85MM_NO_SILK")
      (footprint "eagle-import:1X01_SMD_3.25X0.85MM_NO_SILK")
      (libsource (lib "eagle-import") (part "M01PTH_SMD_3.25X0.85MM_NO_SILK"))
    )
    (comp (ref "JP810")
      (value "M01PTH_SMD_3.25X0.85MM_NO_SILK")
      (footprint "eagle-import:1X01_SMD_3.25X0.85MM_NO_SILK")
      (libsource (lib "eagle-import") (part "M01PTH_SMD_3.25X0.85MM_NO_SILK"))
    )
    (comp (ref "JP811")
      (value "M01PTH_SMD_3.25X0.85MM_NO_SILK")
      (footprint "eagle-import:1X01_SMD_3.25X0.85MM_NO_SILK")
      (libsource (lib "eagle-import") (part "M01PTH_SMD_3.25X0.85MM_NO_SILK"))
    )
    (comp (ref "JP812")
      (value "M01PTH_SMD_3.25X0.85MM_NO_SILK")
      (footprint "eagle-import:1X01_SMD_3.25X0.85MM_NO_SILK")
      (libsource (lib "eagle-import") (part "M01PTH_SMD_3.25X0.85MM_NO_SILK"))
    )
    (comp (ref "JP813")
      (value "M01PTH_SMD_3.25X0.85MM_NO_SILK")
      (footprint "eagle-import:1X01_SMD_3.25X0.85MM_NO_SILK")
      (libsource (lib "eagle-import") (part "M01PTH_SMD_3.25X0.85MM_NO_SILK"))
    )
    (comp (ref "JP814")
      (value "M01PTH_SMD_3.25X0.85MM_NO_SILK")
      (footprint "eagle-import:1X01_SMD_3.25X0.85MM_NO_SILK")
      (libsource (lib "eagle-import") (part "M01PTH_SMD_3.25X0.85MM_NO_SILK"))
    )
    (comp (ref "JP815")
      (value "M01PTH_SMD_3.25X0.85MM_NO_SILK")
      (footprint "eagle-import:1X01_SMD_3.25X0.85MM_NO_SILK")
      (libsource (lib "eagle-import") (part "M01PTH_SMD_3.25X0.85MM_NO_SILK"))
    )
    (comp (ref "JP816")
      (value "M01PTH_SMD_3.25X0.85MM_NO_SILK")
      (footprint "eagle-import:1X01_SMD_3.25X0.85MM_NO_SILK")
      (libsource (lib "eagle-import") (part "M01PTH_SMD_3.25X0.85MM_NO_SILK"))
    )
    (comp (ref "JP817")
      (value "M01PTH_SMD_3.25X0.85MM_NO_SILK")
      (footprint "eagle-import:1X01_SMD_3.25X0.85MM_NO_SILK")
      (libsource (lib "eagle-import") (part "M01PTH_SMD_3.25X0.85MM_NO_SILK"))
    )
    (comp (ref "JP818")
      (value "M01PTH_SMD_3.25X0.85MM_NO_SILK")
      (footprint "eagle-import:1X01_SMD_3.25X0.85MM_NO_SILK")
      (libsource (lib "eagle-import") (part "M01PTH_SMD_3.25X0.85MM_NO_SILK"))
    )
    (comp (ref "JP819")
      (value "M01PTH_SMD_3.25X0.85MM_NO_SILK")
      (footprint "eagle-import:1X01_SMD_3.25X0.85MM_NO_SILK")
      (libsource (lib "eagle-import") (part "M01PTH_SMD_3.25X0.85MM_NO_SILK"))
    )
    (comp (ref "JP820")
      (value "M01PTH_SMD_3.25X0.85MM_NO_SILK")
      (footprint "eagle-import:1X01_SMD_3.25X0.85MM_NO_SILK")
      (libsource (lib "eagle-import") (part "M01PTH_SMD_3.25X0.85MM_NO_SILK"))
    )
    (comp (ref "JP821")
      (value "M01PTH_SMD_3.25X0.85MM_NO_SILK")
      (footprint "eagle-import:1X01_SMD_3.25X0.85MM_NO_SILK")
      (libsource (lib "eagle-import") (part "M01PTH_SMD_3.25X0.85MM_NO_SILK"))
    )
    (comp (ref "JP822")
      (value "M01PTH_SMD_3.25X0.85MM_NO_SILK")
      (footprint "eagle-import:1X01_SMD_3.25X0.85MM_NO_SILK")
      (libsource (lib "eagle-import") (part "M01PTH_SMD_3.25X0.85MM_NO_SILK"))
    )
    (comp (ref "JP823")
      (value "M01PTH_SMD_3.25X0.85MM_NO_SILK")
      (footprint "eagle-import:1X01_SMD_3.25X0.85MM_NO_SILK")
      (libsource (lib "eagle-import") (part "M01PTH_SMD_3.25X0.85MM_NO_SILK"))
    )
    (comp (ref "JP824")
      (value "M01PTH_SMD_3.25X0.85MM_NO_SILK")
      (footprint "eagle-import:1X01_SMD_3.25X0.85MM_NO_SILK")
      (libsource (lib "eagle-import") (part "M01PTH_SMD_3.25X0.85MM_NO_SILK"))
    )
    (comp (ref "JP825")
      (value "M01PTH_SMD_3.25X0.85MM_NO_SILK")
      (footprint "eagle-import:1X01_SMD_3.25X0.85MM_NO_SILK")
      (libsource (lib "eagle-import") (part "M01PTH_SMD_3.25X0.85MM_NO_SILK"))
    )
    (comp (ref "JP826")
      (value "M01PTH_SMD_3.25X0.85MM_NO_SILK")
      (footprint "eagle-import:1X01_SMD_3.25X0.85MM_NO_SILK")
      (libsource (lib "eagle-import") (part "M01PTH_SMD_3.25X0.85MM_NO_SILK"))
    )
    (comp (ref "JP827")
      (value "M01PTH_SMD_3.25X0.85MM_NO_SILK")
      (footprint "eagle-import:1X01_SMD_3.25X0.85MM_NO_SILK")
      (libsource (lib "eagle-import") (part "M01PTH_SMD_3.25X0.85MM_NO_SILK"))
    )
    (comp (ref "JP828")
      (value "M01PTH_SMD_3.25X0.85MM_NO_SILK")
      (footprint "eagle-import:1X01_SMD_3.25X0.85MM_NO_SILK")
      (libsource (lib "eagle-import") (part "M01PTH_SMD_3.25X0.85MM_NO_SILK"))
    )
    (comp (ref "JP829")
      (value "M01PTH_SMD_3.25X0.85MM_NO_SILK")
      (footprint "eagle-import:1X01_SMD_3.25X0.85MM_NO_SILK")
      (libsource (lib "eagle-import") (part "M01PTH_SMD_3.25X0.85MM_NO_SILK"))
    )
    (comp (ref "JP830")
      (value "M01PTH_SMD_3.25X0.85MM_NO_SILK")
      (footprint "eagle-import:1X01_SMD_3.25X0.85MM_NO_SILK")
      (libsource (lib "eagle-import") (part "M01PTH_SMD_3.25X0.85MM_NO_SILK"))
    )
    (comp (ref "JP831")
      (value "M01PTH_SMD_3.25X0.85MM_NO_SILK")
      (footprint "eagle-import:1X01_SMD_3.25X0.85MM_NO_SILK")
      (libsource (lib "eagle-import") (part "M01PTH_SMD_3.25X0.85MM_NO_SILK"))
    )
    (comp (ref "JP832")
      (value "M01PTH_SMD_3.25X0.85MM_NO_SILK")
      (footprint "eagle-import:1X01_SMD_3.25X0.85MM_NO_SILK")
      (libsource (lib "eagle-import") (part "M01PTH_SMD_3.25X0.85MM_NO_SILK"))
    )
    (comp (ref "JP833")
      (value "M01PTH_SMD_3.25X0.85MM_NO_SILK")
      (footprint "eagle-import:1X01_SMD_3.25X0.85MM_NO_SILK")
      (libsource (lib "eagle-import") (part "M01PTH_SMD_3.25X0.85MM_NO_SILK"))
    )
    (comp (ref "JP834")
      (value "M01PTH_SMD_3.25X0.85MM_NO_SILK")
      (footprint "eagle-import:1X01_SMD_3.25X0.85MM_NO_SILK")
      (libsource (lib "eagle-import") (part "M01PTH_SMD_3.25X0.85MM_NO_SILK"))
    )
    (comp (ref "JP835")
      (value "M01PTH_SMD_3.25X0.85MM_NO_SILK")
      (footprint "eagle-import:1X01_SMD_3.25X0.85MM_NO_SILK")
      (libsource (lib "eagle-import") (part "M01PTH_SMD_3.25X0.85MM_NO_SILK"))
    )
    (comp (ref "JP836")
      (value "M01PTH_SMD_3.25X0.85MM_NO_SILK")
      (footprint "eagle-import:1X01_SMD_3.25X0.85MM_NO_SILK")
      (libsource (lib "eagle-import") (part "M01PTH_SMD_3.25X0.85MM_NO_SILK"))
    )
    (comp (ref "JP837")
      (value "M01PTH_SMD_3.25X0.85MM_NO_SILK")
      (footprint "eagle-import:1X01_SMD_3.25X0.85MM_NO_SILK")
      (libsource (lib "eagle-import") (part "M01PTH_SMD_3.25X0.85MM_NO_SILK"))
    )
    (comp (ref "JP838")
      (value "M01PTH_SMD_3.25X0.85MM_NO_SILK")
      (footprint "eagle-import:1X01_SMD_3.25X0.85MM_NO_SILK")
      (libsource (lib "eagle-import") (part "M01PTH_SMD_3.25X0.85MM_NO_SILK"))
    )
    (comp (ref "JP839")
      (value "M01PTH_SMD_3.25X0.85MM_NO_SILK")
      (footprint "eagle-import:1X01_SMD_3.25X0.85MM_NO_SILK")
      (libsource (lib "eagle-import") (part "M01PTH_SMD_3.25X0.85MM_NO_SILK"))
    )
    (comp (ref "JP840")
      (value "M01PTH_SMD_3.25X0.85MM_NO_SILK")
      (footprint "eagle-import:1X01_SMD_3.25X0.85MM_NO_SILK")
      (libsource (lib "eagle-import") (part "M01PTH_SMD_3.25X0.85MM_NO_SILK"))
    )
    (comp (ref "JP841")
      (value "M01PTH_SMD_3.25X0.85MM_NO_SILK")
      (footprint "eagle-import:1X01_SMD_3.25X0.85MM_NO_SILK")
      (libsource (lib "eagle-import") (part "M01PTH_SMD_3.25X0.85MM_NO_SILK"))
    )
    (comp (ref "JP842")
      (value "M01PTH_SMD_3.25X0.85MM_NO_SILK")
      (footprint "eagle-import:1X01_SMD_3.25X0.85MM_NO_SILK")
      (libsource (lib "eagle-import") (part "M01PTH_SMD_3.25X0.85MM_NO_SILK"))
    )
    (comp (ref "JP843")
      (value "M01PTH_SMD_3.25X0.85MM_NO_SILK")
      (footprint "eagle-import:1X01_SMD_3.25X0.85MM_NO_SILK")
      (libsource (lib "eagle-import") (part "M01PTH_SMD_3.25X0.85MM_NO_SILK"))
    )
    (comp (ref "JP844")
      (value "M01PTH_SMD_3.25X0.85MM_NO_SILK")
      (footprint "eagle-import:1X01_SMD_3.25X0.85MM_NO_SILK")
      (libsource (lib "eagle-import") (part "M01PTH_SMD_3.25X0.85MM_NO_SILK"))
    )
    (comp (ref "JP845")
      (value "M01PTH_SMD_3.25X0.85MM_NO_SILK")
      (footprint "eagle-import:1X01_SMD_3.25X0.85MM_NO_SILK")
      (libsource (lib "eagle-import") (part "M01PTH_SMD_3.25X0.85MM_NO_SILK"))
    )
    (comp (ref "JP846")
      (value "M01PTH_SMD_3.25X0.85MM_NO_SILK")
      (footprint "eagle-import:1X01_SMD_3.25X0.85MM_NO_SILK")
      (libsource (lib "eagle-import") (part "M01PTH_SMD_3.25X0.85MM_NO_SILK"))
    )
    (comp (ref "JP847")
      (value "M01PTH_SMD_3.25X0.85MM_NO_SILK")
      (footprint "eagle-import:1X01_SMD_3.25X0.85MM_NO_SILK")
      (libsource (lib "eagle-import") (part "M01PTH_SMD_3.25X0.85MM_NO_SILK"))
    )
    (comp (ref "JP848")
      (value "M01PTH_SMD_3.25X0.85MM_NO_SILK")
      (footprint "eagle-import:1X01_SMD_3.25X0.85MM_NO_SILK")
      (libsource (lib "eagle-import") (part "M01PTH_SMD_3.25X0.85MM_NO_SILK"))
    )
    (comp (ref "JP849")
      (value "M01PTH_SMD_3.25X0.85MM_NO_SILK")
      (footprint "eagle-import:1X01_SMD_3.25X0.85MM_NO_SILK")
      (libsource (lib "eagle-import") (part "M01PTH_SMD_3.25X0.85MM_NO_SILK"))
    )
    (comp (ref "JP850")
      (value "M01PTH_SMD_3.25X0.85MM_NO_SILK")
      (footprint "eagle-import:1X01_SMD_3.25X0.85MM_NO_SILK")
      (libsource (lib "eagle-import") (part "M01PTH_SMD_3.25X0.85MM_NO_SILK"))
    )
    (comp (ref "JP851")
      (value "M01PTH_SMD_3.25X0.85MM_NO_SILK")
      (footprint "eagle-import:1X01_SMD_3.25X0.85MM_NO_SILK")
      (libsource (lib "eagle-import") (part "M01PTH_SMD_3.25X0.85MM_NO_SILK"))
    )
    (comp (ref "JP852")
      (value "M01PTH_SMD_3.25X0.85MM_NO_SILK")
      (footprint "eagle-import:1X01_SMD_3.25X0.85MM_NO_SILK")
      (libsource (lib "eagle-import") (part "M01PTH_SMD_3.25X0.85MM_NO_SILK"))
    )
    (comp (ref "JP853")
      (value "M01PTH_SMD_3.25X0.85MM_NO_SILK")
      (footprint "eagle-import:1X01_SMD_3.25X0.85MM_NO_SILK")
      (libsource (lib "eagle-import") (part "M01PTH_SMD_3.25X0.85MM_NO_SILK"))
    )
    (comp (ref "JP854")
      (value "M01PTH_SMD_3.25X0.85MM_NO_SILK")
      (footprint "eagle-import:1X01_SMD_3.25X0.85MM_NO_SILK")
      (libsource (lib "eagle-import") (part "M01PTH_SMD_3.25X0.85MM_NO_SILK"))
    )
    (comp (ref "JP855")
      (value "M01PTH_SMD_3.25X0.85MM_NO_SILK")
      (footprint "eagle-import:1X01_SMD_3.25X0.85MM_NO_SILK")
      (libsource (lib "eagle-import") (part "M01PTH_SMD_3.25X0.85MM_NO_SILK"))
    )
    (comp (ref "JP856")
      (value "M01PTH_SMD_3.25X0.85MM_NO_SILK")
      (footprint "eagle-import:1X01_SMD_3.25X0.85MM_NO_SILK")
      (libsource (lib "eagle-import") (part "M01PTH_SMD_3.25X0.85MM_NO_SILK"))
    )
    (comp (ref "JP857")
      (value "M01PTH_SMD_3.25X0.85MM_NO_SILK")
      (footprint "eagle-import:1X01_SMD_3.25X0.85MM_NO_SILK")
      (libsource (lib "eagle-import") (part "M01PTH_SMD_3.25X0.85MM_NO_SILK"))
    )
    (comp (ref "JP858")
      (value "M01PTH_SMD_3.25X0.85MM_NO_SILK")
      (footprint "eagle-import:1X01_SMD_3.25X0.85MM_NO_SILK")
      (libsource (lib "eagle-import") (part "M01PTH_SMD_3.25X0.85MM_NO_SILK"))
    )
    (comp (ref "JP859")
      (value "M01PTH_SMD_3.25X0.85MM_NO_SILK")
      (footprint "eagle-import:1X01_SMD_3.25X0.85MM_NO_SILK")
      (libsource (lib "eagle-import") (part "M01PTH_SMD_3.25X0.85MM_NO_SILK"))
    )
    (comp (ref "JP860")
      (value "M01PTH_SMD_3.25X0.85MM_NO_SILK")
      (footprint "eagle-import:1X01_SMD_3.25X0.85MM_NO_SILK")
      (libsource (lib "eagle-import") (part "M01PTH_SMD_3.25X0.85MM_NO_SILK"))
    )
    (comp (ref "JP861")
      (value "M01PTH_SMD_3.25X0.85MM_NO_SILK")
      (footprint "eagle-import:1X01_SMD_3.25X0.85MM_NO_SILK")
      (libsource (lib "eagle-import") (part "M01PTH_SMD_3.25X0.85MM_NO_SILK"))
    )
    (comp (ref "JP862")
      (value "M01PTH_SMD_3.25X0.85MM_NO_SILK")
      (footprint "eagle-import:1X01_SMD_3.25X0.85MM_NO_SILK")
      (libsource (lib "eagle-import") (part "M01PTH_SMD_3.25X0.85MM_NO_SILK"))
    )
    (comp (ref "JP863")
      (value "M01PTH_SMD_3.25X0.85MM_NO_SILK")
      (footprint "eagle-import:1X01_SMD_3.25X0.85MM_NO_SILK")
      (libsource (lib "eagle-import") (part "M01PTH_SMD_3.25X0.85MM_NO_SILK"))
    )
    (comp (ref "JP864")
      (value "M01PTH_SMD_3.25X0.85MM_NO_SILK")
      (footprint "eagle-import:1X01_SMD_3.25X0.85MM_NO_SILK")
      (libsource (lib "eagle-import") (part "M01PTH_SMD_3.25X0.85MM_NO_SILK"))
    )
    (comp (ref "JP865")
      (value "M01PTH_SMD_3.25X0.85MM_NO_SILK")
      (footprint "eagle-import:1X01_SMD_3.25X0.85MM_NO_SILK")
      (libsource (lib "eagle-import") (part "M01PTH_SMD_3.25X0.85MM_NO_SILK"))
    )
    (comp (ref "JP866")
      (value "M01PTH_SMD_3.25X0.85MM_NO_SILK")
      (footprint "eagle-import:1X01_SMD_3.25X0.85MM_NO_SILK")
      (libsource (lib "eagle-import") (part "M01PTH_SMD_3.25X0.85MM_NO_SILK"))
    )
    (comp (ref "JP867")
      (value "M01PTH_SMD_3.25X0.85MM_NO_SILK")
      (footprint "eagle-import:1X01_SMD_3.25X0.85MM_NO_SILK")
      (libsource (lib "eagle-import") (part "M01PTH_SMD_3.25X0.85MM_NO_SILK"))
    )
    (comp (ref "JP868")
      (value "M01PTH_SMD_3.25X0.85MM_NO_SILK")
      (footprint "eagle-import:1X01_SMD_3.25X0.85MM_NO_SILK")
      (libsource (lib "eagle-import") (part "M01PTH_SMD_3.25X0.85MM_NO_SILK"))
    )
    (comp (ref "JP869")
      (value "M01PTH_SMD_3.25X0.85MM_NO_SILK")
      (footprint "eagle-import:1X01_SMD_3.25X0.85MM_NO_SILK")
      (libsource (lib "eagle-import") (part "M01PTH_SMD_3.25X0.85MM_NO_SILK"))
    )
    (comp (ref "JP870")
      (value "M01PTH_SMD_3.25X0.85MM_NO_SILK")
      (footprint "eagle-import:1X01_SMD_3.25X0.85MM_NO_SILK")
      (libsource (lib "eagle-import") (part "M01PTH_SMD_3.25X0.85MM_NO_SILK"))
    )
    (comp (ref "JP871")
      (value "M01PTH_SMD_3.25X0.85MM_NO_SILK")
      (footprint "eagle-import:1X01_SMD_3.25X0.85MM_NO_SILK")
      (libsource (lib "eagle-import") (part "M01PTH_SMD_3.25X0.85MM_NO_SILK"))
    )
    (comp (ref "JP872")
      (value "M01PTH_SMD_3.25X0.85MM_NO_SILK")
      (footprint "eagle-import:1X01_SMD_3.25X0.85MM_NO_SILK")
      (libsource (lib "eagle-import") (part "M01PTH_SMD_3.25X0.85MM_NO_SILK"))
    )
    (comp (ref "JP873")
      (value "M01PTH_SMD_3.25X0.85MM_NO_SILK")
      (footprint "eagle-import:1X01_SMD_3.25X0.85MM_NO_SILK")
      (libsource (lib "eagle-import") (part "M01PTH_SMD_3.25X0.85MM_NO_SILK"))
    )
    (comp (ref "JP874")
      (value "M01PTH_SMD_3.25X0.85MM_NO_SILK")
      (footprint "eagle-import:1X01_SMD_3.25X0.85MM_NO_SILK")
      (libsource (lib "eagle-import") (part "M01PTH_SMD_3.25X0.85MM_NO_SILK"))
    )
    (comp (ref "JP875")
      (value "M01PTH_SMD_3.25X0.85MM_NO_SILK")
      (footprint "eagle-import:1X01_SMD_3.25X0.85MM_NO_SILK")
      (libsource (lib "eagle-import") (part "M01PTH_SMD_3.25X0.85MM_NO_SILK"))
    )
    (comp (ref "JP876")
      (value "M01PTH_SMD_3.25X0.85MM_NO_SILK")
      (footprint "eagle-import:1X01_SMD_3.25X0.85MM_NO_SILK")
      (libsource (lib "eagle-import") (part "M01PTH_SMD_3.25X0.85MM_NO_SILK"))
    )
    (comp (ref "JP877")
      (value "M01PTH_SMD_3.25X0.85MM_NO_SILK")
      (footprint "eagle-import:1X01_SMD_3.25X0.85MM_NO_SILK")
      (libsource (lib "eagle-import") (part "M01PTH_SMD_3.25X0.85MM_NO_SILK"))
    )
    (comp (ref "JP878")
      (value "M01PTH_SMD_3.25X0.85MM_NO_SILK")
      (footprint "eagle-import:1X01_SMD_3.25X0.85MM_NO_SILK")
      (libsource (lib "eagle-import") (part "M01PTH_SMD_3.25X0.85MM_NO_SILK"))
    )
    (comp (ref "JP879")
      (value "M01PTH_SMD_3.25X0.85MM_NO_SILK")
      (footprint "eagle-import:1X01_SMD_3.25X0.85MM_NO_SILK")
      (libsource (lib "eagle-import") (part "M01PTH_SMD_3.25X0.85MM_NO_SILK"))
    )
    (comp (ref "JP880")
      (value "M01PTH_SMD_3.25X0.85MM_NO_SILK")
      (footprint "eagle-import:1X01_SMD_3.25X0.85MM_NO_SILK")
      (libsource (lib "eagle-import") (part "M01PTH_SMD_3.25X0.85MM_NO_SILK"))
    )
    (comp (ref "JP881")
      (value "M01PTH_SMD_3.25X0.85MM_NO_SILK")
      (footprint "eagle-import:1X01_SMD_3.25X0.85MM_NO_SILK")
      (libsource (lib "eagle-import") (part "M01PTH_SMD_3.25X0.85MM_NO_SILK"))
    )
    (comp (ref "JP882")
      (value "M01PTH_SMD_3.25X0.85MM_NO_SILK")
      (footprint "eagle-import:1X01_SMD_3.25X0.85MM_NO_SILK")
      (libsource (lib "eagle-import") (part "M01PTH_SMD_3.25X0.85MM_NO_SILK"))
    )
    (comp (ref "JP883")
      (value "M01PTH_SMD_3.25X0.85MM_NO_SILK")
      (footprint "eagle-import:1X01_SMD_3.25X0.85MM_NO_SILK")
      (libsource (lib "eagle-import") (part "M01PTH_SMD_3.25X0.85MM_NO_SILK"))
    )
    (comp (ref "JP884")
      (value "M01PTH_SMD_3.25X0.85MM_NO_SILK")
      (footprint "eagle-import:1X01_SMD_3.25X0.85MM_NO_SILK")
      (libsource (lib "eagle-import") (part "M01PTH_SMD_3.25X0.85MM_NO_SILK"))
    )
    (comp (ref "JP885")
      (value "M01PTH_SMD_3.25X0.85MM_NO_SILK")
      (footprint "eagle-import:1X01_SMD_3.25X0.85MM_NO_SILK")
      (libsource (lib "eagle-import") (part "M01PTH_SMD_3.25X0.85MM_NO_SILK"))
    )
    (comp (ref "JP886")
      (value "M01PTH_SMD_3.25X0.85MM_NO_SILK")
      (footprint "eagle-import:1X01_SMD_3.25X0.85MM_NO_SILK")
      (libsource (lib "eagle-import") (part "M01PTH_SMD_3.25X0.85MM_NO_SILK"))
    )
    (comp (ref "JP887")
      (value "M01PTH_SMD_3.25X0.85MM_NO_SILK")
      (footprint "eagle-import:1X01_SMD_3.25X0.85MM_NO_SILK")
      (libsource (lib "eagle-import") (part "M01PTH_SMD_3.25X0.85MM_NO_SILK"))
    )
    (comp (ref "JP888")
      (value "M01PTH_SMD_3.25X0.85MM_NO_SILK")
      (footprint "eagle-import:1X01_SMD_3.25X0.85MM_NO_SILK")
      (libsource (lib "eagle-import") (part "M01PTH_SMD_3.25X0.85MM_NO_SILK"))
    )
    (comp (ref "JP889")
      (value "M01PTH_SMD_3.25X0.85MM_NO_SILK")
      (footprint "eagle-import:1X01_SMD_3.25X0.85MM_NO_SILK")
      (libsource (lib "eagle-import") (part "M01PTH_SMD_3.25X0.85MM_NO_SILK"))
    )
    (comp (ref "JP890")
      (value "M01PTH_SMD_3.25X0.85MM_NO_SILK")
      (footprint "eagle-import:1X01_SMD_3.25X0.85MM_NO_SILK")
      (libsource (lib "eagle-import") (part "M01PTH_SMD_3.25X0.85MM_NO_SILK"))
    )
    (comp (ref "JP891")
      (value "M01PTH_SMD_3.25X0.85MM_NO_SILK")
      (footprint "eagle-import:1X01_SMD_3.25X0.85MM_NO_SILK")
      (libsource (lib "eagle-import") (part "M01PTH_SMD_3.25X0.85MM_NO_SILK"))
    )
    (comp (ref "JP892")
      (value "M01PTH_SMD_3.25X0.85MM_NO_SILK")
      (footprint "eagle-import:1X01_SMD_3.25X0.85MM_NO_SILK")
      (libsource (lib "eagle-import") (part "M01PTH_SMD_3.25X0.85MM_NO_SILK"))
    )
    (comp (ref "JP893")
      (value "M01PTH_SMD_3.25X0.85MM_NO_SILK")
      (footprint "eagle-import:1X01_SMD_3.25X0.85MM_NO_SILK")
      (libsource (lib "eagle-import") (part "M01PTH_SMD_3.25X0.85MM_NO_SILK"))
    )
    (comp (ref "JP894")
      (value "M01PTH_SMD_3.25X0.85MM_NO_SILK")
      (footprint "eagle-import:1X01_SMD_3.25X0.85MM_NO_SILK")
      (libsource (lib "eagle-import") (part "M01PTH_SMD_3.25X0.85MM_NO_SILK"))
    )
    (comp (ref "JP895")
      (value "M01PTH_SMD_3.25X0.85MM_NO_SILK")
      (footprint "eagle-import:1X01_SMD_3.25X0.85MM_NO_SILK")
      (libsource (lib "eagle-import") (part "M01PTH_SMD_3.25X0.85MM_NO_SILK"))
    )
    (comp (ref "JP896")
      (value "M01PTH_SMD_3.25X0.85MM_NO_SILK")
      (footprint "eagle-import:1X01_SMD_3.25X0.85MM_NO_SILK")
      (libsource (lib "eagle-import") (part "M01PTH_SMD_3.25X0.85MM_NO_SILK"))
    )
    (comp (ref "JP897")
      (value "M01PTH_SMD_3.25X0.85MM_NO_SILK")
      (footprint "eagle-import:1X01_SMD_3.25X0.85MM_NO_SILK")
      (libsource (lib "eagle-import") (part "M01PTH_SMD_3.25X0.85MM_NO_SILK"))
    )
    (comp (ref "JP898")
      (value "M01PTH_SMD_3.25X0.85MM_NO_SILK")
      (footprint "eagle-import:1X01_SMD_3.25X0.85MM_NO_SILK")
      (libsource (lib "eagle-import") (part "M01PTH_SMD_3.25X0.85MM_NO_SILK"))
    )
    (comp (ref "JP899")
      (value "M01PTH_SMD_3.25X0.85MM_NO_SILK")
      (footprint "eagle-import:1X01_SMD_3.25X0.85MM_NO_SILK")
      (libsource (lib "eagle-import") (part "M01PTH_SMD_3.25X0.85MM_NO_SILK"))
    )
    (comp (ref "JP900")
      (value "M01PTH_SMD_3.25X0.85MM_NO_SILK")
      (footprint "eagle-import:1X01_SMD_3.25X0.85MM_NO_SILK")
      (libsource (lib "eagle-import") (part "M01PTH_SMD_3.25X0.85MM_NO_SILK"))
    )
    (comp (ref "JP901")
      (value "M01PTH_SMD_3.25X0.85MM_NO_SILK")
      (footprint "eagle-import:1X01_SMD_3.25X0.85MM_NO_SILK")
      (libsource (lib "eagle-import") (part "M01PTH_SMD_3.25X0.85MM_NO_SILK"))
    )
    (comp (ref "JP902")
      (value "M01PTH_SMD_3.25X0.85MM_NO_SILK")
      (footprint "eagle-import:1X01_SMD_3.25X0.85MM_NO_SILK")
      (libsource (lib "eagle-import") (part "M01PTH_SMD_3.25X0.85MM_NO_SILK"))
    )
    (comp (ref "JP903")
      (value "M01PTH_SMD_3.25X0.85MM_NO_SILK")
      (footprint "eagle-import:1X01_SMD_3.25X0.85MM_NO_SILK")
      (libsource (lib "eagle-import") (part "M01PTH_SMD_3.25X0.85MM_NO_SILK"))
    )
    (comp (ref "JP904")
      (value "M01PTH_SMD_3.25X0.85MM_NO_SILK")
      (footprint "eagle-import:1X01_SMD_3.25X0.85MM_NO_SILK")
      (libsource (lib "eagle-import") (part "M01PTH_SMD_3.25X0.85MM_NO_SILK"))
    )
    (comp (ref "JP905")
      (value "M01PTH_SMD_3.25X0.85MM_NO_SILK")
      (footprint "eagle-import:1X01_SMD_3.25X0.85MM_NO_SILK")
      (libsource (lib "eagle-import") (part "M01PTH_SMD_3.25X0.85MM_NO_SILK"))
    )
    (comp (ref "JP906")
      (value "M01PTH_SMD_3.25X0.85MM_NO_SILK")
      (footprint "eagle-import:1X01_SMD_3.25X0.85MM_NO_SILK")
      (libsource (lib "eagle-import") (part "M01PTH_SMD_3.25X0.85MM_NO_SILK"))
    )
    (comp (ref "JP907")
      (value "M01PTH_SMD_3.25X0.85MM_NO_SILK")
      (footprint "eagle-import:1X01_SMD_3.25X0.85MM_NO_SILK")
      (libsource (lib "eagle-import") (part "M01PTH_SMD_3.25X0.85MM_NO_SILK"))
    )
    (comp (ref "JP908")
      (value "M01PTH_SMD_3.25X0.85MM_NO_SILK")
      (footprint "eagle-import:1X01_SMD_3.25X0.85MM_NO_SILK")
      (libsource (lib "eagle-import") (part "M01PTH_SMD_3.25X0.85MM_NO_SILK"))
    )
    (comp (ref "JP909")
      (value "M01PTH_SMD_3.25X0.85MM_NO_SILK")
      (footprint "eagle-import:1X01_SMD_3.25X0.85MM_NO_SILK")
      (libsource (lib "eagle-import") (part "M01PTH_SMD_3.25X0.85MM_NO_SILK"))
    )
    (comp (ref "JP910")
      (value "M01PTH_SMD_3.25X0.85MM_NO_SILK")
      (footprint "eagle-import:1X01_SMD_3.25X0.85MM_NO_SILK")
      (libsource (lib "eagle-import") (part "M01PTH_SMD_3.25X0.85MM_NO_SILK"))
    )
    (comp (ref "JP911")
      (value "M01PTH_SMD_3.25X0.85MM_NO_SILK")
      (footprint "eagle-import:1X01_SMD_3.25X0.85MM_NO_SILK")
      (libsource (lib "eagle-import") (part "M01PTH_SMD_3.25X0.85MM_NO_SILK"))
    )
    (comp (ref "JP912")
      (value "M01PTH_SMD_3.25X0.85MM_NO_SILK")
      (footprint "eagle-import:1X01_SMD_3.25X0.85MM_NO_SILK")
      (libsource (lib "eagle-import") (part "M01PTH_SMD_3.25X0.85MM_NO_SILK"))
    )
    (comp (ref "JP913")
      (value "M01PTH_SMD_3.25X0.85MM_NO_SILK")
      (footprint "eagle-import:1X01_SMD_3.25X0.85MM_NO_SILK")
      (libsource (lib "eagle-import") (part "M01PTH_SMD_3.25X0.85MM_NO_SILK"))
    )
    (comp (ref "JP914")
      (value "M01PTH_SMD_3.25X0.85MM_NO_SILK")
      (footprint "eagle-import:1X01_SMD_3.25X0.85MM_NO_SILK")
      (libsource (lib "eagle-import") (part "M01PTH_SMD_3.25X0.85MM_NO_SILK"))
    )
    (comp (ref "JP915")
      (value "M01PTH_SMD_3.25X0.85MM_NO_SILK")
      (footprint "eagle-import:1X01_SMD_3.25X0.85MM_NO_SILK")
      (libsource (lib "eagle-import") (part "M01PTH_SMD_3.25X0.85MM_NO_SILK"))
    )
    (comp (ref "JP916")
      (value "M01PTH_SMD_3.25X0.85MM_NO_SILK")
      (footprint "eagle-import:1X01_SMD_3.25X0.85MM_NO_SILK")
      (libsource (lib "eagle-import") (part "M01PTH_SMD_3.25X0.85MM_NO_SILK"))
    )
    (comp (ref "JP917")
      (value "M01PTH_SMD_3.25X0.85MM_NO_SILK")
      (footprint "eagle-import:1X01_SMD_3.25X0.85MM_NO_SILK")
      (libsource (lib "eagle-import") (part "M01PTH_SMD_3.25X0.85MM_NO_SILK"))
    )
    (comp (ref "JP918")
      (value "M01PTH_SMD_3.25X0.85MM_NO_SILK")
      (footprint "eagle-import:1X01_SMD_3.25X0.85MM_NO_SILK")
      (libsource (lib "eagle-import") (part "M01PTH_SMD_3.25X0.85MM_NO_SILK"))
    )
    (comp (ref "JP919")
      (value "M01PTH_SMD_3.25X0.85MM_NO_SILK")
      (footprint "eagle-import:1X01_SMD_3.25X0.85MM_NO_SILK")
      (libsource (lib "eagle-import") (part "M01PTH_SMD_3.25X0.85MM_NO_SILK"))
    )
    (comp (ref "JP920")
      (value "M01PTH_SMD_3.25X0.85MM_NO_SILK")
      (footprint "eagle-import:1X01_SMD_3.25X0.85MM_NO_SILK")
      (libsource (lib "eagle-import") (part "M01PTH_SMD_3.25X0.85MM_NO_SILK"))
    )
    (comp (ref "JP921")
      (value "M01PTH_SMD_3.25X0.85MM_NO_SILK")
      (footprint "eagle-import:1X01_SMD_3.25X0.85MM_NO_SILK")
      (libsource (lib "eagle-import") (part "M01PTH_SMD_3.25X0.85MM_NO_SILK"))
    )
    (comp (ref "JP922")
      (value "M01PTH_SMD_3.25X0.85MM_NO_SILK")
      (footprint "eagle-import:1X01_SMD_3.25X0.85MM_NO_SILK")
      (libsource (lib "eagle-import") (part "M01PTH_SMD_3.25X0.85MM_NO_SILK"))
    )
    (comp (ref "JP923")
      (value "M01PTH_SMD_3.25X0.85MM_NO_SILK")
      (footprint "eagle-import:1X01_SMD_3.25X0.85MM_NO_SILK")
      (libsource (lib "eagle-import") (part "M01PTH_SMD_3.25X0.85MM_NO_SILK"))
    )
    (comp (ref "JP924")
      (value "M01PTH_SMD_3.25X0.85MM_NO_SILK")
      (footprint "eagle-import:1X01_SMD_3.25X0.85MM_NO_SILK")
      (libsource (lib "eagle-import") (part "M01PTH_SMD_3.25X0.85MM_NO_SILK"))
    )
    (comp (ref "JP925")
      (value "M01PTH_SMD_3.25X0.85MM_NO_SILK")
      (footprint "eagle-import:1X01_SMD_3.25X0.85MM_NO_SILK")
      (libsource (lib "eagle-import") (part "M01PTH_SMD_3.25X0.85MM_NO_SILK"))
    )
    (comp (ref "JP926")
      (value "M01PTH_SMD_3.25X0.85MM_NO_SILK")
      (footprint "eagle-import:1X01_SMD_3.25X0.85MM_NO_SILK")
      (libsource (lib "eagle-import") (part "M01PTH_SMD_3.25X0.85MM_NO_SILK"))
    )
    (comp (ref "JP927")
      (value "M01PTH_SMD_3.25X0.85MM_NO_SILK")
      (footprint "eagle-import:1X01_SMD_3.25X0.85MM_NO_SILK")
      (libsource (lib "eagle-import") (part "M01PTH_SMD_3.25X0.85MM_NO_SILK"))
    )
    (comp (ref "JP928")
      (value "M01PTH_SMD_3.25X0.85MM_NO_SILK")
      (footprint "eagle-import:1X01_SMD_3.25X0.85MM_NO_SILK")
      (libsource (lib "eagle-import") (part "M01PTH_SMD_3.25X0.85MM_NO_SILK"))
    )
    (comp (ref "JP929")
      (value "M01PTH_SMD_3.25X0.85MM_NO_SILK")
      (footprint "eagle-import:1X01_SMD_3.25X0.85MM_NO_SILK")
      (libsource (lib "eagle-import") (part "M01PTH_SMD_3.25X0.85MM_NO_SILK"))
    )
    (comp (ref "JP930")
      (value "M01PTH_SMD_3.25X0.85MM_NO_SILK")
      (footprint "eagle-import:1X01_SMD_3.25X0.85MM_NO_SILK")
      (libsource (lib "eagle-import") (part "M01PTH_SMD_3.25X0.85MM_NO_SILK"))
    )
    (comp (ref "JP931")
      (value "M01PTH_SMD_3.25X0.85MM_NO_SILK")
      (footprint "eagle-import:1X01_SMD_3.25X0.85MM_NO_SILK")
      (libsource (lib "eagle-import") (part "M01PTH_SMD_3.25X0.85MM_NO_SILK"))
    )
    (comp (ref "JP932")
      (value "M01PTH_SMD_3.25X0.85MM_NO_SILK")
      (footprint "eagle-import:1X01_SMD_3.25X0.85MM_NO_SILK")
      (libsource (lib "eagle-import") (part "M01PTH_SMD_3.25X0.85MM_NO_SILK"))
    )
    (comp (ref "JP933")
      (value "M01PTH_SMD_3.25X0.85MM_NO_SILK")
      (footprint "eagle-import:1X01_SMD_3.25X0.85MM_NO_SILK")
      (libsource (lib "eagle-import") (part "M01PTH_SMD_3.25X0.85MM_NO_SILK"))
    )
    (comp (ref "JP934")
      (value "M01PTH_SMD_3.25X0.85MM_NO_SILK")
      (footprint "eagle-import:1X01_SMD_3.25X0.85MM_NO_SILK")
      (libsource (lib "eagle-import") (part "M01PTH_SMD_3.25X0.85MM_NO_SILK"))
    )
    (comp (ref "JP935")
      (value "M01PTH_SMD_3.25X0.85MM_NO_SILK")
      (footprint "eagle-import:1X01_SMD_3.25X0.85MM_NO_SILK")
      (libsource (lib "eagle-import") (part "M01PTH_SMD_3.25X0.85MM_NO_SILK"))
    )
    (comp (ref "JP936")
      (value "M01PTH_SMD_3.25X0.85MM_NO_SILK")
      (footprint "eagle-import:1X01_SMD_3.25X0.85MM_NO_SILK")
      (libsource (lib "eagle-import") (part "M01PTH_SMD_3.25X0.85MM_NO_SILK"))
    )
    (comp (ref "JP937")
      (value "M01PTH_SMD_3.25X0.85MM_NO_SILK")
      (footprint "eagle-import:1X01_SMD_3.25X0.85MM_NO_SILK")
      (libsource (lib "eagle-import") (part "M01PTH_SMD_3.25X0.85MM_NO_SILK"))
    )
    (comp (ref "JP938")
      (value "M01PTH_SMD_3.25X0.85MM_NO_SILK")
      (footprint "eagle-import:1X01_SMD_3.25X0.85MM_NO_SILK")
      (libsource (lib "eagle-import") (part "M01PTH_SMD_3.25X0.85MM_NO_SILK"))
    )
    (comp (ref "JP939")
      (value "M01PTH_SMD_3.25X0.85MM_NO_SILK")
      (footprint "eagle-import:1X01_SMD_3.25X0.85MM_NO_SILK")
      (libsource (lib "eagle-import") (part "M01PTH_SMD_3.25X0.85MM_NO_SILK"))
    )
    (comp (ref "JP940")
      (value "M01PTH_SMD_3.25X0.85MM_NO_SILK")
      (footprint "eagle-import:1X01_SMD_3.25X0.85MM_NO_SILK")
      (libsource (lib "eagle-import") (part "M01PTH_SMD_3.25X0.85MM_NO_SILK"))
    )
    (comp (ref "JP941")
      (value "M01PTH_SMD_3.25X0.85MM_NO_SILK")
      (footprint "eagle-import:1X01_SMD_3.25X0.85MM_NO_SILK")
      (libsource (lib "eagle-import") (part "M01PTH_SMD_3.25X0.85MM_NO_SILK"))
    )
    (comp (ref "JP942")
      (value "M01PTH_SMD_3.25X0.85MM_NO_SILK")
      (footprint "eagle-import:1X01_SMD_3.25X0.85MM_NO_SILK")
      (libsource (lib "eagle-import") (part "M01PTH_SMD_3.25X0.85MM_NO_SILK"))
    )
    (comp (ref "JP943")
      (value "M01PTH_SMD_3.25X0.85MM_NO_SILK")
      (footprint "eagle-import:1X01_SMD_3.25X0.85MM_NO_SILK")
      (libsource (lib "eagle-import") (part "M01PTH_SMD_3.25X0.85MM_NO_SILK"))
    )
    (comp (ref "JP944")
      (value "M01PTH_SMD_3.25X0.85MM_NO_SILK")
      (footprint "eagle-import:1X01_SMD_3.25X0.85MM_NO_SILK")
      (libsource (lib "eagle-import") (part "M01PTH_SMD_3.25X0.85MM_NO_SILK"))
    )
    (comp (ref "JP945")
      (value "M01PTH_SMD_3.25X0.85MM_NO_SILK")
      (footprint "eagle-import:1X01_SMD_3.25X0.85MM_NO_SILK")
      (libsource (lib "eagle-import") (part "M01PTH_SMD_3.25X0.85MM_NO_SILK"))
    )
    (comp (ref "JP946")
      (value "M01PTH_SMD_3.25X0.85MM_NO_SILK")
      (footprint "eagle-import:1X01_SMD_3.25X0.85MM_NO_SILK")
      (libsource (lib "eagle-import") (part "M01PTH_SMD_3.25X0.85MM_NO_SILK"))
    )
    (comp (ref "JP947")
      (value "M01PTH_SMD_3.25X0.85MM_NO_SILK")
      (footprint "eagle-import:1X01_SMD_3.25X0.85MM_NO_SILK")
      (libsource (lib "eagle-import") (part "M01PTH_SMD_3.25X0.85MM_NO_SILK"))
    )
    (comp (ref "JP948")
      (value "M01PTH_SMD_3.25X0.85MM_NO_SILK")
      (footprint "eagle-import:1X01_SMD_3.25X0.85MM_NO_SILK")
      (libsource (lib "eagle-import") (part "M01PTH_SMD_3.25X0.85MM_NO_SILK"))
    )
    (comp (ref "JP949")
      (value "M01PTH_SMD_3.25X0.85MM_NO_SILK")
      (footprint "eagle-import:1X01_SMD_3.25X0.85MM_NO_SILK")
      (libsource (lib "eagle-import") (part "M01PTH_SMD_3.25X0.85MM_NO_SILK"))
    )
    (comp (ref "JP950")
      (value "M01PTH_SMD_3.25X0.85MM_NO_SILK")
      (footprint "eagle-import:1X01_SMD_3.25X0.85MM_NO_SILK")
      (libsource (lib "eagle-import") (part "M01PTH_SMD_3.25X0.85MM_NO_SILK"))
    )
    (comp (ref "JP951")
      (value "M01PTH_SMD_3.25X0.85MM_NO_SILK")
      (footprint "eagle-import:1X01_SMD_3.25X0.85MM_NO_SILK")
      (libsource (lib "eagle-import") (part "M01PTH_SMD_3.25X0.85MM_NO_SILK"))
    )
    (comp (ref "JP952")
      (value "M01PTH_SMD_3.25X0.85MM_NO_SILK")
      (footprint "eagle-import:1X01_SMD_3.25X0.85MM_NO_SILK")
      (libsource (lib "eagle-import") (part "M01PTH_SMD_3.25X0.85MM_NO_SILK"))
    )
    (comp (ref "JP953")
      (value "M01PTH_SMD_3.25X0.85MM_NO_SILK")
      (footprint "eagle-import:1X01_SMD_3.25X0.85MM_NO_SILK")
      (libsource (lib "eagle-import") (part "M01PTH_SMD_3.25X0.85MM_NO_SILK"))
    )
    (comp (ref "JP954")
      (value "M01PTH_SMD_3.25X0.85MM_NO_SILK")
      (footprint "eagle-import:1X01_SMD_3.25X0.85MM_NO_SILK")
      (libsource (lib "eagle-import") (part "M01PTH_SMD_3.25X0.85MM_NO_SILK"))
    )
    (comp (ref "JP955")
      (value "M01PTH_SMD_3.25X0.85MM_NO_SILK")
      (footprint "eagle-import:1X01_SMD_3.25X0.85MM_NO_SILK")
      (libsource (lib "eagle-import") (part "M01PTH_SMD_3.25X0.85MM_NO_SILK"))
    )
    (comp (ref "JP956")
      (value "M01PTH_SMD_3.25X0.85MM_NO_SILK")
      (footprint "eagle-import:1X01_SMD_3.25X0.85MM_NO_SILK")
      (libsource (lib "eagle-import") (part "M01PTH_SMD_3.25X0.85MM_NO_SILK"))
    )
    (comp (ref "JP957")
      (value "M01PTH_SMD_3.25X0.85MM_NO_SILK")
      (footprint "eagle-import:1X01_SMD_3.25X0.85MM_NO_SILK")
      (libsource (lib "eagle-import") (part "M01PTH_SMD_3.25X0.85MM_NO_SILK"))
    )
    (comp (ref "JP958")
      (value "M01PTH_SMD_3.25X0.85MM_NO_SILK")
      (footprint "eagle-import:1X01_SMD_3.25X0.85MM_NO_SILK")
      (libsource (lib "eagle-import") (part "M01PTH_SMD_3.25X0.85MM_NO_SILK"))
    )
    (comp (ref "JP959")
      (value "M01PTH_SMD_3.25X0.85MM_NO_SILK")
      (footprint "eagle-import:1X01_SMD_3.25X0.85MM_NO_SILK")
      (libsource (lib "eagle-import") (part "M01PTH_SMD_3.25X0.85MM_NO_SILK"))
    )
    (comp (ref "JP960")
      (value "M01PTH_SMD_3.25X0.85MM_NO_SILK")
      (footprint "eagle-import:1X01_SMD_3.25X0.85MM_NO_SILK")
      (libsource (lib "eagle-import") (part "M01PTH_SMD_3.25X0.85MM_NO_SILK"))
    )
    (comp (ref "JP961")
      (value "M01PTH_SMD_3.25X0.85MM_NO_SILK")
      (footprint "eagle-import:1X01_SMD_3.25X0.85MM_NO_SILK")
      (libsource (lib "eagle-import") (part "M01PTH_SMD_3.25X0.85MM_NO_SILK"))
    )
    (comp (ref "JP962")
      (value "M01PTH_SMD_3.25X0.85MM_NO_SILK")
      (footprint "eagle-import:1X01_SMD_3.25X0.85MM_NO_SILK")
      (libsource (lib "eagle-import") (part "M01PTH_SMD_3.25X0.85MM_NO_SILK"))
    )
    (comp (ref "JP963")
      (value "M01PTH_SMD_3.25X0.85MM_NO_SILK")
      (footprint "eagle-import:1X01_SMD_3.25X0.85MM_NO_SILK")
      (libsource (lib "eagle-import") (part "M01PTH_SMD_3.25X0.85MM_NO_SILK"))
    )
    (comp (ref "JP964")
      (value "M01PTH_SMD_3.25X0.85MM_NO_SILK")
      (footprint "eagle-import:1X01_SMD_3.25X0.85MM_NO_SILK")
      (libsource (lib "eagle-import") (part "M01PTH_SMD_3.25X0.85MM_NO_SILK"))
    )
    (comp (ref "JP965")
      (value "M01PTH_SMD_3.25X0.85MM_NO_SILK")
      (footprint "eagle-import:1X01_SMD_3.25X0.85MM_NO_SILK")
      (libsource (lib "eagle-import") (part "M01PTH_SMD_3.25X0.85MM_NO_SILK"))
    )
    (comp (ref "JP966")
      (value "M01PTH_SMD_3.25X0.85MM_NO_SILK")
      (footprint "eagle-import:1X01_SMD_3.25X0.85MM_NO_SILK")
      (libsource (lib "eagle-import") (part "M01PTH_SMD_3.25X0.85MM_NO_SILK"))
    )
    (comp (ref "JP967")
      (value "M01PTH_SMD_3.25X0.85MM_NO_SILK")
      (footprint "eagle-import:1X01_SMD_3.25X0.85MM_NO_SILK")
      (libsource (lib "eagle-import") (part "M01PTH_SMD_3.25X0.85MM_NO_SILK"))
    )
    (comp (ref "JP968")
      (value "M01PTH_SMD_3.25X0.85MM_NO_SILK")
      (footprint "eagle-import:1X01_SMD_3.25X0.85MM_NO_SILK")
      (libsource (lib "eagle-import") (part "M01PTH_SMD_3.25X0.85MM_NO_SILK"))
    )
    (comp (ref "JP969")
      (value "M01PTH_SMD_3.25X0.85MM_NO_SILK")
      (footprint "eagle-import:1X01_SMD_3.25X0.85MM_NO_SILK")
      (libsource (lib "eagle-import") (part "M01PTH_SMD_3.25X0.85MM_NO_SILK"))
    )
    (comp (ref "JP970")
      (value "M01PTH_SMD_3.25X0.85MM_NO_SILK")
      (footprint "eagle-import:1X01_SMD_3.25X0.85MM_NO_SILK")
      (libsource (lib "eagle-import") (part "M01PTH_SMD_3.25X0.85MM_NO_SILK"))
    )
    (comp (ref "JP971")
      (value "M01PTH_SMD_3.25X0.85MM_NO_SILK")
      (footprint "eagle-import:1X01_SMD_3.25X0.85MM_NO_SILK")
      (libsource (lib "eagle-import") (part "M01PTH_SMD_3.25X0.85MM_NO_SILK"))
    )
    (comp (ref "JP972")
      (value "M01PTH_SMD_3.25X0.85MM_NO_SILK")
      (footprint "eagle-import:1X01_SMD_3.25X0.85MM_NO_SILK")
      (libsource (lib "eagle-import") (part "M01PTH_SMD_3.25X0.85MM_NO_SILK"))
    )
    (comp (ref "JP973")
      (value "M01PTH_SMD_3.25X0.85MM_NO_SILK")
      (footprint "eagle-import:1X01_SMD_3.25X0.85MM_NO_SILK")
      (libsource (lib "eagle-import") (part "M01PTH_SMD_3.25X0.85MM_NO_SILK"))
    )
    (comp (ref "JP974")
      (value "M01PTH_SMD_3.25X0.85MM_NO_SILK")
      (footprint "eagle-import:1X01_SMD_3.25X0.85MM_NO_SILK")
      (libsource (lib "eagle-import") (part "M01PTH_SMD_3.25X0.85MM_NO_SILK"))
    )
    (comp (ref "JP975")
      (value "M01PTH_SMD_3.25X0.85MM_NO_SILK")
      (footprint "eagle-import:1X01_SMD_3.25X0.85MM_NO_SILK")
      (libsource (lib "eagle-import") (part "M01PTH_SMD_3.25X0.85MM_NO_SILK"))
    )
    (comp (ref "JP976")
      (value "M01PTH_SMD_3.25X0.85MM_NO_SILK")
      (footprint "eagle-import:1X01_SMD_3.25X0.85MM_NO_SILK")
      (libsource (lib "eagle-import") (part "M01PTH_SMD_3.25X0.85MM_NO_SILK"))
    )
    (comp (ref "JP977")
      (value "M01PTH_SMD_3.25X0.85MM_NO_SILK")
      (footprint "eagle-import:1X01_SMD_3.25X0.85MM_NO_SILK")
      (libsource (lib "eagle-import") (part "M01PTH_SMD_3.25X0.85MM_NO_SILK"))
    )
    (comp (ref "JP978")
      (value "M01PTH_SMD_3.25X0.85MM_NO_SILK")
      (footprint "eagle-import:1X01_SMD_3.25X0.85MM_NO_SILK")
      (libsource (lib "eagle-import") (part "M01PTH_SMD_3.25X0.85MM_NO_SILK"))
    )
    (comp (ref "JP979")
      (value "M01PTH_SMD_3.25X0.85MM_NO_SILK")
      (footprint "eagle-import:1X01_SMD_3.25X0.85MM_NO_SILK")
      (libsource (lib "eagle-import") (part "M01PTH_SMD_3.25X0.85MM_NO_SILK"))
    )
    (comp (ref "JP980")
      (value "M01PTH_SMD_3.25X0.85MM_NO_SILK")
      (footprint "eagle-import:1X01_SMD_3.25X0.85MM_NO_SILK")
      (libsource (lib "eagle-import") (part "M01PTH_SMD_3.25X0.85MM_NO_SILK"))
    )
    (comp (ref "JP981")
      (value "M01PTH_SMD_3.25X0.85MM_NO_SILK")
      (footprint "eagle-import:1X01_SMD_3.25X0.85MM_NO_SILK")
      (libsource (lib "eagle-import") (part "M01PTH_SMD_3.25X0.85MM_NO_SILK"))
    )
    (comp (ref "JP982")
      (value "M01PTH_SMD_3.25X0.85MM_NO_SILK")
      (footprint "eagle-import:1X01_SMD_3.25X0.85MM_NO_SILK")
      (libsource (lib "eagle-import") (part "M01PTH_SMD_3.25X0.85MM_NO_SILK"))
    )
    (comp (ref "JP983")
      (value "M01PTH_SMD_3.25X0.85MM_NO_SILK")
      (footprint "eagle-import:1X01_SMD_3.25X0.85MM_NO_SILK")
      (libsource (lib "eagle-import") (part "M01PTH_SMD_3.25X0.85MM_NO_SILK"))
    )
    (comp (ref "JP984")
      (value "M01PTH_SMD_3.25X0.85MM_NO_SILK")
      (footprint "eagle-import:1X01_SMD_3.25X0.85MM_NO_SILK")
      (libsource (lib "eagle-import") (part "M01PTH_SMD_3.25X0.85MM_NO_SILK"))
    )
    (comp (ref "JP985")
      (value "M01PTH_SMD_3.25X0.85MM_NO_SILK")
      (footprint "eagle-import:1X01_SMD_3.25X0.85MM_NO_SILK")
      (libsource (lib "eagle-import") (part "M01PTH_SMD_3.25X0.85MM_NO_SILK"))
    )
    (comp (ref "JP986")
      (value "M01PTH_SMD_3.25X0.85MM_NO_SILK")
      (footprint "eagle-import:1X01_SMD_3.25X0.85MM_NO_SILK")
      (libsource (lib "eagle-import") (part "M01PTH_SMD_3.25X0.85MM_NO_SILK"))
    )
    (comp (ref "JP987")
      (value "M01PTH_SMD_3.25X0.85MM_NO_SILK")
      (footprint "eagle-import:1X01_SMD_3.25X0.85MM_NO_SILK")
      (libsource (lib "eagle-import") (part "M01PTH_SMD_3.25X0.85MM_NO_SILK"))
    )
    (comp (ref "JP988")
      (value "M01PTH_SMD_3.25X0.85MM_NO_SILK")
      (footprint "eagle-import:1X01_SMD_3.25X0.85MM_NO_SILK")
      (libsource (lib "eagle-import") (part "M01PTH_SMD_3.25X0.85MM_NO_SILK"))
    )
    (comp (ref "JP989")
      (value "M01PTH_SMD_3.25X0.85MM_NO_SILK")
      (footprint "eagle-import:1X01_SMD_3.25X0.85MM_NO_SILK")
      (libsource (lib "eagle-import") (part "M01PTH_SMD_3.25X0.85MM_NO_SILK"))
    )
    (comp (ref "JP990")
      (value "M01PTH_SMD_3.25X0.85MM_NO_SILK")
      (footprint "eagle-import:1X01_SMD_3.25X0.85MM_NO_SILK")
      (libsource (lib "eagle-import") (part "M01PTH_SMD_3.25X0.85MM_NO_SILK"))
    )
    (comp (ref "JP991")
      (value "M01PTH_SMD_3.25X0.85MM_NO_SILK")
      (footprint "eagle-import:1X01_SMD_3.25X0.85MM_NO_SILK")
      (libsource (lib "eagle-import") (part "M01PTH_SMD_3.25X0.85MM_NO_SILK"))
    )
    (comp (ref "JP992")
      (value "M01PTH_SMD_3.25X0.85MM_NO_SILK")
      (footprint "eagle-import:1X01_SMD_3.25X0.85MM_NO_SILK")
      (libsource (lib "eagle-import") (part "M01PTH_SMD_3.25X0.85MM_NO_SILK"))
    )
    (comp (ref "JP993")
      (value "M01PTH_SMD_3.25X0.85MM_NO_SILK")
      (footprint "eagle-import:1X01_SMD_3.25X0.85MM_NO_SILK")
      (libsource (lib "eagle-import") (part "M01PTH_SMD_3.25X0.85MM_NO_SILK"))
    )
    (comp (ref "JP994")
      (value "M01PTH_SMD_3.25X0.85MM_NO_SILK")
      (footprint "eagle-import:1X01_SMD_3.25X0.85MM_NO_SILK")
      (libsource (lib "eagle-import") (part "M01PTH_SMD_3.25X0.85MM_NO_SILK"))
    )
    (comp (ref "JP995")
      (value "M01PTH_SMD_3.25X0.85MM_NO_SILK")
      (footprint "eagle-import:1X01_SMD_3.25X0.85MM_NO_SILK")
      (libsource (lib "eagle-import") (part "M01PTH_SMD_3.25X0.85MM_NO_SILK"))
    )
    (comp (ref "JP996")
      (value "M01PTH_SMD_3.25X0.85MM_NO_SILK")
      (footprint "eagle-import:1X01_SMD_3.25X0.85MM_NO_SILK")
      (libsource (lib "eagle-import") (part "M01PTH_SMD_3.25X0.85MM_NO_SILK"))
    )
    (comp (ref "JP997")
      (value "M01PTH_SMD_3.25X0.85MM_NO_SILK")
      (footprint "eagle-import:1X01_SMD_3.25X0.85MM_NO_SILK")
      (libsource (lib "eagle-import") (part "M01PTH_SMD_3.25X0.85MM_NO_SILK"))
    )
    (comp (ref "JP998")
      (value "M01PTH_SMD_3.25X0.85MM_NO_SILK")
      (footprint "eagle-import:1X01_SMD_3.25X0.85MM_NO_SILK")
      (libsource (lib "eagle-import") (part "M01PTH_SMD_3.25X0.85MM_NO_SILK"))
    )
    (comp (ref "JP999")
      (value "M01PTH_SMD_3.25X0.85MM_NO_SILK")
      (footprint "eagle-import:1X01_SMD_3.25X0.85MM_NO_SILK")
      (libsource (lib "eagle-import") (part "M01PTH_SMD_3.25X0.85MM_NO_SILK"))
    )
    (comp (ref "JP1000")
      (value "M01PTH_SMD_3.25X0.85MM_NO_SILK")
      (footprint "eagle-import:1X01_SMD_3.25X0.85MM_NO_SILK")
      (libsource (lib "eagle-import") (part "M01PTH_SMD_3.25X0.85MM_NO_SILK"))
    )
    (comp (ref "JP1001")
      (value "M01PTH_SMD_3.25X0.85MM_NO_SILK")
      (footprint "eagle-import:1X01_SMD_3.25X0.85MM_NO_SILK")
      (libsource (lib "eagle-import") (part "M01PTH_SMD_3.25X0.85MM_NO_SILK"))
    )
    (comp (ref "JP1002")
      (value "M01PTH_SMD_3.25X0.85MM_NO_SILK")
      (footprint "eagle-import:1X01_SMD_3.25X0.85MM_NO_SILK")
      (libsource (lib "eagle-import") (part "M01PTH_SMD_3.25X0.85MM_NO_SILK"))
    )
    (comp (ref "JP1003")
      (value "M01PTH_SMD_3.25X0.85MM_NO_SILK")
      (footprint "eagle-import:1X01_SMD_3.25X0.85MM_NO_SILK")
      (libsource (lib "eagle-import") (part "M01PTH_SMD_3.25X0.85MM_NO_SILK"))
    )
    (comp (ref "JP1004")
      (value "M01PTH_SMD_3.25X0.85MM_NO_SILK")
      (footprint "eagle-import:1X01_SMD_3.25X0.85MM_NO_SILK")
      (libsource (lib "eagle-import") (part "M01PTH_SMD_3.25X0.85MM_NO_SILK"))
    )
    (comp (ref "JP1005")
      (value "M01PTH_SMD_3.25X0.85MM_NO_SILK")
      (footprint "eagle-import:1X01_SMD_3.25X0.85MM_NO_SILK")
      (libsource (lib "eagle-import") (part "M01PTH_SMD_3.25X0.85MM_NO_SILK"))
    )
    (comp (ref "JP1006")
      (value "M01PTH_SMD_3.25X0.85MM_NO_SILK")
      (footprint "eagle-import:1X01_SMD_3.25X0.85MM_NO_SILK")
      (libsource (lib "eagle-import") (part "M01PTH_SMD_3.25X0.85MM_NO_SILK"))
    )
    (comp (ref "JP1007")
      (value "M01PTH_SMD_3.25X0.85MM_NO_SILK")
      (footprint "eagle-import:1X01_SMD_3.25X0.85MM_NO_SILK")
      (libsource (lib "eagle-import") (part "M01PTH_SMD_3.25X0.85MM_NO_SILK"))
    )
    (comp (ref "JP1008")
      (value "M01PTH_SMD_3.25X0.85MM_NO_SILK")
      (footprint "eagle-import:1X01_SMD_3.25X0.85MM_NO_SILK")
      (libsource (lib "eagle-import") (part "M01PTH_SMD_3.25X0.85MM_NO_SILK"))
    )
    (comp (ref "JP1009")
      (value "M01PTH_SMD_3.25X0.85MM_NO_SILK")
      (footprint "eagle-import:1X01_SMD_3.25X0.85MM_NO_SILK")
      (libsource (lib "eagle-import") (part "M01PTH_SMD_3.25X0.85MM_NO_SILK"))
    )
    (comp (ref "JP1010")
      (value "M01PTH_SMD_3.25X0.85MM_NO_SILK")
      (footprint "eagle-import:1X01_SMD_3.25X0.85MM_NO_SILK")
      (libsource (lib "eagle-import") (part "M01PTH_SMD_3.25X0.85MM_NO_SILK"))
    )
    (comp (ref "JP1011")
      (value "M01PTH_SMD_3.25X0.85MM_NO_SILK")
      (footprint "eagle-import:1X01_SMD_3.25X0.85MM_NO_SILK")
      (libsource (lib "eagle-import") (part "M01PTH_SMD_3.25X0.85MM_NO_SILK"))
    )
    (comp (ref "JP1012")
      (value "M01PTH_SMD_3.25X0.85MM_NO_SILK")
      (footprint "eagle-import:1X01_SMD_3.25X0.85MM_NO_SILK")
      (libsource (lib "eagle-import") (part "M01PTH_SMD_3.25X0.85MM_NO_SILK"))
    )
    (comp (ref "JP1013")
      (value "M01PTH_SMD_3.25X0.85MM_NO_SILK")
      (footprint "eagle-import:1X01_SMD_3.25X0.85MM_NO_SILK")
      (libsource (lib "eagle-import") (part "M01PTH_SMD_3.25X0.85MM_NO_SILK"))
    )
    (comp (ref "JP1014")
      (value "M01PTH_SMD_3.25X0.85MM_NO_SILK")
      (footprint "eagle-import:1X01_SMD_3.25X0.85MM_NO_SILK")
      (libsource (lib "eagle-import") (part "M01PTH_SMD_3.25X0.85MM_NO_SILK"))
    )
    (comp (ref "JP1015")
      (value "M01PTH_SMD_3.25X0.85MM_NO_SILK")
      (footprint "eagle-import:1X01_SMD_3.25X0.85MM_NO_SILK")
      (libsource (lib "eagle-import") (part "M01PTH_SMD_3.25X0.85MM_NO_SILK"))
    )
    (comp (ref "JP1016")
      (value "M01PTH_SMD_3.25X0.85MM_NO_SILK")
      (footprint "eagle-import:1X01_SMD_3.25X0.85MM_NO_SILK")
      (libsource (lib "eagle-import") (part "M01PTH_SMD_3.25X0.85MM_NO_SILK"))
    )
    (comp (ref "JP1017")
      (value "M01PTH_SMD_3.25X0.85MM_NO_SILK")
      (footprint "eagle-import:1X01_SMD_3.25X0.85MM_NO_SILK")
      (libsource (lib "eagle-import") (part "M01PTH_SMD_3.25X0.85MM_NO_SILK"))
    )
    (comp (ref "JP1018")
      (value "M01PTH_SMD_3.25X0.85MM_NO_SILK")
      (footprint "eagle-import:1X01_SMD_3.25X0.85MM_NO_SILK")
      (libsource (lib "eagle-import") (part "M01PTH_SMD_3.25X0.85MM_NO_SILK"))
    )
    (comp (ref "JP1019")
      (value "M01PTH_SMD_3.25X0.85MM_NO_SILK")
      (footprint "eagle-import:1X01_SMD_3.25X0.85MM_NO_SILK")
      (libsource (lib "eagle-import") (part "M01PTH_SMD_3.25X0.85MM_NO_SILK"))
    )
    (comp (ref "JP1020")
      (value "M01PTH_SMD_3.25X0.85MM_NO_SILK")
      (footprint "eagle-import:1X01_SMD_3.25X0.85MM_NO_SILK")
      (libsource (lib "eagle-import") (part "M01PTH_SMD_3.25X0.85MM_NO_SILK"))
    )
    (comp (ref "JP1021")
      (value "M01PTH_SMD_3.25X0.85MM_NO_SILK")
      (footprint "eagle-import:1X01_SMD_3.25X0.85MM_NO_SILK")
      (libsource (lib "eagle-import") (part "M01PTH_SMD_3.25X0.85MM_NO_SILK"))
    )
    (comp (ref "JP1022")
      (value "M01PTH_SMD_3.25X0.85MM_NO_SILK")
      (footprint "eagle-import:1X01_SMD_3.25X0.85MM_NO_SILK")
      (libsource (lib "eagle-import") (part "M01PTH_SMD_3.25X0.85MM_NO_SILK"))
    )
    (comp (ref "JP1023")
      (value "M01PTH_SMD_3.25X0.85MM_NO_SILK")
      (footprint "eagle-import:1X01_SMD_3.25X0.85MM_NO_SILK")
      (libsource (lib "eagle-import") (part "M01PTH_SMD_3.25X0.85MM_NO_SILK"))
    )
    (comp (ref "JP1024")
      (value "M01PTH_SMD_3.25X0.85MM_NO_SILK")
      (footprint "eagle-import:1X01_SMD_3.25X0.85MM_NO_SILK")
      (libsource (lib "eagle-import") (part "M01PTH_SMD_3.25X0.85MM_NO_SILK"))
    )
    (comp (ref "JP1025")
      (value "M01PTH_SMD_3.25X0.85MM_NO_SILK")
      (footprint "eagle-import:1X01_SMD_3.25X0.85MM_NO_SILK")
      (libsource (lib "eagle-import") (part "M01PTH_SMD_3.25X0.85MM_NO_SILK"))
    )
    (comp (ref "JP1026")
      (value "M01PTH_SMD_3.25X0.85MM_NO_SILK")
      (footprint "eagle-import:1X01_SMD_3.25X0.85MM_NO_SILK")
      (libsource (lib "eagle-import") (part "M01PTH_SMD_3.25X0.85MM_NO_SILK"))
    )
    (comp (ref "JP1027")
      (value "M01PTH_SMD_3.25X0.85MM_NO_SILK")
      (footprint "eagle-import:1X01_SMD_3.25X0.85MM_NO_SILK")
      (libsource (lib "eagle-import") (part "M01PTH_SMD_3.25X0.85MM_NO_SILK"))
    )
    (comp (ref "JP1028")
      (value "M01PTH_SMD_3.25X0.85MM_NO_SILK")
      (footprint "eagle-import:1X01_SMD_3.25X0.85MM_NO_SILK")
      (libsource (lib "eagle-import") (part "M01PTH_SMD_3.25X0.85MM_NO_SILK"))
    )
    (comp (ref "JP1029")
      (value "M01PTH_SMD_3.25X0.85MM_NO_SILK")
      (footprint "eagle-import:1X01_SMD_3.25X0.85MM_NO_SILK")
      (libsource (lib "eagle-import") (part "M01PTH_SMD_3.25X0.85MM_NO_SILK"))
    )
    (comp (ref "JP1030")
      (value "M01PTH_SMD_3.25X0.85MM_NO_SILK")
      (footprint "eagle-import:1X01_SMD_3.25X0.85MM_NO_SILK")
      (libsource (lib "eagle-import") (part "M01PTH_SMD_3.25X0.85MM_NO_SILK"))
    )
    (comp (ref "JP1031")
      (value "M01PTH_SMD_3.25X0.85MM_NO_SILK")
      (footprint "eagle-import:1X01_SMD_3.25X0.85MM_NO_SILK")
      (libsource (lib "eagle-import") (part "M01PTH_SMD_3.25X0.85MM_NO_SILK"))
    )
    (comp (ref "JP1032")
      (value "M01PTH_SMD_3.25X0.85MM_NO_SILK")
      (footprint "eagle-import:1X01_SMD_3.25X0.85MM_NO_SILK")
      (libsource (lib "eagle-import") (part "M01PTH_SMD_3.25X0.85MM_NO_SILK"))
    )
    (comp (ref "JP1033")
      (value "M01PTH_SMD_3.25X0.85MM_NO_SILK")
      (footprint "eagle-import:1X01_SMD_3.25X0.85MM_NO_SILK")
      (libsource (lib "eagle-import") (part "M01PTH_SMD_3.25X0.85MM_NO_SILK"))
    )
    (comp (ref "JP1034")
      (value "M01PTH_SMD_3.25X0.85MM_NO_SILK")
      (footprint "eagle-import:1X01_SMD_3.25X0.85MM_NO_SILK")
      (libsource (lib "eagle-import") (part "M01PTH_SMD_3.25X0.85MM_NO_SILK"))
    )
    (comp (ref "JP1035")
      (value "M01PTH_SMD_3.25X0.85MM_NO_SILK")
      (footprint "eagle-import:1X01_SMD_3.25X0.85MM_NO_SILK")
      (libsource (lib "eagle-import") (part "M01PTH_SMD_3.25X0.85MM_NO_SILK"))
    )
    (comp (ref "JP1036")
      (value "M01PTH_SMD_3.25X0.85MM_NO_SILK")
      (footprint "eagle-import:1X01_SMD_3.25X0.85MM_NO_SILK")
      (libsource (lib "eagle-import") (part "M01PTH_SMD_3.25X0.85MM_NO_SILK"))
    )
    (comp (ref "JP1037")
      (value "M01PTH_SMD_3.25X0.85MM_NO_SILK")
      (footprint "eagle-import:1X01_SMD_3.25X0.85MM_NO_SILK")
      (libsource (lib "eagle-import") (part "M01PTH_SMD_3.25X0.85MM_NO_SILK"))
    )
    (comp (ref "JP1038")
      (value "M01PTH_SMD_3.25X0.85MM_NO_SILK")
      (footprint "eagle-import:1X01_SMD_3.25X0.85MM_NO_SILK")
      (libsource (lib "eagle-import") (part "M01PTH_SMD_3.25X0.85MM_NO_SILK"))
    )
    (comp (ref "JP1039")
      (value "M01PTH_SMD_3.25X0.85MM_NO_SILK")
      (footprint "eagle-import:1X01_SMD_3.25X0.85MM_NO_SILK")
      (libsource (lib "eagle-import") (part "M01PTH_SMD_3.25X0.85MM_NO_SILK"))
    )
    (comp (ref "JP1040")
      (value "M01PTH_SMD_3.25X0.85MM_NO_SILK")
      (footprint "eagle-import:1X01_SMD_3.25X0.85MM_NO_SILK")
      (libsource (lib "eagle-import") (part "M01PTH_SMD_3.25X0.85MM_NO_SILK"))
    )
    (comp (ref "JP1041")
      (value "M01PTH_SMD_3.25X0.85MM_NO_SILK")
      (footprint "eagle-import:1X01_SMD_3.25X0.85MM_NO_SILK")
      (libsource (lib "eagle-import") (part "M01PTH_SMD_3.25X0.85MM_NO_SILK"))
    )
    (comp (ref "JP1042")
      (value "M01PTH_SMD_3.25X0.85MM_NO_SILK")
      (footprint "eagle-import:1X01_SMD_3.25X0.85MM_NO_SILK")
      (libsource (lib "eagle-import") (part "M01PTH_SMD_3.25X0.85MM_NO_SILK"))
    )
    (comp (ref "JP1043")
      (value "M01PTH_SMD_3.25X0.85MM_NO_SILK")
      (footprint "eagle-import:1X01_SMD_3.25X0.85MM_NO_SILK")
      (libsource (lib "eagle-import") (part "M01PTH_SMD_3.25X0.85MM_NO_SILK"))
    )
    (comp (ref "JP1044")
      (value "M01PTH_SMD_3.25X0.85MM_NO_SILK")
      (footprint "eagle-import:1X01_SMD_3.25X0.85MM_NO_SILK")
      (libsource (lib "eagle-import") (part "M01PTH_SMD_3.25X0.85MM_NO_SILK"))
    )
    (comp (ref "JP1045")
      (value "M01PTH_SMD_3.25X0.85MM_NO_SILK")
      (footprint "eagle-import:1X01_SMD_3.25X0.85MM_NO_SILK")
      (libsource (lib "eagle-import") (part "M01PTH_SMD_3.25X0.85MM_NO_SILK"))
    )
    (comp (ref "JP1046")
      (value "M01PTH_SMD_3.25X0.85MM_NO_SILK")
      (footprint "eagle-import:1X01_SMD_3.25X0.85MM_NO_SILK")
      (libsource (lib "eagle-import") (part "M01PTH_SMD_3.25X0.85MM_NO_SILK"))
    )
    (comp (ref "JP1047")
      (value "M01PTH_SMD_3.25X0.85MM_NO_SILK")
      (footprint "eagle-import:1X01_SMD_3.25X0.85MM_NO_SILK")
      (libsource (lib "eagle-import") (part "M01PTH_SMD_3.25X0.85MM_NO_SILK"))
    )
    (comp (ref "JP1048")
      (value "M01PTH_SMD_3.25X0.85MM_NO_SILK")
      (footprint "eagle-import:1X01_SMD_3.25X0.85MM_NO_SILK")
      (libsource (lib "eagle-import") (part "M01PTH_SMD_3.25X0.85MM_NO_SILK"))
    )
    (comp (ref "JP1049")
      (value "M01PTH_SMD_3.25X0.85MM_NO_SILK")
      (footprint "eagle-import:1X01_SMD_3.25X0.85MM_NO_SILK")
      (libsource (lib "eagle-import") (part "M01PTH_SMD_3.25X0.85MM_NO_SILK"))
    )
    (comp (ref "JP1050")
      (value "M01PTH_SMD_3.25X0.85MM_NO_SILK")
      (footprint "eagle-import:1X01_SMD_3.25X0.85MM_NO_SILK")
      (libsource (lib "eagle-import") (part "M01PTH_SMD_3.25X0.85MM_NO_SILK"))
    )
    (comp (ref "JP1051")
      (value "M01PTH_SMD_3.25X0.85MM_NO_SILK")
      (footprint "eagle-import:1X01_SMD_3.25X0.85MM_NO_SILK")
      (libsource (lib "eagle-import") (part "M01PTH_SMD_3.25X0.85MM_NO_SILK"))
    )
    (comp (ref "JP1052")
      (value "M01PTH_SMD_3.25X0.85MM_NO_SILK")
      (footprint "eagle-import:1X01_SMD_3.25X0.85MM_NO_SILK")
      (libsource (lib "eagle-import") (part "M01PTH_SMD_3.25X0.85MM_NO_SILK"))
    )
    (comp (ref "JP1053")
      (value "M01PTH_SMD_3.25X0.85MM_NO_SILK")
      (footprint "eagle-import:1X01_SMD_3.25X0.85MM_NO_SILK")
      (libsource (lib "eagle-import") (part "M01PTH_SMD_3.25X0.85MM_NO_SILK"))
    )
    (comp (ref "JP1054")
      (value "M01PTH_SMD_3.25X0.85MM_NO_SILK")
      (footprint "eagle-import:1X01_SMD_3.25X0.85MM_NO_SILK")
      (libsource (lib "eagle-import") (part "M01PTH_SMD_3.25X0.85MM_NO_SILK"))
    )
    (comp (ref "JP1055")
      (value "M01PTH_SMD_3.25X0.85MM_NO_SILK")
      (footprint "eagle-import:1X01_SMD_3.25X0.85MM_NO_SILK")
      (libsource (lib "eagle-import") (part "M01PTH_SMD_3.25X0.85MM_NO_SILK"))
    )
    (comp (ref "JP1056")
      (value "M01PTH_SMD_3.25X0.85MM_NO_SILK")
      (footprint "eagle-import:1X01_SMD_3.25X0.85MM_NO_SILK")
      (libsource (lib "eagle-import") (part "M01PTH_SMD_3.25X0.85MM_NO_SILK"))
    )
    (comp (ref "JP1057")
      (value "M01PTH_SMD_3.25X0.85MM_NO_SILK")
      (footprint "eagle-import:1X01_SMD_3.25X0.85MM_NO_SILK")
      (libsource (lib "eagle-import") (part "M01PTH_SMD_3.25X0.85MM_NO_SILK"))
    )
    (comp (ref "JP1058")
      (value "M01PTH_SMD_3.25X0.85MM_NO_SILK")
      (footprint "eagle-import:1X01_SMD_3.25X0.85MM_NO_SILK")
      (libsource (lib "eagle-import") (part "M01PTH_SMD_3.25X0.85MM_NO_SILK"))
    )
    (comp (ref "JP1059")
      (value "M01PTH_SMD_3.25X0.85MM_NO_SILK")
      (footprint "eagle-import:1X01_SMD_3.25X0.85MM_NO_SILK")
      (libsource (lib "eagle-import") (part "M01PTH_SMD_3.25X0.85MM_NO_SILK"))
    )
    (comp (ref "JP1060")
      (value "M01PTH_SMD_3.25X0.85MM_NO_SILK")
      (footprint "eagle-import:1X01_SMD_3.25X0.85MM_NO_SILK")
      (libsource (lib "eagle-import") (part "M01PTH_SMD_3.25X0.85MM_NO_SILK"))
    )
    (comp (ref "JP1061")
      (value "M01PTH_SMD_3.25X0.85MM_NO_SILK")
      (footprint "eagle-import:1X01_SMD_3.25X0.85MM_NO_SILK")
      (libsource (lib "eagle-import") (part "M01PTH_SMD_3.25X0.85MM_NO_SILK"))
    )
    (comp (ref "JP1062")
      (value "M01PTH_SMD_3.25X0.85MM_NO_SILK")
      (footprint "eagle-import:1X01_SMD_3.25X0.85MM_NO_SILK")
      (libsource (lib "eagle-import") (part "M01PTH_SMD_3.25X0.85MM_NO_SILK"))
    )
    (comp (ref "JP1063")
      (value "M01PTH_SMD_3.25X0.85MM_NO_SILK")
      (footprint "eagle-import:1X01_SMD_3.25X0.85MM_NO_SILK")
      (libsource (lib "eagle-import") (part "M01PTH_SMD_3.25X0.85MM_NO_SILK"))
    )
    (comp (ref "JP1064")
      (value "M01PTH_SMD_3.25X0.85MM_NO_SILK")
      (footprint "eagle-import:1X01_SMD_3.25X0.85MM_NO_SILK")
      (libsource (lib "eagle-import") (part "M01PTH_SMD_3.25X0.85MM_NO_SILK"))
    )
    (comp (ref "JP1065")
      (value "M01PTH_SMD_3.25X0.85MM_NO_SILK")
      (footprint "eagle-import:1X01_SMD_3.25X0.85MM_NO_SILK")
      (libsource (lib "eagle-import") (part "M01PTH_SMD_3.25X0.85MM_NO_SILK"))
    )
    (comp (ref "JP1066")
      (value "M01PTH_SMD_3.25X0.85MM_NO_SILK")
      (footprint "eagle-import:1X01_SMD_3.25X0.85MM_NO_SILK")
      (libsource (lib "eagle-import") (part "M01PTH_SMD_3.25X0.85MM_NO_SILK"))
    )
    (comp (ref "JP1067")
      (value "M01PTH_SMD_3.25X0.85MM_NO_SILK")
      (footprint "eagle-import:1X01_SMD_3.25X0.85MM_NO_SILK")
      (libsource (lib "eagle-import") (part "M01PTH_SMD_3.25X0.85MM_NO_SILK"))
    )
    (comp (ref "JP1068")
      (value "M01PTH_SMD_3.25X0.85MM_NO_SILK")
      (footprint "eagle-import:1X01_SMD_3.25X0.85MM_NO_SILK")
      (libsource (lib "eagle-import") (part "M01PTH_SMD_3.25X0.85MM_NO_SILK"))
    )
    (comp (ref "JP1069")
      (value "M01PTH_SMD_3.25X0.85MM_NO_SILK")
      (footprint "eagle-import:1X01_SMD_3.25X0.85MM_NO_SILK")
      (libsource (lib "eagle-import") (part "M01PTH_SMD_3.25X0.85MM_NO_SILK"))
    )
    (comp (ref "JP1070")
      (value "M01PTH_SMD_3.25X0.85MM_NO_SILK")
      (footprint "eagle-import:1X01_SMD_3.25X0.85MM_NO_SILK")
      (libsource (lib "eagle-import") (part "M01PTH_SMD_3.25X0.85MM_NO_SILK"))
    )
    (comp (ref "JP1071")
      (value "M01PTH_SMD_3.25X0.85MM_NO_SILK")
      (footprint "eagle-import:1X01_SMD_3.25X0.85MM_NO_SILK")
      (libsource (lib "eagle-import") (part "M01PTH_SMD_3.25X0.85MM_NO_SILK"))
    )
    (comp (ref "JP1072")
      (value "M01PTH_SMD_3.25X0.85MM_NO_SILK")
      (footprint "eagle-import:1X01_SMD_3.25X0.85MM_NO_SILK")
      (libsource (lib "eagle-import") (part "M01PTH_SMD_3.25X0.85MM_NO_SILK"))
    )
    (comp (ref "JP1073")
      (value "M01PTH_SMD_3.25X0.85MM_NO_SILK")
      (footprint "eagle-import:1X01_SMD_3.25X0.85MM_NO_SILK")
      (libsource (lib "eagle-import") (part "M01PTH_SMD_3.25X0.85MM_NO_SILK"))
    )
    (comp (ref "JP1074")
      (value "M01PTH_SMD_3.25X0.85MM_NO_SILK")
      (footprint "eagle-import:1X01_SMD_3.25X0.85MM_NO_SILK")
      (libsource (lib "eagle-import") (part "M01PTH_SMD_3.25X0.85MM_NO_SILK"))
    )
    (comp (ref "JP1075")
      (value "M01PTH_SMD_3.25X0.85MM_NO_SILK")
      (footprint "eagle-import:1X01_SMD_3.25X0.85MM_NO_SILK")
      (libsource (lib "eagle-import") (part "M01PTH_SMD_3.25X0.85MM_NO_SILK"))
    )
    (comp (ref "JP1076")
      (value "M01PTH_SMD_3.25X0.85MM_NO_SILK")
      (footprint "eagle-import:1X01_SMD_3.25X0.85MM_NO_SILK")
      (libsource (lib "eagle-import") (part "M01PTH_SMD_3.25X0.85MM_NO_SILK"))
    )
    (comp (ref "JP1077")
      (value "M01PTH_SMD_3.25X0.85MM_NO_SILK")
      (footprint "eagle-import:1X01_SMD_3.25X0.85MM_NO_SILK")
      (libsource (lib "eagle-import") (part "M01PTH_SMD_3.25X0.85MM_NO_SILK"))
    )
    (comp (ref "JP1078")
      (value "M01PTH_SMD_3.25X0.85MM_NO_SILK")
      (footprint "eagle-import:1X01_SMD_3.25X0.85MM_NO_SILK")
      (libsource (lib "eagle-import") (part "M01PTH_SMD_3.25X0.85MM_NO_SILK"))
    )
    (comp (ref "JP1079")
      (value "M01PTH_SMD_3.25X0.85MM_NO_SILK")
      (footprint "eagle-import:1X01_SMD_3.25X0.85MM_NO_SILK")
      (libsource (lib "eagle-import") (part "M01PTH_SMD_3.25X0.85MM_NO_SILK"))
    )
    (comp (ref "JP1080")
      (value "M01PTH_SMD_3.25X0.85MM_NO_SILK")
      (footprint "eagle-import:1X01_SMD_3.25X0.85MM_NO_SILK")
      (libsource (lib "eagle-import") (part "M01PTH_SMD_3.25X0.85MM_NO_SILK"))
    )
    (comp (ref "JP1081")
      (value "M01PTH_SMD_3.25X0.85MM_NO_SILK")
      (footprint "eagle-import:1X01_SMD_3.25X0.85MM_NO_SILK")
      (libsource (lib "eagle-import") (part "M01PTH_SMD_3.25X0.85MM_NO_SILK"))
    )
    (comp (ref "JP1082")
      (value "M01PTH_SMD_3.25X0.85MM_NO_SILK")
      (footprint "eagle-import:1X01_SMD_3.25X0.85MM_NO_SILK")
      (libsource (lib "eagle-import") (part "M01PTH_SMD_3.25X0.85MM_NO_SILK"))
    )
    (comp (ref "JP1083")
      (value "M01PTH_SMD_3.25X0.85MM_NO_SILK")
      (footprint "eagle-import:1X01_SMD_3.25X0.85MM_NO_SILK")
      (libsource (lib "eagle-import") (part "M01PTH_SMD_3.25X0.85MM_NO_SILK"))
    )
    (comp (ref "JP1084")
      (value "M01PTH_SMD_3.25X0.85MM_NO_SILK")
      (footprint "eagle-import:1X01_SMD_3.25X0.85MM_NO_SILK")
      (libsource (lib "eagle-import") (part "M01PTH_SMD_3.25X0.85MM_NO_SILK"))
    )
    (comp (ref "JP1085")
      (value "M01PTH_SMD_3.25X0.85MM_NO_SILK")
      (footprint "eagle-import:1X01_SMD_3.25X0.85MM_NO_SILK")
      (libsource (lib "eagle-import") (part "M01PTH_SMD_3.25X0.85MM_NO_SILK"))
    )
    (comp (ref "JP1086")
      (value "M01PTH_SMD_3.25X0.85MM_NO_SILK")
      (footprint "eagle-import:1X01_SMD_3.25X0.85MM_NO_SILK")
      (libsource (lib "eagle-import") (part "M01PTH_SMD_3.25X0.85MM_NO_SILK"))
    )
    (comp (ref "JP1087")
      (value "M01PTH_SMD_3.25X0.85MM_NO_SILK")
      (footprint "eagle-import:1X01_SMD_3.25X0.85MM_NO_SILK")
      (libsource (lib "eagle-import") (part "M01PTH_SMD_3.25X0.85MM_NO_SILK"))
    )
    (comp (ref "JP1088")
      (value "M01PTH_SMD_3.25X0.85MM_NO_SILK")
      (footprint "eagle-import:1X01_SMD_3.25X0.85MM_NO_SILK")
      (libsource (lib "eagle-import") (part "M01PTH_SMD_3.25X0.85MM_NO_SILK"))
    )
    (comp (ref "JP1089")
      (value "M01PTH_SMD_3.25X0.85MM_NO_SILK")
      (footprint "eagle-import:1X01_SMD_3.25X0.85MM_NO_SILK")
      (libsource (lib "eagle-import") (part "M01PTH_SMD_3.25X0.85MM_NO_SILK"))
    )
    (comp (ref "JP1090")
      (value "M01PTH_SMD_3.25X0.85MM_NO_SILK")
      (footprint "eagle-import:1X01_SMD_3.25X0.85MM_NO_SILK")
      (libsource (lib "eagle-import") (part "M01PTH_SMD_3.25X0.85MM_NO_SILK"))
    )
    (comp (ref "JP1091")
      (value "M01PTH_SMD_3.25X0.85MM_NO_SILK")
      (footprint "eagle-import:1X01_SMD_3.25X0.85MM_NO_SILK")
      (libsource (lib "eagle-import") (part "M01PTH_SMD_3.25X0.85MM_NO_SILK"))
    )
    (comp (ref "JP1092")
      (value "M01PTH_SMD_3.25X0.85MM_NO_SILK")
      (footprint "eagle-import:1X01_SMD_3.25X0.85MM_NO_SILK")
      (libsource (lib "eagle-import") (part "M01PTH_SMD_3.25X0.85MM_NO_SILK"))
    )
    (comp (ref "JP1093")
      (value "M01PTH_SMD_3.25X0.85MM_NO_SILK")
      (footprint "eagle-import:1X01_SMD_3.25X0.85MM_NO_SILK")
      (libsource (lib "eagle-import") (part "M01PTH_SMD_3.25X0.85MM_NO_SILK"))
    )
    (comp (ref "JP1094")
      (value "M01PTH_SMD_3.25X0.85MM_NO_SILK")
      (footprint "eagle-import:1X01_SMD_3.25X0.85MM_NO_SILK")
      (libsource (lib "eagle-import") (part "M01PTH_SMD_3.25X0.85MM_NO_SILK"))
    )
    (comp (ref "JP1095")
      (value "M01PTH_SMD_3.25X0.85MM_NO_SILK")
      (footprint "eagle-import:1X01_SMD_3.25X0.85MM_NO_SILK")
      (libsource (lib "eagle-import") (part "M01PTH_SMD_3.25X0.85MM_NO_SILK"))
    )
    (comp (ref "JP1096")
      (value "M01PTH_SMD_3.25X0.85MM_NO_SILK")
      (footprint "eagle-import:1X01_SMD_3.25X0.85MM_NO_SILK")
      (libsource (lib "eagle-import") (part "M01PTH_SMD_3.25X0.85MM_NO_SILK"))
    )
    (comp (ref "JP1097")
      (value "M01PTH_SMD_3.25X0.85MM_NO_SILK")
      (footprint "eagle-import:1X01_SMD_3.25X0.85MM_NO_SILK")
      (libsource (lib "eagle-import") (part "M01PTH_SMD_3.25X0.85MM_NO_SILK"))
    )
    (comp (ref "JP1098")
      (value "M01PTH_SMD_3.25X0.85MM_NO_SILK")
      (footprint "eagle-import:1X01_SMD_3.25X0.85MM_NO_SILK")
      (libsource (lib "eagle-import") (part "M01PTH_SMD_3.25X0.85MM_NO_SILK"))
    )
    (comp (ref "JP1099")
      (value "M01PTH_SMD_3.25X0.85MM_NO_SILK")
      (footprint "eagle-import:1X01_SMD_3.25X0.85MM_NO_SILK")
      (libsource (lib "eagle-import") (part "M01PTH_SMD_3.25X0.85MM_NO_SILK"))
    )
    (comp (ref "JP1100")
      (value "M01PTH_SMD_3.25X0.85MM_NO_SILK")
      (footprint "eagle-import:1X01_SMD_3.25X0.85MM_NO_SILK")
      (libsource (lib "eagle-import") (part "M01PTH_SMD_3.25X0.85MM_NO_SILK"))
    )
    (comp (ref "JP1101")
      (value "M01PTH_SMD_3.25X0.85MM_NO_SILK")
      (footprint "eagle-import:1X01_SMD_3.25X0.85MM_NO_SILK")
      (libsource (lib "eagle-import") (part "M01PTH_SMD_3.25X0.85MM_NO_SILK"))
    )
    (comp (ref "JP1102")
      (value "M01PTH_SMD_3.25X0.85MM_NO_SILK")
      (footprint "eagle-import:1X01_SMD_3.25X0.85MM_NO_SILK")
      (libsource (lib "eagle-import") (part "M01PTH_SMD_3.25X0.85MM_NO_SILK"))
    )
    (comp (ref "JP1103")
      (value "M01PTH_SMD_3.25X0.85MM_NO_SILK")
      (footprint "eagle-import:1X01_SMD_3.25X0.85MM_NO_SILK")
      (libsource (lib "eagle-import") (part "M01PTH_SMD_3.25X0.85MM_NO_SILK"))
    )
    (comp (ref "JP1104")
      (value "M01PTH_SMD_3.25X0.85MM_NO_SILK")
      (footprint "eagle-import:1X01_SMD_3.25X0.85MM_NO_SILK")
      (libsource (lib "eagle-import") (part "M01PTH_SMD_3.25X0.85MM_NO_SILK"))
    )
    (comp (ref "JP1105")
      (value "M01PTH_SMD_3.25X0.85MM_NO_SILK")
      (footprint "eagle-import:1X01_SMD_3.25X0.85MM_NO_SILK")
      (libsource (lib "eagle-import") (part "M01PTH_SMD_3.25X0.85MM_NO_SILK"))
    )
    (comp (ref "JP1106")
      (value "M01PTH_SMD_3.25X0.85MM_NO_SILK")
      (footprint "eagle-import:1X01_SMD_3.25X0.85MM_NO_SILK")
      (libsource (lib "eagle-import") (part "M01PTH_SMD_3.25X0.85MM_NO_SILK"))
    )
    (comp (ref "JP1107")
      (value "M01PTH_SMD_3.25X0.85MM_NO_SILK")
      (footprint "eagle-import:1X01_SMD_3.25X0.85MM_NO_SILK")
      (libsource (lib "eagle-import") (part "M01PTH_SMD_3.25X0.85MM_NO_SILK"))
    )
    (comp (ref "JP1108")
      (value "M01PTH_SMD_3.25X0.85MM_NO_SILK")
      (footprint "eagle-import:1X01_SMD_3.25X0.85MM_NO_SILK")
      (libsource (lib "eagle-import") (part "M01PTH_SMD_3.25X0.85MM_NO_SILK"))
    )
    (comp (ref "JP1109")
      (value "M01PTH_SMD_3.25X0.85MM_NO_SILK")
      (footprint "eagle-import:1X01_SMD_3.25X0.85MM_NO_SILK")
      (libsource (lib "eagle-import") (part "M01PTH_SMD_3.25X0.85MM_NO_SILK"))
    )
    (comp (ref "JP1110")
      (value "M01PTH_SMD_3.25X0.85MM_NO_SILK")
      (footprint "eagle-import:1X01_SMD_3.25X0.85MM_NO_SILK")
      (libsource (lib "eagle-import") (part "M01PTH_SMD_3.25X0.85MM_NO_SILK"))
    )
    (comp (ref "JP1111")
      (value "M01PTH_SMD_3.25X0.85MM_NO_SILK")
      (footprint "eagle-import:1X01_SMD_3.25X0.85MM_NO_SILK")
      (libsource (lib "eagle-import") (part "M01PTH_SMD_3.25X0.85MM_NO_SILK"))
    )
    (comp (ref "JP1112")
      (value "M01PTH_SMD_3.25X0.85MM_NO_SILK")
      (footprint "eagle-import:1X01_SMD_3.25X0.85MM_NO_SILK")
      (libsource (lib "eagle-import") (part "M01PTH_SMD_3.25X0.85MM_NO_SILK"))
    )
    (comp (ref "JP1113")
      (value "M01PTH_SMD_3.25X0.85MM_NO_SILK")
      (footprint "eagle-import:1X01_SMD_3.25X0.85MM_NO_SILK")
      (libsource (lib "eagle-import") (part "M01PTH_SMD_3.25X0.85MM_NO_SILK"))
    )
    (comp (ref "JP1114")
      (value "M01PTH_SMD_3.25X0.85MM_NO_SILK")
      (footprint "eagle-import:1X01_SMD_3.25X0.85MM_NO_SILK")
      (libsource (lib "eagle-import") (part "M01PTH_SMD_3.25X0.85MM_NO_SILK"))
    )
    (comp (ref "JP1115")
      (value "M01PTH_SMD_3.25X0.85MM_NO_SILK")
      (footprint "eagle-import:1X01_SMD_3.25X0.85MM_NO_SILK")
      (libsource (lib "eagle-import") (part "M01PTH_SMD_3.25X0.85MM_NO_SILK"))
    )
    (comp (ref "JP1116")
      (value "M01PTH_SMD_3.25X0.85MM_NO_SILK")
      (footprint "eagle-import:1X01_SMD_3.25X0.85MM_NO_SILK")
      (libsource (lib "eagle-import") (part "M01PTH_SMD_3.25X0.85MM_NO_SILK"))
    )
    (comp (ref "JP1117")
      (value "M01PTH_SMD_3.25X0.85MM_NO_SILK")
      (footprint "eagle-import:1X01_SMD_3.25X0.85MM_NO_SILK")
      (libsource (lib "eagle-import") (part "M01PTH_SMD_3.25X0.85MM_NO_SILK"))
    )
    (comp (ref "JP1118")
      (value "M01PTH_SMD_3.25X0.85MM_NO_SILK")
      (footprint "eagle-import:1X01_SMD_3.25X0.85MM_NO_SILK")
      (libsource (lib "eagle-import") (part "M01PTH_SMD_3.25X0.85MM_NO_SILK"))
    )
    (comp (ref "JP1119")
      (value "M01PTH_SMD_3.25X0.85MM_NO_SILK")
      (footprint "eagle-import:1X01_SMD_3.25X0.85MM_NO_SILK")
      (libsource (lib "eagle-import") (part "M01PTH_SMD_3.25X0.85MM_NO_SILK"))
    )
    (comp (ref "JP1120")
      (value "M01PTH_SMD_3.25X0.85MM_NO_SILK")
      (footprint "eagle-import:1X01_SMD_3.25X0.85MM_NO_SILK")
      (libsource (lib "eagle-import") (part "M01PTH_SMD_3.25X0.85MM_NO_SILK"))
    )
    (comp (ref "JP1121")
      (value "M01PTH_SMD_3.25X0.85MM_NO_SILK")
      (footprint "eagle-import:1X01_SMD_3.25X0.85MM_NO_SILK")
      (libsource (lib "eagle-import") (part "M01PTH_SMD_3.25X0.85MM_NO_SILK"))
    )
    (comp (ref "JP1122")
      (value "M01PTH_SMD_3.25X0.85MM_NO_SILK")
      (footprint "eagle-import:1X01_SMD_3.25X0.85MM_NO_SILK")
      (libsource (lib "eagle-import") (part "M01PTH_SMD_3.25X0.85MM_NO_SILK"))
    )
    (comp (ref "JP1123")
      (value "M01PTH_SMD_3.25X0.85MM_NO_SILK")
      (footprint "eagle-import:1X01_SMD_3.25X0.85MM_NO_SILK")
      (libsource (lib "eagle-import") (part "M01PTH_SMD_3.25X0.85MM_NO_SILK"))
    )
    (comp (ref "JP1124")
      (value "M01PTH_SMD_3.25X0.85MM_NO_SILK")
      (footprint "eagle-import:1X01_SMD_3.25X0.85MM_NO_SILK")
      (libsource (lib "eagle-import") (part "M01PTH_SMD_3.25X0.85MM_NO_SILK"))
    )
    (comp (ref "JP1125")
      (value "M01PTH_SMD_3.25X0.85MM_NO_SILK")
      (footprint "eagle-import:1X01_SMD_3.25X0.85MM_NO_SILK")
      (libsource (lib "eagle-import") (part "M01PTH_SMD_3.25X0.85MM_NO_SILK"))
    )
    (comp (ref "JP1126")
      (value "M01PTH_SMD_3.25X0.85MM_NO_SILK")
      (footprint "eagle-import:1X01_SMD_3.25X0.85MM_NO_SILK")
      (libsource (lib "eagle-import") (part "M01PTH_SMD_3.25X0.85MM_NO_SILK"))
    )
    (comp (ref "JP1127")
      (value "M01PTH_SMD_3.25X0.85MM_NO_SILK")
      (footprint "eagle-import:1X01_SMD_3.25X0.85MM_NO_SILK")
      (libsource (lib "eagle-import") (part "M01PTH_SMD_3.25X0.85MM_NO_SILK"))
    )
    (comp (ref "JP1128")
      (value "M01PTH_SMD_3.25X0.85MM_NO_SILK")
      (footprint "eagle-import:1X01_SMD_3.25X0.85MM_NO_SILK")
      (libsource (lib "eagle-import") (part "M01PTH_SMD_3.25X0.85MM_NO_SILK"))
    )
    (comp (ref "JP1129")
      (value "M01PTH_SMD_3.25X0.85MM_NO_SILK")
      (footprint "eagle-import:1X01_SMD_3.25X0.85MM_NO_SILK")
      (libsource (lib "eagle-import") (part "M01PTH_SMD_3.25X0.85MM_NO_SILK"))
    )
    (comp (ref "JP1130")
      (value "M01PTH_SMD_3.25X0.85MM_NO_SILK")
      (footprint "eagle-import:1X01_SMD_3.25X0.85MM_NO_SILK")
      (libsource (lib "eagle-import") (part "M01PTH_SMD_3.25X0.85MM_NO_SILK"))
    )
    (comp (ref "JP1131")
      (value "M01PTH_SMD_3.25X0.85MM_NO_SILK")
      (footprint "eagle-import:1X01_SMD_3.25X0.85MM_NO_SILK")
      (libsource (lib "eagle-import") (part "M01PTH_SMD_3.25X0.85MM_NO_SILK"))
    )
    (comp (ref "JP1132")
      (value "M01PTH_SMD_3.25X0.85MM_NO_SILK")
      (footprint "eagle-import:1X01_SMD_3.25X0.85MM_NO_SILK")
      (libsource (lib "eagle-import") (part "M01PTH_SMD_3.25X0.85MM_NO_SILK"))
    )
    (comp (ref "JP1133")
      (value "M01PTH_SMD_3.25X0.85MM_NO_SILK")
      (footprint "eagle-import:1X01_SMD_3.25X0.85MM_NO_SILK")
      (libsource (lib "eagle-import") (part "M01PTH_SMD_3.25X0.85MM_NO_SILK"))
    )
    (comp (ref "JP1134")
      (value "M01PTH_SMD_3.25X0.85MM_NO_SILK")
      (footprint "eagle-import:1X01_SMD_3.25X0.85MM_NO_SILK")
      (libsource (lib "eagle-import") (part "M01PTH_SMD_3.25X0.85MM_NO_SILK"))
    )
    (comp (ref "JP1135")
      (value "M01PTH_SMD_3.25X0.85MM_NO_SILK")
      (footprint "eagle-import:1X01_SMD_3.25X0.85MM_NO_SILK")
      (libsource (lib "eagle-import") (part "M01PTH_SMD_3.25X0.85MM_NO_SILK"))
    )
    (comp (ref "JP1136")
      (value "M01PTH_SMD_3.25X0.85MM_NO_SILK")
      (footprint "eagle-import:1X01_SMD_3.25X0.85MM_NO_SILK")
      (libsource (lib "eagle-import") (part "M01PTH_SMD_3.25X0.85MM_NO_SILK"))
    )
    (comp (ref "JP1137")
      (value "M01PTH_SMD_3.25X0.85MM_NO_SILK")
      (footprint "eagle-import:1X01_SMD_3.25X0.85MM_NO_SILK")
      (libsource (lib "eagle-import") (part "M01PTH_SMD_3.25X0.85MM_NO_SILK"))
    )
    (comp (ref "JP1138")
      (value "M01PTH_SMD_3.25X0.85MM_NO_SILK")
      (footprint "eagle-import:1X01_SMD_3.25X0.85MM_NO_SILK")
      (libsource (lib "eagle-import") (part "M01PTH_SMD_3.25X0.85MM_NO_SILK"))
    )
    (comp (ref "JP1139")
      (value "M01PTH_SMD_3.25X0.85MM_NO_SILK")
      (footprint "eagle-import:1X01_SMD_3.25X0.85MM_NO_SILK")
      (libsource (lib "eagle-import") (part "M01PTH_SMD_3.25X0.85MM_NO_SILK"))
    )
    (comp (ref "JP1140")
      (value "M01PTH_SMD_3.25X0.85MM_NO_SILK")
      (footprint "eagle-import:1X01_SMD_3.25X0.85MM_NO_SILK")
      (libsource (lib "eagle-import") (part "M01PTH_SMD_3.25X0.85MM_NO_SILK"))
    )
    (comp (ref "JP1141")
      (value "M01PTH_SMD_3.25X0.85MM_NO_SILK")
      (footprint "eagle-import:1X01_SMD_3.25X0.85MM_NO_SILK")
      (libsource (lib "eagle-import") (part "M01PTH_SMD_3.25X0.85MM_NO_SILK"))
    )
    (comp (ref "JP1142")
      (value "M01PTH_SMD_3.25X0.85MM_NO_SILK")
      (footprint "eagle-import:1X01_SMD_3.25X0.85MM_NO_SILK")
      (libsource (lib "eagle-import") (part "M01PTH_SMD_3.25X0.85MM_NO_SILK"))
    )
    (comp (ref "JP1143")
      (value "M01PTH_SMD_3.25X0.85MM_NO_SILK")
      (footprint "eagle-import:1X01_SMD_3.25X0.85MM_NO_SILK")
      (libsource (lib "eagle-import") (part "M01PTH_SMD_3.25X0.85MM_NO_SILK"))
    )
    (comp (ref "JP1144")
      (value "M01PTH_SMD_3.25X0.85MM_NO_SILK")
      (footprint "eagle-import:1X01_SMD_3.25X0.85MM_NO_SILK")
      (libsource (lib "eagle-import") (part "M01PTH_SMD_3.25X0.85MM_NO_SILK"))
    )
    (comp (ref "JP1145")
      (value "M01PTH_SMD_3.25X0.85MM_NO_SILK")
      (footprint "eagle-import:1X01_SMD_3.25X0.85MM_NO_SILK")
      (libsource (lib "eagle-import") (part "M01PTH_SMD_3.25X0.85MM_NO_SILK"))
    )
    (comp (ref "JP1146")
      (value "M01PTH_SMD_3.25X0.85MM_NO_SILK")
      (footprint "eagle-import:1X01_SMD_3.25X0.85MM_NO_SILK")
      (libsource (lib "eagle-import") (part "M01PTH_SMD_3.25X0.85MM_NO_SILK"))
    )
    (comp (ref "JP1147")
      (value "M01PTH_SMD_3.25X0.85MM_NO_SILK")
      (footprint "eagle-import:1X01_SMD_3.25X0.85MM_NO_SILK")
      (libsource (lib "eagle-import") (part "M01PTH_SMD_3.25X0.85MM_NO_SILK"))
    )
    (comp (ref "JP1148")
      (value "M01PTH_SMD_3.25X0.85MM_NO_SILK")
      (footprint "eagle-import:1X01_SMD_3.25X0.85MM_NO_SILK")
      (libsource (lib "eagle-import") (part "M01PTH_SMD_3.25X0.85MM_NO_SILK"))
    )
    (comp (ref "JP1149")
      (value "M01PTH_SMD_3.25X0.85MM_NO_SILK")
      (footprint "eagle-import:1X01_SMD_3.25X0.85MM_NO_SILK")
      (libsource (lib "eagle-import") (part "M01PTH_SMD_3.25X0.85MM_NO_SILK"))
    )
    (comp (ref "JP1150")
      (value "M01PTH_SMD_3.25X0.85MM_NO_SILK")
      (footprint "eagle-import:1X01_SMD_3.25X0.85MM_NO_SILK")
      (libsource (lib "eagle-import") (part "M01PTH_SMD_3.25X0.85MM_NO_SILK"))
    )
    (comp (ref "JP1151")
      (value "M01PTH_SMD_3.25X0.85MM_NO_SILK")
      (footprint "eagle-import:1X01_SMD_3.25X0.85MM_NO_SILK")
      (libsource (lib "eagle-import") (part "M01PTH_SMD_3.25X0.85MM_NO_SILK"))
    )
    (comp (ref "JP1152")
      (value "M01PTH_SMD_3.25X0.85MM_NO_SILK")
      (footprint "eagle-import:1X01_SMD_3.25X0.85MM_NO_SILK")
      (libsource (lib "eagle-import") (part "M01PTH_SMD_3.25X0.85MM_NO_SILK"))
    )
    (comp (ref "JP1153")
      (value "M01PTH_SMD_3.25X0.85MM_NO_SILK")
      (footprint "eagle-import:1X01_SMD_3.25X0.85MM_NO_SILK")
      (libsource (lib "eagle-import") (part "M01PTH_SMD_3.25X0.85MM_NO_SILK"))
    )
    (comp (ref "JP1154")
      (value "M01PTH_SMD_3.25X0.85MM_NO_SILK")
      (footprint "eagle-import:1X01_SMD_3.25X0.85MM_NO_SILK")
      (libsource (lib "eagle-import") (part "M01PTH_SMD_3.25X0.85MM_NO_SILK"))
    )
    (comp (ref "JP1155")
      (value "M01PTH_SMD_3.25X0.85MM_NO_SILK")
      (footprint "eagle-import:1X01_SMD_3.25X0.85MM_NO_SILK")
      (libsource (lib "eagle-import") (part "M01PTH_SMD_3.25X0.85MM_NO_SILK"))
    )
    (comp (ref "JP1156")
      (value "M01PTH_SMD_3.25X0.85MM_NO_SILK")
      (footprint "eagle-import:1X01_SMD_3.25X0.85MM_NO_SILK")
      (libsource (lib "eagle-import") (part "M01PTH_SMD_3.25X0.85MM_NO_SILK"))
    )
    (comp (ref "JP1157")
      (value "M01PTH_SMD_3.25X0.85MM_NO_SILK")
      (footprint "eagle-import:1X01_SMD_3.25X0.85MM_NO_SILK")
      (libsource (lib "eagle-import") (part "M01PTH_SMD_3.25X0.85MM_NO_SILK"))
    )
    (comp (ref "JP1158")
      (value "M01PTH_SMD_3.25X0.85MM_NO_SILK")
      (footprint "eagle-import:1X01_SMD_3.25X0.85MM_NO_SILK")
      (libsource (lib "eagle-import") (part "M01PTH_SMD_3.25X0.85MM_NO_SILK"))
    )
    (comp (ref "JP1159")
      (value "M01PTH_SMD_3.25X0.85MM_NO_SILK")
      (footprint "eagle-import:1X01_SMD_3.25X0.85MM_NO_SILK")
      (libsource (lib "eagle-import") (part "M01PTH_SMD_3.25X0.85MM_NO_SILK"))
    )
    (comp (ref "JP1160")
      (value "M01PTH_SMD_3.25X0.85MM_NO_SILK")
      (footprint "eagle-import:1X01_SMD_3.25X0.85MM_NO_SILK")
      (libsource (lib "eagle-import") (part "M01PTH_SMD_3.25X0.85MM_NO_SILK"))
    )
    (comp (ref "JP1161")
      (value "M01PTH_SMD_3.25X0.85MM_NO_SILK")
      (footprint "eagle-import:1X01_SMD_3.25X0.85MM_NO_SILK")
      (libsource (lib "eagle-import") (part "M01PTH_SMD_3.25X0.85MM_NO_SILK"))
    )
    (comp (ref "JP1162")
      (value "M01PTH_SMD_3.25X0.85MM_NO_SILK")
      (footprint "eagle-import:1X01_SMD_3.25X0.85MM_NO_SILK")
      (libsource (lib "eagle-import") (part "M01PTH_SMD_3.25X0.85MM_NO_SILK"))
    )
    (comp (ref "JP1163")
      (value "M01PTH_SMD_3.25X0.85MM_NO_SILK")
      (footprint "eagle-import:1X01_SMD_3.25X0.85MM_NO_SILK")
      (libsource (lib "eagle-import") (part "M01PTH_SMD_3.25X0.85MM_NO_SILK"))
    )
    (comp (ref "JP1164")
      (value "M01PTH_SMD_3.25X0.85MM_NO_SILK")
      (footprint "eagle-import:1X01_SMD_3.25X0.85MM_NO_SILK")
      (libsource (lib "eagle-import") (part "M01PTH_SMD_3.25X0.85MM_NO_SILK"))
    )
    (comp (ref "JP1165")
      (value "M01PTH_SMD_3.25X0.85MM_NO_SILK")
      (footprint "eagle-import:1X01_SMD_3.25X0.85MM_NO_SILK")
      (libsource (lib "eagle-import") (part "M01PTH_SMD_3.25X0.85MM_NO_SILK"))
    )
    (comp (ref "JP1166")
      (value "M01PTH_SMD_3.25X0.85MM_NO_SILK")
      (footprint "eagle-import:1X01_SMD_3.25X0.85MM_NO_SILK")
      (libsource (lib "eagle-import") (part "M01PTH_SMD_3.25X0.85MM_NO_SILK"))
    )
    (comp (ref "JP1167")
      (value "M01PTH_SMD_3.25X0.85MM_NO_SILK")
      (footprint "eagle-import:1X01_SMD_3.25X0.85MM_NO_SILK")
      (libsource (lib "eagle-import") (part "M01PTH_SMD_3.25X0.85MM_NO_SILK"))
    )
    (comp (ref "JP1168")
      (value "M01PTH_SMD_3.25X0.85MM_NO_SILK")
      (footprint "eagle-import:1X01_SMD_3.25X0.85MM_NO_SILK")
      (libsource (lib "eagle-import") (part "M01PTH_SMD_3.25X0.85MM_NO_SILK"))
    )
    (comp (ref "JP1169")
      (value "M01PTH_SMD_3.25X0.85MM_NO_SILK")
      (footprint "eagle-import:1X01_SMD_3.25X0.85MM_NO_SILK")
      (libsource (lib "eagle-import") (part "M01PTH_SMD_3.25X0.85MM_NO_SILK"))
    )
    (comp (ref "JP1170")
      (value "M01PTH_SMD_3.25X0.85MM_NO_SILK")
      (footprint "eagle-import:1X01_SMD_3.25X0.85MM_NO_SILK")
      (libsource (lib "eagle-import") (part "M01PTH_SMD_3.25X0.85MM_NO_SILK"))
    )
    (comp (ref "JP1171")
      (value "M01PTH_SMD_3.25X0.85MM_NO_SILK")
      (footprint "eagle-import:1X01_SMD_3.25X0.85MM_NO_SILK")
      (libsource (lib "eagle-import") (part "M01PTH_SMD_3.25X0.85MM_NO_SILK"))
    )
    (comp (ref "JP1172")
      (value "M01PTH_SMD_3.25X0.85MM_NO_SILK")
      (footprint "eagle-import:1X01_SMD_3.25X0.85MM_NO_SILK")
      (libsource (lib "eagle-import") (part "M01PTH_SMD_3.25X0.85MM_NO_SILK"))
    )
    (comp (ref "JP1173")
      (value "M01PTH_SMD_3.25X0.85MM_NO_SILK")
      (footprint "eagle-import:1X01_SMD_3.25X0.85MM_NO_SILK")
      (libsource (lib "eagle-import") (part "M01PTH_SMD_3.25X0.85MM_NO_SILK"))
    )
    (comp (ref "JP1174")
      (value "M01PTH_SMD_3.25X0.85MM_NO_SILK")
      (footprint "eagle-import:1X01_SMD_3.25X0.85MM_NO_SILK")
      (libsource (lib "eagle-import") (part "M01PTH_SMD_3.25X0.85MM_NO_SILK"))
    )
    (comp (ref "JP1175")
      (value "M01PTH_SMD_3.25X0.85MM_NO_SILK")
      (footprint "eagle-import:1X01_SMD_3.25X0.85MM_NO_SILK")
      (libsource (lib "eagle-import") (part "M01PTH_SMD_3.25X0.85MM_NO_SILK"))
    )
    (comp (ref "JP1176")
      (value "M01PTH_SMD_3.25X0.85MM_NO_SILK")
      (footprint "eagle-import:1X01_SMD_3.25X0.85MM_NO_SILK")
      (libsource (lib "eagle-import") (part "M01PTH_SMD_3.25X0.85MM_NO_SILK"))
    )
    (comp (ref "JP1177")
      (value "M01PTH_SMD_3.25X0.85MM_NO_SILK")
      (footprint "eagle-import:1X01_SMD_3.25X0.85MM_NO_SILK")
      (libsource (lib "eagle-import") (part "M01PTH_SMD_3.25X0.85MM_NO_SILK"))
    )
    (comp (ref "JP1178")
      (value "M01PTH_SMD_3.25X0.85MM_NO_SILK")
      (footprint "eagle-import:1X01_SMD_3.25X0.85MM_NO_SILK")
      (libsource (lib "eagle-import") (part "M01PTH_SMD_3.25X0.85MM_NO_SILK"))
    )
    (comp (ref "JP1179")
      (value "M01PTH_SMD_3.25X0.85MM_NO_SILK")
      (footprint "eagle-import:1X01_SMD_3.25X0.85MM_NO_SILK")
      (libsource (lib "eagle-import") (part "M01PTH_SMD_3.25X0.85MM_NO_SILK"))
    )
    (comp (ref "JP1180")
      (value "M01PTH_SMD_3.25X0.85MM_NO_SILK")
      (footprint "eagle-import:1X01_SMD_3.25X0.85MM_NO_SILK")
      (libsource (lib "eagle-import") (part "M01PTH_SMD_3.25X0.85MM_NO_SILK"))
    )
    (comp (ref "JP1181")
      (value "M01PTH_SMD_3.25X0.85MM_NO_SILK")
      (footprint "eagle-import:1X01_SMD_3.25X0.85MM_NO_SILK")
      (libsource (lib "eagle-import") (part "M01PTH_SMD_3.25X0.85MM_NO_SILK"))
    )
    (comp (ref "JP1182")
      (value "M01PTH_SMD_3.25X0.85MM_NO_SILK")
      (footprint "eagle-import:1X01_SMD_3.25X0.85MM_NO_SILK")
      (libsource (lib "eagle-import") (part "M01PTH_SMD_3.25X0.85MM_NO_SILK"))
    )
    (comp (ref "JP1183")
      (value "M01PTH_SMD_3.25X0.85MM_NO_SILK")
      (footprint "eagle-import:1X01_SMD_3.25X0.85MM_NO_SILK")
      (libsource (lib "eagle-import") (part "M01PTH_SMD_3.25X0.85MM_NO_SILK"))
    )
    (comp (ref "JP1184")
      (value "M01PTH_SMD_3.25X0.85MM_NO_SILK")
      (footprint "eagle-import:1X01_SMD_3.25X0.85MM_NO_SILK")
      (libsource (lib "eagle-import") (part "M01PTH_SMD_3.25X0.85MM_NO_SILK"))
    )
    (comp (ref "JP1185")
      (value "M01PTH_SMD_3.25X0.85MM_NO_SILK")
      (footprint "eagle-import:1X01_SMD_3.25X0.85MM_NO_SILK")
      (libsource (lib "eagle-import") (part "M01PTH_SMD_3.25X0.85MM_NO_SILK"))
    )
    (comp (ref "JP1186")
      (value "M01PTH_SMD_3.25X0.85MM_NO_SILK")
      (footprint "eagle-import:1X01_SMD_3.25X0.85MM_NO_SILK")
      (libsource (lib "eagle-import") (part "M01PTH_SMD_3.25X0.85MM_NO_SILK"))
    )
    (comp (ref "JP1187")
      (value "M01PTH_SMD_3.25X0.85MM_NO_SILK")
      (footprint "eagle-import:1X01_SMD_3.25X0.85MM_NO_SILK")
      (libsource (lib "eagle-import") (part "M01PTH_SMD_3.25X0.85MM_NO_SILK"))
    )
    (comp (ref "JP1188")
      (value "M01PTH_SMD_3.25X0.85MM_NO_SILK")
      (footprint "eagle-import:1X01_SMD_3.25X0.85MM_NO_SILK")
      (libsource (lib "eagle-import") (part "M01PTH_SMD_3.25X0.85MM_NO_SILK"))
    )
    (comp (ref "JP1189")
      (value "M01PTH_SMD_3.25X0.85MM_NO_SILK")
      (footprint "eagle-import:1X01_SMD_3.25X0.85MM_NO_SILK")
      (libsource (lib "eagle-import") (part "M01PTH_SMD_3.25X0.85MM_NO_SILK"))
    )
    (comp (ref "JP1190")
      (value "M01PTH_SMD_3.25X0.85MM_NO_SILK")
      (footprint "eagle-import:1X01_SMD_3.25X0.85MM_NO_SILK")
      (libsource (lib "eagle-import") (part "M01PTH_SMD_3.25X0.85MM_NO_SILK"))
    )
    (comp (ref "JP1191")
      (value "M01PTH_SMD_3.25X0.85MM_NO_SILK")
      (footprint "eagle-import:1X01_SMD_3.25X0.85MM_NO_SILK")
      (libsource (lib "eagle-import") (part "M01PTH_SMD_3.25X0.85MM_NO_SILK"))
    )
    (comp (ref "JP1192")
      (value "M01PTH_SMD_3.25X0.85MM_NO_SILK")
      (footprint "eagle-import:1X01_SMD_3.25X0.85MM_NO_SILK")
      (libsource (lib "eagle-import") (part "M01PTH_SMD_3.25X0.85MM_NO_SILK"))
    )
    (comp (ref "JP1193")
      (value "M01PTH_SMD_3.25X0.85MM_NO_SILK")
      (footprint "eagle-import:1X01_SMD_3.25X0.85MM_NO_SILK")
      (libsource (lib "eagle-import") (part "M01PTH_SMD_3.25X0.85MM_NO_SILK"))
    )
    (comp (ref "JP1194")
      (value "M01PTH_SMD_3.25X0.85MM_NO_SILK")
      (footprint "eagle-import:1X01_SMD_3.25X0.85MM_NO_SILK")
      (libsource (lib "eagle-import") (part "M01PTH_SMD_3.25X0.85MM_NO_SILK"))
    )
    (comp (ref "JP1195")
      (value "M01PTH_SMD_3.25X0.85MM_NO_SILK")
      (footprint "eagle-import:1X01_SMD_3.25X0.85MM_NO_SILK")
      (libsource (lib "eagle-import") (part "M01PTH_SMD_3.25X0.85MM_NO_SILK"))
    )
    (comp (ref "JP1196")
      (value "M01PTH_SMD_3.25X0.85MM_NO_SILK")
      (footprint "eagle-import:1X01_SMD_3.25X0.85MM_NO_SILK")
      (libsource (lib "eagle-import") (part "M01PTH_SMD_3.25X0.85MM_NO_SILK"))
    )
    (comp (ref "JP1197")
      (value "M01PTH_SMD_3.25X0.85MM_NO_SILK")
      (footprint "eagle-import:1X01_SMD_3.25X0.85MM_NO_SILK")
      (libsource (lib "eagle-import") (part "M01PTH_SMD_3.25X0.85MM_NO_SILK"))
    )
    (comp (ref "JP1198")
      (value "M01PTH_SMD_3.25X0.85MM_NO_SILK")
      (footprint "eagle-import:1X01_SMD_3.25X0.85MM_NO_SILK")
      (libsource (lib "eagle-import") (part "M01PTH_SMD_3.25X0.85MM_NO_SILK"))
    )
    (comp (ref "JP1199")
      (value "M01PTH_SMD_3.25X0.85MM_NO_SILK")
      (footprint "eagle-import:1X01_SMD_3.25X0.85MM_NO_SILK")
      (libsource (lib "eagle-import") (part "M01PTH_SMD_3.25X0.85MM_NO_SILK"))
    )
    (comp (ref "JP1200")
      (value "M01PTH_SMD_3.25X0.85MM_NO_SILK")
      (footprint "eagle-import:1X01_SMD_3.25X0.85MM_NO_SILK")
      (libsource (lib "eagle-import") (part "M01PTH_SMD_3.25X0.85MM_NO_SILK"))
    )
  )
  (nets
    (net (code "1") (name "/0_1439897169") (class "Default")
      (node (ref "JP301") (pin "P$3") (pinfunction "1_P$3") (pintype "passive"))
      (node (ref "JP841") (pin "P$3") (pinfunction "1_P$3") (pintype "passive"))
    )
    (net (code "2") (name "/0_1439897178") (class "Default")
      (node (ref "JP311") (pin "P$3") (pinfunction "1_P$3") (pintype "passive"))
      (node (ref "JP843") (pin "P$3") (pinfunction "1_P$3") (pintype "passive"))
    )
    (net (code "3") (name "/0_1439897188") (class "Default")
      (node (ref "JP321") (pin "P$3") (pinfunction "1_P$3") (pintype "passive"))
      (node (ref "JP845") (pin "P$3") (pinfunction "1_P$3") (pintype "passive"))
    )
    (net (code "4") (name "/0_1439897194") (class "Default")
      (node (ref "JP310") (pin "P$3") (pinfunction "1_P$3") (pintype "passive"))
      (node (ref "JP781") (pin "P$3") (pinfunction "1_P$3") (pintype "passive"))
    )
    (net (code "5") (name "/0_1439897209") (class "Default")
      (node (ref "JP320") (pin "P$3") (pinfunction "1_P$3") (pintype "passive"))
      (node (ref "JP783") (pin "P$3") (pinfunction "1_P$3") (pintype "passive"))
    )
    (net (code "6") (name "/0_1439897217") (class "Default")
      (node (ref "JP330") (pin "P$3") (pinfunction "1_P$3") (pintype "passive"))
      (node (ref "JP785") (pin "P$3") (pinfunction "1_P$3") (pintype "passive"))
    )
    (net (code "7") (name "/0_1439897230") (class "Default")
      (node (ref "JP340") (pin "P$3") (pinfunction "1_P$3") (pintype "passive"))
      (node (ref "JP787") (pin "P$3") (pinfunction "1_P$3") (pintype "passive"))
    )
    (net (code "8") (name "/0_1439897238") (class "Default")
      (node (ref "JP350") (pin "P$3") (pinfunction "1_P$3") (pintype "passive"))
      (node (ref "JP789") (pin "P$3") (pinfunction "1_P$3") (pintype "passive"))
    )
    (net (code "9") (name "/0_1439897247") (class "Default")
      (node (ref "JP360") (pin "P$3") (pinfunction "1_P$3") (pintype "passive"))
      (node (ref "JP791") (pin "P$3") (pinfunction "1_P$3") (pintype "passive"))
    )
    (net (code "10") (name "/0_1439897254") (class "Default")
      (node (ref "JP370") (pin "P$3") (pinfunction "1_P$3") (pintype "passive"))
      (node (ref "JP793") (pin "P$3") (pinfunction "1_P$3") (pintype "passive"))
    )
    (net (code "11") (name "/0_1439897261") (class "Default")
      (node (ref "JP380") (pin "P$3") (pinfunction "1_P$3") (pintype "passive"))
      (node (ref "JP795") (pin "P$3") (pinfunction "1_P$3") (pintype "passive"))
    )
    (net (code "12") (name "/0_1439897267") (class "Default")
      (node (ref "JP390") (pin "P$3") (pinfunction "1_P$3") (pintype "passive"))
      (node (ref "JP797") (pin "P$3") (pinfunction "1_P$3") (pintype "passive"))
    )
    (net (code "13") (name "/0_1439897281") (class "Default")
      (node (ref "JP600") (pin "P$3") (pinfunction "1_P$3") (pintype "passive"))
      (node (ref "JP839") (pin "P$3") (pinfunction "1_P$3") (pintype "passive"))
    )
    (net (code "14") (name "/0_1439897288") (class "Default")
      (node (ref "JP590") (pin "P$3") (pinfunction "1_P$3") (pintype "passive"))
      (node (ref "JP837") (pin "P$3") (pinfunction "1_P$3") (pintype "passive"))
    )
    (net (code "15") (name "/0_1439897294") (class "Default")
      (node (ref "JP580") (pin "P$3") (pinfunction "1_P$3") (pintype "passive"))
      (node (ref "JP835") (pin "P$3") (pinfunction "1_P$3") (pintype "passive"))
    )
    (net (code "16") (name "/0_1439897300") (class "Default")
      (node (ref "JP591") (pin "P$3") (pinfunction "1_P$3") (pintype "passive"))
      (node (ref "JP899") (pin "P$3") (pinfunction "1_P$3") (pintype "passive"))
    )
    (net (code "17") (name "/0_1439897307") (class "Default")
      (node (ref "JP581") (pin "P$3") (pinfunction "1_P$3") (pintype "passive"))
      (node (ref "JP897") (pin "P$3") (pinfunction "1_P$3") (pintype "passive"))
    )
    (net (code "18") (name "/0_1439897312") (class "Default")
      (node (ref "JP571") (pin "P$3") (pinfunction "1_P$3") (pintype "passive"))
      (node (ref "JP895") (pin "P$3") (pinfunction "1_P$3") (pintype "passive"))
    )
    (net (code "19") (name "/0_1439897321") (class "Default")
      (node (ref "JP561") (pin "P$3") (pinfunction "1_P$3") (pintype "passive"))
      (node (ref "JP893") (pin "P$3") (pinfunction "1_P$3") (pintype "passive"))
    )
    (net (code "20") (name "/0_1439897329") (class "Default")
      (node (ref "JP551") (pin "P$3") (pinfunction "1_P$3") (pintype "passive"))
      (node (ref "JP891") (pin "P$3") (pinfunction "1_P$3") (pintype "passive"))
    )
    (net (code "21") (name "/0_1439897335") (class "Default")
      (node (ref "JP541") (pin "P$3") (pinfunction "1_P$3") (pintype "passive"))
      (node (ref "JP889") (pin "P$3") (pinfunction "1_P$3") (pintype "passive"))
    )
    (net (code "22") (name "/0_1439897341") (class "Default")
      (node (ref "JP531") (pin "P$3") (pinfunction "1_P$3") (pintype "passive"))
      (node (ref "JP887") (pin "P$3") (pinfunction "1_P$3") (pintype "passive"))
    )
    (net (code "23") (name "/0_1439897349") (class "Default")
      (node (ref "JP521") (pin "P$3") (pinfunction "1_P$3") (pintype "passive"))
      (node (ref "JP885") (pin "P$3") (pinfunction "1_P$3") (pintype "passive"))
    )
    (net (code "24") (name "/0_1439897354") (class "Default")
      (node (ref "JP570") (pin "P$3") (pinfunction "1_P$3") (pintype "passive"))
      (node (ref "JP833") (pin "P$3") (pinfunction "1_P$3") (pintype "passive"))
    )
    (net (code "25") (name "/0_1439897362") (class "Default")
      (node (ref "JP560") (pin "P$3") (pinfunction "1_P$3") (pintype "passive"))
      (node (ref "JP831") (pin "P$3") (pinfunction "1_P$3") (pintype "passive"))
    )
    (net (code "26") (name "/0_1439897369") (class "Default")
      (node (ref "JP550") (pin "P$3") (pinfunction "1_P$3") (pintype "passive"))
      (node (ref "JP829") (pin "P$3") (pinfunction "1_P$3") (pintype "passive"))
    )
    (net (code "27") (name "/0_1439897383") (class "Default")
      (node (ref "JP540") (pin "P$3") (pinfunction "1_P$3") (pintype "passive"))
      (node (ref "JP827") (pin "P$3") (pinfunction "1_P$3") (pintype "passive"))
    )
    (net (code "28") (name "/0_1439897389") (class "Default")
      (node (ref "JP530") (pin "P$3") (pinfunction "1_P$3") (pintype "passive"))
      (node (ref "JP825") (pin "P$3") (pinfunction "1_P$3") (pintype "passive"))
    )
    (net (code "29") (name "/0_1439897395") (class "Default")
      (node (ref "JP511") (pin "P$3") (pinfunction "1_P$3") (pintype "passive"))
      (node (ref "JP883") (pin "P$3") (pinfunction "1_P$3") (pintype "passive"))
    )
    (net (code "30") (name "/0_1439897401") (class "Default")
      (node (ref "JP501") (pin "P$3") (pinfunction "1_P$3") (pintype "passive"))
      (node (ref "JP881") (pin "P$3") (pinfunction "1_P$3") (pintype "passive"))
    )
    (net (code "31") (name "/0_1439897407") (class "Default")
      (node (ref "JP491") (pin "P$3") (pinfunction "1_P$3") (pintype "passive"))
      (node (ref "JP879") (pin "P$3") (pinfunction "1_P$3") (pintype "passive"))
    )
    (net (code "32") (name "/0_1439897412") (class "Default")
      (node (ref "JP481") (pin "P$3") (pinfunction "1_P$3") (pintype "passive"))
      (node (ref "JP877") (pin "P$3") (pinfunction "1_P$3") (pintype "passive"))
    )
    (net (code "33") (name "/0_1439897418") (class "Default")
      (node (ref "JP471") (pin "P$3") (pinfunction "1_P$3") (pintype "passive"))
      (node (ref "JP875") (pin "P$3") (pinfunction "1_P$3") (pintype "passive"))
    )
    (net (code "34") (name "/0_1439897423") (class "Default")
      (node (ref "JP461") (pin "P$3") (pinfunction "1_P$3") (pintype "passive"))
      (node (ref "JP873") (pin "P$3") (pinfunction "1_P$3") (pintype "passive"))
    )
    (net (code "35") (name "/0_1439897429") (class "Default")
      (node (ref "JP451") (pin "P$3") (pinfunction "1_P$3") (pintype "passive"))
      (node (ref "JP871") (pin "P$3") (pinfunction "1_P$3") (pintype "passive"))
    )
    (net (code "36") (name "/0_1439897436") (class "Default")
      (node (ref "JP520") (pin "P$3") (pinfunction "1_P$3") (pintype "passive"))
      (node (ref "JP823") (pin "P$3") (pinfunction "1_P$3") (pintype "passive"))
    )
    (net (code "37") (name "/0_1439897442") (class "Default")
      (node (ref "JP510") (pin "P$3") (pinfunction "1_P$3") (pintype "passive"))
      (node (ref "JP821") (pin "P$3") (pinfunction "1_P$3") (pintype "passive"))
    )
    (net (code "38") (name "/0_1439897448") (class "Default")
      (node (ref "JP500") (pin "P$3") (pinfunction "1_P$3") (pintype "passive"))
      (node (ref "JP819") (pin "P$3") (pinfunction "1_P$3") (pintype "passive"))
    )
    (net (code "39") (name "/0_1439897454") (class "Default")
      (node (ref "JP490") (pin "P$3") (pinfunction "1_P$3") (pintype "passive"))
      (node (ref "JP817") (pin "P$3") (pinfunction "1_P$3") (pintype "passive"))
    )
    (net (code "40") (name "/0_1439897461") (class "Default")
      (node (ref "JP480") (pin "P$3") (pinfunction "1_P$3") (pintype "passive"))
      (node (ref "JP815") (pin "P$3") (pinfunction "1_P$3") (pintype "passive"))
    )
    (net (code "41") (name "/0_1439897467") (class "Default")
      (node (ref "JP470") (pin "P$3") (pinfunction "1_P$3") (pintype "passive"))
      (node (ref "JP813") (pin "P$3") (pinfunction "1_P$3") (pintype "passive"))
    )
    (net (code "42") (name "/0_1439897473") (class "Default")
      (node (ref "JP460") (pin "P$3") (pinfunction "1_P$3") (pintype "passive"))
      (node (ref "JP811") (pin "P$3") (pinfunction "1_P$3") (pintype "passive"))
    )
    (net (code "43") (name "/0_1439897480") (class "Default")
      (node (ref "JP450") (pin "P$3") (pinfunction "1_P$3") (pintype "passive"))
      (node (ref "JP809") (pin "P$3") (pinfunction "1_P$3") (pintype "passive"))
    )
    (net (code "44") (name "/0_1439897485") (class "Default")
      (node (ref "JP441") (pin "P$3") (pinfunction "1_P$3") (pintype "passive"))
      (node (ref "JP869") (pin "P$3") (pinfunction "1_P$3") (pintype "passive"))
    )
    (net (code "45") (name "/0_1439897491") (class "Default")
      (node (ref "JP431") (pin "P$3") (pinfunction "1_P$3") (pintype "passive"))
      (node (ref "JP867") (pin "P$3") (pinfunction "1_P$3") (pintype "passive"))
    )
    (net (code "46") (name "/0_1439897496") (class "Default")
      (node (ref "JP421") (pin "P$3") (pinfunction "1_P$3") (pintype "passive"))
      (node (ref "JP865") (pin "P$3") (pinfunction "1_P$3") (pintype "passive"))
    )
    (net (code "47") (name "/0_1439897505") (class "Default")
      (node (ref "JP411") (pin "P$3") (pinfunction "1_P$3") (pintype "passive"))
      (node (ref "JP863") (pin "P$3") (pinfunction "1_P$3") (pintype "passive"))
    )
    (net (code "48") (name "/0_1439897514") (class "Default")
      (node (ref "JP401") (pin "P$3") (pinfunction "1_P$3") (pintype "passive"))
      (node (ref "JP861") (pin "P$3") (pinfunction "1_P$3") (pintype "passive"))
    )
    (net (code "49") (name "/0_1439897520") (class "Default")
      (node (ref "JP440") (pin "P$3") (pinfunction "1_P$3") (pintype "passive"))
      (node (ref "JP807") (pin "P$3") (pinfunction "1_P$3") (pintype "passive"))
    )
    (net (code "50") (name "/0_1439897527") (class "Default")
      (node (ref "JP430") (pin "P$3") (pinfunction "1_P$3") (pintype "passive"))
      (node (ref "JP805") (pin "P$3") (pinfunction "1_P$3") (pintype "passive"))
    )
    (net (code "51") (name "/0_1439897534") (class "Default")
      (node (ref "JP420") (pin "P$3") (pinfunction "1_P$3") (pintype "passive"))
      (node (ref "JP803") (pin "P$3") (pinfunction "1_P$3") (pintype "passive"))
    )
    (net (code "52") (name "/0_1439897539") (class "Default")
      (node (ref "JP410") (pin "P$3") (pinfunction "1_P$3") (pintype "passive"))
      (node (ref "JP801") (pin "P$3") (pinfunction "1_P$3") (pintype "passive"))
    )
    (net (code "53") (name "/0_1439897546") (class "Default")
      (node (ref "JP400") (pin "P$3") (pinfunction "1_P$3") (pintype "passive"))
      (node (ref "JP799") (pin "P$3") (pinfunction "1_P$3") (pintype "passive"))
    )
    (net (code "54") (name "/0_1439897614") (class "Default")
      (node (ref "JP391") (pin "P$3") (pinfunction "1_P$3") (pintype "passive"))
      (node (ref "JP859") (pin "P$3") (pinfunction "1_P$3") (pintype "passive"))
    )
    (net (code "55") (name "/0_1439897622") (class "Default")
      (node (ref "JP381") (pin "P$3") (pinfunction "1_P$3") (pintype "passive"))
      (node (ref "JP857") (pin "P$3") (pinfunction "1_P$3") (pintype "passive"))
    )
    (net (code "56") (name "/0_1439897631") (class "Default")
      (node (ref "JP371") (pin "P$3") (pinfunction "1_P$3") (pintype "passive"))
      (node (ref "JP855") (pin "P$3") (pinfunction "1_P$3") (pintype "passive"))
    )
    (net (code "57") (name "/0_1439897637") (class "Default")
      (node (ref "JP361") (pin "P$3") (pinfunction "1_P$3") (pintype "passive"))
      (node (ref "JP853") (pin "P$3") (pinfunction "1_P$3") (pintype "passive"))
    )
    (net (code "58") (name "/0_1439897643") (class "Default")
      (node (ref "JP351") (pin "P$3") (pinfunction "1_P$3") (pintype "passive"))
      (node (ref "JP851") (pin "P$3") (pinfunction "1_P$3") (pintype "passive"))
    )
    (net (code "59") (name "/0_1439897654") (class "Default")
      (node (ref "JP331") (pin "P$3") (pinfunction "1_P$3") (pintype "passive"))
      (node (ref "JP847") (pin "P$3") (pinfunction "1_P$3") (pintype "passive"))
    )
    (net (code "60") (name "/0_1439897660") (class "Default")
      (node (ref "JP341") (pin "P$3") (pinfunction "1_P$3") (pintype "passive"))
      (node (ref "JP849") (pin "P$3") (pinfunction "1_P$3") (pintype "passive"))
    )
    (net (code "61") (name "/0_1439897711") (class "Default")
      (node (ref "JP593") (pin "P$3") (pinfunction "1_P$3") (pintype "passive"))
      (node (ref "JP651") (pin "P$3") (pinfunction "1_P$3") (pintype "passive"))
    )
    (net (code "62") (name "/0_1439897726") (class "Default")
      (node (ref "JP597") (pin "P$3") (pinfunction "1_P$3") (pintype "passive"))
      (node (ref "JP641") (pin "P$3") (pinfunction "1_P$3") (pintype "passive"))
    )
    (net (code "63") (name "/0_1439897746") (class "Default")
      (node (ref "JP303") (pin "P$3") (pinfunction "1_P$3") (pintype "passive"))
      (node (ref "JP621") (pin "P$3") (pinfunction "1_P$3") (pintype "passive"))
    )
    (net (code "64") (name "/0_1439897770") (class "Default")
      (node (ref "JP307") (pin "P$3") (pinfunction "1_P$3") (pintype "passive"))
      (node (ref "JP601") (pin "P$3") (pinfunction "1_P$3") (pintype "passive"))
    )
    (net (code "65") (name "/0_1439897792") (class "Default")
      (node (ref "JP363") (pin "P$3") (pinfunction "1_P$3") (pintype "passive"))
      (node (ref "JP661") (pin "P$3") (pinfunction "1_P$3") (pintype "passive"))
    )
    (net (code "66") (name "/0_1439897815") (class "Default")
      (node (ref "JP378") (pin "P$3") (pinfunction "1_P$3") (pintype "passive"))
      (node (ref "JP721") (pin "P$3") (pinfunction "1_P$3") (pintype "passive"))
    )
    (net (code "67") (name "/0_1439897831") (class "Default")
      (node (ref "JP473") (pin "P$3") (pinfunction "1_P$3") (pintype "passive"))
      (node (ref "JP695") (pin "P$3") (pinfunction "1_P$3") (pintype "passive"))
    )
    (net (code "68") (name "/0_1439897845") (class "Default")
      (node (ref "JP488") (pin "P$3") (pinfunction "1_P$3") (pintype "passive"))
      (node (ref "JP757") (pin "P$3") (pinfunction "1_P$3") (pintype "passive"))
    )
    (net (code "69") (name "/0_1439897966") (class "Default")
      (node (ref "JP423") (pin "P$3") (pinfunction "1_P$3") (pintype "passive"))
      (node (ref "JP677") (pin "P$3") (pinfunction "1_P$3") (pintype "passive"))
    )
    (net (code "70") (name "/0_1439897993") (class "Default")
      (node (ref "JP428") (pin "P$3") (pinfunction "1_P$3") (pintype "passive"))
      (node (ref "JP737") (pin "P$3") (pinfunction "1_P$3") (pintype "passive"))
    )
    (net (code "71") (name "/1_1439897169") (class "Default")
      (node (ref "JP302") (pin "P$3") (pinfunction "1_P$3") (pintype "passive"))
      (node (ref "JP842") (pin "P$3") (pinfunction "1_P$3") (pintype "passive"))
    )
    (net (code "72") (name "/1_1439897178") (class "Default")
      (node (ref "JP312") (pin "P$3") (pinfunction "1_P$3") (pintype "passive"))
      (node (ref "JP844") (pin "P$3") (pinfunction "1_P$3") (pintype "passive"))
    )
    (net (code "73") (name "/1_1439897188") (class "Default")
      (node (ref "JP322") (pin "P$3") (pinfunction "1_P$3") (pintype "passive"))
      (node (ref "JP846") (pin "P$3") (pinfunction "1_P$3") (pintype "passive"))
    )
    (net (code "74") (name "/1_1439897194") (class "Default")
      (node (ref "JP309") (pin "P$3") (pinfunction "1_P$3") (pintype "passive"))
      (node (ref "JP782") (pin "P$3") (pinfunction "1_P$3") (pintype "passive"))
    )
    (net (code "75") (name "/1_1439897209") (class "Default")
      (node (ref "JP319") (pin "P$3") (pinfunction "1_P$3") (pintype "passive"))
      (node (ref "JP784") (pin "P$3") (pinfunction "1_P$3") (pintype "passive"))
    )
    (net (code "76") (name "/1_1439897217") (class "Default")
      (node (ref "JP329") (pin "P$3") (pinfunction "1_P$3") (pintype "passive"))
      (node (ref "JP786") (pin "P$3") (pinfunction "1_P$3") (pintype "passive"))
    )
    (net (code "77") (name "/1_1439897230") (class "Default")
      (node (ref "JP339") (pin "P$3") (pinfunction "1_P$3") (pintype "passive"))
      (node (ref "JP788") (pin "P$3") (pinfunction "1_P$3") (pintype "passive"))
    )
    (net (code "78") (name "/1_1439897238") (class "Default")
      (node (ref "JP349") (pin "P$3") (pinfunction "1_P$3") (pintype "passive"))
      (node (ref "JP790") (pin "P$3") (pinfunction "1_P$3") (pintype "passive"))
    )
    (net (code "79") (name "/1_1439897247") (class "Default")
      (node (ref "JP359") (pin "P$3") (pinfunction "1_P$3") (pintype "passive"))
      (node (ref "JP792") (pin "P$3") (pinfunction "1_P$3") (pintype "passive"))
    )
    (net (code "80") (name "/1_1439897254") (class "Default")
      (node (ref "JP369") (pin "P$3") (pinfunction "1_P$3") (pintype "passive"))
      (node (ref "JP794") (pin "P$3") (pinfunction "1_P$3") (pintype "passive"))
    )
    (net (code "81") (name "/1_1439897261") (class "Default")
      (node (ref "JP379") (pin "P$3") (pinfunction "1_P$3") (pintype "passive"))
      (node (ref "JP796") (pin "P$3") (pinfunction "1_P$3") (pintype "passive"))
    )
    (net (code "82") (name "/1_1439897267") (class "Default")
      (node (ref "JP389") (pin "P$3") (pinfunction "1_P$3") (pintype "passive"))
      (node (ref "JP798") (pin "P$3") (pinfunction "1_P$3") (pintype "passive"))
    )
    (net (code "83") (name "/1_1439897281") (class "Default")
      (node (ref "JP599") (pin "P$3") (pinfunction "1_P$3") (pintype "passive"))
      (node (ref "JP840") (pin "P$3") (pinfunction "1_P$3") (pintype "passive"))
    )
    (net (code "84") (name "/1_1439897288") (class "Default")
      (node (ref "JP589") (pin "P$3") (pinfunction "1_P$3") (pintype "passive"))
      (node (ref "JP838") (pin "P$3") (pinfunction "1_P$3") (pintype "passive"))
    )
    (net (code "85") (name "/1_1439897294") (class "Default")
      (node (ref "JP579") (pin "P$3") (pinfunction "1_P$3") (pintype "passive"))
      (node (ref "JP836") (pin "P$3") (pinfunction "1_P$3") (pintype "passive"))
    )
    (net (code "86") (name "/1_1439897300") (class "Default")
      (node (ref "JP592") (pin "P$3") (pinfunction "1_P$3") (pintype "passive"))
      (node (ref "JP900") (pin "P$3") (pinfunction "1_P$3") (pintype "passive"))
    )
    (net (code "87") (name "/1_1439897307") (class "Default")
      (node (ref "JP582") (pin "P$3") (pinfunction "1_P$3") (pintype "passive"))
      (node (ref "JP898") (pin "P$3") (pinfunction "1_P$3") (pintype "passive"))
    )
    (net (code "88") (name "/1_1439897312") (class "Default")
      (node (ref "JP572") (pin "P$3") (pinfunction "1_P$3") (pintype "passive"))
      (node (ref "JP896") (pin "P$3") (pinfunction "1_P$3") (pintype "passive"))
    )
    (net (code "89") (name "/1_1439897321") (class "Default")
      (node (ref "JP562") (pin "P$3") (pinfunction "1_P$3") (pintype "passive"))
      (node (ref "JP894") (pin "P$3") (pinfunction "1_P$3") (pintype "passive"))
    )
    (net (code "90") (name "/1_1439897329") (class "Default")
      (node (ref "JP552") (pin "P$3") (pinfunction "1_P$3") (pintype "passive"))
      (node (ref "JP892") (pin "P$3") (pinfunction "1_P$3") (pintype "passive"))
    )
    (net (code "91") (name "/1_1439897335") (class "Default")
      (node (ref "JP542") (pin "P$3") (pinfunction "1_P$3") (pintype "passive"))
      (node (ref "JP890") (pin "P$3") (pinfunction "1_P$3") (pintype "passive"))
    )
    (net (code "92") (name "/1_1439897341") (class "Default")
      (node (ref "JP532") (pin "P$3") (pinfunction "1_P$3") (pintype "passive"))
      (node (ref "JP888") (pin "P$3") (pinfunction "1_P$3") (pintype "passive"))
    )
    (net (code "93") (name "/1_1439897349") (class "Default")
      (node (ref "JP522") (pin "P$3") (pinfunction "1_P$3") (pintype "passive"))
      (node (ref "JP886") (pin "P$3") (pinfunction "1_P$3") (pintype "passive"))
    )
    (net (code "94") (name "/1_1439897354") (class "Default")
      (node (ref "JP569") (pin "P$3") (pinfunction "1_P$3") (pintype "passive"))
      (node (ref "JP834") (pin "P$3") (pinfunction "1_P$3") (pintype "passive"))
    )
    (net (code "95") (name "/1_1439897362") (class "Default")
      (node (ref "JP559") (pin "P$3") (pinfunction "1_P$3") (pintype "passive"))
      (node (ref "JP832") (pin "P$3") (pinfunction "1_P$3") (pintype "passive"))
    )
    (net (code "96") (name "/1_1439897369") (class "Default")
      (node (ref "JP549") (pin "P$3") (pinfunction "1_P$3") (pintype "passive"))
      (node (ref "JP830") (pin "P$3") (pinfunction "1_P$3") (pintype "passive"))
    )
    (net (code "97") (name "/1_1439897383") (class "Default")
      (node (ref "JP539") (pin "P$3") (pinfunction "1_P$3") (pintype "passive"))
      (node (ref "JP828") (pin "P$3") (pinfunction "1_P$3") (pintype "passive"))
    )
    (net (code "98") (name "/1_1439897389") (class "Default")
      (node (ref "JP529") (pin "P$3") (pinfunction "1_P$3") (pintype "passive"))
      (node (ref "JP826") (pin "P$3") (pinfunction "1_P$3") (pintype "passive"))
    )
    (net (code "99") (name "/1_1439897395") (class "Default")
      (node (ref "JP512") (pin "P$3") (pinfunction "1_P$3") (pintype "passive"))
      (node (ref "JP884") (pin "P$3") (pinfunction "1_P$3") (pintype "passive"))
    )
    (net (code "100") (name "/1_1439897401") (class "Default")
      (node (ref "JP502") (pin "P$3") (pinfunction "1_P$3") (pintype "passive"))
      (node (ref "JP882") (pin "P$3") (pinfunction "1_P$3") (pintype "passive"))
    )
    (net (code "101") (name "/1_1439897407") (class "Default")
      (node (ref "JP492") (pin "P$3") (pinfunction "1_P$3") (pintype "passive"))
      (node (ref "JP880") (pin "P$3") (pinfunction "1_P$3") (pintype "passive"))
    )
    (net (code "102") (name "/1_1439897412") (class "Default")
      (node (ref "JP482") (pin "P$3") (pinfunction "1_P$3") (pintype "passive"))
      (node (ref "JP878") (pin "P$3") (pinfunction "1_P$3") (pintype "passive"))
    )
    (net (code "103") (name "/1_1439897418") (class "Default")
      (node (ref "JP472") (pin "P$3") (pinfunction "1_P$3") (pintype "passive"))
      (node (ref "JP876") (pin "P$3") (pinfunction "1_P$3") (pintype "passive"))
    )
    (net (code "104") (name "/1_1439897423") (class "Default")
      (node (ref "JP462") (pin "P$3") (pinfunction "1_P$3") (pintype "passive"))
      (node (ref "JP874") (pin "P$3") (pinfunction "1_P$3") (pintype "passive"))
    )
    (net (code "105") (name "/1_1439897429") (class "Default")
      (node (ref "JP452") (pin "P$3") (pinfunction "1_P$3") (pintype "passive"))
      (node (ref "JP872") (pin "P$3") (pinfunction "1_P$3") (pintype "passive"))
    )
    (net (code "106") (name "/1_1439897436") (class "Default")
      (node (ref "JP519") (pin "P$3") (pinfunction "1_P$3") (pintype "passive"))
      (node (ref "JP824") (pin "P$3") (pinfunction "1_P$3") (pintype "passive"))
    )
    (net (code "107") (name "/1_1439897442") (class "Default")
      (node (ref "JP509") (pin "P$3") (pinfunction "1_P$3") (pintype "passive"))
      (node (ref "JP822") (pin "P$3") (pinfunction "1_P$3") (pintype "passive"))
    )
    (net (code "108") (name "/1_1439897448") (class "Default")
      (node (ref "JP499") (pin "P$3") (pinfunction "1_P$3") (pintype "passive"))
      (node (ref "JP820") (pin "P$3") (pinfunction "1_P$3") (pintype "passive"))
    )
    (net (code "109") (name "/1_1439897454") (class "Default")
      (node (ref "JP489") (pin "P$3") (pinfunction "1_P$3") (pintype "passive"))
      (node (ref "JP818") (pin "P$3") (pinfunction "1_P$3") (pintype "passive"))
    )
    (net (code "110") (name "/1_1439897461") (class "Default")
      (node (ref "JP479") (pin "P$3") (pinfunction "1_P$3") (pintype "passive"))
      (node (ref "JP816") (pin "P$3") (pinfunction "1_P$3") (pintype "passive"))
    )
    (net (code "111") (name "/1_1439897467") (class "Default")
      (node (ref "JP469") (pin "P$3") (pinfunction "1_P$3") (pintype "passive"))
      (node (ref "JP814") (pin "P$3") (pinfunction "1_P$3") (pintype "passive"))
    )
    (net (code "112") (name "/1_1439897473") (class "Default")
      (node (ref "JP459") (pin "P$3") (pinfunction "1_P$3") (pintype "passive"))
      (node (ref "JP812") (pin "P$3") (pinfunction "1_P$3") (pintype "passive"))
    )
    (net (code "113") (name "/1_1439897480") (class "Default")
      (node (ref "JP449") (pin "P$3") (pinfunction "1_P$3") (pintype "passive"))
      (node (ref "JP810") (pin "P$3") (pinfunction "1_P$3") (pintype "passive"))
    )
    (net (code "114") (name "/1_1439897485") (class "Default")
      (node (ref "JP442") (pin "P$3") (pinfunction "1_P$3") (pintype "passive"))
      (node (ref "JP870") (pin "P$3") (pinfunction "1_P$3") (pintype "passive"))
    )
    (net (code "115") (name "/1_1439897491") (class "Default")
      (node (ref "JP432") (pin "P$3") (pinfunction "1_P$3") (pintype "passive"))
      (node (ref "JP868") (pin "P$3") (pinfunction "1_P$3") (pintype "passive"))
    )
    (net (code "116") (name "/1_1439897496") (class "Default")
      (node (ref "JP422") (pin "P$3") (pinfunction "1_P$3") (pintype "passive"))
      (node (ref "JP866") (pin "P$3") (pinfunction "1_P$3") (pintype "passive"))
    )
    (net (code "117") (name "/1_1439897505") (class "Default")
      (node (ref "JP412") (pin "P$3") (pinfunction "1_P$3") (pintype "passive"))
      (node (ref "JP864") (pin "P$3") (pinfunction "1_P$3") (pintype "passive"))
    )
    (net (code "118") (name "/1_1439897514") (class "Default")
      (node (ref "JP402") (pin "P$3") (pinfunction "1_P$3") (pintype "passive"))
      (node (ref "JP862") (pin "P$3") (pinfunction "1_P$3") (pintype "passive"))
    )
    (net (code "119") (name "/1_1439897520") (class "Default")
      (node (ref "JP439") (pin "P$3") (pinfunction "1_P$3") (pintype "passive"))
      (node (ref "JP808") (pin "P$3") (pinfunction "1_P$3") (pintype "passive"))
    )
    (net (code "120") (name "/1_1439897527") (class "Default")
      (node (ref "JP429") (pin "P$3") (pinfunction "1_P$3") (pintype "passive"))
      (node (ref "JP806") (pin "P$3") (pinfunction "1_P$3") (pintype "passive"))
    )
    (net (code "121") (name "/1_1439897534") (class "Default")
      (node (ref "JP419") (pin "P$3") (pinfunction "1_P$3") (pintype "passive"))
      (node (ref "JP804") (pin "P$3") (pinfunction "1_P$3") (pintype "passive"))
    )
    (net (code "122") (name "/1_1439897539") (class "Default")
      (node (ref "JP409") (pin "P$3") (pinfunction "1_P$3") (pintype "passive"))
      (node (ref "JP802") (pin "P$3") (pinfunction "1_P$3") (pintype "passive"))
    )
    (net (code "123") (name "/1_1439897546") (class "Default")
      (node (ref "JP399") (pin "P$3") (pinfunction "1_P$3") (pintype "passive"))
      (node (ref "JP800") (pin "P$3") (pinfunction "1_P$3") (pintype "passive"))
    )
    (net (code "124") (name "/1_1439897614") (class "Default")
      (node (ref "JP392") (pin "P$3") (pinfunction "1_P$3") (pintype "passive"))
      (node (ref "JP860") (pin "P$3") (pinfunction "1_P$3") (pintype "passive"))
    )
    (net (code "125") (name "/1_1439897622") (class "Default")
      (node (ref "JP382") (pin "P$3") (pinfunction "1_P$3") (pintype "passive"))
      (node (ref "JP858") (pin "P$3") (pinfunction "1_P$3") (pintype "passive"))
    )
    (net (code "126") (name "/1_1439897631") (class "Default")
      (node (ref "JP372") (pin "P$3") (pinfunction "1_P$3") (pintype "passive"))
      (node (ref "JP856") (pin "P$3") (pinfunction "1_P$3") (pintype "passive"))
    )
    (net (code "127") (name "/1_1439897637") (class "Default")
      (node (ref "JP362") (pin "P$3") (pinfunction "1_P$3") (pintype "passive"))
      (node (ref "JP854") (pin "P$3") (pinfunction "1_P$3") (pintype "passive"))
    )
    (net (code "128") (name "/1_1439897643") (class "Default")
      (node (ref "JP352") (pin "P$3") (pinfunction "1_P$3") (pintype "passive"))
      (node (ref "JP852") (pin "P$3") (pinfunction "1_P$3") (pintype "passive"))
    )
    (net (code "129") (name "/1_1439897654") (class "Default")
      (node (ref "JP332") (pin "P$3") (pinfunction "1_P$3") (pintype "passive"))
      (node (ref "JP848") (pin "P$3") (pinfunction "1_P$3") (pintype "passive"))
    )
    (net (code "130") (name "/1_1439897660") (class "Default")
      (node (ref "JP342") (pin "P$3") (pinfunction "1_P$3") (pintype "passive"))
      (node (ref "JP850") (pin "P$3") (pinfunction "1_P$3") (pintype "passive"))
    )
    (net (code "131") (name "/1_1439897711") (class "Default")
      (node (ref "JP583") (pin "P$3") (pinfunction "1_P$3") (pintype "passive"))
      (node (ref "JP652") (pin "P$3") (pinfunction "1_P$3") (pintype "passive"))
    )
    (net (code "132") (name "/1_1439897726") (class "Default")
      (node (ref "JP598") (pin "P$3") (pinfunction "1_P$3") (pintype "passive"))
      (node (ref "JP642") (pin "P$3") (pinfunction "1_P$3") (pintype "passive"))
    )
    (net (code "133") (name "/1_1439897746") (class "Default")
      (node (ref "JP304") (pin "P$3") (pinfunction "1_P$3") (pintype "passive"))
      (node (ref "JP622") (pin "P$3") (pinfunction "1_P$3") (pintype "passive"))
    )
    (net (code "134") (name "/1_1439897770") (class "Default")
      (node (ref "JP308") (pin "P$3") (pinfunction "1_P$3") (pintype "passive"))
      (node (ref "JP602") (pin "P$3") (pinfunction "1_P$3") (pintype "passive"))
    )
    (net (code "135") (name "/1_1439897792") (class "Default")
      (node (ref "JP373") (pin "P$3") (pinfunction "1_P$3") (pintype "passive"))
      (node (ref "JP662") (pin "P$3") (pinfunction "1_P$3") (pintype "passive"))
    )
    (net (code "136") (name "/1_1439897815") (class "Default")
      (node (ref "JP388") (pin "P$3") (pinfunction "1_P$3") (pintype "passive"))
      (node (ref "JP722") (pin "P$3") (pinfunction "1_P$3") (pintype "passive"))
    )
    (net (code "137") (name "/1_1439897831") (class "Default")
      (node (ref "JP483") (pin "P$3") (pinfunction "1_P$3") (pintype "passive"))
      (node (ref "JP696") (pin "P$3") (pinfunction "1_P$3") (pintype "passive"))
    )
    (net (code "138") (name "/1_1439897845") (class "Default")
      (node (ref "JP498") (pin "P$3") (pinfunction "1_P$3") (pintype "passive"))
      (node (ref "JP758") (pin "P$3") (pinfunction "1_P$3") (pintype "passive"))
    )
    (net (code "139") (name "/1_1439897966") (class "Default")
      (node (ref "JP433") (pin "P$3") (pinfunction "1_P$3") (pintype "passive"))
      (node (ref "JP678") (pin "P$3") (pinfunction "1_P$3") (pintype "passive"))
    )
    (net (code "140") (name "/1_1439897993") (class "Default")
      (node (ref "JP438") (pin "P$3") (pinfunction "1_P$3") (pintype "passive"))
      (node (ref "JP738") (pin "P$3") (pinfunction "1_P$3") (pintype "passive"))
    )
    (net (code "141") (name "/2_1439897711") (class "Default")
      (node (ref "JP594") (pin "P$3") (pinfunction "1_P$3") (pintype "passive"))
      (node (ref "JP653") (pin "P$3") (pinfunction "1_P$3") (pintype "passive"))
    )
    (net (code "142") (name "/2_1439897726") (class "Default")
      (node (ref "JP596") (pin "P$3") (pinfunction "1_P$3") (pintype "passive"))
      (node (ref "JP643") (pin "P$3") (pinfunction "1_P$3") (pintype "passive"))
    )
    (net (code "143") (name "/2_1439897746") (class "Default")
      (node (ref "JP313") (pin "P$3") (pinfunction "1_P$3") (pintype "passive"))
      (node (ref "JP623") (pin "P$3") (pinfunction "1_P$3") (pintype "passive"))
    )
    (net (code "144") (name "/2_1439897770") (class "Default")
      (node (ref "JP306") (pin "P$3") (pinfunction "1_P$3") (pintype "passive"))
      (node (ref "JP603") (pin "P$3") (pinfunction "1_P$3") (pintype "passive"))
    )
    (net (code "145") (name "/2_1439897792") (class "Default")
      (node (ref "JP383") (pin "P$3") (pinfunction "1_P$3") (pintype "passive"))
      (node (ref "JP663") (pin "P$3") (pinfunction "1_P$3") (pintype "passive"))
    )
    (net (code "146") (name "/2_1439897815") (class "Default")
      (node (ref "JP377") (pin "P$3") (pinfunction "1_P$3") (pintype "passive"))
      (node (ref "JP723") (pin "P$3") (pinfunction "1_P$3") (pintype "passive"))
    )
    (net (code "147") (name "/2_1439897831") (class "Default")
      (node (ref "JP493") (pin "P$3") (pinfunction "1_P$3") (pintype "passive"))
      (node (ref "JP697") (pin "P$3") (pinfunction "1_P$3") (pintype "passive"))
    )
    (net (code "148") (name "/2_1439897845") (class "Default")
      (node (ref "JP508") (pin "P$3") (pinfunction "1_P$3") (pintype "passive"))
      (node (ref "JP759") (pin "P$3") (pinfunction "1_P$3") (pintype "passive"))
    )
    (net (code "149") (name "/2_1439897966") (class "Default")
      (node (ref "JP443") (pin "P$3") (pinfunction "1_P$3") (pintype "passive"))
      (node (ref "JP679") (pin "P$3") (pinfunction "1_P$3") (pintype "passive"))
    )
    (net (code "150") (name "/2_1439897993") (class "Default")
      (node (ref "JP448") (pin "P$3") (pinfunction "1_P$3") (pintype "passive"))
      (node (ref "JP739") (pin "P$3") (pinfunction "1_P$3") (pintype "passive"))
    )
    (net (code "151") (name "/3_1439897711") (class "Default")
      (node (ref "JP584") (pin "P$3") (pinfunction "1_P$3") (pintype "passive"))
      (node (ref "JP654") (pin "P$3") (pinfunction "1_P$3") (pintype "passive"))
    )
    (net (code "152") (name "/3_1439897726") (class "Default")
      (node (ref "JP588") (pin "P$3") (pinfunction "1_P$3") (pintype "passive"))
      (node (ref "JP644") (pin "P$3") (pinfunction "1_P$3") (pintype "passive"))
    )
    (net (code "153") (name "/3_1439897746") (class "Default")
      (node (ref "JP314") (pin "P$3") (pinfunction "1_P$3") (pintype "passive"))
      (node (ref "JP624") (pin "P$3") (pinfunction "1_P$3") (pintype "passive"))
    )
    (net (code "154") (name "/3_1439897770") (class "Default")
      (node (ref "JP318") (pin "P$3") (pinfunction "1_P$3") (pintype "passive"))
      (node (ref "JP604") (pin "P$3") (pinfunction "1_P$3") (pintype "passive"))
    )
    (net (code "155") (name "/3_1439897792") (class "Default")
      (node (ref "JP374") (pin "P$3") (pinfunction "1_P$3") (pintype "passive"))
      (node (ref "JP664") (pin "P$3") (pinfunction "1_P$3") (pintype "passive"))
    )
    (net (code "156") (name "/3_1439897815") (class "Default")
      (node (ref "JP398") (pin "P$3") (pinfunction "1_P$3") (pintype "passive"))
      (node (ref "JP724") (pin "P$3") (pinfunction "1_P$3") (pintype "passive"))
    )
    (net (code "157") (name "/3_1439897831") (class "Default")
      (node (ref "JP503") (pin "P$3") (pinfunction "1_P$3") (pintype "passive"))
      (node (ref "JP698") (pin "P$3") (pinfunction "1_P$3") (pintype "passive"))
    )
    (net (code "158") (name "/3_1439897845") (class "Default")
      (node (ref "JP518") (pin "P$3") (pinfunction "1_P$3") (pintype "passive"))
      (node (ref "JP760") (pin "P$3") (pinfunction "1_P$3") (pintype "passive"))
    )
    (net (code "159") (name "/3_1439897966") (class "Default")
      (node (ref "JP424") (pin "P$3") (pinfunction "1_P$3") (pintype "passive"))
      (node (ref "JP680") (pin "P$3") (pinfunction "1_P$3") (pintype "passive"))
    )
    (net (code "160") (name "/3_1439897993") (class "Default")
      (node (ref "JP427") (pin "P$3") (pinfunction "1_P$3") (pintype "passive"))
      (node (ref "JP740") (pin "P$3") (pinfunction "1_P$3") (pintype "passive"))
    )
    (net (code "161") (name "/4_1439897711") (class "Default")
      (node (ref "JP573") (pin "P$3") (pinfunction "1_P$3") (pintype "passive"))
      (node (ref "JP655") (pin "P$3") (pinfunction "1_P$3") (pintype "passive"))
    )
    (net (code "162") (name "/4_1439897726") (class "Default")
      (node (ref "JP587") (pin "P$3") (pinfunction "1_P$3") (pintype "passive"))
      (node (ref "JP645") (pin "P$3") (pinfunction "1_P$3") (pintype "passive"))
    )
    (net (code "163") (name "/4_1439897746") (class "Default")
      (node (ref "JP305") (pin "P$3") (pinfunction "1_P$3") (pintype "passive"))
      (node (ref "JP625") (pin "P$3") (pinfunction "1_P$3") (pintype "passive"))
    )
    (net (code "164") (name "/4_1439897770") (class "Default")
      (node (ref "JP317") (pin "P$3") (pinfunction "1_P$3") (pintype "passive"))
      (node (ref "JP605") (pin "P$3") (pinfunction "1_P$3") (pintype "passive"))
    )
    (net (code "165") (name "/4_1439897792") (class "Default")
      (node (ref "JP393") (pin "P$3") (pinfunction "1_P$3") (pintype "passive"))
      (node (ref "JP665") (pin "P$3") (pinfunction "1_P$3") (pintype "passive"))
    )
    (net (code "166") (name "/4_1439897815") (class "Default")
      (node (ref "JP387") (pin "P$3") (pinfunction "1_P$3") (pintype "passive"))
      (node (ref "JP725") (pin "P$3") (pinfunction "1_P$3") (pintype "passive"))
    )
    (net (code "167") (name "/4_1439897831") (class "Default")
      (node (ref "JP513") (pin "P$3") (pinfunction "1_P$3") (pintype "passive"))
      (node (ref "JP699") (pin "P$3") (pinfunction "1_P$3") (pintype "passive"))
    )
    (net (code "168") (name "/4_1439897845") (class "Default")
      (node (ref "JP528") (pin "P$3") (pinfunction "1_P$3") (pintype "passive"))
      (node (ref "JP761") (pin "P$3") (pinfunction "1_P$3") (pintype "passive"))
    )
    (net (code "169") (name "/4_1439897966") (class "Default")
      (node (ref "JP453") (pin "P$3") (pinfunction "1_P$3") (pintype "passive"))
      (node (ref "JP681") (pin "P$3") (pinfunction "1_P$3") (pintype "passive"))
    )
    (net (code "170") (name "/4_1439897993") (class "Default")
      (node (ref "JP458") (pin "P$3") (pinfunction "1_P$3") (pintype "passive"))
      (node (ref "JP741") (pin "P$3") (pinfunction "1_P$3") (pintype "passive"))
    )
    (net (code "171") (name "/5_1439897711") (class "Default")
      (node (ref "JP595") (pin "P$3") (pinfunction "1_P$3") (pintype "passive"))
      (node (ref "JP656") (pin "P$3") (pinfunction "1_P$3") (pintype "passive"))
    )
    (net (code "172") (name "/5_1439897726") (class "Default")
      (node (ref "JP578") (pin "P$3") (pinfunction "1_P$3") (pintype "passive"))
      (node (ref "JP646") (pin "P$3") (pinfunction "1_P$3") (pintype "passive"))
    )
    (net (code "173") (name "/5_1439897746") (class "Default")
      (node (ref "JP315") (pin "P$3") (pinfunction "1_P$3") (pintype "passive"))
      (node (ref "JP626") (pin "P$3") (pinfunction "1_P$3") (pintype "passive"))
    )
    (net (code "174") (name "/5_1439897770") (class "Default")
      (node (ref "JP328") (pin "P$3") (pinfunction "1_P$3") (pintype "passive"))
      (node (ref "JP606") (pin "P$3") (pinfunction "1_P$3") (pintype "passive"))
    )
    (net (code "175") (name "/5_1439897792") (class "Default")
      (node (ref "JP384") (pin "P$3") (pinfunction "1_P$3") (pintype "passive"))
      (node (ref "JP666") (pin "P$3") (pinfunction "1_P$3") (pintype "passive"))
    )
    (net (code "176") (name "/5_1439897815") (class "Default")
      (node (ref "JP366") (pin "P$3") (pinfunction "1_P$3") (pintype "passive"))
      (node (ref "JP726") (pin "P$3") (pinfunction "1_P$3") (pintype "passive"))
    )
    (net (code "177") (name "/5_1439897831") (class "Default")
      (node (ref "JP523") (pin "P$3") (pinfunction "1_P$3") (pintype "passive"))
      (node (ref "JP700") (pin "P$3") (pinfunction "1_P$3") (pintype "passive"))
    )
    (net (code "178") (name "/5_1439897845") (class "Default")
      (node (ref "JP538") (pin "P$3") (pinfunction "1_P$3") (pintype "passive"))
      (node (ref "JP762") (pin "P$3") (pinfunction "1_P$3") (pintype "passive"))
    )
    (net (code "179") (name "/5_1439897966") (class "Default")
      (node (ref "JP434") (pin "P$3") (pinfunction "1_P$3") (pintype "passive"))
      (node (ref "JP682") (pin "P$3") (pinfunction "1_P$3") (pintype "passive"))
    )
    (net (code "180") (name "/5_1439897993") (class "Default")
      (node (ref "JP437") (pin "P$3") (pinfunction "1_P$3") (pintype "passive"))
      (node (ref "JP742") (pin "P$3") (pinfunction "1_P$3") (pintype "passive"))
    )
    (net (code "181") (name "/6_1439897711") (class "Default")
      (node (ref "JP585") (pin "P$3") (pinfunction "1_P$3") (pintype "passive"))
      (node (ref "JP657") (pin "P$3") (pinfunction "1_P$3") (pintype "passive"))
    )
    (net (code "182") (name "/6_1439897726") (class "Default")
      (node (ref "JP577") (pin "P$3") (pinfunction "1_P$3") (pintype "passive"))
      (node (ref "JP647") (pin "P$3") (pinfunction "1_P$3") (pintype "passive"))
    )
    (net (code "183") (name "/6_1439897746") (class "Default")
      (node (ref "JP323") (pin "P$3") (pinfunction "1_P$3") (pintype "passive"))
      (node (ref "JP627") (pin "P$3") (pinfunction "1_P$3") (pintype "passive"))
    )
    (net (code "184") (name "/6_1439897770") (class "Default")
      (node (ref "JP327") (pin "P$3") (pinfunction "1_P$3") (pintype "passive"))
      (node (ref "JP607") (pin "P$3") (pinfunction "1_P$3") (pintype "passive"))
    )
    (net (code "185") (name "/6_1439897792") (class "Default")
      (node (ref "JP403") (pin "P$3") (pinfunction "1_P$3") (pintype "passive"))
      (node (ref "JP667") (pin "P$3") (pinfunction "1_P$3") (pintype "passive"))
    )
    (net (code "186") (name "/6_1439897815") (class "Default")
      (node (ref "JP408") (pin "P$3") (pinfunction "1_P$3") (pintype "passive"))
      (node (ref "JP727") (pin "P$3") (pinfunction "1_P$3") (pintype "passive"))
    )
    (net (code "187") (name "/6_1439897831") (class "Default")
      (node (ref "JP533") (pin "P$3") (pinfunction "1_P$3") (pintype "passive"))
      (node (ref "JP701") (pin "P$3") (pinfunction "1_P$3") (pintype "passive"))
    )
    (net (code "188") (name "/6_1439897845") (class "Default")
      (node (ref "JP548") (pin "P$3") (pinfunction "1_P$3") (pintype "passive"))
      (node (ref "JP763") (pin "P$3") (pinfunction "1_P$3") (pintype "passive"))
    )
    (net (code "189") (name "/6_1439897966") (class "Default")
      (node (ref "JP463") (pin "P$3") (pinfunction "1_P$3") (pintype "passive"))
      (node (ref "JP683") (pin "P$3") (pinfunction "1_P$3") (pintype "passive"))
    )
    (net (code "190") (name "/6_1439897993") (class "Default")
      (node (ref "JP468") (pin "P$3") (pinfunction "1_P$3") (pintype "passive"))
      (node (ref "JP743") (pin "P$3") (pinfunction "1_P$3") (pintype "passive"))
    )
    (net (code "191") (name "/7_1439897711") (class "Default")
      (node (ref "JP574") (pin "P$3") (pinfunction "1_P$3") (pintype "passive"))
      (node (ref "JP658") (pin "P$3") (pinfunction "1_P$3") (pintype "passive"))
    )
    (net (code "192") (name "/7_1439897726") (class "Default")
      (node (ref "JP568") (pin "P$3") (pinfunction "1_P$3") (pintype "passive"))
      (node (ref "JP648") (pin "P$3") (pinfunction "1_P$3") (pintype "passive"))
    )
    (net (code "193") (name "/7_1439897746") (class "Default")
      (node (ref "JP324") (pin "P$3") (pinfunction "1_P$3") (pintype "passive"))
      (node (ref "JP628") (pin "P$3") (pinfunction "1_P$3") (pintype "passive"))
    )
    (net (code "194") (name "/7_1439897770") (class "Default")
      (node (ref "JP338") (pin "P$3") (pinfunction "1_P$3") (pintype "passive"))
      (node (ref "JP608") (pin "P$3") (pinfunction "1_P$3") (pintype "passive"))
    )
    (net (code "195") (name "/7_1439897792") (class "Default")
      (node (ref "JP394") (pin "P$3") (pinfunction "1_P$3") (pintype "passive"))
      (node (ref "JP668") (pin "P$3") (pinfunction "1_P$3") (pintype "passive"))
    )
    (net (code "196") (name "/7_1439897815") (class "Default")
      (node (ref "JP397") (pin "P$3") (pinfunction "1_P$3") (pintype "passive"))
      (node (ref "JP728") (pin "P$3") (pinfunction "1_P$3") (pintype "passive"))
    )
    (net (code "197") (name "/7_1439897831") (class "Default")
      (node (ref "JP543") (pin "P$3") (pinfunction "1_P$3") (pintype "passive"))
      (node (ref "JP702") (pin "P$3") (pinfunction "1_P$3") (pintype "passive"))
    )
    (net (code "198") (name "/7_1439897845") (class "Default")
      (node (ref "JP558") (pin "P$3") (pinfunction "1_P$3") (pintype "passive"))
      (node (ref "JP764") (pin "P$3") (pinfunction "1_P$3") (pintype "passive"))
    )
    (net (code "199") (name "/7_1439897966") (class "Default")
      (node (ref "JP444") (pin "P$3") (pinfunction "1_P$3") (pintype "passive"))
      (node (ref "JP684") (pin "P$3") (pinfunction "1_P$3") (pintype "passive"))
    )
    (net (code "200") (name "/7_1439897993") (class "Default")
      (node (ref "JP447") (pin "P$3") (pinfunction "1_P$3") (pintype "passive"))
      (node (ref "JP744") (pin "P$3") (pinfunction "1_P$3") (pintype "passive"))
    )
    (net (code "201") (name "/8_1439897711") (class "Default")
      (node (ref "JP575") (pin "P$3") (pinfunction "1_P$3") (pintype "passive"))
      (node (ref "JP659") (pin "P$3") (pinfunction "1_P$3") (pintype "passive"))
    )
    (net (code "202") (name "/8_1439897726") (class "Default")
      (node (ref "JP586") (pin "P$3") (pinfunction "1_P$3") (pintype "passive"))
      (node (ref "JP649") (pin "P$3") (pinfunction "1_P$3") (pintype "passive"))
    )
    (net (code "203") (name "/8_1439897746") (class "Default")
      (node (ref "JP325") (pin "P$3") (pinfunction "1_P$3") (pintype "passive"))
      (node (ref "JP629") (pin "P$3") (pinfunction "1_P$3") (pintype "passive"))
    )
    (net (code "204") (name "/8_1439897770") (class "Default")
      (node (ref "JP316") (pin "P$3") (pinfunction "1_P$3") (pintype "passive"))
      (node (ref "JP609") (pin "P$3") (pinfunction "1_P$3") (pintype "passive"))
    )
    (net (code "205") (name "/8_1439897792") (class "Default")
      (node (ref "JP413") (pin "P$3") (pinfunction "1_P$3") (pintype "passive"))
      (node (ref "JP669") (pin "P$3") (pinfunction "1_P$3") (pintype "passive"))
    )
    (net (code "206") (name "/8_1439897815") (class "Default")
      (node (ref "JP418") (pin "P$3") (pinfunction "1_P$3") (pintype "passive"))
      (node (ref "JP729") (pin "P$3") (pinfunction "1_P$3") (pintype "passive"))
    )
    (net (code "207") (name "/8_1439897831") (class "Default")
      (node (ref "JP553") (pin "P$3") (pinfunction "1_P$3") (pintype "passive"))
      (node (ref "JP703") (pin "P$3") (pinfunction "1_P$3") (pintype "passive"))
    )
    (net (code "208") (name "/8_1439897845") (class "Default")
      (node (ref "JP557") (pin "P$3") (pinfunction "1_P$3") (pintype "passive"))
      (node (ref "JP765") (pin "P$3") (pinfunction "1_P$3") (pintype "passive"))
    )
    (net (code "209") (name "/8_1439897966") (class "Default")
      (node (ref "JP454") (pin "P$3") (pinfunction "1_P$3") (pintype "passive"))
      (node (ref "JP685") (pin "P$3") (pinfunction "1_P$3") (pintype "passive"))
    )
    (net (code "210") (name "/8_1439897993") (class "Default")
      (node (ref "JP478") (pin "P$3") (pinfunction "1_P$3") (pintype "passive"))
      (node (ref "JP745") (pin "P$3") (pinfunction "1_P$3") (pintype "passive"))
    )
    (net (code "211") (name "/9_1439897711") (class "Default")
      (node (ref "JP564") (pin "P$3") (pinfunction "1_P$3") (pintype "passive"))
      (node (ref "JP660") (pin "P$3") (pinfunction "1_P$3") (pintype "passive"))
    )
    (net (code "212") (name "/9_1439897726") (class "Default")
      (node (ref "JP567") (pin "P$3") (pinfunction "1_P$3") (pintype "passive"))
      (node (ref "JP650") (pin "P$3") (pinfunction "1_P$3") (pintype "passive"))
    )
    (net (code "213") (name "/9_1439897746") (class "Default")
      (node (ref "JP334") (pin "P$3") (pinfunction "1_P$3") (pintype "passive"))
      (node (ref "JP630") (pin "P$3") (pinfunction "1_P$3") (pintype "passive"))
    )
    (net (code "214") (name "/9_1439897770") (class "Default")
      (node (ref "JP337") (pin "P$3") (pinfunction "1_P$3") (pintype "passive"))
      (node (ref "JP610") (pin "P$3") (pinfunction "1_P$3") (pintype "passive"))
    )
    (net (code "215") (name "/9_1439897792") (class "Default")
      (node (ref "JP404") (pin "P$3") (pinfunction "1_P$3") (pintype "passive"))
      (node (ref "JP670") (pin "P$3") (pinfunction "1_P$3") (pintype "passive"))
    )
    (net (code "216") (name "/9_1439897815") (class "Default")
      (node (ref "JP407") (pin "P$3") (pinfunction "1_P$3") (pintype "passive"))
      (node (ref "JP730") (pin "P$3") (pinfunction "1_P$3") (pintype "passive"))
    )
    (net (code "217") (name "/9_1439897831") (class "Default")
      (node (ref "JP563") (pin "P$3") (pinfunction "1_P$3") (pintype "passive"))
      (node (ref "JP704") (pin "P$3") (pinfunction "1_P$3") (pintype "passive"))
    )
    (net (code "218") (name "/9_1439897845") (class "Default")
      (node (ref "JP547") (pin "P$3") (pinfunction "1_P$3") (pintype "passive"))
      (node (ref "JP766") (pin "P$3") (pinfunction "1_P$3") (pintype "passive"))
    )
    (net (code "219") (name "/9_1439897966") (class "Default")
      (node (ref "JP464") (pin "P$3") (pinfunction "1_P$3") (pintype "passive"))
      (node (ref "JP686") (pin "P$3") (pinfunction "1_P$3") (pintype "passive"))
    )
    (net (code "220") (name "/9_1439897993") (class "Default")
      (node (ref "JP457") (pin "P$3") (pinfunction "1_P$3") (pintype "passive"))
      (node (ref "JP746") (pin "P$3") (pinfunction "1_P$3") (pintype "passive"))
    )
    (net (code "221") (name "/10_1439897746") (class "Default")
      (node (ref "JP333") (pin "P$3") (pinfunction "1_P$3") (pintype "passive"))
      (node (ref "JP631") (pin "P$3") (pinfunction "1_P$3") (pintype "passive"))
    )
    (net (code "222") (name "/10_1439897770") (class "Default")
      (node (ref "JP326") (pin "P$3") (pinfunction "1_P$3") (pintype "passive"))
      (node (ref "JP611") (pin "P$3") (pinfunction "1_P$3") (pintype "passive"))
    )
    (net (code "223") (name "/10_1439897792") (class "Default")
      (node (ref "JP375") (pin "P$3") (pinfunction "1_P$3") (pintype "passive"))
      (node (ref "JP671") (pin "P$3") (pinfunction "1_P$3") (pintype "passive"))
    )
    (net (code "224") (name "/10_1439897815") (class "Default")
      (node (ref "JP376") (pin "P$3") (pinfunction "1_P$3") (pintype "passive"))
      (node (ref "JP731") (pin "P$3") (pinfunction "1_P$3") (pintype "passive"))
    )
    (net (code "225") (name "/10_1439897831") (class "Default")
      (node (ref "JP524") (pin "P$3") (pinfunction "1_P$3") (pintype "passive"))
      (node (ref "JP705") (pin "P$3") (pinfunction "1_P$3") (pintype "passive"))
    )
    (net (code "226") (name "/10_1439897845") (class "Default")
      (node (ref "JP537") (pin "P$3") (pinfunction "1_P$3") (pintype "passive"))
      (node (ref "JP767") (pin "P$3") (pinfunction "1_P$3") (pintype "passive"))
    )
    (net (code "227") (name "/10_1439897966") (class "Default")
      (node (ref "JP474") (pin "P$3") (pinfunction "1_P$3") (pintype "passive"))
      (node (ref "JP687") (pin "P$3") (pinfunction "1_P$3") (pintype "passive"))
    )
    (net (code "228") (name "/10_1439897993") (class "Default")
      (node (ref "JP467") (pin "P$3") (pinfunction "1_P$3") (pintype "passive"))
      (node (ref "JP747") (pin "P$3") (pinfunction "1_P$3") (pintype "passive"))
    )
    (net (code "229") (name "/11_1439897746") (class "Default")
      (node (ref "JP343") (pin "P$3") (pinfunction "1_P$3") (pintype "passive"))
      (node (ref "JP632") (pin "P$3") (pinfunction "1_P$3") (pintype "passive"))
    )
    (net (code "230") (name "/11_1439897770") (class "Default")
      (node (ref "JP336") (pin "P$3") (pinfunction "1_P$3") (pintype "passive"))
      (node (ref "JP612") (pin "P$3") (pinfunction "1_P$3") (pintype "passive"))
    )
    (net (code "231") (name "/11_1439897792") (class "Default")
      (node (ref "JP414") (pin "P$3") (pinfunction "1_P$3") (pintype "passive"))
      (node (ref "JP672") (pin "P$3") (pinfunction "1_P$3") (pintype "passive"))
    )
    (net (code "232") (name "/11_1439897815") (class "Default")
      (node (ref "JP417") (pin "P$3") (pinfunction "1_P$3") (pintype "passive"))
      (node (ref "JP732") (pin "P$3") (pinfunction "1_P$3") (pintype "passive"))
    )
    (net (code "233") (name "/11_1439897831") (class "Default")
      (node (ref "JP534") (pin "P$3") (pinfunction "1_P$3") (pintype "passive"))
      (node (ref "JP706") (pin "P$3") (pinfunction "1_P$3") (pintype "passive"))
    )
    (net (code "234") (name "/11_1439897845") (class "Default")
      (node (ref "JP527") (pin "P$3") (pinfunction "1_P$3") (pintype "passive"))
      (node (ref "JP768") (pin "P$3") (pinfunction "1_P$3") (pintype "passive"))
    )
    (net (code "235") (name "/11_1439897966") (class "Default")
      (node (ref "JP435") (pin "P$3") (pinfunction "1_P$3") (pintype "passive"))
      (node (ref "JP688") (pin "P$3") (pinfunction "1_P$3") (pintype "passive"))
    )
    (net (code "236") (name "/11_1439897993") (class "Default")
      (node (ref "JP477") (pin "P$3") (pinfunction "1_P$3") (pintype "passive"))
      (node (ref "JP748") (pin "P$3") (pinfunction "1_P$3") (pintype "passive"))
    )
    (net (code "237") (name "/12_1439897746") (class "Default")
      (node (ref "JP335") (pin "P$3") (pinfunction "1_P$3") (pintype "passive"))
      (node (ref "JP633") (pin "P$3") (pinfunction "1_P$3") (pintype "passive"))
    )
    (net (code "238") (name "/12_1439897770") (class "Default")
      (node (ref "JP348") (pin "P$3") (pinfunction "1_P$3") (pintype "passive"))
      (node (ref "JP613") (pin "P$3") (pinfunction "1_P$3") (pintype "passive"))
    )
    (net (code "239") (name "/12_1439897792") (class "Default")
      (node (ref "JP385") (pin "P$3") (pinfunction "1_P$3") (pintype "passive"))
      (node (ref "JP673") (pin "P$3") (pinfunction "1_P$3") (pintype "passive"))
    )
    (net (code "240") (name "/12_1439897815") (class "Default")
      (node (ref "JP386") (pin "P$3") (pinfunction "1_P$3") (pintype "passive"))
      (node (ref "JP733") (pin "P$3") (pinfunction "1_P$3") (pintype "passive"))
    )
    (net (code "241") (name "/12_1439897831") (class "Default")
      (node (ref "JP544") (pin "P$3") (pinfunction "1_P$3") (pintype "passive"))
      (node (ref "JP707") (pin "P$3") (pinfunction "1_P$3") (pintype "passive"))
    )
    (net (code "242") (name "/12_1439897845") (class "Default")
      (node (ref "JP576") (pin "P$3") (pinfunction "1_P$3") (pintype "passive"))
      (node (ref "JP769") (pin "P$3") (pinfunction "1_P$3") (pintype "passive"))
    )
    (net (code "243") (name "/12_1439897966") (class "Default")
      (node (ref "JP445") (pin "P$3") (pinfunction "1_P$3") (pintype "passive"))
      (node (ref "JP689") (pin "P$3") (pinfunction "1_P$3") (pintype "passive"))
    )
    (net (code "244") (name "/12_1439897993") (class "Default")
      (node (ref "JP446") (pin "P$3") (pinfunction "1_P$3") (pintype "passive"))
      (node (ref "JP749") (pin "P$3") (pinfunction "1_P$3") (pintype "passive"))
    )
    (net (code "245") (name "/13_1439897746") (class "Default")
      (node (ref "JP344") (pin "P$3") (pinfunction "1_P$3") (pintype "passive"))
      (node (ref "JP634") (pin "P$3") (pinfunction "1_P$3") (pintype "passive"))
    )
    (net (code "246") (name "/13_1439897770") (class "Default")
      (node (ref "JP347") (pin "P$3") (pinfunction "1_P$3") (pintype "passive"))
      (node (ref "JP614") (pin "P$3") (pinfunction "1_P$3") (pintype "passive"))
    )
    (net (code "247") (name "/13_1439897792") (class "Default")
      (node (ref "JP395") (pin "P$3") (pinfunction "1_P$3") (pintype "passive"))
      (node (ref "JP674") (pin "P$3") (pinfunction "1_P$3") (pintype "passive"))
    )
    (net (code "248") (name "/13_1439897815") (class "Default")
      (node (ref "JP396") (pin "P$3") (pinfunction "1_P$3") (pintype "passive"))
      (node (ref "JP734") (pin "P$3") (pinfunction "1_P$3") (pintype "passive"))
    )
    (net (code "249") (name "/13_1439897831") (class "Default")
      (node (ref "JP554") (pin "P$3") (pinfunction "1_P$3") (pintype "passive"))
      (node (ref "JP708") (pin "P$3") (pinfunction "1_P$3") (pintype "passive"))
    )
    (net (code "250") (name "/13_1439897845") (class "Default")
      (node (ref "JP566") (pin "P$3") (pinfunction "1_P$3") (pintype "passive"))
      (node (ref "JP770") (pin "P$3") (pinfunction "1_P$3") (pintype "passive"))
    )
    (net (code "251") (name "/13_1439897966") (class "Default")
      (node (ref "JP455") (pin "P$3") (pinfunction "1_P$3") (pintype "passive"))
      (node (ref "JP690") (pin "P$3") (pinfunction "1_P$3") (pintype "passive"))
    )
    (net (code "252") (name "/13_1439897993") (class "Default")
      (node (ref "JP456") (pin "P$3") (pinfunction "1_P$3") (pintype "passive"))
      (node (ref "JP750") (pin "P$3") (pinfunction "1_P$3") (pintype "passive"))
    )
    (net (code "253") (name "/14_1439897746") (class "Default")
      (node (ref "JP345") (pin "P$3") (pinfunction "1_P$3") (pintype "passive"))
      (node (ref "JP635") (pin "P$3") (pinfunction "1_P$3") (pintype "passive"))
    )
    (net (code "254") (name "/14_1439897770") (class "Default")
      (node (ref "JP346") (pin "P$3") (pinfunction "1_P$3") (pintype "passive"))
      (node (ref "JP615") (pin "P$3") (pinfunction "1_P$3") (pintype "passive"))
    )
    (net (code "255") (name "/14_1439897792") (class "Default")
      (node (ref "JP405") (pin "P$3") (pinfunction "1_P$3") (pintype "passive"))
      (node (ref "JP675") (pin "P$3") (pinfunction "1_P$3") (pintype "passive"))
    )
    (net (code "256") (name "/14_1439897815") (class "Default")
      (node (ref "JP406") (pin "P$3") (pinfunction "1_P$3") (pintype "passive"))
      (node (ref "JP735") (pin "P$3") (pinfunction "1_P$3") (pintype "passive"))
    )
    (net (code "257") (name "/14_1439897831") (class "Default")
      (node (ref "JP514") (pin "P$3") (pinfunction "1_P$3") (pintype "passive"))
      (node (ref "JP709") (pin "P$3") (pinfunction "1_P$3") (pintype "passive"))
    )
    (net (code "258") (name "/14_1439897845") (class "Default")
      (node (ref "JP556") (pin "P$3") (pinfunction "1_P$3") (pintype "passive"))
      (node (ref "JP771") (pin "P$3") (pinfunction "1_P$3") (pintype "passive"))
    )
    (net (code "259") (name "/14_1439897966") (class "Default")
      (node (ref "JP465") (pin "P$3") (pinfunction "1_P$3") (pintype "passive"))
      (node (ref "JP691") (pin "P$3") (pinfunction "1_P$3") (pintype "passive"))
    )
    (net (code "260") (name "/14_1439897993") (class "Default")
      (node (ref "JP466") (pin "P$3") (pinfunction "1_P$3") (pintype "passive"))
      (node (ref "JP751") (pin "P$3") (pinfunction "1_P$3") (pintype "passive"))
    )
    (net (code "261") (name "/15_1439897746") (class "Default")
      (node (ref "JP353") (pin "P$3") (pinfunction "1_P$3") (pintype "passive"))
      (node (ref "JP636") (pin "P$3") (pinfunction "1_P$3") (pintype "passive"))
    )
    (net (code "262") (name "/15_1439897770") (class "Default")
      (node (ref "JP358") (pin "P$3") (pinfunction "1_P$3") (pintype "passive"))
      (node (ref "JP616") (pin "P$3") (pinfunction "1_P$3") (pintype "passive"))
    )
    (net (code "263") (name "/15_1439897792") (class "Default")
      (node (ref "JP415") (pin "P$3") (pinfunction "1_P$3") (pintype "passive"))
      (node (ref "JP676") (pin "P$3") (pinfunction "1_P$3") (pintype "passive"))
    )
    (net (code "264") (name "/15_1439897815") (class "Default")
      (node (ref "JP416") (pin "P$3") (pinfunction "1_P$3") (pintype "passive"))
      (node (ref "JP736") (pin "P$3") (pinfunction "1_P$3") (pintype "passive"))
    )
    (net (code "265") (name "/15_1439897831") (class "Default")
      (node (ref "JP504") (pin "P$3") (pinfunction "1_P$3") (pintype "passive"))
      (node (ref "JP710") (pin "P$3") (pinfunction "1_P$3") (pintype "passive"))
    )
    (net (code "266") (name "/15_1439897845") (class "Default")
      (node (ref "JP546") (pin "P$3") (pinfunction "1_P$3") (pintype "passive"))
      (node (ref "JP772") (pin "P$3") (pinfunction "1_P$3") (pintype "passive"))
    )
    (net (code "267") (name "/15_1439897966") (class "Default")
      (node (ref "JP475") (pin "P$3") (pinfunction "1_P$3") (pintype "passive"))
      (node (ref "JP692") (pin "P$3") (pinfunction "1_P$3") (pintype "passive"))
    )
    (net (code "268") (name "/15_1439897993") (class "Default")
      (node (ref "JP476") (pin "P$3") (pinfunction "1_P$3") (pintype "passive"))
      (node (ref "JP752") (pin "P$3") (pinfunction "1_P$3") (pintype "passive"))
    )
    (net (code "269") (name "/16_1439897746") (class "Default")
      (node (ref "JP354") (pin "P$3") (pinfunction "1_P$3") (pintype "passive"))
      (node (ref "JP637") (pin "P$3") (pinfunction "1_P$3") (pintype "passive"))
    )
    (net (code "270") (name "/16_1439897770") (class "Default")
      (node (ref "JP357") (pin "P$3") (pinfunction "1_P$3") (pintype "passive"))
      (node (ref "JP617") (pin "P$3") (pinfunction "1_P$3") (pintype "passive"))
    )
    (net (code "271") (name "/16_1439897831") (class "Default")
      (node (ref "JP545") (pin "P$3") (pinfunction "1_P$3") (pintype "passive"))
      (node (ref "JP711") (pin "P$3") (pinfunction "1_P$3") (pintype "passive"))
    )
    (net (code "272") (name "/16_1439897845") (class "Default")
      (node (ref "JP517") (pin "P$3") (pinfunction "1_P$3") (pintype "passive"))
      (node (ref "JP773") (pin "P$3") (pinfunction "1_P$3") (pintype "passive"))
    )
    (net (code "273") (name "/16_1439897966") (class "Default")
      (node (ref "JP485") (pin "P$3") (pinfunction "1_P$3") (pintype "passive"))
      (node (ref "JP693") (pin "P$3") (pinfunction "1_P$3") (pintype "passive"))
    )
    (net (code "274") (name "/16_1439897993") (class "Default")
      (node (ref "JP486") (pin "P$3") (pinfunction "1_P$3") (pintype "passive"))
      (node (ref "JP753") (pin "P$3") (pinfunction "1_P$3") (pintype "passive"))
    )
    (net (code "275") (name "/17_1439897746") (class "Default")
      (node (ref "JP355") (pin "P$3") (pinfunction "1_P$3") (pintype "passive"))
      (node (ref "JP638") (pin "P$3") (pinfunction "1_P$3") (pintype "passive"))
    )
    (net (code "276") (name "/17_1439897770") (class "Default")
      (node (ref "JP356") (pin "P$3") (pinfunction "1_P$3") (pintype "passive"))
      (node (ref "JP618") (pin "P$3") (pinfunction "1_P$3") (pintype "passive"))
    )
    (net (code "277") (name "/17_1439897831") (class "Default")
      (node (ref "JP555") (pin "P$3") (pinfunction "1_P$3") (pintype "passive"))
      (node (ref "JP712") (pin "P$3") (pinfunction "1_P$3") (pintype "passive"))
    )
    (net (code "278") (name "/17_1439897845") (class "Default")
      (node (ref "JP507") (pin "P$3") (pinfunction "1_P$3") (pintype "passive"))
      (node (ref "JP774") (pin "P$3") (pinfunction "1_P$3") (pintype "passive"))
    )
    (net (code "279") (name "/17_1439897966") (class "Default")
      (node (ref "JP425") (pin "P$3") (pinfunction "1_P$3") (pintype "passive"))
      (node (ref "JP694") (pin "P$3") (pinfunction "1_P$3") (pintype "passive"))
    )
    (net (code "280") (name "/17_1439897993") (class "Default")
      (node (ref "JP496") (pin "P$3") (pinfunction "1_P$3") (pintype "passive"))
      (node (ref "JP754") (pin "P$3") (pinfunction "1_P$3") (pintype "passive"))
    )
    (net (code "281") (name "/18_1439897746") (class "Default")
      (node (ref "JP364") (pin "P$3") (pinfunction "1_P$3") (pintype "passive"))
      (node (ref "JP639") (pin "P$3") (pinfunction "1_P$3") (pintype "passive"))
    )
    (net (code "282") (name "/18_1439897770") (class "Default")
      (node (ref "JP368") (pin "P$3") (pinfunction "1_P$3") (pintype "passive"))
      (node (ref "JP619") (pin "P$3") (pinfunction "1_P$3") (pintype "passive"))
    )
    (net (code "283") (name "/18_1439897831") (class "Default")
      (node (ref "JP565") (pin "P$3") (pinfunction "1_P$3") (pintype "passive"))
      (node (ref "JP713") (pin "P$3") (pinfunction "1_P$3") (pintype "passive"))
    )
    (net (code "284") (name "/18_1439897845") (class "Default")
      (node (ref "JP536") (pin "P$3") (pinfunction "1_P$3") (pintype "passive"))
      (node (ref "JP775") (pin "P$3") (pinfunction "1_P$3") (pintype "passive"))
    )
    (net (code "285") (name "/18_1439897993") (class "Default")
      (node (ref "JP436") (pin "P$3") (pinfunction "1_P$3") (pintype "passive"))
      (node (ref "JP755") (pin "P$3") (pinfunction "1_P$3") (pintype "passive"))
    )
    (net (code "286") (name "/19_1439897746") (class "Default")
      (node (ref "JP365") (pin "P$3") (pinfunction "1_P$3") (pintype "passive"))
      (node (ref "JP640") (pin "P$3") (pinfunction "1_P$3") (pintype "passive"))
    )
    (net (code "287") (name "/19_1439897770") (class "Default")
      (node (ref "JP367") (pin "P$3") (pinfunction "1_P$3") (pintype "passive"))
      (node (ref "JP620") (pin "P$3") (pinfunction "1_P$3") (pintype "passive"))
    )
    (net (code "288") (name "/19_1439897831") (class "Default")
      (node (ref "JP535") (pin "P$3") (pinfunction "1_P$3") (pintype "passive"))
      (node (ref "JP714") (pin "P$3") (pinfunction "1_P$3") (pintype "passive"))
    )
    (net (code "289") (name "/19_1439897845") (class "Default")
      (node (ref "JP497") (pin "P$3") (pinfunction "1_P$3") (pintype "passive"))
      (node (ref "JP776") (pin "P$3") (pinfunction "1_P$3") (pintype "passive"))
    )
    (net (code "290") (name "/19_1439897993") (class "Default")
      (node (ref "JP426") (pin "P$3") (pinfunction "1_P$3") (pintype "passive"))
      (node (ref "JP756") (pin "P$3") (pinfunction "1_P$3") (pintype "passive"))
    )
    (net (code "291") (name "/20_1439897831") (class "Default")
      (node (ref "JP525") (pin "P$3") (pinfunction "1_P$3") (pintype "passive"))
      (node (ref "JP715") (pin "P$3") (pinfunction "1_P$3") (pintype "passive"))
    )
    (net (code "292") (name "/20_1439897845") (class "Default")
      (node (ref "JP526") (pin "P$3") (pinfunction "1_P$3") (pintype "passive"))
      (node (ref "JP777") (pin "P$3") (pinfunction "1_P$3") (pintype "passive"))
    )
    (net (code "293") (name "/21_1439897831") (class "Default")
      (node (ref "JP494") (pin "P$3") (pinfunction "1_P$3") (pintype "passive"))
      (node (ref "JP716") (pin "P$3") (pinfunction "1_P$3") (pintype "passive"))
    )
    (net (code "294") (name "/21_1439897845") (class "Default")
      (node (ref "JP487") (pin "P$3") (pinfunction "1_P$3") (pintype "passive"))
      (node (ref "JP778") (pin "P$3") (pinfunction "1_P$3") (pintype "passive"))
    )
    (net (code "295") (name "/22_1439897831") (class "Default")
      (node (ref "JP515") (pin "P$3") (pinfunction "1_P$3") (pintype "passive"))
      (node (ref "JP717") (pin "P$3") (pinfunction "1_P$3") (pintype "passive"))
    )
    (net (code "296") (name "/22_1439897845") (class "Default")
      (node (ref "JP516") (pin "P$3") (pinfunction "1_P$3") (pintype "passive"))
      (node (ref "JP779") (pin "P$3") (pinfunction "1_P$3") (pintype "passive"))
    )
    (net (code "297") (name "/23_1439897831") (class "Default")
      (node (ref "JP505") (pin "P$3") (pinfunction "1_P$3") (pintype "passive"))
      (node (ref "JP718") (pin "P$3") (pinfunction "1_P$3") (pintype "passive"))
    )
    (net (code "298") (name "/23_1439897845") (class "Default")
      (node (ref "JP506") (pin "P$3") (pinfunction "1_P$3") (pintype "passive"))
      (node (ref "JP780") (pin "P$3") (pinfunction "1_P$3") (pintype "passive"))
    )
    (net (code "299") (name "/24_1439897831") (class "Default")
      (node (ref "JP484") (pin "P$3") (pinfunction "1_P$3") (pintype "passive"))
      (node (ref "JP719") (pin "P$3") (pinfunction "1_P$3") (pintype "passive"))
    )
    (net (code "300") (name "/25_1439897831") (class "Default")
      (node (ref "JP495") (pin "P$3") (pinfunction "1_P$3") (pintype "passive"))
      (node (ref "JP720") (pin "P$3") (pinfunction "1_P$3") (pintype "passive"))
    )
    (net (code "301") (name "unconnected-(JP901-1-PadP$3)") (class "Default")
      (node (ref "JP901") (pin "P$3") (pinfunction "1_P$3") (pintype "passive"))
    )
    (net (code "302") (name "unconnected-(JP902-1-PadP$3)") (class "Default")
      (node (ref "JP902") (pin "P$3") (pinfunction "1_P$3") (pintype "passive"))
    )
    (net (code "303") (name "unconnected-(JP903-1-PadP$3)") (class "Default")
      (node (ref "JP903") (pin "P$3") (pinfunction "1_P$3") (pintype "passive"))
    )
    (net (code "304") (name "unconnected-(JP904-1-PadP$3)") (class "Default")
      (node (ref "JP904") (pin "P$3") (pinfunction "1_P$3") (pintype "passive"))
    )
    (net (code "305") (name "unconnected-(JP905-1-PadP$3)") (class "Default")
      (node (ref "JP905") (pin "P$3") (pinfunction "1_P$3") (pintype "passive"))
    )
    (net (code "306") (name "unconnected-(JP906-1-PadP$3)") (class "Default")
      (node (ref "JP906") (pin "P$3") (pinfunction "1_P$3") (pintype "passive"))
    )
    (net (code "307") (name "unconnected-(JP907-1-PadP$3)") (class "Default")
      (node (ref "JP907") (pin "P$3") (pinfunction "1_P$3") (pintype "passive"))
    )
    (net (code "308") (name "unconnected-(JP908-1-PadP$3)") (class "Default")
      (node (ref "JP908") (pin "P$3") (pinfunction "1_P$3") (pintype "passive"))
    )
    (net (code "309") (name "unconnected-(JP909-1-PadP$3)") (class "Default")
      (node (ref "JP909") (pin "P$3") (pinfunction "1_P$3") (pintype "passive"))
    )
    (net (code "310") (name "unconnected-(JP910-1-PadP$3)") (class "Default")
      (node (ref "JP910") (pin "P$3") (pinfunction "1_P$3") (pintype "passive"))
    )
    (net (code "311") (name "unconnected-(JP911-1-PadP$3)") (class "Default")
      (node (ref "JP911") (pin "P$3") (pinfunction "1_P$3") (pintype "passive"))
    )
    (net (code "312") (name "unconnected-(JP912-1-PadP$3)") (class "Default")
      (node (ref "JP912") (pin "P$3") (pinfunction "1_P$3") (pintype "passive"))
    )
    (net (code "313") (name "unconnected-(JP913-1-PadP$3)") (class "Default")
      (node (ref "JP913") (pin "P$3") (pinfunction "1_P$3") (pintype "passive"))
    )
    (net (code "314") (name "unconnected-(JP914-1-PadP$3)") (class "Default")
      (node (ref "JP914") (pin "P$3") (pinfunction "1_P$3") (pintype "passive"))
    )
    (net (code "315") (name "unconnected-(JP915-1-PadP$3)") (class "Default")
      (node (ref "JP915") (pin "P$3") (pinfunction "1_P$3") (pintype "passive"))
    )
    (net (code "316") (name "unconnected-(JP916-1-PadP$3)") (class "Default")
      (node (ref "JP916") (pin "P$3") (pinfunction "1_P$3") (pintype "passive"))
    )
    (net (code "317") (name "unconnected-(JP917-1-PadP$3)") (class "Default")
      (node (ref "JP917") (pin "P$3") (pinfunction "1_P$3") (pintype "passive"))
    )
    (net (code "318") (name "unconnected-(JP918-1-PadP$3)") (class "Default")
      (node (ref "JP918") (pin "P$3") (pinfunction "1_P$3") (pintype "passive"))
    )
    (net (code "319") (name "unconnected-(JP919-1-PadP$3)") (class "Default")
      (node (ref "JP919") (pin "P$3") (pinfunction "1_P$3") (pintype "passive"))
    )
    (net (code "320") (name "unconnected-(JP920-1-PadP$3)") (class "Default")
      (node (ref "JP920") (pin "P$3") (pinfunction "1_P$3") (pintype "passive"))
    )
    (net (code "321") (name "unconnected-(JP921-1-PadP$3)") (class "Default")
      (node (ref "JP921") (pin "P$3") (pinfunction "1_P$3") (pintype "passive"))
    )
    (net (code "322") (name "unconnected-(JP922-1-PadP$3)") (class "Default")
      (node (ref "JP922") (pin "P$3") (pinfunction "1_P$3") (pintype "passive"))
    )
    (net (code "323") (name "unconnected-(JP923-1-PadP$3)") (class "Default")
      (node (ref "JP923") (pin "P$3") (pinfunction "1_P$3") (pintype "passive"))
    )
    (net (code "324") (name "unconnected-(JP924-1-PadP$3)") (class "Default")
      (node (ref "JP924") (pin "P$3") (pinfunction "1_P$3") (pintype "passive"))
    )
    (net (code "325") (name "unconnected-(JP925-1-PadP$3)") (class "Default")
      (node (ref "JP925") (pin "P$3") (pinfunction "1_P$3") (pintype "passive"))
    )
    (net (code "326") (name "unconnected-(JP926-1-PadP$3)") (class "Default")
      (node (ref "JP926") (pin "P$3") (pinfunction "1_P$3") (pintype "passive"))
    )
    (net (code "327") (name "unconnected-(JP927-1-PadP$3)") (class "Default")
      (node (ref "JP927") (pin "P$3") (pinfunction "1_P$3") (pintype "passive"))
    )
    (net (code "328") (name "unconnected-(JP928-1-PadP$3)") (class "Default")
      (node (ref "JP928") (pin "P$3") (pinfunction "1_P$3") (pintype "passive"))
    )
    (net (code "329") (name "unconnected-(JP929-1-PadP$3)") (class "Default")
      (node (ref "JP929") (pin "P$3") (pinfunction "1_P$3") (pintype "passive"))
    )
    (net (code "330") (name "unconnected-(JP930-1-PadP$3)") (class "Default")
      (node (ref "JP930") (pin "P$3") (pinfunction "1_P$3") (pintype "passive"))
    )
    (net (code "331") (name "unconnected-(JP931-1-PadP$3)") (class "Default")
      (node (ref "JP931") (pin "P$3") (pinfunction "1_P$3") (pintype "passive"))
    )
    (net (code "332") (name "unconnected-(JP932-1-PadP$3)") (class "Default")
      (node (ref "JP932") (pin "P$3") (pinfunction "1_P$3") (pintype "passive"))
    )
    (net (code "333") (name "unconnected-(JP933-1-PadP$3)") (class "Default")
      (node (ref "JP933") (pin "P$3") (pinfunction "1_P$3") (pintype "passive"))
    )
    (net (code "334") (name "unconnected-(JP934-1-PadP$3)") (class "Default")
      (node (ref "JP934") (pin "P$3") (pinfunction "1_P$3") (pintype "passive"))
    )
    (net (code "335") (name "unconnected-(JP935-1-PadP$3)") (class "Default")
      (node (ref "JP935") (pin "P$3") (pinfunction "1_P$3") (pintype "passive"))
    )
    (net (code "336") (name "unconnected-(JP936-1-PadP$3)") (class "Default")
      (node (ref "JP936") (pin "P$3") (pinfunction "1_P$3") (pintype "passive"))
    )
    (net (code "337") (name "unconnected-(JP937-1-PadP$3)") (class "Default")
      (node (ref "JP937") (pin "P$3") (pinfunction "1_P$3") (pintype "passive"))
    )
    (net (code "338") (name "unconnected-(JP938-1-PadP$3)") (class "Default")
      (node (ref "JP938") (pin "P$3") (pinfunction "1_P$3") (pintype "passive"))
    )
    (net (code "339") (name "unconnected-(JP939-1-PadP$3)") (class "Default")
      (node (ref "JP939") (pin "P$3") (pinfunction "1_P$3") (pintype "passive"))
    )
    (net (code "340") (name "unconnected-(JP940-1-PadP$3)") (class "Default")
      (node (ref "JP940") (pin "P$3") (pinfunction "1_P$3") (pintype "passive"))
    )
    (net (code "341") (name "unconnected-(JP941-1-PadP$3)") (class "Default")
      (node (ref "JP941") (pin "P$3") (pinfunction "1_P$3") (pintype "passive"))
    )
    (net (code "342") (name "unconnected-(JP942-1-PadP$3)") (class "Default")
      (node (ref "JP942") (pin "P$3") (pinfunction "1_P$3") (pintype "passive"))
    )
    (net (code "343") (name "unconnected-(JP943-1-PadP$3)") (class "Default")
      (node (ref "JP943") (pin "P$3") (pinfunction "1_P$3") (pintype "passive"))
    )
    (net (code "344") (name "unconnected-(JP944-1-PadP$3)") (class "Default")
      (node (ref "JP944") (pin "P$3") (pinfunction "1_P$3") (pintype "passive"))
    )
    (net (code "345") (name "unconnected-(JP945-1-PadP$3)") (class "Default")
      (node (ref "JP945") (pin "P$3") (pinfunction "1_P$3") (pintype "passive"))
    )
    (net (code "346") (name "unconnected-(JP946-1-PadP$3)") (class "Default")
      (node (ref "JP946") (pin "P$3") (pinfunction "1_P$3") (pintype "passive"))
    )
    (net (code "347") (name "unconnected-(JP947-1-PadP$3)") (class "Default")
      (node (ref "JP947") (pin "P$3") (pinfunction "1_P$3") (pintype "passive"))
    )
    (net (code "348") (name "unconnected-(JP948-1-PadP$3)") (class "Default")
      (node (ref "JP948") (pin "P$3") (pinfunction "1_P$3") (pintype "passive"))
    )
    (net (code "349") (name "unconnected-(JP949-1-PadP$3)") (class "Default")
      (node (ref "JP949") (pin "P$3") (pinfunction "1_P$3") (pintype "passive"))
    )
    (net (code "350") (name "unconnected-(JP950-1-PadP$3)") (class "Default")
      (node (ref "JP950") (pin "P$3") (pinfunction "1_P$3") (pintype "passive"))
    )
    (net (code "351") (name "unconnected-(JP951-1-PadP$3)") (class "Default")
      (node (ref "JP951") (pin "P$3") (pinfunction "1_P$3") (pintype "passive"))
    )
    (net (code "352") (name "unconnected-(JP952-1-PadP$3)") (class "Default")
      (node (ref "JP952") (pin "P$3") (pinfunction "1_P$3") (pintype "passive"))
    )
    (net (code "353") (name "unconnected-(JP953-1-PadP$3)") (class "Default")
      (node (ref "JP953") (pin "P$3") (pinfunction "1_P$3") (pintype "passive"))
    )
    (net (code "354") (name "unconnected-(JP954-1-PadP$3)") (class "Default")
      (node (ref "JP954") (pin "P$3") (pinfunction "1_P$3") (pintype "passive"))
    )
    (net (code "355") (name "unconnected-(JP955-1-PadP$3)") (class "Default")
      (node (ref "JP955") (pin "P$3") (pinfunction "1_P$3") (pintype "passive"))
    )
    (net (code "356") (name "unconnected-(JP956-1-PadP$3)") (class "Default")
      (node (ref "JP956") (pin "P$3") (pinfunction "1_P$3") (pintype "passive"))
    )
    (net (code "357") (name "unconnected-(JP957-1-PadP$3)") (class "Default")
      (node (ref "JP957") (pin "P$3") (pinfunction "1_P$3") (pintype "passive"))
    )
    (net (code "358") (name "unconnected-(JP958-1-PadP$3)") (class "Default")
      (node (ref "JP958") (pin "P$3") (pinfunction "1_P$3") (pintype "passive"))
    )
    (net (code "359") (name "unconnected-(JP959-1-PadP$3)") (class "Default")
      (node (ref "JP959") (pin "P$3") (pinfunction "1_P$3") (pintype "passive"))
    )
    (net (code "360") (name "unconnected-(JP960-1-PadP$3)") (class "Default")
      (node (ref "JP960") (pin "P$3") (pinfunction "1_P$3") (pintype "passive"))
    )
    (net (code "361") (name "unconnected-(JP961-1-PadP$3)") (class "Default")
      (node (ref "JP961") (pin "P$3") (pinfunction "1_P$3") (pintype "passive"))
    )
    (net (code "362") (name "unconnected-(JP962-1-PadP$3)") (class "Default")
      (node (ref "JP962") (pin "P$3") (pinfunction "1_P$3") (pintype "passive"))
    )
    (net (code "363") (name "unconnected-(JP963-1-PadP$3)") (class "Default")
      (node (ref "JP963") (pin "P$3") (pinfunction "1_P$3") (pintype "passive"))
    )
    (net (code "364") (name "unconnected-(JP964-1-PadP$3)") (class "Default")
      (node (ref "JP964") (pin "P$3") (pinfunction "1_P$3") (pintype "passive"))
    )
    (net (code "365") (name "unconnected-(JP965-1-PadP$3)") (class "Default")
      (node (ref "JP965") (pin "P$3") (pinfunction "1_P$3") (pintype "passive"))
    )
    (net (code "366") (name "unconnected-(JP966-1-PadP$3)") (class "Default")
      (node (ref "JP966") (pin "P$3") (pinfunction "1_P$3") (pintype "passive"))
    )
    (net (code "367") (name "unconnected-(JP967-1-PadP$3)") (class "Default")
      (node (ref "JP967") (pin "P$3") (pinfunction "1_P$3") (pintype "passive"))
    )
    (net (code "368") (name "unconnected-(JP968-1-PadP$3)") (class "Default")
      (node (ref "JP968") (pin "P$3") (pinfunction "1_P$3") (pintype "passive"))
    )
    (net (code "369") (name "unconnected-(JP969-1-PadP$3)") (class "Default")
      (node (ref "JP969") (pin "P$3") (pinfunction "1_P$3") (pintype "passive"))
    )
    (net (code "370") (name "unconnected-(JP970-1-PadP$3)") (class "Default")
      (node (ref "JP970") (pin "P$3") (pinfunction "1_P$3") (pintype "passive"))
    )
    (net (code "371") (name "unconnected-(JP971-1-PadP$3)") (class "Default")
      (node (ref "JP971") (pin "P$3") (pinfunction "1_P$3") (pintype "passive"))
    )
    (net (code "372") (name "unconnected-(JP972-1-PadP$3)") (class "Default")
      (node (ref "JP972") (pin "P$3") (pinfunction "1_P$3") (pintype "passive"))
    )
    (net (code "373") (name "unconnected-(JP973-1-PadP$3)") (class "Default")
      (node (ref "JP973") (pin "P$3") (pinfunction "1_P$3") (pintype "passive"))
    )
    (net (code "374") (name "unconnected-(JP974-1-PadP$3)") (class "Default")
      (node (ref "JP974") (pin "P$3") (pinfunction "1_P$3") (pintype "passive"))
    )
    (net (code "375") (name "unconnected-(JP975-1-PadP$3)") (class "Default")
      (node (ref "JP975") (pin "P$3") (pinfunction "1_P$3") (pintype "passive"))
    )
    (net (code "376") (name "unconnected-(JP976-1-PadP$3)") (class "Default")
      (node (ref "JP976") (pin "P$3") (pinfunction "1_P$3") (pintype "passive"))
    )
    (net (code "377") (name "unconnected-(JP977-1-PadP$3)") (class "Default")
      (node (ref "JP977") (pin "P$3") (pinfunction "1_P$3") (pintype "passive"))
    )
    (net (code "378") (name "unconnected-(JP978-1-PadP$3)") (class "Default")
      (node (ref "JP978") (pin "P$3") (pinfunction "1_P$3") (pintype "passive"))
    )
    (net (code "379") (name "unconnected-(JP979-1-PadP$3)") (class "Default")
      (node (ref "JP979") (pin "P$3") (pinfunction "1_P$3") (pintype "passive"))
    )
    (net (code "380") (name "unconnected-(JP980-1-PadP$3)") (class "Default")
      (node (ref "JP980") (pin "P$3") (pinfunction "1_P$3") (pintype "passive"))
    )
    (net (code "381") (name "unconnected-(JP981-1-PadP$3)") (class "Default")
      (node (ref "JP981") (pin "P$3") (pinfunction "1_P$3") (pintype "passive"))
    )
    (net (code "382") (name "unconnected-(JP982-1-PadP$3)") (class "Default")
      (node (ref "JP982") (pin "P$3") (pinfunction "1_P$3") (pintype "passive"))
    )
    (net (code "383") (name "unconnected-(JP983-1-PadP$3)") (class "Default")
      (node (ref "JP983") (pin "P$3") (pinfunction "1_P$3") (pintype "passive"))
    )
    (net (code "384") (name "unconnected-(JP984-1-PadP$3)") (class "Default")
      (node (ref "JP984") (pin "P$3") (pinfunction "1_P$3") (pintype "passive"))
    )
    (net (code "385") (name "unconnected-(JP985-1-PadP$3)") (class "Default")
      (node (ref "JP985") (pin "P$3") (pinfunction "1_P$3") (pintype "passive"))
    )
    (net (code "386") (name "unconnected-(JP986-1-PadP$3)") (class "Default")
      (node (ref "JP986") (pin "P$3") (pinfunction "1_P$3") (pintype "passive"))
    )
    (net (code "387") (name "unconnected-(JP987-1-PadP$3)") (class "Default")
      (node (ref "JP987") (pin "P$3") (pinfunction "1_P$3") (pintype "passive"))
    )
    (net (code "388") (name "unconnected-(JP988-1-PadP$3)") (class "Default")
      (node (ref "JP988") (pin "P$3") (pinfunction "1_P$3") (pintype "passive"))
    )
    (net (code "389") (name "unconnected-(JP989-1-PadP$3)") (class "Default")
      (node (ref "JP989") (pin "P$3") (pinfunction "1_P$3") (pintype "passive"))
    )
    (net (code "390") (name "unconnected-(JP990-1-PadP$3)") (class "Default")
      (node (ref "JP990") (pin "P$3") (pinfunction "1_P$3") (pintype "passive"))
    )
    (net (code "391") (name "unconnected-(JP991-1-PadP$3)") (class "Default")
      (node (ref "JP991") (pin "P$3") (pinfunction "1_P$3") (pintype "passive"))
    )
    (net (code "392") (name "unconnected-(JP992-1-PadP$3)") (class "Default")
      (node (ref "JP992") (pin "P$3") (pinfunction "1_P$3") (pintype "passive"))
    )
    (net (code "393") (name "unconnected-(JP993-1-PadP$3)") (class "Default")
      (node (ref "JP993") (pin "P$3") (pinfunction "1_P$3") (pintype "passive"))
    )
    (net (code "394") (name "unconnected-(JP994-1-PadP$3)") (class "Default")
      (node (ref "JP994") (pin "P$3") (pinfunction "1_P$3") (pintype "passive"))
    )
    (net (code "395") (name "unconnected-(JP995-1-PadP$3)") (class "Default")
      (node (ref "JP995") (pin "P$3") (pinfunction "1_P$3") (pintype "passive"))
    )
    (net (code "396") (name "unconnected-(JP996-1-PadP$3)") (class "Default")
      (node (ref "JP996") (pin "P$3") (pinfunction "1_P$3") (pintype "passive"))
    )
    (net (code "397") (name "unconnected-(JP997-1-PadP$3)") (class "Default")
      (node (ref "JP997") (pin "P$3") (pinfunction "1_P$3") (pintype "passive"))
    )
    (net (code "398") (name "unconnected-(JP998-1-PadP$3)") (class "Default")
      (node (ref "JP998") (pin "P$3") (pinfunction "1_P$3") (pintype "passive"))
    )
    (net (code "399") (name "unconnected-(JP999-1-PadP$3)") (class "Default")
      (node (ref "JP999") (pin "P$3") (pinfunction "1_P$3") (pintype "passive"))
    )
    (net (code "400") (name "unconnected-(JP1000-1-PadP$3)") (class "Default")
      (node (ref "JP1000") (pin "P$3") (pinfunction "1_P$3") (pintype "passive"))
    )
    (net (code "401") (name "unconnected-(JP1001-1-PadP$3)") (class "Default")
      (node (ref "JP1001") (pin "P$3") (pinfunction "1_P$3") (pintype "passive"))
    )
    (net (code "402") (name "unconnected-(JP1002-1-PadP$3)") (class "Default")
      (node (ref "JP1002") (pin "P$3") (pinfunction "1_P$3") (pintype "passive"))
    )
    (net (code "403") (name "unconnected-(JP1003-1-PadP$3)") (class "Default")
      (node (ref "JP1003") (pin "P$3") (pinfunction "1_P$3") (pintype "passive"))
    )
    (net (code "404") (name "unconnected-(JP1004-1-PadP$3)") (class "Default")
      (node (ref "JP1004") (pin "P$3") (pinfunction "1_P$3") (pintype "passive"))
    )
    (net (code "405") (name "unconnected-(JP1005-1-PadP$3)") (class "Default")
      (node (ref "JP1005") (pin "P$3") (pinfunction "1_P$3") (pintype "passive"))
    )
    (net (code "406") (name "unconnected-(JP1006-1-PadP$3)") (class "Default")
      (node (ref "JP1006") (pin "P$3") (pinfunction "1_P$3") (pintype "passive"))
    )
    (net (code "407") (name "unconnected-(JP1007-1-PadP$3)") (class "Default")
      (node (ref "JP1007") (pin "P$3") (pinfunction "1_P$3") (pintype "passive"))
    )
    (net (code "408") (name "unconnected-(JP1008-1-PadP$3)") (class "Default")
      (node (ref "JP1008") (pin "P$3") (pinfunction "1_P$3") (pintype "passive"))
    )
    (net (code "409") (name "unconnected-(JP1009-1-PadP$3)") (class "Default")
      (node (ref "JP1009") (pin "P$3") (pinfunction "1_P$3") (pintype "passive"))
    )
    (net (code "410") (name "unconnected-(JP1010-1-PadP$3)") (class "Default")
      (node (ref "JP1010") (pin "P$3") (pinfunction "1_P$3") (pintype "passive"))
    )
    (net (code "411") (name "unconnected-(JP1011-1-PadP$3)") (class "Default")
      (node (ref "JP1011") (pin "P$3") (pinfunction "1_P$3") (pintype "passive"))
    )
    (net (code "412") (name "unconnected-(JP1012-1-PadP$3)") (class "Default")
      (node (ref "JP1012") (pin "P$3") (pinfunction "1_P$3") (pintype "passive"))
    )
    (net (code "413") (name "unconnected-(JP1013-1-PadP$3)") (class "Default")
      (node (ref "JP1013") (pin "P$3") (pinfunction "1_P$3") (pintype "passive"))
    )
    (net (code "414") (name "unconnected-(JP1014-1-PadP$3)") (class "Default")
      (node (ref "JP1014") (pin "P$3") (pinfunction "1_P$3") (pintype "passive"))
    )
    (net (code "415") (name "unconnected-(JP1015-1-PadP$3)") (class "Default")
      (node (ref "JP1015") (pin "P$3") (pinfunction "1_P$3") (pintype "passive"))
    )
    (net (code "416") (name "unconnected-(JP1016-1-PadP$3)") (class "Default")
      (node (ref "JP1016") (pin "P$3") (pinfunction "1_P$3") (pintype "passive"))
    )
    (net (code "417") (name "unconnected-(JP1017-1-PadP$3)") (class "Default")
      (node (ref "JP1017") (pin "P$3") (pinfunction "1_P$3") (pintype "passive"))
    )
    (net (code "418") (name "unconnected-(JP1018-1-PadP$3)") (class "Default")
      (node (ref "JP1018") (pin "P$3") (pinfunction "1_P$3") (pintype "passive"))
    )
    (net (code "419") (name "unconnected-(JP1019-1-PadP$3)") (class "Default")
      (node (ref "JP1019") (pin "P$3") (pinfunction "1_P$3") (pintype "passive"))
    )
    (net (code "420") (name "unconnected-(JP1020-1-PadP$3)") (class "Default")
      (node (ref "JP1020") (pin "P$3") (pinfunction "1_P$3") (pintype "passive"))
    )
    (net (code "421") (name "unconnected-(JP1021-1-PadP$3)") (class "Default")
      (node (ref "JP1021") (pin "P$3") (pinfunction "1_P$3") (pintype "passive"))
    )
    (net (code "422") (name "unconnected-(JP1022-1-PadP$3)") (class "Default")
      (node (ref "JP1022") (pin "P$3") (pinfunction "1_P$3") (pintype "passive"))
    )
    (net (code "423") (name "unconnected-(JP1023-1-PadP$3)") (class "Default")
      (node (ref "JP1023") (pin "P$3") (pinfunction "1_P$3") (pintype "passive"))
    )
    (net (code "424") (name "unconnected-(JP1024-1-PadP$3)") (class "Default")
      (node (ref "JP1024") (pin "P$3") (pinfunction "1_P$3") (pintype "passive"))
    )
    (net (code "425") (name "unconnected-(JP1025-1-PadP$3)") (class "Default")
      (node (ref "JP1025") (pin "P$3") (pinfunction "1_P$3") (pintype "passive"))
    )
    (net (code "426") (name "unconnected-(JP1026-1-PadP$3)") (class "Default")
      (node (ref "JP1026") (pin "P$3") (pinfunction "1_P$3") (pintype "passive"))
    )
    (net (code "427") (name "unconnected-(JP1027-1-PadP$3)") (class "Default")
      (node (ref "JP1027") (pin "P$3") (pinfunction "1_P$3") (pintype "passive"))
    )
    (net (code "428") (name "unconnected-(JP1028-1-PadP$3)") (class "Default")
      (node (ref "JP1028") (pin "P$3") (pinfunction "1_P$3") (pintype "passive"))
    )
    (net (code "429") (name "unconnected-(JP1029-1-PadP$3)") (class "Default")
      (node (ref "JP1029") (pin "P$3") (pinfunction "1_P$3") (pintype "passive"))
    )
    (net (code "430") (name "unconnected-(JP1030-1-PadP$3)") (class "Default")
      (node (ref "JP1030") (pin "P$3") (pinfunction "1_P$3") (pintype "passive"))
    )
    (net (code "431") (name "unconnected-(JP1031-1-PadP$3)") (class "Default")
      (node (ref "JP1031") (pin "P$3") (pinfunction "1_P$3") (pintype "passive"))
    )
    (net (code "432") (name "unconnected-(JP1032-1-PadP$3)") (class "Default")
      (node (ref "JP1032") (pin "P$3") (pinfunction "1_P$3") (pintype "passive"))
    )
    (net (code "433") (name "unconnected-(JP1033-1-PadP$3)") (class "Default")
      (node (ref "JP1033") (pin "P$3") (pinfunction "1_P$3") (pintype "passive"))
    )
    (net (code "434") (name "unconnected-(JP1034-1-PadP$3)") (class "Default")
      (node (ref "JP1034") (pin "P$3") (pinfunction "1_P$3") (pintype "passive"))
    )
    (net (code "435") (name "unconnected-(JP1035-1-PadP$3)") (class "Default")
      (node (ref "JP1035") (pin "P$3") (pinfunction "1_P$3") (pintype "passive"))
    )
    (net (code "436") (name "unconnected-(JP1036-1-PadP$3)") (class "Default")
      (node (ref "JP1036") (pin "P$3") (pinfunction "1_P$3") (pintype "passive"))
    )
    (net (code "437") (name "unconnected-(JP1037-1-PadP$3)") (class "Default")
      (node (ref "JP1037") (pin "P$3") (pinfunction "1_P$3") (pintype "passive"))
    )
    (net (code "438") (name "unconnected-(JP1038-1-PadP$3)") (class "Default")
      (node (ref "JP1038") (pin "P$3") (pinfunction "1_P$3") (pintype "passive"))
    )
    (net (code "439") (name "unconnected-(JP1039-1-PadP$3)") (class "Default")
      (node (ref "JP1039") (pin "P$3") (pinfunction "1_P$3") (pintype "passive"))
    )
    (net (code "440") (name "unconnected-(JP1040-1-PadP$3)") (class "Default")
      (node (ref "JP1040") (pin "P$3") (pinfunction "1_P$3") (pintype "passive"))
    )
    (net (code "441") (name "unconnected-(JP1041-1-PadP$3)") (class "Default")
      (node (ref "JP1041") (pin "P$3") (pinfunction "1_P$3") (pintype "passive"))
    )
    (net (code "442") (name "unconnected-(JP1042-1-PadP$3)") (class "Default")
      (node (ref "JP1042") (pin "P$3") (pinfunction "1_P$3") (pintype "passive"))
    )
    (net (code "443") (name "unconnected-(JP1043-1-PadP$3)") (class "Default")
      (node (ref "JP1043") (pin "P$3") (pinfunction "1_P$3") (pintype "passive"))
    )
    (net (code "444") (name "unconnected-(JP1044-1-PadP$3)") (class "Default")
      (node (ref "JP1044") (pin "P$3") (pinfunction "1_P$3") (pintype "passive"))
    )
    (net (code "445") (name "unconnected-(JP1045-1-PadP$3)") (class "Default")
      (node (ref "JP1045") (pin "P$3") (pinfunction "1_P$3") (pintype "passive"))
    )
    (net (code "446") (name "unconnected-(JP1046-1-PadP$3)") (class "Default")
      (node (ref "JP1046") (pin "P$3") (pinfunction "1_P$3") (pintype "passive"))
    )
    (net (code "447") (name "unconnected-(JP1047-1-PadP$3)") (class "Default")
      (node (ref "JP1047") (pin "P$3") (pinfunction "1_P$3") (pintype "passive"))
    )
    (net (code "448") (name "unconnected-(JP1048-1-PadP$3)") (class "Default")
      (node (ref "JP1048") (pin "P$3") (pinfunction "1_P$3") (pintype "passive"))
    )
    (net (code "449") (name "unconnected-(JP1049-1-PadP$3)") (class "Default")
      (node (ref "JP1049") (pin "P$3") (pinfunction "1_P$3") (pintype "passive"))
    )
    (net (code "450") (name "unconnected-(JP1050-1-PadP$3)") (class "Default")
      (node (ref "JP1050") (pin "P$3") (pinfunction "1_P$3") (pintype "passive"))
    )
    (net (code "451") (name "unconnected-(JP1051-1-PadP$3)") (class "Default")
      (node (ref "JP1051") (pin "P$3") (pinfunction "1_P$3") (pintype "passive"))
    )
    (net (code "452") (name "unconnected-(JP1052-1-PadP$3)") (class "Default")
      (node (ref "JP1052") (pin "P$3") (pinfunction "1_P$3") (pintype "passive"))
    )
    (net (code "453") (name "unconnected-(JP1053-1-PadP$3)") (class "Default")
      (node (ref "JP1053") (pin "P$3") (pinfunction "1_P$3") (pintype "passive"))
    )
    (net (code "454") (name "unconnected-(JP1054-1-PadP$3)") (class "Default")
      (node (ref "JP1054") (pin "P$3") (pinfunction "1_P$3") (pintype "passive"))
    )
    (net (code "455") (name "unconnected-(JP1055-1-PadP$3)") (class "Default")
      (node (ref "JP1055") (pin "P$3") (pinfunction "1_P$3") (pintype "passive"))
    )
    (net (code "456") (name "unconnected-(JP1056-1-PadP$3)") (class "Default")
      (node (ref "JP1056") (pin "P$3") (pinfunction "1_P$3") (pintype "passive"))
    )
    (net (code "457") (name "unconnected-(JP1057-1-PadP$3)") (class "Default")
      (node (ref "JP1057") (pin "P$3") (pinfunction "1_P$3") (pintype "passive"))
    )
    (net (code "458") (name "unconnected-(JP1058-1-PadP$3)") (class "Default")
      (node (ref "JP1058") (pin "P$3") (pinfunction "1_P$3") (pintype "passive"))
    )
    (net (code "459") (name "unconnected-(JP1059-1-PadP$3)") (class "Default")
      (node (ref "JP1059") (pin "P$3") (pinfunction "1_P$3") (pintype "passive"))
    )
    (net (code "460") (name "unconnected-(JP1060-1-PadP$3)") (class "Default")
      (node (ref "JP1060") (pin "P$3") (pinfunction "1_P$3") (pintype "passive"))
    )
    (net (code "461") (name "unconnected-(JP1061-1-PadP$3)") (class "Default")
      (node (ref "JP1061") (pin "P$3") (pinfunction "1_P$3") (pintype "passive"))
    )
    (net (code "462") (name "unconnected-(JP1062-1-PadP$3)") (class "Default")
      (node (ref "JP1062") (pin "P$3") (pinfunction "1_P$3") (pintype "passive"))
    )
    (net (code "463") (name "unconnected-(JP1063-1-PadP$3)") (class "Default")
      (node (ref "JP1063") (pin "P$3") (pinfunction "1_P$3") (pintype "passive"))
    )
    (net (code "464") (name "unconnected-(JP1064-1-PadP$3)") (class "Default")
      (node (ref "JP1064") (pin "P$3") (pinfunction "1_P$3") (pintype "passive"))
    )
    (net (code "465") (name "unconnected-(JP1065-1-PadP$3)") (class "Default")
      (node (ref "JP1065") (pin "P$3") (pinfunction "1_P$3") (pintype "passive"))
    )
    (net (code "466") (name "unconnected-(JP1066-1-PadP$3)") (class "Default")
      (node (ref "JP1066") (pin "P$3") (pinfunction "1_P$3") (pintype "passive"))
    )
    (net (code "467") (name "unconnected-(JP1067-1-PadP$3)") (class "Default")
      (node (ref "JP1067") (pin "P$3") (pinfunction "1_P$3") (pintype "passive"))
    )
    (net (code "468") (name "unconnected-(JP1068-1-PadP$3)") (class "Default")
      (node (ref "JP1068") (pin "P$3") (pinfunction "1_P$3") (pintype "passive"))
    )
    (net (code "469") (name "unconnected-(JP1069-1-PadP$3)") (class "Default")
      (node (ref "JP1069") (pin "P$3") (pinfunction "1_P$3") (pintype "passive"))
    )
    (net (code "470") (name "unconnected-(JP1070-1-PadP$3)") (class "Default")
      (node (ref "JP1070") (pin "P$3") (pinfunction "1_P$3") (pintype "passive"))
    )
    (net (code "471") (name "unconnected-(JP1071-1-PadP$3)") (class "Default")
      (node (ref "JP1071") (pin "P$3") (pinfunction "1_P$3") (pintype "passive"))
    )
    (net (code "472") (name "unconnected-(JP1072-1-PadP$3)") (class "Default")
      (node (ref "JP1072") (pin "P$3") (pinfunction "1_P$3") (pintype "passive"))
    )
    (net (code "473") (name "unconnected-(JP1073-1-PadP$3)") (class "Default")
      (node (ref "JP1073") (pin "P$3") (pinfunction "1_P$3") (pintype "passive"))
    )
    (net (code "474") (name "unconnected-(JP1074-1-PadP$3)") (class "Default")
      (node (ref "JP1074") (pin "P$3") (pinfunction "1_P$3") (pintype "passive"))
    )
    (net (code "475") (name "unconnected-(JP1075-1-PadP$3)") (class "Default")
      (node (ref "JP1075") (pin "P$3") (pinfunction "1_P$3") (pintype "passive"))
    )
    (net (code "476") (name "unconnected-(JP1076-1-PadP$3)") (class "Default")
      (node (ref "JP1076") (pin "P$3") (pinfunction "1_P$3") (pintype "passive"))
    )
    (net (code "477") (name "unconnected-(JP1077-1-PadP$3)") (class "Default")
      (node (ref "JP1077") (pin "P$3") (pinfunction "1_P$3") (pintype "passive"))
    )
    (net (code "478") (name "unconnected-(JP1078-1-PadP$3)") (class "Default")
      (node (ref "JP1078") (pin "P$3") (pinfunction "1_P$3") (pintype "passive"))
    )
    (net (code "479") (name "unconnected-(JP1079-1-PadP$3)") (class "Default")
      (node (ref "JP1079") (pin "P$3") (pinfunction "1_P$3") (pintype "passive"))
    )
    (net (code "480") (name "unconnected-(JP1080-1-PadP$3)") (class "Default")
      (node (ref "JP1080") (pin "P$3") (pinfunction "1_P$3") (pintype "passive"))
    )
    (net (code "481") (name "unconnected-(JP1081-1-PadP$3)") (class "Default")
      (node (ref "JP1081") (pin "P$3") (pinfunction "1_P$3") (pintype "passive"))
    )
    (net (code "482") (name "unconnected-(JP1082-1-PadP$3)") (class "Default")
      (node (ref "JP1082") (pin "P$3") (pinfunction "1_P$3") (pintype "passive"))
    )
    (net (code "483") (name "unconnected-(JP1083-1-PadP$3)") (class "Default")
      (node (ref "JP1083") (pin "P$3") (pinfunction "1_P$3") (pintype "passive"))
    )
    (net (code "484") (name "unconnected-(JP1084-1-PadP$3)") (class "Default")
      (node (ref "JP1084") (pin "P$3") (pinfunction "1_P$3") (pintype "passive"))
    )
    (net (code "485") (name "unconnected-(JP1085-1-PadP$3)") (class "Default")
      (node (ref "JP1085") (pin "P$3") (pinfunction "1_P$3") (pintype "passive"))
    )
    (net (code "486") (name "unconnected-(JP1086-1-PadP$3)") (class "Default")
      (node (ref "JP1086") (pin "P$3") (pinfunction "1_P$3") (pintype "passive"))
    )
    (net (code "487") (name "unconnected-(JP1087-1-PadP$3)") (class "Default")
      (node (ref "JP1087") (pin "P$3") (pinfunction "1_P$3") (pintype "passive"))
    )
    (net (code "488") (name "unconnected-(JP1088-1-PadP$3)") (class "Default")
      (node (ref "JP1088") (pin "P$3") (pinfunction "1_P$3") (pintype "passive"))
    )
    (net (code "489") (name "unconnected-(JP1089-1-PadP$3)") (class "Default")
      (node (ref "JP1089") (pin "P$3") (pinfunction "1_P$3") (pintype "passive"))
    )
    (net (code "490") (name "unconnected-(JP1090-1-PadP$3)") (class "Default")
      (node (ref "JP1090") (pin "P$3") (pinfunction "1_P$3") (pintype "passive"))
    )
    (net (code "491") (name "unconnected-(JP1091-1-PadP$3)") (class "Default")
      (node (ref "JP1091") (pin "P$3") (pinfunction "1_P$3") (pintype "passive"))
    )
    (net (code "492") (name "unconnected-(JP1092-1-PadP$3)") (class "Default")
      (node (ref "JP1092") (pin "P$3") (pinfunction "1_P$3") (pintype "passive"))
    )
    (net (code "493") (name "unconnected-(JP1093-1-PadP$3)") (class "Default")
      (node (ref "JP1093") (pin "P$3") (pinfunction "1_P$3") (pintype "passive"))
    )
    (net (code "494") (name "unconnected-(JP1094-1-PadP$3)") (class "Default")
      (node (ref "JP1094") (pin "P$3") (pinfunction "1_P$3") (pintype "passive"))
    )
    (net (code "495") (name "unconnected-(JP1095-1-PadP$3)") (class "Default")
      (node (ref "JP1095") (pin "P$3") (pinfunction "1_P$3") (pintype "passive"))
    )
    (net (code "496") (name "unconnected-(JP1096-1-PadP$3)") (class "Default")
      (node (ref "JP1096") (pin "P$3") (pinfunction "1_P$3") (pintype "passive"))
    )
    (net (code "497") (name "unconnected-(JP1097-1-PadP$3)") (class "Default")
      (node (ref "JP1097") (pin "P$3") (pinfunction "1_P$3") (pintype "passive"))
    )
    (net (code "498") (name "unconnected-(JP1098-1-PadP$3)") (class "Default")
      (node (ref "JP1098") (pin "P$3") (pinfunction "1_P$3") (pintype "passive"))
    )
    (net (code "499") (name "unconnected-(JP1099-1-PadP$3)") (class "Default")
      (node (ref "JP1099") (pin "P$3") (pinfunction "1_P$3") (pintype "passive"))
    )
    (net (code "500") (name "unconnected-(JP1100-1-PadP$3)") (class "Default")
      (node (ref "JP1100") (pin "P$3") (pinfunction "1_P$3") (pintype "passive"))
    )
    (net (code "501") (name "unconnected-(JP1101-1-PadP$3)") (class "Default")
      (node (ref "JP1101") (pin "P$3") (pinfunction "1_P$3") (pintype "passive"))
    )
    (net (code "502") (name "unconnected-(JP1102-1-PadP$3)") (class "Default")
      (node (ref "JP1102") (pin "P$3") (pinfunction "1_P$3") (pintype "passive"))
    )
    (net (code "503") (name "unconnected-(JP1103-1-PadP$3)") (class "Default")
      (node (ref "JP1103") (pin "P$3") (pinfunction "1_P$3") (pintype "passive"))
    )
    (net (code "504") (name "unconnected-(JP1104-1-PadP$3)") (class "Default")
      (node (ref "JP1104") (pin "P$3") (pinfunction "1_P$3") (pintype "passive"))
    )
    (net (code "505") (name "unconnected-(JP1105-1-PadP$3)") (class "Default")
      (node (ref "JP1105") (pin "P$3") (pinfunction "1_P$3") (pintype "passive"))
    )
    (net (code "506") (name "unconnected-(JP1106-1-PadP$3)") (class "Default")
      (node (ref "JP1106") (pin "P$3") (pinfunction "1_P$3") (pintype "passive"))
    )
    (net (code "507") (name "unconnected-(JP1107-1-PadP$3)") (class "Default")
      (node (ref "JP1107") (pin "P$3") (pinfunction "1_P$3") (pintype "passive"))
    )
    (net (code "508") (name "unconnected-(JP1108-1-PadP$3)") (class "Default")
      (node (ref "JP1108") (pin "P$3") (pinfunction "1_P$3") (pintype "passive"))
    )
    (net (code "509") (name "unconnected-(JP1109-1-PadP$3)") (class "Default")
      (node (ref "JP1109") (pin "P$3") (pinfunction "1_P$3") (pintype "passive"))
    )
    (net (code "510") (name "unconnected-(JP1110-1-PadP$3)") (class "Default")
      (node (ref "JP1110") (pin "P$3") (pinfunction "1_P$3") (pintype "passive"))
    )
    (net (code "511") (name "unconnected-(JP1111-1-PadP$3)") (class "Default")
      (node (ref "JP1111") (pin "P$3") (pinfunction "1_P$3") (pintype "passive"))
    )
    (net (code "512") (name "unconnected-(JP1112-1-PadP$3)") (class "Default")
      (node (ref "JP1112") (pin "P$3") (pinfunction "1_P$3") (pintype "passive"))
    )
    (net (code "513") (name "unconnected-(JP1113-1-PadP$3)") (class "Default")
      (node (ref "JP1113") (pin "P$3") (pinfunction "1_P$3") (pintype "passive"))
    )
    (net (code "514") (name "unconnected-(JP1114-1-PadP$3)") (class "Default")
      (node (ref "JP1114") (pin "P$3") (pinfunction "1_P$3") (pintype "passive"))
    )
    (net (code "515") (name "unconnected-(JP1115-1-PadP$3)") (class "Default")
      (node (ref "JP1115") (pin "P$3") (pinfunction "1_P$3") (pintype "passive"))
    )
    (net (code "516") (name "unconnected-(JP1116-1-PadP$3)") (class "Default")
      (node (ref "JP1116") (pin "P$3") (pinfunction "1_P$3") (pintype "passive"))
    )
    (net (code "517") (name "unconnected-(JP1117-1-PadP$3)") (class "Default")
      (node (ref "JP1117") (pin "P$3") (pinfunction "1_P$3") (pintype "passive"))
    )
    (net (code "518") (name "unconnected-(JP1118-1-PadP$3)") (class "Default")
      (node (ref "JP1118") (pin "P$3") (pinfunction "1_P$3") (pintype "passive"))
    )
    (net (code "519") (name "unconnected-(JP1119-1-PadP$3)") (class "Default")
      (node (ref "JP1119") (pin "P$3") (pinfunction "1_P$3") (pintype "passive"))
    )
    (net (code "520") (name "unconnected-(JP1120-1-PadP$3)") (class "Default")
      (node (ref "JP1120") (pin "P$3") (pinfunction "1_P$3") (pintype "passive"))
    )
    (net (code "521") (name "unconnected-(JP1121-1-PadP$3)") (class "Default")
      (node (ref "JP1121") (pin "P$3") (pinfunction "1_P$3") (pintype "passive"))
    )
    (net (code "522") (name "unconnected-(JP1122-1-PadP$3)") (class "Default")
      (node (ref "JP1122") (pin "P$3") (pinfunction "1_P$3") (pintype "passive"))
    )
    (net (code "523") (name "unconnected-(JP1123-1-PadP$3)") (class "Default")
      (node (ref "JP1123") (pin "P$3") (pinfunction "1_P$3") (pintype "passive"))
    )
    (net (code "524") (name "unconnected-(JP1124-1-PadP$3)") (class "Default")
      (node (ref "JP1124") (pin "P$3") (pinfunction "1_P$3") (pintype "passive"))
    )
    (net (code "525") (name "unconnected-(JP1125-1-PadP$3)") (class "Default")
      (node (ref "JP1125") (pin "P$3") (pinfunction "1_P$3") (pintype "passive"))
    )
    (net (code "526") (name "unconnected-(JP1126-1-PadP$3)") (class "Default")
      (node (ref "JP1126") (pin "P$3") (pinfunction "1_P$3") (pintype "passive"))
    )
    (net (code "527") (name "unconnected-(JP1127-1-PadP$3)") (class "Default")
      (node (ref "JP1127") (pin "P$3") (pinfunction "1_P$3") (pintype "passive"))
    )
    (net (code "528") (name "unconnected-(JP1128-1-PadP$3)") (class "Default")
      (node (ref "JP1128") (pin "P$3") (pinfunction "1_P$3") (pintype "passive"))
    )
    (net (code "529") (name "unconnected-(JP1129-1-PadP$3)") (class "Default")
      (node (ref "JP1129") (pin "P$3") (pinfunction "1_P$3") (pintype "passive"))
    )
    (net (code "530") (name "unconnected-(JP1130-1-PadP$3)") (class "Default")
      (node (ref "JP1130") (pin "P$3") (pinfunction "1_P$3") (pintype "passive"))
    )
    (net (code "531") (name "unconnected-(JP1131-1-PadP$3)") (class "Default")
      (node (ref "JP1131") (pin "P$3") (pinfunction "1_P$3") (pintype "passive"))
    )
    (net (code "532") (name "unconnected-(JP1132-1-PadP$3)") (class "Default")
      (node (ref "JP1132") (pin "P$3") (pinfunction "1_P$3") (pintype "passive"))
    )
    (net (code "533") (name "unconnected-(JP1133-1-PadP$3)") (class "Default")
      (node (ref "JP1133") (pin "P$3") (pinfunction "1_P$3") (pintype "passive"))
    )
    (net (code "534") (name "unconnected-(JP1134-1-PadP$3)") (class "Default")
      (node (ref "JP1134") (pin "P$3") (pinfunction "1_P$3") (pintype "passive"))
    )
    (net (code "535") (name "unconnected-(JP1135-1-PadP$3)") (class "Default")
      (node (ref "JP1135") (pin "P$3") (pinfunction "1_P$3") (pintype "passive"))
    )
    (net (code "536") (name "unconnected-(JP1136-1-PadP$3)") (class "Default")
      (node (ref "JP1136") (pin "P$3") (pinfunction "1_P$3") (pintype "passive"))
    )
    (net (code "537") (name "unconnected-(JP1137-1-PadP$3)") (class "Default")
      (node (ref "JP1137") (pin "P$3") (pinfunction "1_P$3") (pintype "passive"))
    )
    (net (code "538") (name "unconnected-(JP1138-1-PadP$3)") (class "Default")
      (node (ref "JP1138") (pin "P$3") (pinfunction "1_P$3") (pintype "passive"))
    )
    (net (code "539") (name "unconnected-(JP1139-1-PadP$3)") (class "Default")
      (node (ref "JP1139") (pin "P$3") (pinfunction "1_P$3") (pintype "passive"))
    )
    (net (code "540") (name "unconnected-(JP1140-1-PadP$3)") (class "Default")
      (node (ref "JP1140") (pin "P$3") (pinfunction "1_P$3") (pintype "passive"))
    )
    (net (code "541") (name "unconnected-(JP1141-1-PadP$3)") (class "Default")
      (node (ref "JP1141") (pin "P$3") (pinfunction "1_P$3") (pintype "passive"))
    )
    (net (code "542") (name "unconnected-(JP1142-1-PadP$3)") (class "Default")
      (node (ref "JP1142") (pin "P$3") (pinfunction "1_P$3") (pintype "passive"))
    )
    (net (code "543") (name "unconnected-(JP1143-1-PadP$3)") (class "Default")
      (node (ref "JP1143") (pin "P$3") (pinfunction "1_P$3") (pintype "passive"))
    )
    (net (code "544") (name "unconnected-(JP1144-1-PadP$3)") (class "Default")
      (node (ref "JP1144") (pin "P$3") (pinfunction "1_P$3") (pintype "passive"))
    )
    (net (code "545") (name "unconnected-(JP1145-1-PadP$3)") (class "Default")
      (node (ref "JP1145") (pin "P$3") (pinfunction "1_P$3") (pintype "passive"))
    )
    (net (code "546") (name "unconnected-(JP1146-1-PadP$3)") (class "Default")
      (node (ref "JP1146") (pin "P$3") (pinfunction "1_P$3") (pintype "passive"))
    )
    (net (code "547") (name "unconnected-(JP1147-1-PadP$3)") (class "Default")
      (node (ref "JP1147") (pin "P$3") (pinfunction "1_P$3") (pintype "passive"))
    )
    (net (code "548") (name "unconnected-(JP1148-1-PadP$3)") (class "Default")
      (node (ref "JP1148") (pin "P$3") (pinfunction "1_P$3") (pintype "passive"))
    )
    (net (code "549") (name "unconnected-(JP1149-1-PadP$3)") (class "Default")
      (node (ref "JP1149") (pin "P$3") (pinfunction "1_P$3") (pintype "passive"))
    )
    (net (code "550") (name "unconnected-(JP1150-1-PadP$3)") (class "Default")
      (node (ref "JP1150") (pin "P$3") (pinfunction "1_P$3") (pintype "passive"))
    )
    (net (code "551") (name "unconnected-(JP1151-1-PadP$3)") (class "Default")
      (node (ref "JP1151") (pin "P$3") (pinfunction "1_P$3") (pintype "passive"))
    )
    (net (code "552") (name "unconnected-(JP1152-1-PadP$3)") (class "Default")
      (node (ref "JP1152") (pin "P$3") (pinfunction "1_P$3") (pintype "passive"))
    )
    (net (code "553") (name "unconnected-(JP1153-1-PadP$3)") (class "Default")
      (node (ref "JP1153") (pin "P$3") (pinfunction "1_P$3") (pintype "passive"))
    )
    (net (code "554") (name "unconnected-(JP1154-1-PadP$3)") (class "Default")
      (node (ref "JP1154") (pin "P$3") (pinfunction "1_P$3") (pintype "passive"))
    )
    (net (code "555") (name "unconnected-(JP1155-1-PadP$3)") (class "Default")
      (node (ref "JP1155") (pin "P$3") (pinfunction "1_P$3") (pintype "passive"))
    )
    (net (code "556") (name "unconnected-(JP1156-1-PadP$3)") (class "Default")
      (node (ref "JP1156") (pin "P$3") (pinfunction "1_P$3") (pintype "passive"))
    )
    (net (code "557") (name "unconnected-(JP1157-1-PadP$3)") (class "Default")
      (node (ref "JP1157") (pin "P$3") (pinfunction "1_P$3") (pintype "passive"))
    )
    (net (code "558") (name "unconnected-(JP1158-1-PadP$3)") (class "Default")
      (node (ref "JP1158") (pin "P$3") (pinfunction "1_P$3") (pintype "passive"))
    )
    (net (code "559") (name "unconnected-(JP1159-1-PadP$3)") (class "Default")
      (node (ref "JP1159") (pin "P$3") (pinfunction "1_P$3") (pintype "passive"))
    )
    (net (code "560") (name "unconnected-(JP1160-1-PadP$3)") (class "Default")
      (node (ref "JP1160") (pin "P$3") (pinfunction "1_P$3") (pintype "passive"))
    )
    (net (code "561") (name "unconnected-(JP1161-1-PadP$3)") (class "Default")
      (node (ref "JP1161") (pin "P$3") (pinfunction "1_P$3") (pintype "passive"))
    )
    (net (code "562") (name "unconnected-(JP1162-1-PadP$3)") (class "Default")
      (node (ref "JP1162") (pin "P$3") (pinfunction "1_P$3") (pintype "passive"))
    )
    (net (code "563") (name "unconnected-(JP1163-1-PadP$3)") (class "Default")
      (node (ref "JP1163") (pin "P$3") (pinfunction "1_P$3") (pintype "passive"))
    )
    (net (code "564") (name "unconnected-(JP1164-1-PadP$3)") (class "Default")
      (node (ref "JP1164") (pin "P$3") (pinfunction "1_P$3") (pintype "passive"))
    )
    (net (code "565") (name "unconnected-(JP1165-1-PadP$3)") (class "Default")
      (node (ref "JP1165") (pin "P$3") (pinfunction "1_P$3") (pintype "passive"))
    )
    (net (code "566") (name "unconnected-(JP1166-1-PadP$3)") (class "Default")
      (node (ref "JP1166") (pin "P$3") (pinfunction "1_P$3") (pintype "passive"))
    )
    (net (code "567") (name "unconnected-(JP1167-1-PadP$3)") (class "Default")
      (node (ref "JP1167") (pin "P$3") (pinfunction "1_P$3") (pintype "passive"))
    )
    (net (code "568") (name "unconnected-(JP1168-1-PadP$3)") (class "Default")
      (node (ref "JP1168") (pin "P$3") (pinfunction "1_P$3") (pintype "passive"))
    )
    (net (code "569") (name "unconnected-(JP1169-1-PadP$3)") (class "Default")
      (node (ref "JP1169") (pin "P$3") (pinfunction "1_P$3") (pintype "passive"))
    )
    (net (code "570") (name "unconnected-(JP1170-1-PadP$3)") (class "Default")
      (node (ref "JP1170") (pin "P$3") (pinfunction "1_P$3") (pintype "passive"))
    )
    (net (code "571") (name "unconnected-(JP1171-1-PadP$3)") (class "Default")
      (node (ref "JP1171") (pin "P$3") (pinfunction "1_P$3") (pintype "passive"))
    )
    (net (code "572") (name "unconnected-(JP1172-1-PadP$3)") (class "Default")
      (node (ref "JP1172") (pin "P$3") (pinfunction "1_P$3") (pintype "passive"))
    )
    (net (code "573") (name "unconnected-(JP1173-1-PadP$3)") (class "Default")
      (node (ref "JP1173") (pin "P$3") (pinfunction "1_P$3") (pintype "passive"))
    )
    (net (code "574") (name "unconnected-(JP1174-1-PadP$3)") (class "Default")
      (node (ref "JP1174") (pin "P$3") (pinfunction "1_P$3") (pintype "passive"))
    )
    (net (code "575") (name "unconnected-(JP1175-1-PadP$3)") (class "Default")
      (node (ref "JP1175") (pin "P$3") (pinfunction "1_P$3") (pintype "passive"))
    )
    (net (code "576") (name "unconnected-(JP1176-1-PadP$3)") (class "Default")
      (node (ref "JP1176") (pin "P$3") (pinfunction "1_P$3") (pintype "passive"))
    )
    (net (code "577") (name "unconnected-(JP1177-1-PadP$3)") (class "Default")
      (node (ref "JP1177") (pin "P$3") (pinfunction "1_P$3") (pintype "passive"))
    )
    (net (code "578") (name "unconnected-(JP1178-1-PadP$3)") (class "Default")
      (node (ref "JP1178") (pin "P$3") (pinfunction "1_P$3") (pintype "passive"))
    )
    (net (code "579") (name "unconnected-(JP1179-1-PadP$3)") (class "Default")
      (node (ref "JP1179") (pin "P$3") (pinfunction "1_P$3") (pintype "passive"))
    )
    (net (code "580") (name "unconnected-(JP1180-1-PadP$3)") (class "Default")
      (node (ref "JP1180") (pin "P$3") (pinfunction "1_P$3") (pintype "passive"))
    )
    (net (code "581") (name "unconnected-(JP1181-1-PadP$3)") (class "Default")
      (node (ref "JP1181") (pin "P$3") (pinfunction "1_P$3") (pintype "passive"))
    )
    (net (code "582") (name "unconnected-(JP1182-1-PadP$3)") (class "Default")
      (node (ref "JP1182") (pin "P$3") (pinfunction "1_P$3") (pintype "passive"))
    )
    (net (code "583") (name "unconnected-(JP1183-1-PadP$3)") (class "Default")
      (node (ref "JP1183") (pin "P$3") (pinfunction "1_P$3") (pintype "passive"))
    )
    (net (code "584") (name "unconnected-(JP1184-1-PadP$3)") (class "Default")
      (node (ref "JP1184") (pin "P$3") (pinfunction "1_P$3") (pintype "passive"))
    )
    (net (code "585") (name "unconnected-(JP1185-1-PadP$3)") (class "Default")
      (node (ref "JP1185") (pin "P$3") (pinfunction "1_P$3") (pintype "passive"))
    )
    (net (code "586") (name "unconnected-(JP1186-1-PadP$3)") (class "Default")
      (node (ref "JP1186") (pin "P$3") (pinfunction "1_P$3") (pintype "passive"))
    )
    (net (code "587") (name "unconnected-(JP1187-1-PadP$3)") (class "Default")
      (node (ref "JP1187") (pin "P$3") (pinfunction "1_P$3") (pintype "passive"))
    )
    (net (code "588") (name "unconnected-(JP1188-1-PadP$3)") (class "Default")
      (node (ref "JP1188") (pin "P$3") (pinfunction "1_P$3") (pintype "passive"))
    )
    (net (code "589") (name "unconnected-(JP1189-1-PadP$3)") (class "Default")
      (node (ref "JP1189") (pin "P$3") (pinfunction "1_P$3") (pintype "passive"))
    )
    (net (code "590") (name "unconnected-(JP1190-1-PadP$3)") (class "Default")
      (node (ref "JP1190") (pin "P$3") (pinfunction "1_P$3") (pintype "passive"))
    )
    (net (code "591") (name "unconnected-(JP1191-1-PadP$3)") (class "Default")
      (node (ref "JP1191") (pin "P$3") (pinfunction "1_P$3") (pintype "passive"))
    )
    (net (code "592") (name "unconnected-(JP1192-1-PadP$3)") (class "Default")
      (node (ref "JP1192") (pin "P$3") (pinfunction "1_P$3") (pintype "passive"))
    )
    (net (code "593") (name "unconnected-(JP1193-1-PadP$3)") (class "Default")
      (node (ref "JP1193") (pin "P$3") (pinfunction "1_P$3") (pintype "passive"))
    )
    (net (code "594") (name "unconnected-(JP1194-1-PadP$3)") (class "Default")
      (node (ref "JP1194") (pin "P$3") (pinfunction "1_P$3") (pintype "passive"))
    )
    (net (code "595") (name "unconnected-(JP1195-1-PadP$3)") (class "Default")
      (node (ref "JP1195") (pin "P$3") (pinfunction "1_P$3") (pintype "passive"))
    )
    (net (code "596") (name "unconnected-(JP1196-1-PadP$3)") (class "Default")
      (node (ref "JP1196") (pin "P$3") (pinfunction "1_P$3") (pintype "passive"))
    )
    (net (code "597") (name "unconnected-(JP1197-1-PadP$3)") (class "Default")
      (node (ref "JP1197") (pin "P$3") (pinfunction "1_P$3") (pintype "passive"))
    )
    (net (code "598") (name "unconnected-(JP1198-1-PadP$3)") (class "Default")
      (node (ref "JP1198") (pin "P$3") (pinfunction "1_P$3") (pintype "passive"))
    )
    (net (code "599") (name "unconnected-(JP1199-1-PadP$3)") (class "Default")
      (node (ref "JP1199") (pin "P$3") (pinfunction "1_P$3") (pintype "passive"))
    )
    (net (code "600") (name "unconnected-(JP1200-1-PadP$3)") (class "Default")
      (node (ref "JP1200") (pin "P$3") (pinfunction "1_P$3") (pintype "passive"))
    )
  )
)
